# omniproto.net
KiCad netlist of a schematic drawn in EAGLE
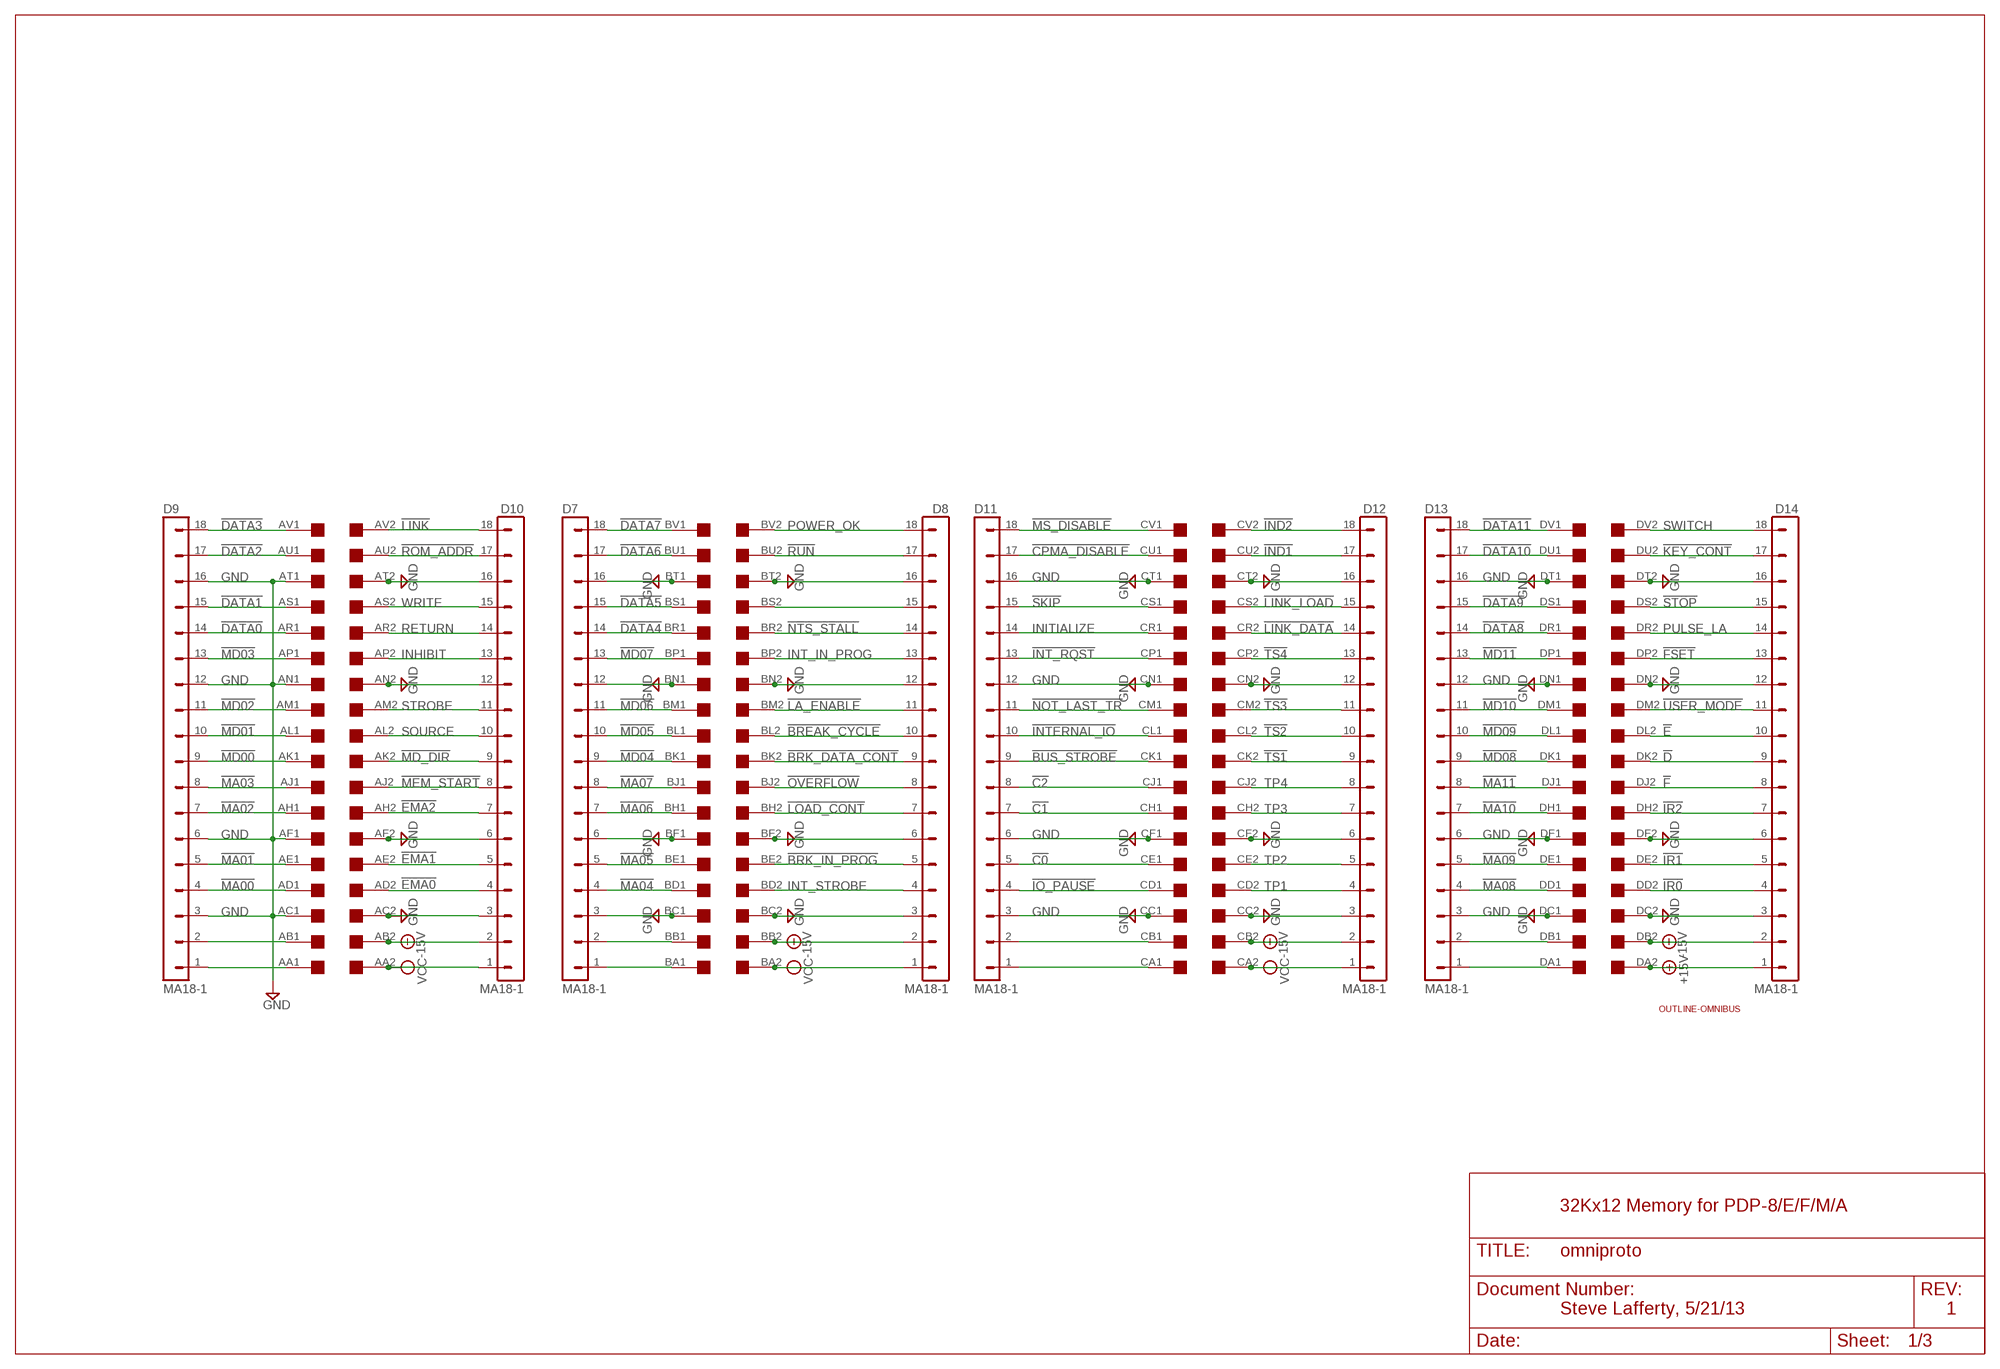
[diagram p0: schematic, sheet 1]
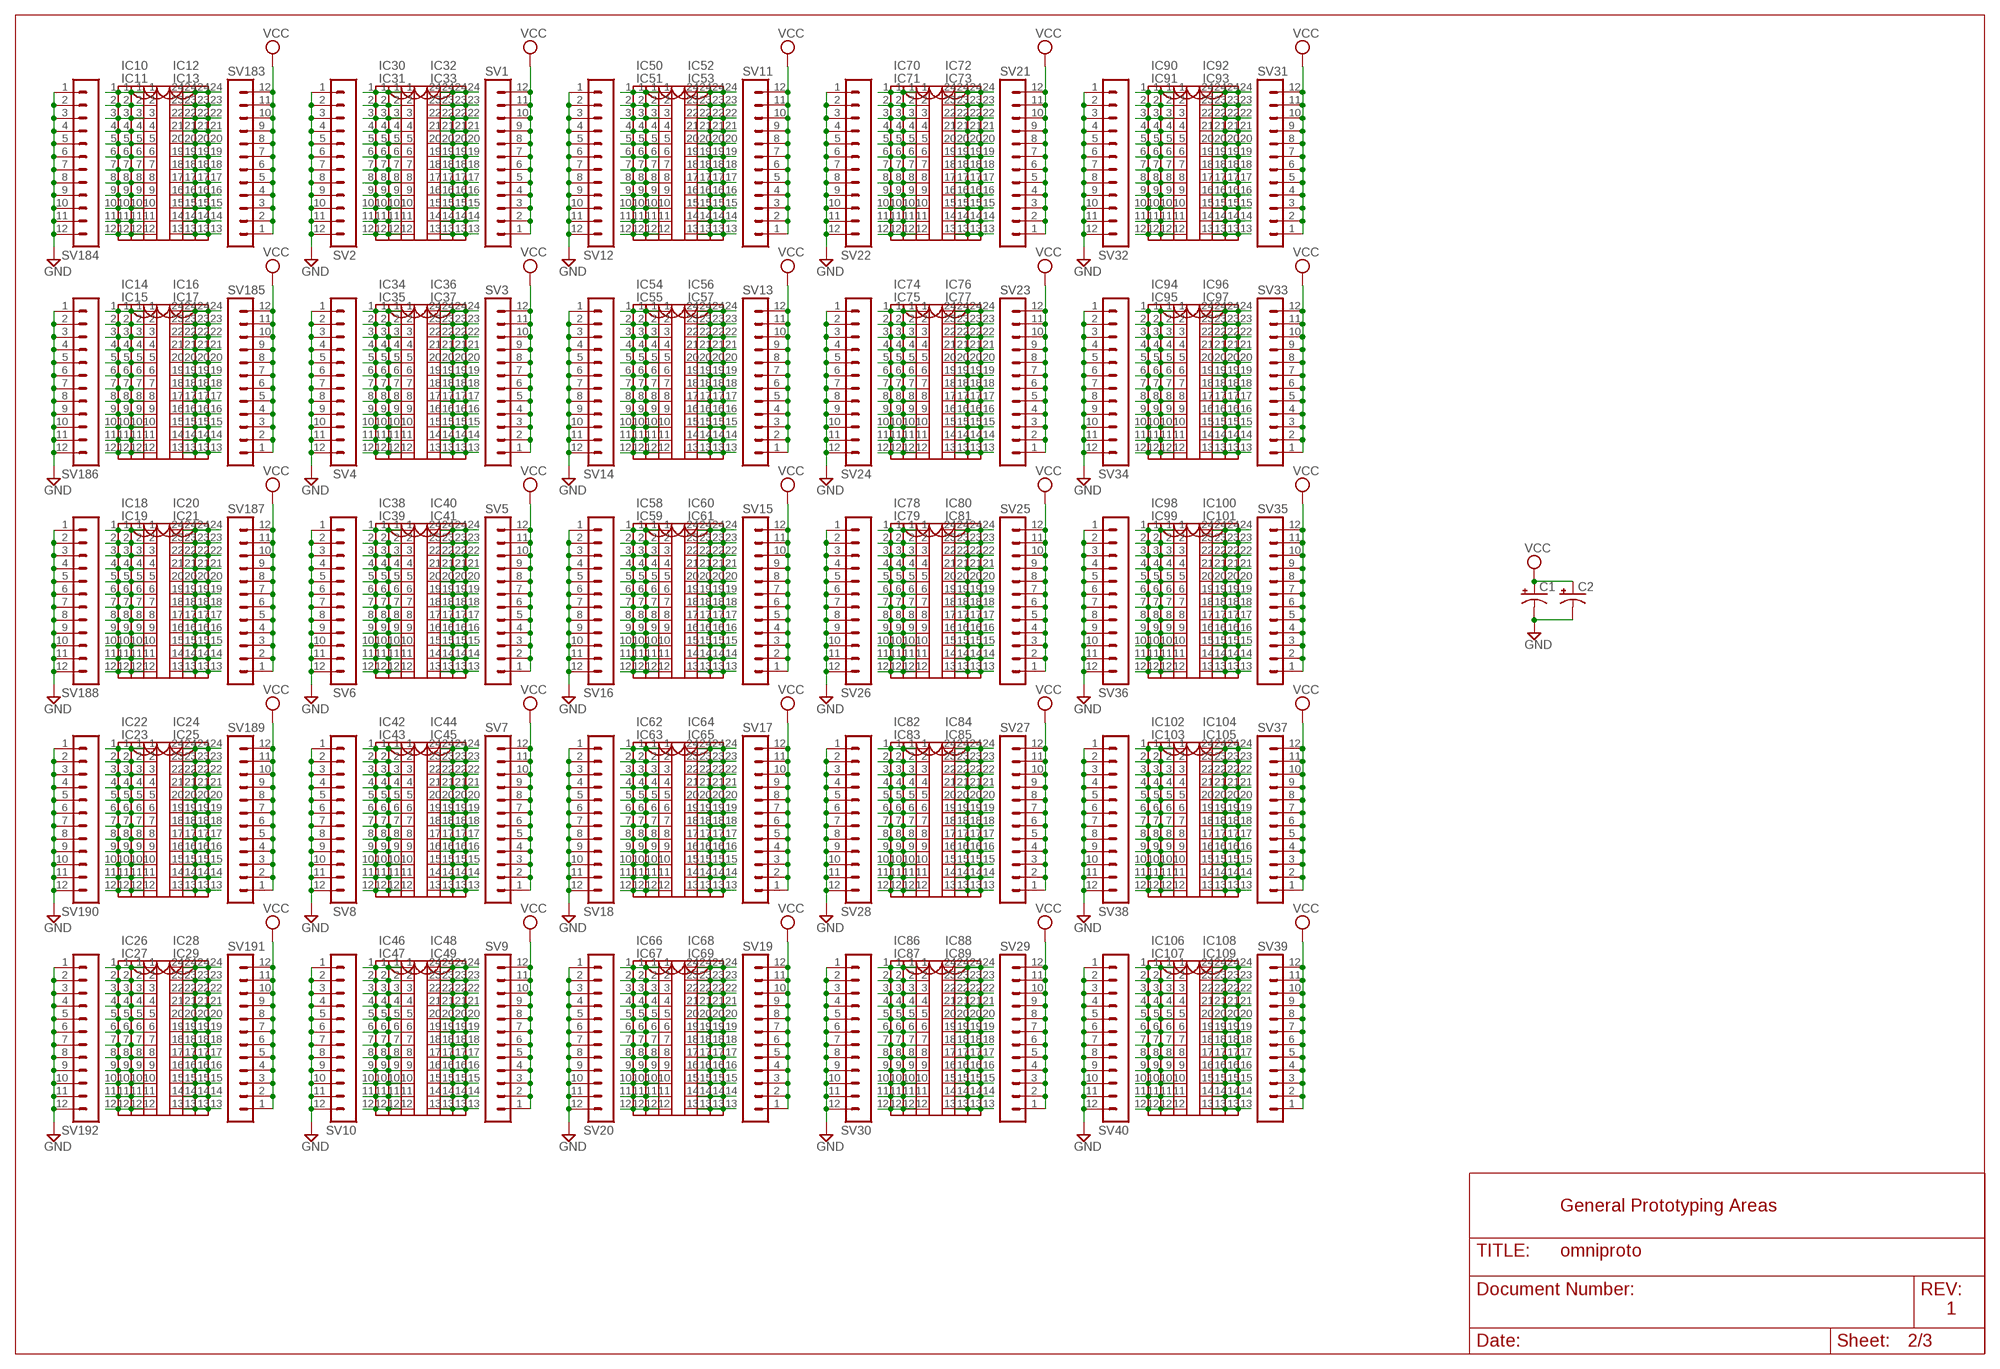
[diagram p1: schematic, sheet 2]
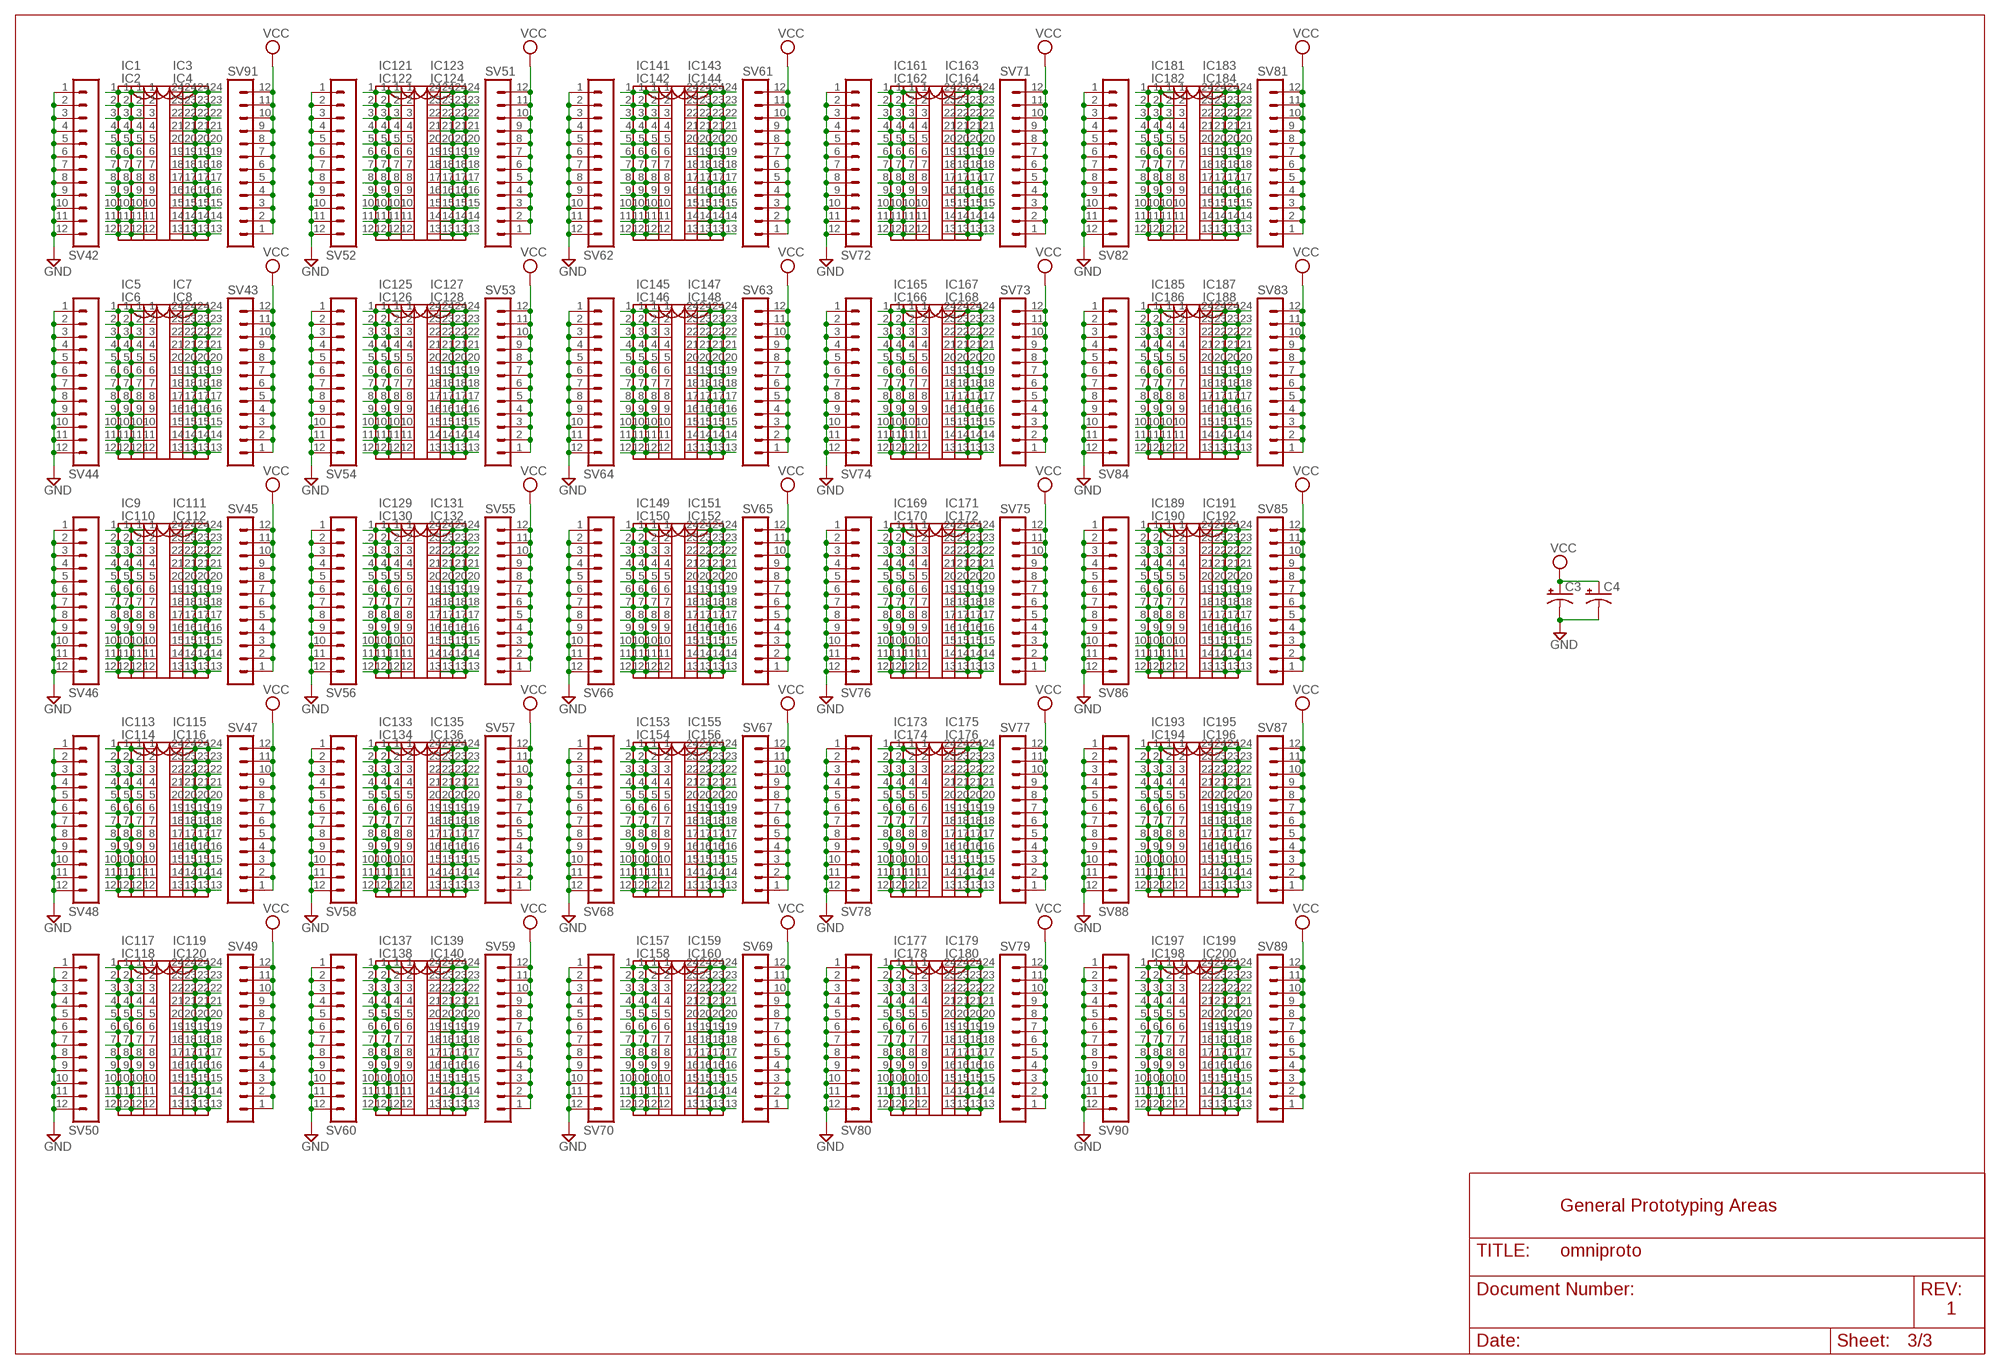
[diagram p2: schematic, sheet 3]

(export (version "E")
  (design (tool "Eeschema 10.0.6"))
  (components
    (comp (ref "D7")
      (value "MA18-1")
      (footprint "eagle-import:MA18-1")
      (libsource (lib "eagle-import") (part "MA18-1"))
    )
    (comp (ref "D8")
      (value "MA18-1")
      (footprint "eagle-import:MA18-1")
      (libsource (lib "eagle-import") (part "MA18-1"))
    )
    (comp (ref "D9")
      (value "MA18-1")
      (footprint "eagle-import:MA18-1")
      (libsource (lib "eagle-import") (part "MA18-1"))
    )
    (comp (ref "D10")
      (value "MA18-1")
      (footprint "eagle-import:MA18-1")
      (libsource (lib "eagle-import") (part "MA18-1"))
    )
    (comp (ref "D11")
      (value "MA18-1")
      (footprint "eagle-import:MA18-1")
      (libsource (lib "eagle-import") (part "MA18-1"))
    )
    (comp (ref "D12")
      (value "MA18-1")
      (footprint "eagle-import:MA18-1")
      (libsource (lib "eagle-import") (part "MA18-1"))
    )
    (comp (ref "D13")
      (value "MA18-1")
      (footprint "eagle-import:MA18-1")
      (libsource (lib "eagle-import") (part "MA18-1"))
    )
    (comp (ref "D14")
      (value "MA18-1")
      (footprint "eagle-import:MA18-1")
      (libsource (lib "eagle-import") (part "MA18-1"))
    )
    (comp (ref "U$1")
      (value "OUTLINE-OMNIBUS")
      (footprint "eagle-import:OMNIBUS")
      (libsource (lib "eagle-import") (part "OUTLINE-OMNIBUS"))
    )
    (comp (ref "U$2")
      (value "QUAD")
      (footprint "eagle-import:EDGE-CON8")
      (libsource (lib "eagle-import") (part "QUAD"))
    )
    (comp (ref "C3")
      (value "CPOL-USE20-8AXIAL")
      (footprint "eagle-import:E12-8")
      (libsource (lib "eagle-import") (part "CPOL-USE20-8AXIAL"))
    )
    (comp (ref "C4")
      (value "CPOL-USE20-8AXIAL")
      (footprint "eagle-import:E12-8")
      (libsource (lib "eagle-import") (part "CPOL-USE20-8AXIAL"))
    )
    (comp (ref "IC1")
      (value "DIL24-3")
      (footprint "eagle-import:DIL24-3")
      (libsource (lib "eagle-import") (part "DIL24-3"))
    )
    (comp (ref "IC2")
      (value "DIL24-6")
      (footprint "eagle-import:DIL24-6")
      (libsource (lib "eagle-import") (part "DIL24-6"))
    )
    (comp (ref "IC3")
      (value "DIL24-9")
      (footprint "eagle-import:DIL24-9")
      (libsource (lib "eagle-import") (part "DIL24-9"))
    )
    (comp (ref "IC4")
      (value "DIL24-6")
      (footprint "eagle-import:DIL24-6")
      (libsource (lib "eagle-import") (part "DIL24-6"))
    )
    (comp (ref "IC5")
      (value "DIL24-3")
      (footprint "eagle-import:DIL24-3")
      (libsource (lib "eagle-import") (part "DIL24-3"))
    )
    (comp (ref "IC6")
      (value "DIL24-6")
      (footprint "eagle-import:DIL24-6")
      (libsource (lib "eagle-import") (part "DIL24-6"))
    )
    (comp (ref "IC7")
      (value "DIL24-9")
      (footprint "eagle-import:DIL24-9")
      (libsource (lib "eagle-import") (part "DIL24-9"))
    )
    (comp (ref "IC8")
      (value "DIL24-6")
      (footprint "eagle-import:DIL24-6")
      (libsource (lib "eagle-import") (part "DIL24-6"))
    )
    (comp (ref "IC9")
      (value "DIL24-3")
      (footprint "eagle-import:DIL24-3")
      (libsource (lib "eagle-import") (part "DIL24-3"))
    )
    (comp (ref "IC110")
      (value "DIL24-6")
      (footprint "eagle-import:DIL24-6")
      (libsource (lib "eagle-import") (part "DIL24-6"))
    )
    (comp (ref "IC111")
      (value "DIL24-9")
      (footprint "eagle-import:DIL24-9")
      (libsource (lib "eagle-import") (part "DIL24-9"))
    )
    (comp (ref "IC112")
      (value "DIL24-6")
      (footprint "eagle-import:DIL24-6")
      (libsource (lib "eagle-import") (part "DIL24-6"))
    )
    (comp (ref "IC113")
      (value "DIL24-3")
      (footprint "eagle-import:DIL24-3")
      (libsource (lib "eagle-import") (part "DIL24-3"))
    )
    (comp (ref "IC114")
      (value "DIL24-6")
      (footprint "eagle-import:DIL24-6")
      (libsource (lib "eagle-import") (part "DIL24-6"))
    )
    (comp (ref "IC115")
      (value "DIL24-9")
      (footprint "eagle-import:DIL24-9")
      (libsource (lib "eagle-import") (part "DIL24-9"))
    )
    (comp (ref "IC116")
      (value "DIL24-6")
      (footprint "eagle-import:DIL24-6")
      (libsource (lib "eagle-import") (part "DIL24-6"))
    )
    (comp (ref "IC117")
      (value "DIL24-3")
      (footprint "eagle-import:DIL24-3")
      (libsource (lib "eagle-import") (part "DIL24-3"))
    )
    (comp (ref "IC118")
      (value "DIL24-6")
      (footprint "eagle-import:DIL24-6")
      (libsource (lib "eagle-import") (part "DIL24-6"))
    )
    (comp (ref "IC119")
      (value "DIL24-9")
      (footprint "eagle-import:DIL24-9")
      (libsource (lib "eagle-import") (part "DIL24-9"))
    )
    (comp (ref "IC120")
      (value "DIL24-6")
      (footprint "eagle-import:DIL24-6")
      (libsource (lib "eagle-import") (part "DIL24-6"))
    )
    (comp (ref "IC121")
      (value "DIL24-3")
      (footprint "eagle-import:DIL24-3")
      (libsource (lib "eagle-import") (part "DIL24-3"))
    )
    (comp (ref "IC122")
      (value "DIL24-6")
      (footprint "eagle-import:DIL24-6")
      (libsource (lib "eagle-import") (part "DIL24-6"))
    )
    (comp (ref "IC123")
      (value "DIL24-9")
      (footprint "eagle-import:DIL24-9")
      (libsource (lib "eagle-import") (part "DIL24-9"))
    )
    (comp (ref "IC124")
      (value "DIL24-6")
      (footprint "eagle-import:DIL24-6")
      (libsource (lib "eagle-import") (part "DIL24-6"))
    )
    (comp (ref "IC125")
      (value "DIL24-3")
      (footprint "eagle-import:DIL24-3")
      (libsource (lib "eagle-import") (part "DIL24-3"))
    )
    (comp (ref "IC126")
      (value "DIL24-6")
      (footprint "eagle-import:DIL24-6")
      (libsource (lib "eagle-import") (part "DIL24-6"))
    )
    (comp (ref "IC127")
      (value "DIL24-9")
      (footprint "eagle-import:DIL24-9")
      (libsource (lib "eagle-import") (part "DIL24-9"))
    )
    (comp (ref "IC128")
      (value "DIL24-6")
      (footprint "eagle-import:DIL24-6")
      (libsource (lib "eagle-import") (part "DIL24-6"))
    )
    (comp (ref "IC129")
      (value "DIL24-3")
      (footprint "eagle-import:DIL24-3")
      (libsource (lib "eagle-import") (part "DIL24-3"))
    )
    (comp (ref "IC130")
      (value "DIL24-6")
      (footprint "eagle-import:DIL24-6")
      (libsource (lib "eagle-import") (part "DIL24-6"))
    )
    (comp (ref "IC131")
      (value "DIL24-9")
      (footprint "eagle-import:DIL24-9")
      (libsource (lib "eagle-import") (part "DIL24-9"))
    )
    (comp (ref "IC132")
      (value "DIL24-6")
      (footprint "eagle-import:DIL24-6")
      (libsource (lib "eagle-import") (part "DIL24-6"))
    )
    (comp (ref "IC133")
      (value "DIL24-3")
      (footprint "eagle-import:DIL24-3")
      (libsource (lib "eagle-import") (part "DIL24-3"))
    )
    (comp (ref "IC134")
      (value "DIL24-6")
      (footprint "eagle-import:DIL24-6")
      (libsource (lib "eagle-import") (part "DIL24-6"))
    )
    (comp (ref "IC135")
      (value "DIL24-9")
      (footprint "eagle-import:DIL24-9")
      (libsource (lib "eagle-import") (part "DIL24-9"))
    )
    (comp (ref "IC136")
      (value "DIL24-6")
      (footprint "eagle-import:DIL24-6")
      (libsource (lib "eagle-import") (part "DIL24-6"))
    )
    (comp (ref "IC137")
      (value "DIL24-3")
      (footprint "eagle-import:DIL24-3")
      (libsource (lib "eagle-import") (part "DIL24-3"))
    )
    (comp (ref "IC138")
      (value "DIL24-6")
      (footprint "eagle-import:DIL24-6")
      (libsource (lib "eagle-import") (part "DIL24-6"))
    )
    (comp (ref "IC139")
      (value "DIL24-9")
      (footprint "eagle-import:DIL24-9")
      (libsource (lib "eagle-import") (part "DIL24-9"))
    )
    (comp (ref "IC140")
      (value "DIL24-6")
      (footprint "eagle-import:DIL24-6")
      (libsource (lib "eagle-import") (part "DIL24-6"))
    )
    (comp (ref "IC141")
      (value "DIL24-3")
      (footprint "eagle-import:DIL24-3")
      (libsource (lib "eagle-import") (part "DIL24-3"))
    )
    (comp (ref "IC142")
      (value "DIL24-6")
      (footprint "eagle-import:DIL24-6")
      (libsource (lib "eagle-import") (part "DIL24-6"))
    )
    (comp (ref "IC143")
      (value "DIL24-9")
      (footprint "eagle-import:DIL24-9")
      (libsource (lib "eagle-import") (part "DIL24-9"))
    )
    (comp (ref "IC144")
      (value "DIL24-6")
      (footprint "eagle-import:DIL24-6")
      (libsource (lib "eagle-import") (part "DIL24-6"))
    )
    (comp (ref "IC145")
      (value "DIL24-3")
      (footprint "eagle-import:DIL24-3")
      (libsource (lib "eagle-import") (part "DIL24-3"))
    )
    (comp (ref "IC146")
      (value "DIL24-6")
      (footprint "eagle-import:DIL24-6")
      (libsource (lib "eagle-import") (part "DIL24-6"))
    )
    (comp (ref "IC147")
      (value "DIL24-9")
      (footprint "eagle-import:DIL24-9")
      (libsource (lib "eagle-import") (part "DIL24-9"))
    )
    (comp (ref "IC148")
      (value "DIL24-6")
      (footprint "eagle-import:DIL24-6")
      (libsource (lib "eagle-import") (part "DIL24-6"))
    )
    (comp (ref "IC149")
      (value "DIL24-3")
      (footprint "eagle-import:DIL24-3")
      (libsource (lib "eagle-import") (part "DIL24-3"))
    )
    (comp (ref "IC150")
      (value "DIL24-6")
      (footprint "eagle-import:DIL24-6")
      (libsource (lib "eagle-import") (part "DIL24-6"))
    )
    (comp (ref "IC151")
      (value "DIL24-9")
      (footprint "eagle-import:DIL24-9")
      (libsource (lib "eagle-import") (part "DIL24-9"))
    )
    (comp (ref "IC152")
      (value "DIL24-6")
      (footprint "eagle-import:DIL24-6")
      (libsource (lib "eagle-import") (part "DIL24-6"))
    )
    (comp (ref "IC153")
      (value "DIL24-3")
      (footprint "eagle-import:DIL24-3")
      (libsource (lib "eagle-import") (part "DIL24-3"))
    )
    (comp (ref "IC154")
      (value "DIL24-6")
      (footprint "eagle-import:DIL24-6")
      (libsource (lib "eagle-import") (part "DIL24-6"))
    )
    (comp (ref "IC155")
      (value "DIL24-9")
      (footprint "eagle-import:DIL24-9")
      (libsource (lib "eagle-import") (part "DIL24-9"))
    )
    (comp (ref "IC156")
      (value "DIL24-6")
      (footprint "eagle-import:DIL24-6")
      (libsource (lib "eagle-import") (part "DIL24-6"))
    )
    (comp (ref "IC157")
      (value "DIL24-3")
      (footprint "eagle-import:DIL24-3")
      (libsource (lib "eagle-import") (part "DIL24-3"))
    )
    (comp (ref "IC158")
      (value "DIL24-6")
      (footprint "eagle-import:DIL24-6")
      (libsource (lib "eagle-import") (part "DIL24-6"))
    )
    (comp (ref "IC159")
      (value "DIL24-9")
      (footprint "eagle-import:DIL24-9")
      (libsource (lib "eagle-import") (part "DIL24-9"))
    )
    (comp (ref "IC160")
      (value "DIL24-6")
      (footprint "eagle-import:DIL24-6")
      (libsource (lib "eagle-import") (part "DIL24-6"))
    )
    (comp (ref "IC161")
      (value "DIL24-3")
      (footprint "eagle-import:DIL24-3")
      (libsource (lib "eagle-import") (part "DIL24-3"))
    )
    (comp (ref "IC162")
      (value "DIL24-6")
      (footprint "eagle-import:DIL24-6")
      (libsource (lib "eagle-import") (part "DIL24-6"))
    )
    (comp (ref "IC163")
      (value "DIL24-9")
      (footprint "eagle-import:DIL24-9")
      (libsource (lib "eagle-import") (part "DIL24-9"))
    )
    (comp (ref "IC164")
      (value "DIL24-6")
      (footprint "eagle-import:DIL24-6")
      (libsource (lib "eagle-import") (part "DIL24-6"))
    )
    (comp (ref "IC165")
      (value "DIL24-3")
      (footprint "eagle-import:DIL24-3")
      (libsource (lib "eagle-import") (part "DIL24-3"))
    )
    (comp (ref "IC166")
      (value "DIL24-6")
      (footprint "eagle-import:DIL24-6")
      (libsource (lib "eagle-import") (part "DIL24-6"))
    )
    (comp (ref "IC167")
      (value "DIL24-9")
      (footprint "eagle-import:DIL24-9")
      (libsource (lib "eagle-import") (part "DIL24-9"))
    )
    (comp (ref "IC168")
      (value "DIL24-6")
      (footprint "eagle-import:DIL24-6")
      (libsource (lib "eagle-import") (part "DIL24-6"))
    )
    (comp (ref "IC169")
      (value "DIL24-3")
      (footprint "eagle-import:DIL24-3")
      (libsource (lib "eagle-import") (part "DIL24-3"))
    )
    (comp (ref "IC170")
      (value "DIL24-6")
      (footprint "eagle-import:DIL24-6")
      (libsource (lib "eagle-import") (part "DIL24-6"))
    )
    (comp (ref "IC171")
      (value "DIL24-9")
      (footprint "eagle-import:DIL24-9")
      (libsource (lib "eagle-import") (part "DIL24-9"))
    )
    (comp (ref "IC172")
      (value "DIL24-6")
      (footprint "eagle-import:DIL24-6")
      (libsource (lib "eagle-import") (part "DIL24-6"))
    )
    (comp (ref "IC173")
      (value "DIL24-3")
      (footprint "eagle-import:DIL24-3")
      (libsource (lib "eagle-import") (part "DIL24-3"))
    )
    (comp (ref "IC174")
      (value "DIL24-6")
      (footprint "eagle-import:DIL24-6")
      (libsource (lib "eagle-import") (part "DIL24-6"))
    )
    (comp (ref "IC175")
      (value "DIL24-9")
      (footprint "eagle-import:DIL24-9")
      (libsource (lib "eagle-import") (part "DIL24-9"))
    )
    (comp (ref "IC176")
      (value "DIL24-6")
      (footprint "eagle-import:DIL24-6")
      (libsource (lib "eagle-import") (part "DIL24-6"))
    )
    (comp (ref "IC177")
      (value "DIL24-3")
      (footprint "eagle-import:DIL24-3")
      (libsource (lib "eagle-import") (part "DIL24-3"))
    )
    (comp (ref "IC178")
      (value "DIL24-6")
      (footprint "eagle-import:DIL24-6")
      (libsource (lib "eagle-import") (part "DIL24-6"))
    )
    (comp (ref "IC179")
      (value "DIL24-9")
      (footprint "eagle-import:DIL24-9")
      (libsource (lib "eagle-import") (part "DIL24-9"))
    )
    (comp (ref "IC180")
      (value "DIL24-6")
      (footprint "eagle-import:DIL24-6")
      (libsource (lib "eagle-import") (part "DIL24-6"))
    )
    (comp (ref "IC181")
      (value "DIL24-3")
      (footprint "eagle-import:DIL24-3")
      (libsource (lib "eagle-import") (part "DIL24-3"))
    )
    (comp (ref "IC182")
      (value "DIL24-6")
      (footprint "eagle-import:DIL24-6")
      (libsource (lib "eagle-import") (part "DIL24-6"))
    )
    (comp (ref "IC183")
      (value "DIL24-9")
      (footprint "eagle-import:DIL24-9")
      (libsource (lib "eagle-import") (part "DIL24-9"))
    )
    (comp (ref "IC184")
      (value "DIL24-6")
      (footprint "eagle-import:DIL24-6")
      (libsource (lib "eagle-import") (part "DIL24-6"))
    )
    (comp (ref "IC185")
      (value "DIL24-3")
      (footprint "eagle-import:DIL24-3")
      (libsource (lib "eagle-import") (part "DIL24-3"))
    )
    (comp (ref "IC186")
      (value "DIL24-6")
      (footprint "eagle-import:DIL24-6")
      (libsource (lib "eagle-import") (part "DIL24-6"))
    )
    (comp (ref "IC187")
      (value "DIL24-9")
      (footprint "eagle-import:DIL24-9")
      (libsource (lib "eagle-import") (part "DIL24-9"))
    )
    (comp (ref "IC188")
      (value "DIL24-6")
      (footprint "eagle-import:DIL24-6")
      (libsource (lib "eagle-import") (part "DIL24-6"))
    )
    (comp (ref "IC189")
      (value "DIL24-3")
      (footprint "eagle-import:DIL24-3")
      (libsource (lib "eagle-import") (part "DIL24-3"))
    )
    (comp (ref "IC190")
      (value "DIL24-6")
      (footprint "eagle-import:DIL24-6")
      (libsource (lib "eagle-import") (part "DIL24-6"))
    )
    (comp (ref "IC191")
      (value "DIL24-9")
      (footprint "eagle-import:DIL24-9")
      (libsource (lib "eagle-import") (part "DIL24-9"))
    )
    (comp (ref "IC192")
      (value "DIL24-6")
      (footprint "eagle-import:DIL24-6")
      (libsource (lib "eagle-import") (part "DIL24-6"))
    )
    (comp (ref "IC193")
      (value "DIL24-3")
      (footprint "eagle-import:DIL24-3")
      (libsource (lib "eagle-import") (part "DIL24-3"))
    )
    (comp (ref "IC194")
      (value "DIL24-6")
      (footprint "eagle-import:DIL24-6")
      (libsource (lib "eagle-import") (part "DIL24-6"))
    )
    (comp (ref "IC195")
      (value "DIL24-9")
      (footprint "eagle-import:DIL24-9")
      (libsource (lib "eagle-import") (part "DIL24-9"))
    )
    (comp (ref "IC196")
      (value "DIL24-6")
      (footprint "eagle-import:DIL24-6")
      (libsource (lib "eagle-import") (part "DIL24-6"))
    )
    (comp (ref "IC197")
      (value "DIL24-3")
      (footprint "eagle-import:DIL24-3")
      (libsource (lib "eagle-import") (part "DIL24-3"))
    )
    (comp (ref "IC198")
      (value "DIL24-6")
      (footprint "eagle-import:DIL24-6")
      (libsource (lib "eagle-import") (part "DIL24-6"))
    )
    (comp (ref "IC199")
      (value "DIL24-9")
      (footprint "eagle-import:DIL24-9")
      (libsource (lib "eagle-import") (part "DIL24-9"))
    )
    (comp (ref "IC200")
      (value "DIL24-6")
      (footprint "eagle-import:DIL24-6")
      (libsource (lib "eagle-import") (part "DIL24-6"))
    )
    (comp (ref "SV42")
      (value "MA12-1")
      (footprint "eagle-import:MA12-1")
      (libsource (lib "eagle-import") (part "MA12-1"))
    )
    (comp (ref "SV43")
      (value "MA12-1")
      (footprint "eagle-import:MA12-1")
      (libsource (lib "eagle-import") (part "MA12-1"))
    )
    (comp (ref "SV44")
      (value "MA12-1")
      (footprint "eagle-import:MA12-1")
      (libsource (lib "eagle-import") (part "MA12-1"))
    )
    (comp (ref "SV45")
      (value "MA12-1")
      (footprint "eagle-import:MA12-1")
      (libsource (lib "eagle-import") (part "MA12-1"))
    )
    (comp (ref "SV46")
      (value "MA12-1")
      (footprint "eagle-import:MA12-1")
      (libsource (lib "eagle-import") (part "MA12-1"))
    )
    (comp (ref "SV47")
      (value "MA12-1")
      (footprint "eagle-import:MA12-1")
      (libsource (lib "eagle-import") (part "MA12-1"))
    )
    (comp (ref "SV48")
      (value "MA12-1")
      (footprint "eagle-import:MA12-1")
      (libsource (lib "eagle-import") (part "MA12-1"))
    )
    (comp (ref "SV49")
      (value "MA12-1")
      (footprint "eagle-import:MA12-1")
      (libsource (lib "eagle-import") (part "MA12-1"))
    )
    (comp (ref "SV50")
      (value "MA12-1")
      (footprint "eagle-import:MA12-1")
      (libsource (lib "eagle-import") (part "MA12-1"))
    )
    (comp (ref "SV51")
      (value "MA12-1")
      (footprint "eagle-import:MA12-1")
      (libsource (lib "eagle-import") (part "MA12-1"))
    )
    (comp (ref "SV52")
      (value "MA12-1")
      (footprint "eagle-import:MA12-1")
      (libsource (lib "eagle-import") (part "MA12-1"))
    )
    (comp (ref "SV53")
      (value "MA12-1")
      (footprint "eagle-import:MA12-1")
      (libsource (lib "eagle-import") (part "MA12-1"))
    )
    (comp (ref "SV54")
      (value "MA12-1")
      (footprint "eagle-import:MA12-1")
      (libsource (lib "eagle-import") (part "MA12-1"))
    )
    (comp (ref "SV55")
      (value "MA12-1")
      (footprint "eagle-import:MA12-1")
      (libsource (lib "eagle-import") (part "MA12-1"))
    )
    (comp (ref "SV56")
      (value "MA12-1")
      (footprint "eagle-import:MA12-1")
      (libsource (lib "eagle-import") (part "MA12-1"))
    )
    (comp (ref "SV57")
      (value "MA12-1")
      (footprint "eagle-import:MA12-1")
      (libsource (lib "eagle-import") (part "MA12-1"))
    )
    (comp (ref "SV58")
      (value "MA12-1")
      (footprint "eagle-import:MA12-1")
      (libsource (lib "eagle-import") (part "MA12-1"))
    )
    (comp (ref "SV59")
      (value "MA12-1")
      (footprint "eagle-import:MA12-1")
      (libsource (lib "eagle-import") (part "MA12-1"))
    )
    (comp (ref "SV60")
      (value "MA12-1")
      (footprint "eagle-import:MA12-1")
      (libsource (lib "eagle-import") (part "MA12-1"))
    )
    (comp (ref "SV61")
      (value "MA12-1")
      (footprint "eagle-import:MA12-1")
      (libsource (lib "eagle-import") (part "MA12-1"))
    )
    (comp (ref "SV62")
      (value "MA12-1")
      (footprint "eagle-import:MA12-1")
      (libsource (lib "eagle-import") (part "MA12-1"))
    )
    (comp (ref "SV63")
      (value "MA12-1")
      (footprint "eagle-import:MA12-1")
      (libsource (lib "eagle-import") (part "MA12-1"))
    )
    (comp (ref "SV64")
      (value "MA12-1")
      (footprint "eagle-import:MA12-1")
      (libsource (lib "eagle-import") (part "MA12-1"))
    )
    (comp (ref "SV65")
      (value "MA12-1")
      (footprint "eagle-import:MA12-1")
      (libsource (lib "eagle-import") (part "MA12-1"))
    )
    (comp (ref "SV66")
      (value "MA12-1")
      (footprint "eagle-import:MA12-1")
      (libsource (lib "eagle-import") (part "MA12-1"))
    )
    (comp (ref "SV67")
      (value "MA12-1")
      (footprint "eagle-import:MA12-1")
      (libsource (lib "eagle-import") (part "MA12-1"))
    )
    (comp (ref "SV68")
      (value "MA12-1")
      (footprint "eagle-import:MA12-1")
      (libsource (lib "eagle-import") (part "MA12-1"))
    )
    (comp (ref "SV69")
      (value "MA12-1")
      (footprint "eagle-import:MA12-1")
      (libsource (lib "eagle-import") (part "MA12-1"))
    )
    (comp (ref "SV70")
      (value "MA12-1")
      (footprint "eagle-import:MA12-1")
      (libsource (lib "eagle-import") (part "MA12-1"))
    )
    (comp (ref "SV71")
      (value "MA12-1")
      (footprint "eagle-import:MA12-1")
      (libsource (lib "eagle-import") (part "MA12-1"))
    )
    (comp (ref "SV72")
      (value "MA12-1")
      (footprint "eagle-import:MA12-1")
      (libsource (lib "eagle-import") (part "MA12-1"))
    )
    (comp (ref "SV73")
      (value "MA12-1")
      (footprint "eagle-import:MA12-1")
      (libsource (lib "eagle-import") (part "MA12-1"))
    )
    (comp (ref "SV74")
      (value "MA12-1")
      (footprint "eagle-import:MA12-1")
      (libsource (lib "eagle-import") (part "MA12-1"))
    )
    (comp (ref "SV75")
      (value "MA12-1")
      (footprint "eagle-import:MA12-1")
      (libsource (lib "eagle-import") (part "MA12-1"))
    )
    (comp (ref "SV76")
      (value "MA12-1")
      (footprint "eagle-import:MA12-1")
      (libsource (lib "eagle-import") (part "MA12-1"))
    )
    (comp (ref "SV77")
      (value "MA12-1")
      (footprint "eagle-import:MA12-1")
      (libsource (lib "eagle-import") (part "MA12-1"))
    )
    (comp (ref "SV78")
      (value "MA12-1")
      (footprint "eagle-import:MA12-1")
      (libsource (lib "eagle-import") (part "MA12-1"))
    )
    (comp (ref "SV79")
      (value "MA12-1")
      (footprint "eagle-import:MA12-1")
      (libsource (lib "eagle-import") (part "MA12-1"))
    )
    (comp (ref "SV80")
      (value "MA12-1")
      (footprint "eagle-import:MA12-1")
      (libsource (lib "eagle-import") (part "MA12-1"))
    )
    (comp (ref "SV81")
      (value "MA12-1")
      (footprint "eagle-import:MA12-1")
      (libsource (lib "eagle-import") (part "MA12-1"))
    )
    (comp (ref "SV82")
      (value "MA12-1")
      (footprint "eagle-import:MA12-1")
      (libsource (lib "eagle-import") (part "MA12-1"))
    )
    (comp (ref "SV83")
      (value "MA12-1")
      (footprint "eagle-import:MA12-1")
      (libsource (lib "eagle-import") (part "MA12-1"))
    )
    (comp (ref "SV84")
      (value "MA12-1")
      (footprint "eagle-import:MA12-1")
      (libsource (lib "eagle-import") (part "MA12-1"))
    )
    (comp (ref "SV85")
      (value "MA12-1")
      (footprint "eagle-import:MA12-1")
      (libsource (lib "eagle-import") (part "MA12-1"))
    )
    (comp (ref "SV86")
      (value "MA12-1")
      (footprint "eagle-import:MA12-1")
      (libsource (lib "eagle-import") (part "MA12-1"))
    )
    (comp (ref "SV87")
      (value "MA12-1")
      (footprint "eagle-import:MA12-1")
      (libsource (lib "eagle-import") (part "MA12-1"))
    )
    (comp (ref "SV88")
      (value "MA12-1")
      (footprint "eagle-import:MA12-1")
      (libsource (lib "eagle-import") (part "MA12-1"))
    )
    (comp (ref "SV89")
      (value "MA12-1")
      (footprint "eagle-import:MA12-1")
      (libsource (lib "eagle-import") (part "MA12-1"))
    )
    (comp (ref "SV90")
      (value "MA12-1")
      (footprint "eagle-import:MA12-1")
      (libsource (lib "eagle-import") (part "MA12-1"))
    )
    (comp (ref "SV91")
      (value "MA12-1")
      (footprint "eagle-import:MA12-1")
      (libsource (lib "eagle-import") (part "MA12-1"))
    )
    (comp (ref "C1")
      (value "CPOL-USE20-8AXIAL")
      (footprint "eagle-import:E12-8")
      (libsource (lib "eagle-import") (part "CPOL-USE20-8AXIAL"))
    )
    (comp (ref "C2")
      (value "CPOL-USE20-8AXIAL")
      (footprint "eagle-import:E12-8")
      (libsource (lib "eagle-import") (part "CPOL-USE20-8AXIAL"))
    )
    (comp (ref "IC10")
      (value "DIL24-3")
      (footprint "eagle-import:DIL24-3")
      (libsource (lib "eagle-import") (part "DIL24-3"))
    )
    (comp (ref "IC11")
      (value "DIL24-6")
      (footprint "eagle-import:DIL24-6")
      (libsource (lib "eagle-import") (part "DIL24-6"))
    )
    (comp (ref "IC12")
      (value "DIL24-9")
      (footprint "eagle-import:DIL24-9")
      (libsource (lib "eagle-import") (part "DIL24-9"))
    )
    (comp (ref "IC13")
      (value "DIL24-6")
      (footprint "eagle-import:DIL24-6")
      (libsource (lib "eagle-import") (part "DIL24-6"))
    )
    (comp (ref "IC14")
      (value "DIL24-3")
      (footprint "eagle-import:DIL24-3")
      (libsource (lib "eagle-import") (part "DIL24-3"))
    )
    (comp (ref "IC15")
      (value "DIL24-6")
      (footprint "eagle-import:DIL24-6")
      (libsource (lib "eagle-import") (part "DIL24-6"))
    )
    (comp (ref "IC16")
      (value "DIL24-9")
      (footprint "eagle-import:DIL24-9")
      (libsource (lib "eagle-import") (part "DIL24-9"))
    )
    (comp (ref "IC17")
      (value "DIL24-6")
      (footprint "eagle-import:DIL24-6")
      (libsource (lib "eagle-import") (part "DIL24-6"))
    )
    (comp (ref "IC18")
      (value "DIL24-3")
      (footprint "eagle-import:DIL24-3")
      (libsource (lib "eagle-import") (part "DIL24-3"))
    )
    (comp (ref "IC19")
      (value "DIL24-6")
      (footprint "eagle-import:DIL24-6")
      (libsource (lib "eagle-import") (part "DIL24-6"))
    )
    (comp (ref "IC20")
      (value "DIL24-9")
      (footprint "eagle-import:DIL24-9")
      (libsource (lib "eagle-import") (part "DIL24-9"))
    )
    (comp (ref "IC21")
      (value "DIL24-6")
      (footprint "eagle-import:DIL24-6")
      (libsource (lib "eagle-import") (part "DIL24-6"))
    )
    (comp (ref "IC22")
      (value "DIL24-3")
      (footprint "eagle-import:DIL24-3")
      (libsource (lib "eagle-import") (part "DIL24-3"))
    )
    (comp (ref "IC23")
      (value "DIL24-6")
      (footprint "eagle-import:DIL24-6")
      (libsource (lib "eagle-import") (part "DIL24-6"))
    )
    (comp (ref "IC24")
      (value "DIL24-9")
      (footprint "eagle-import:DIL24-9")
      (libsource (lib "eagle-import") (part "DIL24-9"))
    )
    (comp (ref "IC25")
      (value "DIL24-6")
      (footprint "eagle-import:DIL24-6")
      (libsource (lib "eagle-import") (part "DIL24-6"))
    )
    (comp (ref "IC26")
      (value "DIL24-3")
      (footprint "eagle-import:DIL24-3")
      (libsource (lib "eagle-import") (part "DIL24-3"))
    )
    (comp (ref "IC27")
      (value "DIL24-6")
      (footprint "eagle-import:DIL24-6")
      (libsource (lib "eagle-import") (part "DIL24-6"))
    )
    (comp (ref "IC28")
      (value "DIL24-9")
      (footprint "eagle-import:DIL24-9")
      (libsource (lib "eagle-import") (part "DIL24-9"))
    )
    (comp (ref "IC29")
      (value "DIL24-6")
      (footprint "eagle-import:DIL24-6")
      (libsource (lib "eagle-import") (part "DIL24-6"))
    )
    (comp (ref "IC30")
      (value "DIL24-3")
      (footprint "eagle-import:DIL24-3")
      (libsource (lib "eagle-import") (part "DIL24-3"))
    )
    (comp (ref "IC31")
      (value "DIL24-6")
      (footprint "eagle-import:DIL24-6")
      (libsource (lib "eagle-import") (part "DIL24-6"))
    )
    (comp (ref "IC32")
      (value "DIL24-9")
      (footprint "eagle-import:DIL24-9")
      (libsource (lib "eagle-import") (part "DIL24-9"))
    )
    (comp (ref "IC33")
      (value "DIL24-6")
      (footprint "eagle-import:DIL24-6")
      (libsource (lib "eagle-import") (part "DIL24-6"))
    )
    (comp (ref "IC34")
      (value "DIL24-3")
      (footprint "eagle-import:DIL24-3")
      (libsource (lib "eagle-import") (part "DIL24-3"))
    )
    (comp (ref "IC35")
      (value "DIL24-6")
      (footprint "eagle-import:DIL24-6")
      (libsource (lib "eagle-import") (part "DIL24-6"))
    )
    (comp (ref "IC36")
      (value "DIL24-9")
      (footprint "eagle-import:DIL24-9")
      (libsource (lib "eagle-import") (part "DIL24-9"))
    )
    (comp (ref "IC37")
      (value "DIL24-6")
      (footprint "eagle-import:DIL24-6")
      (libsource (lib "eagle-import") (part "DIL24-6"))
    )
    (comp (ref "IC38")
      (value "DIL24-3")
      (footprint "eagle-import:DIL24-3")
      (libsource (lib "eagle-import") (part "DIL24-3"))
    )
    (comp (ref "IC39")
      (value "DIL24-6")
      (footprint "eagle-import:DIL24-6")
      (libsource (lib "eagle-import") (part "DIL24-6"))
    )
    (comp (ref "IC40")
      (value "DIL24-9")
      (footprint "eagle-import:DIL24-9")
      (libsource (lib "eagle-import") (part "DIL24-9"))
    )
    (comp (ref "IC41")
      (value "DIL24-6")
      (footprint "eagle-import:DIL24-6")
      (libsource (lib "eagle-import") (part "DIL24-6"))
    )
    (comp (ref "IC42")
      (value "DIL24-3")
      (footprint "eagle-import:DIL24-3")
      (libsource (lib "eagle-import") (part "DIL24-3"))
    )
    (comp (ref "IC43")
      (value "DIL24-6")
      (footprint "eagle-import:DIL24-6")
      (libsource (lib "eagle-import") (part "DIL24-6"))
    )
    (comp (ref "IC44")
      (value "DIL24-9")
      (footprint "eagle-import:DIL24-9")
      (libsource (lib "eagle-import") (part "DIL24-9"))
    )
    (comp (ref "IC45")
      (value "DIL24-6")
      (footprint "eagle-import:DIL24-6")
      (libsource (lib "eagle-import") (part "DIL24-6"))
    )
    (comp (ref "IC46")
      (value "DIL24-3")
      (footprint "eagle-import:DIL24-3")
      (libsource (lib "eagle-import") (part "DIL24-3"))
    )
    (comp (ref "IC47")
      (value "DIL24-6")
      (footprint "eagle-import:DIL24-6")
      (libsource (lib "eagle-import") (part "DIL24-6"))
    )
    (comp (ref "IC48")
      (value "DIL24-9")
      (footprint "eagle-import:DIL24-9")
      (libsource (lib "eagle-import") (part "DIL24-9"))
    )
    (comp (ref "IC49")
      (value "DIL24-6")
      (footprint "eagle-import:DIL24-6")
      (libsource (lib "eagle-import") (part "DIL24-6"))
    )
    (comp (ref "IC50")
      (value "DIL24-3")
      (footprint "eagle-import:DIL24-3")
      (libsource (lib "eagle-import") (part "DIL24-3"))
    )
    (comp (ref "IC51")
      (value "DIL24-6")
      (footprint "eagle-import:DIL24-6")
      (libsource (lib "eagle-import") (part "DIL24-6"))
    )
    (comp (ref "IC52")
      (value "DIL24-9")
      (footprint "eagle-import:DIL24-9")
      (libsource (lib "eagle-import") (part "DIL24-9"))
    )
    (comp (ref "IC53")
      (value "DIL24-6")
      (footprint "eagle-import:DIL24-6")
      (libsource (lib "eagle-import") (part "DIL24-6"))
    )
    (comp (ref "IC54")
      (value "DIL24-3")
      (footprint "eagle-import:DIL24-3")
      (libsource (lib "eagle-import") (part "DIL24-3"))
    )
    (comp (ref "IC55")
      (value "DIL24-6")
      (footprint "eagle-import:DIL24-6")
      (libsource (lib "eagle-import") (part "DIL24-6"))
    )
    (comp (ref "IC56")
      (value "DIL24-9")
      (footprint "eagle-import:DIL24-9")
      (libsource (lib "eagle-import") (part "DIL24-9"))
    )
    (comp (ref "IC57")
      (value "DIL24-6")
      (footprint "eagle-import:DIL24-6")
      (libsource (lib "eagle-import") (part "DIL24-6"))
    )
    (comp (ref "IC58")
      (value "DIL24-3")
      (footprint "eagle-import:DIL24-3")
      (libsource (lib "eagle-import") (part "DIL24-3"))
    )
    (comp (ref "IC59")
      (value "DIL24-6")
      (footprint "eagle-import:DIL24-6")
      (libsource (lib "eagle-import") (part "DIL24-6"))
    )
    (comp (ref "IC60")
      (value "DIL24-9")
      (footprint "eagle-import:DIL24-9")
      (libsource (lib "eagle-import") (part "DIL24-9"))
    )
    (comp (ref "IC61")
      (value "DIL24-6")
      (footprint "eagle-import:DIL24-6")
      (libsource (lib "eagle-import") (part "DIL24-6"))
    )
    (comp (ref "IC62")
      (value "DIL24-3")
      (footprint "eagle-import:DIL24-3")
      (libsource (lib "eagle-import") (part "DIL24-3"))
    )
    (comp (ref "IC63")
      (value "DIL24-6")
      (footprint "eagle-import:DIL24-6")
      (libsource (lib "eagle-import") (part "DIL24-6"))
    )
    (comp (ref "IC64")
      (value "DIL24-9")
      (footprint "eagle-import:DIL24-9")
      (libsource (lib "eagle-import") (part "DIL24-9"))
    )
    (comp (ref "IC65")
      (value "DIL24-6")
      (footprint "eagle-import:DIL24-6")
      (libsource (lib "eagle-import") (part "DIL24-6"))
    )
    (comp (ref "IC66")
      (value "DIL24-3")
      (footprint "eagle-import:DIL24-3")
      (libsource (lib "eagle-import") (part "DIL24-3"))
    )
    (comp (ref "IC67")
      (value "DIL24-6")
      (footprint "eagle-import:DIL24-6")
      (libsource (lib "eagle-import") (part "DIL24-6"))
    )
    (comp (ref "IC68")
      (value "DIL24-9")
      (footprint "eagle-import:DIL24-9")
      (libsource (lib "eagle-import") (part "DIL24-9"))
    )
    (comp (ref "IC69")
      (value "DIL24-6")
      (footprint "eagle-import:DIL24-6")
      (libsource (lib "eagle-import") (part "DIL24-6"))
    )
    (comp (ref "IC70")
      (value "DIL24-3")
      (footprint "eagle-import:DIL24-3")
      (libsource (lib "eagle-import") (part "DIL24-3"))
    )
    (comp (ref "IC71")
      (value "DIL24-6")
      (footprint "eagle-import:DIL24-6")
      (libsource (lib "eagle-import") (part "DIL24-6"))
    )
    (comp (ref "IC72")
      (value "DIL24-9")
      (footprint "eagle-import:DIL24-9")
      (libsource (lib "eagle-import") (part "DIL24-9"))
    )
    (comp (ref "IC73")
      (value "DIL24-6")
      (footprint "eagle-import:DIL24-6")
      (libsource (lib "eagle-import") (part "DIL24-6"))
    )
    (comp (ref "IC74")
      (value "DIL24-3")
      (footprint "eagle-import:DIL24-3")
      (libsource (lib "eagle-import") (part "DIL24-3"))
    )
    (comp (ref "IC75")
      (value "DIL24-6")
      (footprint "eagle-import:DIL24-6")
      (libsource (lib "eagle-import") (part "DIL24-6"))
    )
    (comp (ref "IC76")
      (value "DIL24-9")
      (footprint "eagle-import:DIL24-9")
      (libsource (lib "eagle-import") (part "DIL24-9"))
    )
    (comp (ref "IC77")
      (value "DIL24-6")
      (footprint "eagle-import:DIL24-6")
      (libsource (lib "eagle-import") (part "DIL24-6"))
    )
    (comp (ref "IC78")
      (value "DIL24-3")
      (footprint "eagle-import:DIL24-3")
      (libsource (lib "eagle-import") (part "DIL24-3"))
    )
    (comp (ref "IC79")
      (value "DIL24-6")
      (footprint "eagle-import:DIL24-6")
      (libsource (lib "eagle-import") (part "DIL24-6"))
    )
    (comp (ref "IC80")
      (value "DIL24-9")
      (footprint "eagle-import:DIL24-9")
      (libsource (lib "eagle-import") (part "DIL24-9"))
    )
    (comp (ref "IC81")
      (value "DIL24-6")
      (footprint "eagle-import:DIL24-6")
      (libsource (lib "eagle-import") (part "DIL24-6"))
    )
    (comp (ref "IC82")
      (value "DIL24-3")
      (footprint "eagle-import:DIL24-3")
      (libsource (lib "eagle-import") (part "DIL24-3"))
    )
    (comp (ref "IC83")
      (value "DIL24-6")
      (footprint "eagle-import:DIL24-6")
      (libsource (lib "eagle-import") (part "DIL24-6"))
    )
    (comp (ref "IC84")
      (value "DIL24-9")
      (footprint "eagle-import:DIL24-9")
      (libsource (lib "eagle-import") (part "DIL24-9"))
    )
    (comp (ref "IC85")
      (value "DIL24-6")
      (footprint "eagle-import:DIL24-6")
      (libsource (lib "eagle-import") (part "DIL24-6"))
    )
    (comp (ref "IC86")
      (value "DIL24-3")
      (footprint "eagle-import:DIL24-3")
      (libsource (lib "eagle-import") (part "DIL24-3"))
    )
    (comp (ref "IC87")
      (value "DIL24-6")
      (footprint "eagle-import:DIL24-6")
      (libsource (lib "eagle-import") (part "DIL24-6"))
    )
    (comp (ref "IC88")
      (value "DIL24-9")
      (footprint "eagle-import:DIL24-9")
      (libsource (lib "eagle-import") (part "DIL24-9"))
    )
    (comp (ref "IC89")
      (value "DIL24-6")
      (footprint "eagle-import:DIL24-6")
      (libsource (lib "eagle-import") (part "DIL24-6"))
    )
    (comp (ref "IC90")
      (value "DIL24-3")
      (footprint "eagle-import:DIL24-3")
      (libsource (lib "eagle-import") (part "DIL24-3"))
    )
    (comp (ref "IC91")
      (value "DIL24-6")
      (footprint "eagle-import:DIL24-6")
      (libsource (lib "eagle-import") (part "DIL24-6"))
    )
    (comp (ref "IC92")
      (value "DIL24-9")
      (footprint "eagle-import:DIL24-9")
      (libsource (lib "eagle-import") (part "DIL24-9"))
    )
    (comp (ref "IC93")
      (value "DIL24-6")
      (footprint "eagle-import:DIL24-6")
      (libsource (lib "eagle-import") (part "DIL24-6"))
    )
    (comp (ref "IC94")
      (value "DIL24-3")
      (footprint "eagle-import:DIL24-3")
      (libsource (lib "eagle-import") (part "DIL24-3"))
    )
    (comp (ref "IC95")
      (value "DIL24-6")
      (footprint "eagle-import:DIL24-6")
      (libsource (lib "eagle-import") (part "DIL24-6"))
    )
    (comp (ref "IC96")
      (value "DIL24-9")
      (footprint "eagle-import:DIL24-9")
      (libsource (lib "eagle-import") (part "DIL24-9"))
    )
    (comp (ref "IC97")
      (value "DIL24-6")
      (footprint "eagle-import:DIL24-6")
      (libsource (lib "eagle-import") (part "DIL24-6"))
    )
    (comp (ref "IC98")
      (value "DIL24-3")
      (footprint "eagle-import:DIL24-3")
      (libsource (lib "eagle-import") (part "DIL24-3"))
    )
    (comp (ref "IC99")
      (value "DIL24-6")
      (footprint "eagle-import:DIL24-6")
      (libsource (lib "eagle-import") (part "DIL24-6"))
    )
    (comp (ref "IC100")
      (value "DIL24-9")
      (footprint "eagle-import:DIL24-9")
      (libsource (lib "eagle-import") (part "DIL24-9"))
    )
    (comp (ref "IC101")
      (value "DIL24-6")
      (footprint "eagle-import:DIL24-6")
      (libsource (lib "eagle-import") (part "DIL24-6"))
    )
    (comp (ref "IC102")
      (value "DIL24-3")
      (footprint "eagle-import:DIL24-3")
      (libsource (lib "eagle-import") (part "DIL24-3"))
    )
    (comp (ref "IC103")
      (value "DIL24-6")
      (footprint "eagle-import:DIL24-6")
      (libsource (lib "eagle-import") (part "DIL24-6"))
    )
    (comp (ref "IC104")
      (value "DIL24-9")
      (footprint "eagle-import:DIL24-9")
      (libsource (lib "eagle-import") (part "DIL24-9"))
    )
    (comp (ref "IC105")
      (value "DIL24-6")
      (footprint "eagle-import:DIL24-6")
      (libsource (lib "eagle-import") (part "DIL24-6"))
    )
    (comp (ref "IC106")
      (value "DIL24-3")
      (footprint "eagle-import:DIL24-3")
      (libsource (lib "eagle-import") (part "DIL24-3"))
    )
    (comp (ref "IC107")
      (value "DIL24-6")
      (footprint "eagle-import:DIL24-6")
      (libsource (lib "eagle-import") (part "DIL24-6"))
    )
    (comp (ref "IC108")
      (value "DIL24-9")
      (footprint "eagle-import:DIL24-9")
      (libsource (lib "eagle-import") (part "DIL24-9"))
    )
    (comp (ref "IC109")
      (value "DIL24-6")
      (footprint "eagle-import:DIL24-6")
      (libsource (lib "eagle-import") (part "DIL24-6"))
    )
    (comp (ref "SV1")
      (value "MA12-1")
      (footprint "eagle-import:MA12-1")
      (libsource (lib "eagle-import") (part "MA12-1"))
    )
    (comp (ref "SV2")
      (value "MA12-1")
      (footprint "eagle-import:MA12-1")
      (libsource (lib "eagle-import") (part "MA12-1"))
    )
    (comp (ref "SV3")
      (value "MA12-1")
      (footprint "eagle-import:MA12-1")
      (libsource (lib "eagle-import") (part "MA12-1"))
    )
    (comp (ref "SV4")
      (value "MA12-1")
      (footprint "eagle-import:MA12-1")
      (libsource (lib "eagle-import") (part "MA12-1"))
    )
    (comp (ref "SV5")
      (value "MA12-1")
      (footprint "eagle-import:MA12-1")
      (libsource (lib "eagle-import") (part "MA12-1"))
    )
    (comp (ref "SV6")
      (value "MA12-1")
      (footprint "eagle-import:MA12-1")
      (libsource (lib "eagle-import") (part "MA12-1"))
    )
    (comp (ref "SV7")
      (value "MA12-1")
      (footprint "eagle-import:MA12-1")
      (libsource (lib "eagle-import") (part "MA12-1"))
    )
    (comp (ref "SV8")
      (value "MA12-1")
      (footprint "eagle-import:MA12-1")
      (libsource (lib "eagle-import") (part "MA12-1"))
    )
    (comp (ref "SV9")
      (value "MA12-1")
      (footprint "eagle-import:MA12-1")
      (libsource (lib "eagle-import") (part "MA12-1"))
    )
    (comp (ref "SV10")
      (value "MA12-1")
      (footprint "eagle-import:MA12-1")
      (libsource (lib "eagle-import") (part "MA12-1"))
    )
    (comp (ref "SV11")
      (value "MA12-1")
      (footprint "eagle-import:MA12-1")
      (libsource (lib "eagle-import") (part "MA12-1"))
    )
    (comp (ref "SV12")
      (value "MA12-1")
      (footprint "eagle-import:MA12-1")
      (libsource (lib "eagle-import") (part "MA12-1"))
    )
    (comp (ref "SV13")
      (value "MA12-1")
      (footprint "eagle-import:MA12-1")
      (libsource (lib "eagle-import") (part "MA12-1"))
    )
    (comp (ref "SV14")
      (value "MA12-1")
      (footprint "eagle-import:MA12-1")
      (libsource (lib "eagle-import") (part "MA12-1"))
    )
    (comp (ref "SV15")
      (value "MA12-1")
      (footprint "eagle-import:MA12-1")
      (libsource (lib "eagle-import") (part "MA12-1"))
    )
    (comp (ref "SV16")
      (value "MA12-1")
      (footprint "eagle-import:MA12-1")
      (libsource (lib "eagle-import") (part "MA12-1"))
    )
    (comp (ref "SV17")
      (value "MA12-1")
      (footprint "eagle-import:MA12-1")
      (libsource (lib "eagle-import") (part "MA12-1"))
    )
    (comp (ref "SV18")
      (value "MA12-1")
      (footprint "eagle-import:MA12-1")
      (libsource (lib "eagle-import") (part "MA12-1"))
    )
    (comp (ref "SV19")
      (value "MA12-1")
      (footprint "eagle-import:MA12-1")
      (libsource (lib "eagle-import") (part "MA12-1"))
    )
    (comp (ref "SV20")
      (value "MA12-1")
      (footprint "eagle-import:MA12-1")
      (libsource (lib "eagle-import") (part "MA12-1"))
    )
    (comp (ref "SV21")
      (value "MA12-1")
      (footprint "eagle-import:MA12-1")
      (libsource (lib "eagle-import") (part "MA12-1"))
    )
    (comp (ref "SV22")
      (value "MA12-1")
      (footprint "eagle-import:MA12-1")
      (libsource (lib "eagle-import") (part "MA12-1"))
    )
    (comp (ref "SV23")
      (value "MA12-1")
      (footprint "eagle-import:MA12-1")
      (libsource (lib "eagle-import") (part "MA12-1"))
    )
    (comp (ref "SV24")
      (value "MA12-1")
      (footprint "eagle-import:MA12-1")
      (libsource (lib "eagle-import") (part "MA12-1"))
    )
    (comp (ref "SV25")
      (value "MA12-1")
      (footprint "eagle-import:MA12-1")
      (libsource (lib "eagle-import") (part "MA12-1"))
    )
    (comp (ref "SV26")
      (value "MA12-1")
      (footprint "eagle-import:MA12-1")
      (libsource (lib "eagle-import") (part "MA12-1"))
    )
    (comp (ref "SV27")
      (value "MA12-1")
      (footprint "eagle-import:MA12-1")
      (libsource (lib "eagle-import") (part "MA12-1"))
    )
    (comp (ref "SV28")
      (value "MA12-1")
      (footprint "eagle-import:MA12-1")
      (libsource (lib "eagle-import") (part "MA12-1"))
    )
    (comp (ref "SV29")
      (value "MA12-1")
      (footprint "eagle-import:MA12-1")
      (libsource (lib "eagle-import") (part "MA12-1"))
    )
    (comp (ref "SV30")
      (value "MA12-1")
      (footprint "eagle-import:MA12-1")
      (libsource (lib "eagle-import") (part "MA12-1"))
    )
    (comp (ref "SV31")
      (value "MA12-1")
      (footprint "eagle-import:MA12-1")
      (libsource (lib "eagle-import") (part "MA12-1"))
    )
    (comp (ref "SV32")
      (value "MA12-1")
      (footprint "eagle-import:MA12-1")
      (libsource (lib "eagle-import") (part "MA12-1"))
    )
    (comp (ref "SV33")
      (value "MA12-1")
      (footprint "eagle-import:MA12-1")
      (libsource (lib "eagle-import") (part "MA12-1"))
    )
    (comp (ref "SV34")
      (value "MA12-1")
      (footprint "eagle-import:MA12-1")
      (libsource (lib "eagle-import") (part "MA12-1"))
    )
    (comp (ref "SV35")
      (value "MA12-1")
      (footprint "eagle-import:MA12-1")
      (libsource (lib "eagle-import") (part "MA12-1"))
    )
    (comp (ref "SV36")
      (value "MA12-1")
      (footprint "eagle-import:MA12-1")
      (libsource (lib "eagle-import") (part "MA12-1"))
    )
    (comp (ref "SV37")
      (value "MA12-1")
      (footprint "eagle-import:MA12-1")
      (libsource (lib "eagle-import") (part "MA12-1"))
    )
    (comp (ref "SV38")
      (value "MA12-1")
      (footprint "eagle-import:MA12-1")
      (libsource (lib "eagle-import") (part "MA12-1"))
    )
    (comp (ref "SV39")
      (value "MA12-1")
      (footprint "eagle-import:MA12-1")
      (libsource (lib "eagle-import") (part "MA12-1"))
    )
    (comp (ref "SV40")
      (value "MA12-1")
      (footprint "eagle-import:MA12-1")
      (libsource (lib "eagle-import") (part "MA12-1"))
    )
    (comp (ref "SV183")
      (value "MA12-1")
      (footprint "eagle-import:MA12-1")
      (libsource (lib "eagle-import") (part "MA12-1"))
    )
    (comp (ref "SV184")
      (value "MA12-1")
      (footprint "eagle-import:MA12-1")
      (libsource (lib "eagle-import") (part "MA12-1"))
    )
    (comp (ref "SV185")
      (value "MA12-1")
      (footprint "eagle-import:MA12-1")
      (libsource (lib "eagle-import") (part "MA12-1"))
    )
    (comp (ref "SV186")
      (value "MA12-1")
      (footprint "eagle-import:MA12-1")
      (libsource (lib "eagle-import") (part "MA12-1"))
    )
    (comp (ref "SV187")
      (value "MA12-1")
      (footprint "eagle-import:MA12-1")
      (libsource (lib "eagle-import") (part "MA12-1"))
    )
    (comp (ref "SV188")
      (value "MA12-1")
      (footprint "eagle-import:MA12-1")
      (libsource (lib "eagle-import") (part "MA12-1"))
    )
    (comp (ref "SV189")
      (value "MA12-1")
      (footprint "eagle-import:MA12-1")
      (libsource (lib "eagle-import") (part "MA12-1"))
    )
    (comp (ref "SV190")
      (value "MA12-1")
      (footprint "eagle-import:MA12-1")
      (libsource (lib "eagle-import") (part "MA12-1"))
    )
    (comp (ref "SV191")
      (value "MA12-1")
      (footprint "eagle-import:MA12-1")
      (libsource (lib "eagle-import") (part "MA12-1"))
    )
    (comp (ref "SV192")
      (value "MA12-1")
      (footprint "eagle-import:MA12-1")
      (libsource (lib "eagle-import") (part "MA12-1"))
    )
  )
  (nets
    (net (code "1") (name "+15V") (class "Default")
      (node (ref "D14") (pin "1") (pinfunction "1_1") (pintype "passive"))
      (node (ref "U$2") (pin "DA2") (pinfunction "1_DA2") (pintype "bidirectional"))
    )
    (net (code "2") (name "-15V") (class "Default")
      (node (ref "D10") (pin "2") (pinfunction "2_2") (pintype "passive"))
      (node (ref "D12") (pin "2") (pinfunction "2_2") (pintype "passive"))
      (node (ref "D14") (pin "2") (pinfunction "2_2") (pintype "passive"))
      (node (ref "D8") (pin "2") (pinfunction "2_2") (pintype "passive"))
      (node (ref "U$2") (pin "AB2") (pinfunction "1_AB2") (pintype "bidirectional"))
      (node (ref "U$2") (pin "BB2") (pinfunction "1_BB2") (pintype "bidirectional"))
      (node (ref "U$2") (pin "CB2") (pinfunction "1_CB2") (pintype "bidirectional"))
      (node (ref "U$2") (pin "DB2") (pinfunction "1_DB2") (pintype "bidirectional"))
    )
    (net (code "3") (name "GND") (class "Default")
      (node (ref "C1") (pin "-") (pinfunction "-_-") (pintype "passive"))
      (node (ref "C2") (pin "-") (pinfunction "-_-") (pintype "passive"))
      (node (ref "C3") (pin "-") (pinfunction "-_-") (pintype "passive"))
      (node (ref "C4") (pin "-") (pinfunction "-_-") (pintype "passive"))
      (node (ref "D10") (pin "12") (pinfunction "12_12") (pintype "passive"))
      (node (ref "D10") (pin "16") (pinfunction "16_16") (pintype "passive"))
      (node (ref "D10") (pin "3") (pinfunction "3_3") (pintype "passive"))
      (node (ref "D10") (pin "6") (pinfunction "6_6") (pintype "passive"))
      (node (ref "D11") (pin "12") (pinfunction "12_12") (pintype "passive"))
      (node (ref "D11") (pin "16") (pinfunction "16_16") (pintype "passive"))
      (node (ref "D11") (pin "3") (pinfunction "3_3") (pintype "passive"))
      (node (ref "D11") (pin "6") (pinfunction "6_6") (pintype "passive"))
      (node (ref "D12") (pin "12") (pinfunction "12_12") (pintype "passive"))
      (node (ref "D12") (pin "16") (pinfunction "16_16") (pintype "passive"))
      (node (ref "D12") (pin "3") (pinfunction "3_3") (pintype "passive"))
      (node (ref "D12") (pin "6") (pinfunction "6_6") (pintype "passive"))
      (node (ref "D13") (pin "12") (pinfunction "12_12") (pintype "passive"))
      (node (ref "D13") (pin "16") (pinfunction "16_16") (pintype "passive"))
      (node (ref "D13") (pin "3") (pinfunction "3_3") (pintype "passive"))
      (node (ref "D13") (pin "6") (pinfunction "6_6") (pintype "passive"))
      (node (ref "D14") (pin "12") (pinfunction "12_12") (pintype "passive"))
      (node (ref "D14") (pin "16") (pinfunction "16_16") (pintype "passive"))
      (node (ref "D14") (pin "3") (pinfunction "3_3") (pintype "passive"))
      (node (ref "D14") (pin "6") (pinfunction "6_6") (pintype "passive"))
      (node (ref "D7") (pin "12") (pinfunction "12_12") (pintype "passive"))
      (node (ref "D7") (pin "16") (pinfunction "16_16") (pintype "passive"))
      (node (ref "D7") (pin "3") (pinfunction "3_3") (pintype "passive"))
      (node (ref "D7") (pin "6") (pinfunction "6_6") (pintype "passive"))
      (node (ref "D8") (pin "12") (pinfunction "12_12") (pintype "passive"))
      (node (ref "D8") (pin "16") (pinfunction "16_16") (pintype "passive"))
      (node (ref "D8") (pin "3") (pinfunction "3_3") (pintype "passive"))
      (node (ref "D8") (pin "6") (pinfunction "6_6") (pintype "passive"))
      (node (ref "D9") (pin "12") (pinfunction "12_12") (pintype "passive"))
      (node (ref "D9") (pin "16") (pinfunction "16_16") (pintype "passive"))
      (node (ref "D9") (pin "3") (pinfunction "3_3") (pintype "passive"))
      (node (ref "D9") (pin "6") (pinfunction "6_6") (pintype "passive"))
      (node (ref "SV10") (pin "1") (pinfunction "1_1") (pintype "passive"))
      (node (ref "SV10") (pin "10") (pinfunction "10_10") (pintype "passive"))
      (node (ref "SV10") (pin "11") (pinfunction "11_11") (pintype "passive"))
      (node (ref "SV10") (pin "12") (pinfunction "12_12") (pintype "passive"))
      (node (ref "SV10") (pin "2") (pinfunction "2_2") (pintype "passive"))
      (node (ref "SV10") (pin "3") (pinfunction "3_3") (pintype "passive"))
      (node (ref "SV10") (pin "4") (pinfunction "4_4") (pintype "passive"))
      (node (ref "SV10") (pin "5") (pinfunction "5_5") (pintype "passive"))
      (node (ref "SV10") (pin "6") (pinfunction "6_6") (pintype "passive"))
      (node (ref "SV10") (pin "7") (pinfunction "7_7") (pintype "passive"))
      (node (ref "SV10") (pin "8") (pinfunction "8_8") (pintype "passive"))
      (node (ref "SV10") (pin "9") (pinfunction "9_9") (pintype "passive"))
      (node (ref "SV12") (pin "1") (pinfunction "1_1") (pintype "passive"))
      (node (ref "SV12") (pin "10") (pinfunction "10_10") (pintype "passive"))
      (node (ref "SV12") (pin "11") (pinfunction "11_11") (pintype "passive"))
      (node (ref "SV12") (pin "12") (pinfunction "12_12") (pintype "passive"))
      (node (ref "SV12") (pin "2") (pinfunction "2_2") (pintype "passive"))
      (node (ref "SV12") (pin "3") (pinfunction "3_3") (pintype "passive"))
      (node (ref "SV12") (pin "4") (pinfunction "4_4") (pintype "passive"))
      (node (ref "SV12") (pin "5") (pinfunction "5_5") (pintype "passive"))
      (node (ref "SV12") (pin "6") (pinfunction "6_6") (pintype "passive"))
      (node (ref "SV12") (pin "7") (pinfunction "7_7") (pintype "passive"))
      (node (ref "SV12") (pin "8") (pinfunction "8_8") (pintype "passive"))
      (node (ref "SV12") (pin "9") (pinfunction "9_9") (pintype "passive"))
      (node (ref "SV14") (pin "1") (pinfunction "1_1") (pintype "passive"))
      (node (ref "SV14") (pin "10") (pinfunction "10_10") (pintype "passive"))
      (node (ref "SV14") (pin "11") (pinfunction "11_11") (pintype "passive"))
      (node (ref "SV14") (pin "12") (pinfunction "12_12") (pintype "passive"))
      (node (ref "SV14") (pin "2") (pinfunction "2_2") (pintype "passive"))
      (node (ref "SV14") (pin "3") (pinfunction "3_3") (pintype "passive"))
      (node (ref "SV14") (pin "4") (pinfunction "4_4") (pintype "passive"))
      (node (ref "SV14") (pin "5") (pinfunction "5_5") (pintype "passive"))
      (node (ref "SV14") (pin "6") (pinfunction "6_6") (pintype "passive"))
      (node (ref "SV14") (pin "7") (pinfunction "7_7") (pintype "passive"))
      (node (ref "SV14") (pin "8") (pinfunction "8_8") (pintype "passive"))
      (node (ref "SV14") (pin "9") (pinfunction "9_9") (pintype "passive"))
      (node (ref "SV16") (pin "1") (pinfunction "1_1") (pintype "passive"))
      (node (ref "SV16") (pin "10") (pinfunction "10_10") (pintype "passive"))
      (node (ref "SV16") (pin "11") (pinfunction "11_11") (pintype "passive"))
      (node (ref "SV16") (pin "12") (pinfunction "12_12") (pintype "passive"))
      (node (ref "SV16") (pin "2") (pinfunction "2_2") (pintype "passive"))
      (node (ref "SV16") (pin "3") (pinfunction "3_3") (pintype "passive"))
      (node (ref "SV16") (pin "4") (pinfunction "4_4") (pintype "passive"))
      (node (ref "SV16") (pin "5") (pinfunction "5_5") (pintype "passive"))
      (node (ref "SV16") (pin "6") (pinfunction "6_6") (pintype "passive"))
      (node (ref "SV16") (pin "7") (pinfunction "7_7") (pintype "passive"))
      (node (ref "SV16") (pin "8") (pinfunction "8_8") (pintype "passive"))
      (node (ref "SV16") (pin "9") (pinfunction "9_9") (pintype "passive"))
      (node (ref "SV18") (pin "1") (pinfunction "1_1") (pintype "passive"))
      (node (ref "SV18") (pin "10") (pinfunction "10_10") (pintype "passive"))
      (node (ref "SV18") (pin "11") (pinfunction "11_11") (pintype "passive"))
      (node (ref "SV18") (pin "12") (pinfunction "12_12") (pintype "passive"))
      (node (ref "SV18") (pin "2") (pinfunction "2_2") (pintype "passive"))
      (node (ref "SV18") (pin "3") (pinfunction "3_3") (pintype "passive"))
      (node (ref "SV18") (pin "4") (pinfunction "4_4") (pintype "passive"))
      (node (ref "SV18") (pin "5") (pinfunction "5_5") (pintype "passive"))
      (node (ref "SV18") (pin "6") (pinfunction "6_6") (pintype "passive"))
      (node (ref "SV18") (pin "7") (pinfunction "7_7") (pintype "passive"))
      (node (ref "SV18") (pin "8") (pinfunction "8_8") (pintype "passive"))
      (node (ref "SV18") (pin "9") (pinfunction "9_9") (pintype "passive"))
      (node (ref "SV184") (pin "1") (pinfunction "1_1") (pintype "passive"))
      (node (ref "SV184") (pin "10") (pinfunction "10_10") (pintype "passive"))
      (node (ref "SV184") (pin "11") (pinfunction "11_11") (pintype "passive"))
      (node (ref "SV184") (pin "12") (pinfunction "12_12") (pintype "passive"))
      (node (ref "SV184") (pin "2") (pinfunction "2_2") (pintype "passive"))
      (node (ref "SV184") (pin "3") (pinfunction "3_3") (pintype "passive"))
      (node (ref "SV184") (pin "4") (pinfunction "4_4") (pintype "passive"))
      (node (ref "SV184") (pin "5") (pinfunction "5_5") (pintype "passive"))
      (node (ref "SV184") (pin "6") (pinfunction "6_6") (pintype "passive"))
      (node (ref "SV184") (pin "7") (pinfunction "7_7") (pintype "passive"))
      (node (ref "SV184") (pin "8") (pinfunction "8_8") (pintype "passive"))
      (node (ref "SV184") (pin "9") (pinfunction "9_9") (pintype "passive"))
      (node (ref "SV186") (pin "1") (pinfunction "1_1") (pintype "passive"))
      (node (ref "SV186") (pin "10") (pinfunction "10_10") (pintype "passive"))
      (node (ref "SV186") (pin "11") (pinfunction "11_11") (pintype "passive"))
      (node (ref "SV186") (pin "12") (pinfunction "12_12") (pintype "passive"))
      (node (ref "SV186") (pin "2") (pinfunction "2_2") (pintype "passive"))
      (node (ref "SV186") (pin "3") (pinfunction "3_3") (pintype "passive"))
      (node (ref "SV186") (pin "4") (pinfunction "4_4") (pintype "passive"))
      (node (ref "SV186") (pin "5") (pinfunction "5_5") (pintype "passive"))
      (node (ref "SV186") (pin "6") (pinfunction "6_6") (pintype "passive"))
      (node (ref "SV186") (pin "7") (pinfunction "7_7") (pintype "passive"))
      (node (ref "SV186") (pin "8") (pinfunction "8_8") (pintype "passive"))
      (node (ref "SV186") (pin "9") (pinfunction "9_9") (pintype "passive"))
      (node (ref "SV188") (pin "1") (pinfunction "1_1") (pintype "passive"))
      (node (ref "SV188") (pin "10") (pinfunction "10_10") (pintype "passive"))
      (node (ref "SV188") (pin "11") (pinfunction "11_11") (pintype "passive"))
      (node (ref "SV188") (pin "12") (pinfunction "12_12") (pintype "passive"))
      (node (ref "SV188") (pin "2") (pinfunction "2_2") (pintype "passive"))
      (node (ref "SV188") (pin "3") (pinfunction "3_3") (pintype "passive"))
      (node (ref "SV188") (pin "4") (pinfunction "4_4") (pintype "passive"))
      (node (ref "SV188") (pin "5") (pinfunction "5_5") (pintype "passive"))
      (node (ref "SV188") (pin "6") (pinfunction "6_6") (pintype "passive"))
      (node (ref "SV188") (pin "7") (pinfunction "7_7") (pintype "passive"))
      (node (ref "SV188") (pin "8") (pinfunction "8_8") (pintype "passive"))
      (node (ref "SV188") (pin "9") (pinfunction "9_9") (pintype "passive"))
      (node (ref "SV190") (pin "1") (pinfunction "1_1") (pintype "passive"))
      (node (ref "SV190") (pin "10") (pinfunction "10_10") (pintype "passive"))
      (node (ref "SV190") (pin "11") (pinfunction "11_11") (pintype "passive"))
      (node (ref "SV190") (pin "12") (pinfunction "12_12") (pintype "passive"))
      (node (ref "SV190") (pin "2") (pinfunction "2_2") (pintype "passive"))
      (node (ref "SV190") (pin "3") (pinfunction "3_3") (pintype "passive"))
      (node (ref "SV190") (pin "4") (pinfunction "4_4") (pintype "passive"))
      (node (ref "SV190") (pin "5") (pinfunction "5_5") (pintype "passive"))
      (node (ref "SV190") (pin "6") (pinfunction "6_6") (pintype "passive"))
      (node (ref "SV190") (pin "7") (pinfunction "7_7") (pintype "passive"))
      (node (ref "SV190") (pin "8") (pinfunction "8_8") (pintype "passive"))
      (node (ref "SV190") (pin "9") (pinfunction "9_9") (pintype "passive"))
      (node (ref "SV192") (pin "1") (pinfunction "1_1") (pintype "passive"))
      (node (ref "SV192") (pin "10") (pinfunction "10_10") (pintype "passive"))
      (node (ref "SV192") (pin "11") (pinfunction "11_11") (pintype "passive"))
      (node (ref "SV192") (pin "12") (pinfunction "12_12") (pintype "passive"))
      (node (ref "SV192") (pin "2") (pinfunction "2_2") (pintype "passive"))
      (node (ref "SV192") (pin "3") (pinfunction "3_3") (pintype "passive"))
      (node (ref "SV192") (pin "4") (pinfunction "4_4") (pintype "passive"))
      (node (ref "SV192") (pin "5") (pinfunction "5_5") (pintype "passive"))
      (node (ref "SV192") (pin "6") (pinfunction "6_6") (pintype "passive"))
      (node (ref "SV192") (pin "7") (pinfunction "7_7") (pintype "passive"))
      (node (ref "SV192") (pin "8") (pinfunction "8_8") (pintype "passive"))
      (node (ref "SV192") (pin "9") (pinfunction "9_9") (pintype "passive"))
      (node (ref "SV2") (pin "1") (pinfunction "1_1") (pintype "passive"))
      (node (ref "SV2") (pin "10") (pinfunction "10_10") (pintype "passive"))
      (node (ref "SV2") (pin "11") (pinfunction "11_11") (pintype "passive"))
      (node (ref "SV2") (pin "12") (pinfunction "12_12") (pintype "passive"))
      (node (ref "SV2") (pin "2") (pinfunction "2_2") (pintype "passive"))
      (node (ref "SV2") (pin "3") (pinfunction "3_3") (pintype "passive"))
      (node (ref "SV2") (pin "4") (pinfunction "4_4") (pintype "passive"))
      (node (ref "SV2") (pin "5") (pinfunction "5_5") (pintype "passive"))
      (node (ref "SV2") (pin "6") (pinfunction "6_6") (pintype "passive"))
      (node (ref "SV2") (pin "7") (pinfunction "7_7") (pintype "passive"))
      (node (ref "SV2") (pin "8") (pinfunction "8_8") (pintype "passive"))
      (node (ref "SV2") (pin "9") (pinfunction "9_9") (pintype "passive"))
      (node (ref "SV20") (pin "1") (pinfunction "1_1") (pintype "passive"))
      (node (ref "SV20") (pin "10") (pinfunction "10_10") (pintype "passive"))
      (node (ref "SV20") (pin "11") (pinfunction "11_11") (pintype "passive"))
      (node (ref "SV20") (pin "12") (pinfunction "12_12") (pintype "passive"))
      (node (ref "SV20") (pin "2") (pinfunction "2_2") (pintype "passive"))
      (node (ref "SV20") (pin "3") (pinfunction "3_3") (pintype "passive"))
      (node (ref "SV20") (pin "4") (pinfunction "4_4") (pintype "passive"))
      (node (ref "SV20") (pin "5") (pinfunction "5_5") (pintype "passive"))
      (node (ref "SV20") (pin "6") (pinfunction "6_6") (pintype "passive"))
      (node (ref "SV20") (pin "7") (pinfunction "7_7") (pintype "passive"))
      (node (ref "SV20") (pin "8") (pinfunction "8_8") (pintype "passive"))
      (node (ref "SV20") (pin "9") (pinfunction "9_9") (pintype "passive"))
      (node (ref "SV22") (pin "1") (pinfunction "1_1") (pintype "passive"))
      (node (ref "SV22") (pin "10") (pinfunction "10_10") (pintype "passive"))
      (node (ref "SV22") (pin "11") (pinfunction "11_11") (pintype "passive"))
      (node (ref "SV22") (pin "12") (pinfunction "12_12") (pintype "passive"))
      (node (ref "SV22") (pin "2") (pinfunction "2_2") (pintype "passive"))
      (node (ref "SV22") (pin "3") (pinfunction "3_3") (pintype "passive"))
      (node (ref "SV22") (pin "4") (pinfunction "4_4") (pintype "passive"))
      (node (ref "SV22") (pin "5") (pinfunction "5_5") (pintype "passive"))
      (node (ref "SV22") (pin "6") (pinfunction "6_6") (pintype "passive"))
      (node (ref "SV22") (pin "7") (pinfunction "7_7") (pintype "passive"))
      (node (ref "SV22") (pin "8") (pinfunction "8_8") (pintype "passive"))
      (node (ref "SV22") (pin "9") (pinfunction "9_9") (pintype "passive"))
      (node (ref "SV24") (pin "1") (pinfunction "1_1") (pintype "passive"))
      (node (ref "SV24") (pin "10") (pinfunction "10_10") (pintype "passive"))
      (node (ref "SV24") (pin "11") (pinfunction "11_11") (pintype "passive"))
      (node (ref "SV24") (pin "12") (pinfunction "12_12") (pintype "passive"))
      (node (ref "SV24") (pin "2") (pinfunction "2_2") (pintype "passive"))
      (node (ref "SV24") (pin "3") (pinfunction "3_3") (pintype "passive"))
      (node (ref "SV24") (pin "4") (pinfunction "4_4") (pintype "passive"))
      (node (ref "SV24") (pin "5") (pinfunction "5_5") (pintype "passive"))
      (node (ref "SV24") (pin "6") (pinfunction "6_6") (pintype "passive"))
      (node (ref "SV24") (pin "7") (pinfunction "7_7") (pintype "passive"))
      (node (ref "SV24") (pin "8") (pinfunction "8_8") (pintype "passive"))
      (node (ref "SV24") (pin "9") (pinfunction "9_9") (pintype "passive"))
      (node (ref "SV26") (pin "1") (pinfunction "1_1") (pintype "passive"))
      (node (ref "SV26") (pin "10") (pinfunction "10_10") (pintype "passive"))
      (node (ref "SV26") (pin "11") (pinfunction "11_11") (pintype "passive"))
      (node (ref "SV26") (pin "12") (pinfunction "12_12") (pintype "passive"))
      (node (ref "SV26") (pin "2") (pinfunction "2_2") (pintype "passive"))
      (node (ref "SV26") (pin "3") (pinfunction "3_3") (pintype "passive"))
      (node (ref "SV26") (pin "4") (pinfunction "4_4") (pintype "passive"))
      (node (ref "SV26") (pin "5") (pinfunction "5_5") (pintype "passive"))
      (node (ref "SV26") (pin "6") (pinfunction "6_6") (pintype "passive"))
      (node (ref "SV26") (pin "7") (pinfunction "7_7") (pintype "passive"))
      (node (ref "SV26") (pin "8") (pinfunction "8_8") (pintype "passive"))
      (node (ref "SV26") (pin "9") (pinfunction "9_9") (pintype "passive"))
      (node (ref "SV28") (pin "1") (pinfunction "1_1") (pintype "passive"))
      (node (ref "SV28") (pin "10") (pinfunction "10_10") (pintype "passive"))
      (node (ref "SV28") (pin "11") (pinfunction "11_11") (pintype "passive"))
      (node (ref "SV28") (pin "12") (pinfunction "12_12") (pintype "passive"))
      (node (ref "SV28") (pin "2") (pinfunction "2_2") (pintype "passive"))
      (node (ref "SV28") (pin "3") (pinfunction "3_3") (pintype "passive"))
      (node (ref "SV28") (pin "4") (pinfunction "4_4") (pintype "passive"))
      (node (ref "SV28") (pin "5") (pinfunction "5_5") (pintype "passive"))
      (node (ref "SV28") (pin "6") (pinfunction "6_6") (pintype "passive"))
      (node (ref "SV28") (pin "7") (pinfunction "7_7") (pintype "passive"))
      (node (ref "SV28") (pin "8") (pinfunction "8_8") (pintype "passive"))
      (node (ref "SV28") (pin "9") (pinfunction "9_9") (pintype "passive"))
      (node (ref "SV30") (pin "1") (pinfunction "1_1") (pintype "passive"))
      (node (ref "SV30") (pin "10") (pinfunction "10_10") (pintype "passive"))
      (node (ref "SV30") (pin "11") (pinfunction "11_11") (pintype "passive"))
      (node (ref "SV30") (pin "12") (pinfunction "12_12") (pintype "passive"))
      (node (ref "SV30") (pin "2") (pinfunction "2_2") (pintype "passive"))
      (node (ref "SV30") (pin "3") (pinfunction "3_3") (pintype "passive"))
      (node (ref "SV30") (pin "4") (pinfunction "4_4") (pintype "passive"))
      (node (ref "SV30") (pin "5") (pinfunction "5_5") (pintype "passive"))
      (node (ref "SV30") (pin "6") (pinfunction "6_6") (pintype "passive"))
      (node (ref "SV30") (pin "7") (pinfunction "7_7") (pintype "passive"))
      (node (ref "SV30") (pin "8") (pinfunction "8_8") (pintype "passive"))
      (node (ref "SV30") (pin "9") (pinfunction "9_9") (pintype "passive"))
      (node (ref "SV32") (pin "1") (pinfunction "1_1") (pintype "passive"))
      (node (ref "SV32") (pin "10") (pinfunction "10_10") (pintype "passive"))
      (node (ref "SV32") (pin "11") (pinfunction "11_11") (pintype "passive"))
      (node (ref "SV32") (pin "12") (pinfunction "12_12") (pintype "passive"))
      (node (ref "SV32") (pin "2") (pinfunction "2_2") (pintype "passive"))
      (node (ref "SV32") (pin "3") (pinfunction "3_3") (pintype "passive"))
      (node (ref "SV32") (pin "4") (pinfunction "4_4") (pintype "passive"))
      (node (ref "SV32") (pin "5") (pinfunction "5_5") (pintype "passive"))
      (node (ref "SV32") (pin "6") (pinfunction "6_6") (pintype "passive"))
      (node (ref "SV32") (pin "7") (pinfunction "7_7") (pintype "passive"))
      (node (ref "SV32") (pin "8") (pinfunction "8_8") (pintype "passive"))
      (node (ref "SV32") (pin "9") (pinfunction "9_9") (pintype "passive"))
      (node (ref "SV34") (pin "1") (pinfunction "1_1") (pintype "passive"))
      (node (ref "SV34") (pin "10") (pinfunction "10_10") (pintype "passive"))
      (node (ref "SV34") (pin "11") (pinfunction "11_11") (pintype "passive"))
      (node (ref "SV34") (pin "12") (pinfunction "12_12") (pintype "passive"))
      (node (ref "SV34") (pin "2") (pinfunction "2_2") (pintype "passive"))
      (node (ref "SV34") (pin "3") (pinfunction "3_3") (pintype "passive"))
      (node (ref "SV34") (pin "4") (pinfunction "4_4") (pintype "passive"))
      (node (ref "SV34") (pin "5") (pinfunction "5_5") (pintype "passive"))
      (node (ref "SV34") (pin "6") (pinfunction "6_6") (pintype "passive"))
      (node (ref "SV34") (pin "7") (pinfunction "7_7") (pintype "passive"))
      (node (ref "SV34") (pin "8") (pinfunction "8_8") (pintype "passive"))
      (node (ref "SV34") (pin "9") (pinfunction "9_9") (pintype "passive"))
      (node (ref "SV36") (pin "1") (pinfunction "1_1") (pintype "passive"))
      (node (ref "SV36") (pin "10") (pinfunction "10_10") (pintype "passive"))
      (node (ref "SV36") (pin "11") (pinfunction "11_11") (pintype "passive"))
      (node (ref "SV36") (pin "12") (pinfunction "12_12") (pintype "passive"))
      (node (ref "SV36") (pin "2") (pinfunction "2_2") (pintype "passive"))
      (node (ref "SV36") (pin "3") (pinfunction "3_3") (pintype "passive"))
      (node (ref "SV36") (pin "4") (pinfunction "4_4") (pintype "passive"))
      (node (ref "SV36") (pin "5") (pinfunction "5_5") (pintype "passive"))
      (node (ref "SV36") (pin "6") (pinfunction "6_6") (pintype "passive"))
      (node (ref "SV36") (pin "7") (pinfunction "7_7") (pintype "passive"))
      (node (ref "SV36") (pin "8") (pinfunction "8_8") (pintype "passive"))
      (node (ref "SV36") (pin "9") (pinfunction "9_9") (pintype "passive"))
      (node (ref "SV38") (pin "1") (pinfunction "1_1") (pintype "passive"))
      (node (ref "SV38") (pin "10") (pinfunction "10_10") (pintype "passive"))
      (node (ref "SV38") (pin "11") (pinfunction "11_11") (pintype "passive"))
      (node (ref "SV38") (pin "12") (pinfunction "12_12") (pintype "passive"))
      (node (ref "SV38") (pin "2") (pinfunction "2_2") (pintype "passive"))
      (node (ref "SV38") (pin "3") (pinfunction "3_3") (pintype "passive"))
      (node (ref "SV38") (pin "4") (pinfunction "4_4") (pintype "passive"))
      (node (ref "SV38") (pin "5") (pinfunction "5_5") (pintype "passive"))
      (node (ref "SV38") (pin "6") (pinfunction "6_6") (pintype "passive"))
      (node (ref "SV38") (pin "7") (pinfunction "7_7") (pintype "passive"))
      (node (ref "SV38") (pin "8") (pinfunction "8_8") (pintype "passive"))
      (node (ref "SV38") (pin "9") (pinfunction "9_9") (pintype "passive"))
      (node (ref "SV4") (pin "1") (pinfunction "1_1") (pintype "passive"))
      (node (ref "SV4") (pin "10") (pinfunction "10_10") (pintype "passive"))
      (node (ref "SV4") (pin "11") (pinfunction "11_11") (pintype "passive"))
      (node (ref "SV4") (pin "12") (pinfunction "12_12") (pintype "passive"))
      (node (ref "SV4") (pin "2") (pinfunction "2_2") (pintype "passive"))
      (node (ref "SV4") (pin "3") (pinfunction "3_3") (pintype "passive"))
      (node (ref "SV4") (pin "4") (pinfunction "4_4") (pintype "passive"))
      (node (ref "SV4") (pin "5") (pinfunction "5_5") (pintype "passive"))
      (node (ref "SV4") (pin "6") (pinfunction "6_6") (pintype "passive"))
      (node (ref "SV4") (pin "7") (pinfunction "7_7") (pintype "passive"))
      (node (ref "SV4") (pin "8") (pinfunction "8_8") (pintype "passive"))
      (node (ref "SV4") (pin "9") (pinfunction "9_9") (pintype "passive"))
      (node (ref "SV40") (pin "1") (pinfunction "1_1") (pintype "passive"))
      (node (ref "SV40") (pin "10") (pinfunction "10_10") (pintype "passive"))
      (node (ref "SV40") (pin "11") (pinfunction "11_11") (pintype "passive"))
      (node (ref "SV40") (pin "12") (pinfunction "12_12") (pintype "passive"))
      (node (ref "SV40") (pin "2") (pinfunction "2_2") (pintype "passive"))
      (node (ref "SV40") (pin "3") (pinfunction "3_3") (pintype "passive"))
      (node (ref "SV40") (pin "4") (pinfunction "4_4") (pintype "passive"))
      (node (ref "SV40") (pin "5") (pinfunction "5_5") (pintype "passive"))
      (node (ref "SV40") (pin "6") (pinfunction "6_6") (pintype "passive"))
      (node (ref "SV40") (pin "7") (pinfunction "7_7") (pintype "passive"))
      (node (ref "SV40") (pin "8") (pinfunction "8_8") (pintype "passive"))
      (node (ref "SV40") (pin "9") (pinfunction "9_9") (pintype "passive"))
      (node (ref "SV42") (pin "1") (pinfunction "1_1") (pintype "passive"))
      (node (ref "SV42") (pin "10") (pinfunction "10_10") (pintype "passive"))
      (node (ref "SV42") (pin "11") (pinfunction "11_11") (pintype "passive"))
      (node (ref "SV42") (pin "12") (pinfunction "12_12") (pintype "passive"))
      (node (ref "SV42") (pin "2") (pinfunction "2_2") (pintype "passive"))
      (node (ref "SV42") (pin "3") (pinfunction "3_3") (pintype "passive"))
      (node (ref "SV42") (pin "4") (pinfunction "4_4") (pintype "passive"))
      (node (ref "SV42") (pin "5") (pinfunction "5_5") (pintype "passive"))
      (node (ref "SV42") (pin "6") (pinfunction "6_6") (pintype "passive"))
      (node (ref "SV42") (pin "7") (pinfunction "7_7") (pintype "passive"))
      (node (ref "SV42") (pin "8") (pinfunction "8_8") (pintype "passive"))
      (node (ref "SV42") (pin "9") (pinfunction "9_9") (pintype "passive"))
      (node (ref "SV44") (pin "1") (pinfunction "1_1") (pintype "passive"))
      (node (ref "SV44") (pin "10") (pinfunction "10_10") (pintype "passive"))
      (node (ref "SV44") (pin "11") (pinfunction "11_11") (pintype "passive"))
      (node (ref "SV44") (pin "12") (pinfunction "12_12") (pintype "passive"))
      (node (ref "SV44") (pin "2") (pinfunction "2_2") (pintype "passive"))
      (node (ref "SV44") (pin "3") (pinfunction "3_3") (pintype "passive"))
      (node (ref "SV44") (pin "4") (pinfunction "4_4") (pintype "passive"))
      (node (ref "SV44") (pin "5") (pinfunction "5_5") (pintype "passive"))
      (node (ref "SV44") (pin "6") (pinfunction "6_6") (pintype "passive"))
      (node (ref "SV44") (pin "7") (pinfunction "7_7") (pintype "passive"))
      (node (ref "SV44") (pin "8") (pinfunction "8_8") (pintype "passive"))
      (node (ref "SV44") (pin "9") (pinfunction "9_9") (pintype "passive"))
      (node (ref "SV46") (pin "1") (pinfunction "1_1") (pintype "passive"))
      (node (ref "SV46") (pin "10") (pinfunction "10_10") (pintype "passive"))
      (node (ref "SV46") (pin "11") (pinfunction "11_11") (pintype "passive"))
      (node (ref "SV46") (pin "12") (pinfunction "12_12") (pintype "passive"))
      (node (ref "SV46") (pin "2") (pinfunction "2_2") (pintype "passive"))
      (node (ref "SV46") (pin "3") (pinfunction "3_3") (pintype "passive"))
      (node (ref "SV46") (pin "4") (pinfunction "4_4") (pintype "passive"))
      (node (ref "SV46") (pin "5") (pinfunction "5_5") (pintype "passive"))
      (node (ref "SV46") (pin "6") (pinfunction "6_6") (pintype "passive"))
      (node (ref "SV46") (pin "7") (pinfunction "7_7") (pintype "passive"))
      (node (ref "SV46") (pin "8") (pinfunction "8_8") (pintype "passive"))
      (node (ref "SV46") (pin "9") (pinfunction "9_9") (pintype "passive"))
      (node (ref "SV48") (pin "1") (pinfunction "1_1") (pintype "passive"))
      (node (ref "SV48") (pin "10") (pinfunction "10_10") (pintype "passive"))
      (node (ref "SV48") (pin "11") (pinfunction "11_11") (pintype "passive"))
      (node (ref "SV48") (pin "12") (pinfunction "12_12") (pintype "passive"))
      (node (ref "SV48") (pin "2") (pinfunction "2_2") (pintype "passive"))
      (node (ref "SV48") (pin "3") (pinfunction "3_3") (pintype "passive"))
      (node (ref "SV48") (pin "4") (pinfunction "4_4") (pintype "passive"))
      (node (ref "SV48") (pin "5") (pinfunction "5_5") (pintype "passive"))
      (node (ref "SV48") (pin "6") (pinfunction "6_6") (pintype "passive"))
      (node (ref "SV48") (pin "7") (pinfunction "7_7") (pintype "passive"))
      (node (ref "SV48") (pin "8") (pinfunction "8_8") (pintype "passive"))
      (node (ref "SV48") (pin "9") (pinfunction "9_9") (pintype "passive"))
      (node (ref "SV50") (pin "1") (pinfunction "1_1") (pintype "passive"))
      (node (ref "SV50") (pin "10") (pinfunction "10_10") (pintype "passive"))
      (node (ref "SV50") (pin "11") (pinfunction "11_11") (pintype "passive"))
      (node (ref "SV50") (pin "12") (pinfunction "12_12") (pintype "passive"))
      (node (ref "SV50") (pin "2") (pinfunction "2_2") (pintype "passive"))
      (node (ref "SV50") (pin "3") (pinfunction "3_3") (pintype "passive"))
      (node (ref "SV50") (pin "4") (pinfunction "4_4") (pintype "passive"))
      (node (ref "SV50") (pin "5") (pinfunction "5_5") (pintype "passive"))
      (node (ref "SV50") (pin "6") (pinfunction "6_6") (pintype "passive"))
      (node (ref "SV50") (pin "7") (pinfunction "7_7") (pintype "passive"))
      (node (ref "SV50") (pin "8") (pinfunction "8_8") (pintype "passive"))
      (node (ref "SV50") (pin "9") (pinfunction "9_9") (pintype "passive"))
      (node (ref "SV52") (pin "1") (pinfunction "1_1") (pintype "passive"))
      (node (ref "SV52") (pin "10") (pinfunction "10_10") (pintype "passive"))
      (node (ref "SV52") (pin "11") (pinfunction "11_11") (pintype "passive"))
      (node (ref "SV52") (pin "12") (pinfunction "12_12") (pintype "passive"))
      (node (ref "SV52") (pin "2") (pinfunction "2_2") (pintype "passive"))
      (node (ref "SV52") (pin "3") (pinfunction "3_3") (pintype "passive"))
      (node (ref "SV52") (pin "4") (pinfunction "4_4") (pintype "passive"))
      (node (ref "SV52") (pin "5") (pinfunction "5_5") (pintype "passive"))
      (node (ref "SV52") (pin "6") (pinfunction "6_6") (pintype "passive"))
      (node (ref "SV52") (pin "7") (pinfunction "7_7") (pintype "passive"))
      (node (ref "SV52") (pin "8") (pinfunction "8_8") (pintype "passive"))
      (node (ref "SV52") (pin "9") (pinfunction "9_9") (pintype "passive"))
      (node (ref "SV54") (pin "1") (pinfunction "1_1") (pintype "passive"))
      (node (ref "SV54") (pin "10") (pinfunction "10_10") (pintype "passive"))
      (node (ref "SV54") (pin "11") (pinfunction "11_11") (pintype "passive"))
      (node (ref "SV54") (pin "12") (pinfunction "12_12") (pintype "passive"))
      (node (ref "SV54") (pin "2") (pinfunction "2_2") (pintype "passive"))
      (node (ref "SV54") (pin "3") (pinfunction "3_3") (pintype "passive"))
      (node (ref "SV54") (pin "4") (pinfunction "4_4") (pintype "passive"))
      (node (ref "SV54") (pin "5") (pinfunction "5_5") (pintype "passive"))
      (node (ref "SV54") (pin "6") (pinfunction "6_6") (pintype "passive"))
      (node (ref "SV54") (pin "7") (pinfunction "7_7") (pintype "passive"))
      (node (ref "SV54") (pin "8") (pinfunction "8_8") (pintype "passive"))
      (node (ref "SV54") (pin "9") (pinfunction "9_9") (pintype "passive"))
      (node (ref "SV56") (pin "1") (pinfunction "1_1") (pintype "passive"))
      (node (ref "SV56") (pin "10") (pinfunction "10_10") (pintype "passive"))
      (node (ref "SV56") (pin "11") (pinfunction "11_11") (pintype "passive"))
      (node (ref "SV56") (pin "12") (pinfunction "12_12") (pintype "passive"))
      (node (ref "SV56") (pin "2") (pinfunction "2_2") (pintype "passive"))
      (node (ref "SV56") (pin "3") (pinfunction "3_3") (pintype "passive"))
      (node (ref "SV56") (pin "4") (pinfunction "4_4") (pintype "passive"))
      (node (ref "SV56") (pin "5") (pinfunction "5_5") (pintype "passive"))
      (node (ref "SV56") (pin "6") (pinfunction "6_6") (pintype "passive"))
      (node (ref "SV56") (pin "7") (pinfunction "7_7") (pintype "passive"))
      (node (ref "SV56") (pin "8") (pinfunction "8_8") (pintype "passive"))
      (node (ref "SV56") (pin "9") (pinfunction "9_9") (pintype "passive"))
      (node (ref "SV58") (pin "1") (pinfunction "1_1") (pintype "passive"))
      (node (ref "SV58") (pin "10") (pinfunction "10_10") (pintype "passive"))
      (node (ref "SV58") (pin "11") (pinfunction "11_11") (pintype "passive"))
      (node (ref "SV58") (pin "12") (pinfunction "12_12") (pintype "passive"))
      (node (ref "SV58") (pin "2") (pinfunction "2_2") (pintype "passive"))
      (node (ref "SV58") (pin "3") (pinfunction "3_3") (pintype "passive"))
      (node (ref "SV58") (pin "4") (pinfunction "4_4") (pintype "passive"))
      (node (ref "SV58") (pin "5") (pinfunction "5_5") (pintype "passive"))
      (node (ref "SV58") (pin "6") (pinfunction "6_6") (pintype "passive"))
      (node (ref "SV58") (pin "7") (pinfunction "7_7") (pintype "passive"))
      (node (ref "SV58") (pin "8") (pinfunction "8_8") (pintype "passive"))
      (node (ref "SV58") (pin "9") (pinfunction "9_9") (pintype "passive"))
      (node (ref "SV6") (pin "1") (pinfunction "1_1") (pintype "passive"))
      (node (ref "SV6") (pin "10") (pinfunction "10_10") (pintype "passive"))
      (node (ref "SV6") (pin "11") (pinfunction "11_11") (pintype "passive"))
      (node (ref "SV6") (pin "12") (pinfunction "12_12") (pintype "passive"))
      (node (ref "SV6") (pin "2") (pinfunction "2_2") (pintype "passive"))
      (node (ref "SV6") (pin "3") (pinfunction "3_3") (pintype "passive"))
      (node (ref "SV6") (pin "4") (pinfunction "4_4") (pintype "passive"))
      (node (ref "SV6") (pin "5") (pinfunction "5_5") (pintype "passive"))
      (node (ref "SV6") (pin "6") (pinfunction "6_6") (pintype "passive"))
      (node (ref "SV6") (pin "7") (pinfunction "7_7") (pintype "passive"))
      (node (ref "SV6") (pin "8") (pinfunction "8_8") (pintype "passive"))
      (node (ref "SV6") (pin "9") (pinfunction "9_9") (pintype "passive"))
      (node (ref "SV60") (pin "1") (pinfunction "1_1") (pintype "passive"))
      (node (ref "SV60") (pin "10") (pinfunction "10_10") (pintype "passive"))
      (node (ref "SV60") (pin "11") (pinfunction "11_11") (pintype "passive"))
      (node (ref "SV60") (pin "12") (pinfunction "12_12") (pintype "passive"))
      (node (ref "SV60") (pin "2") (pinfunction "2_2") (pintype "passive"))
      (node (ref "SV60") (pin "3") (pinfunction "3_3") (pintype "passive"))
      (node (ref "SV60") (pin "4") (pinfunction "4_4") (pintype "passive"))
      (node (ref "SV60") (pin "5") (pinfunction "5_5") (pintype "passive"))
      (node (ref "SV60") (pin "6") (pinfunction "6_6") (pintype "passive"))
      (node (ref "SV60") (pin "7") (pinfunction "7_7") (pintype "passive"))
      (node (ref "SV60") (pin "8") (pinfunction "8_8") (pintype "passive"))
      (node (ref "SV60") (pin "9") (pinfunction "9_9") (pintype "passive"))
      (node (ref "SV62") (pin "1") (pinfunction "1_1") (pintype "passive"))
      (node (ref "SV62") (pin "10") (pinfunction "10_10") (pintype "passive"))
      (node (ref "SV62") (pin "11") (pinfunction "11_11") (pintype "passive"))
      (node (ref "SV62") (pin "12") (pinfunction "12_12") (pintype "passive"))
      (node (ref "SV62") (pin "2") (pinfunction "2_2") (pintype "passive"))
      (node (ref "SV62") (pin "3") (pinfunction "3_3") (pintype "passive"))
      (node (ref "SV62") (pin "4") (pinfunction "4_4") (pintype "passive"))
      (node (ref "SV62") (pin "5") (pinfunction "5_5") (pintype "passive"))
      (node (ref "SV62") (pin "6") (pinfunction "6_6") (pintype "passive"))
      (node (ref "SV62") (pin "7") (pinfunction "7_7") (pintype "passive"))
      (node (ref "SV62") (pin "8") (pinfunction "8_8") (pintype "passive"))
      (node (ref "SV62") (pin "9") (pinfunction "9_9") (pintype "passive"))
      (node (ref "SV64") (pin "1") (pinfunction "1_1") (pintype "passive"))
      (node (ref "SV64") (pin "10") (pinfunction "10_10") (pintype "passive"))
      (node (ref "SV64") (pin "11") (pinfunction "11_11") (pintype "passive"))
      (node (ref "SV64") (pin "12") (pinfunction "12_12") (pintype "passive"))
      (node (ref "SV64") (pin "2") (pinfunction "2_2") (pintype "passive"))
      (node (ref "SV64") (pin "3") (pinfunction "3_3") (pintype "passive"))
      (node (ref "SV64") (pin "4") (pinfunction "4_4") (pintype "passive"))
      (node (ref "SV64") (pin "5") (pinfunction "5_5") (pintype "passive"))
      (node (ref "SV64") (pin "6") (pinfunction "6_6") (pintype "passive"))
      (node (ref "SV64") (pin "7") (pinfunction "7_7") (pintype "passive"))
      (node (ref "SV64") (pin "8") (pinfunction "8_8") (pintype "passive"))
      (node (ref "SV64") (pin "9") (pinfunction "9_9") (pintype "passive"))
      (node (ref "SV66") (pin "1") (pinfunction "1_1") (pintype "passive"))
      (node (ref "SV66") (pin "10") (pinfunction "10_10") (pintype "passive"))
      (node (ref "SV66") (pin "11") (pinfunction "11_11") (pintype "passive"))
      (node (ref "SV66") (pin "12") (pinfunction "12_12") (pintype "passive"))
      (node (ref "SV66") (pin "2") (pinfunction "2_2") (pintype "passive"))
      (node (ref "SV66") (pin "3") (pinfunction "3_3") (pintype "passive"))
      (node (ref "SV66") (pin "4") (pinfunction "4_4") (pintype "passive"))
      (node (ref "SV66") (pin "5") (pinfunction "5_5") (pintype "passive"))
      (node (ref "SV66") (pin "6") (pinfunction "6_6") (pintype "passive"))
      (node (ref "SV66") (pin "7") (pinfunction "7_7") (pintype "passive"))
      (node (ref "SV66") (pin "8") (pinfunction "8_8") (pintype "passive"))
      (node (ref "SV66") (pin "9") (pinfunction "9_9") (pintype "passive"))
      (node (ref "SV68") (pin "1") (pinfunction "1_1") (pintype "passive"))
      (node (ref "SV68") (pin "10") (pinfunction "10_10") (pintype "passive"))
      (node (ref "SV68") (pin "11") (pinfunction "11_11") (pintype "passive"))
      (node (ref "SV68") (pin "12") (pinfunction "12_12") (pintype "passive"))
      (node (ref "SV68") (pin "2") (pinfunction "2_2") (pintype "passive"))
      (node (ref "SV68") (pin "3") (pinfunction "3_3") (pintype "passive"))
      (node (ref "SV68") (pin "4") (pinfunction "4_4") (pintype "passive"))
      (node (ref "SV68") (pin "5") (pinfunction "5_5") (pintype "passive"))
      (node (ref "SV68") (pin "6") (pinfunction "6_6") (pintype "passive"))
      (node (ref "SV68") (pin "7") (pinfunction "7_7") (pintype "passive"))
      (node (ref "SV68") (pin "8") (pinfunction "8_8") (pintype "passive"))
      (node (ref "SV68") (pin "9") (pinfunction "9_9") (pintype "passive"))
      (node (ref "SV70") (pin "1") (pinfunction "1_1") (pintype "passive"))
      (node (ref "SV70") (pin "10") (pinfunction "10_10") (pintype "passive"))
      (node (ref "SV70") (pin "11") (pinfunction "11_11") (pintype "passive"))
      (node (ref "SV70") (pin "12") (pinfunction "12_12") (pintype "passive"))
      (node (ref "SV70") (pin "2") (pinfunction "2_2") (pintype "passive"))
      (node (ref "SV70") (pin "3") (pinfunction "3_3") (pintype "passive"))
      (node (ref "SV70") (pin "4") (pinfunction "4_4") (pintype "passive"))
      (node (ref "SV70") (pin "5") (pinfunction "5_5") (pintype "passive"))
      (node (ref "SV70") (pin "6") (pinfunction "6_6") (pintype "passive"))
      (node (ref "SV70") (pin "7") (pinfunction "7_7") (pintype "passive"))
      (node (ref "SV70") (pin "8") (pinfunction "8_8") (pintype "passive"))
      (node (ref "SV70") (pin "9") (pinfunction "9_9") (pintype "passive"))
      (node (ref "SV72") (pin "1") (pinfunction "1_1") (pintype "passive"))
      (node (ref "SV72") (pin "10") (pinfunction "10_10") (pintype "passive"))
      (node (ref "SV72") (pin "11") (pinfunction "11_11") (pintype "passive"))
      (node (ref "SV72") (pin "12") (pinfunction "12_12") (pintype "passive"))
      (node (ref "SV72") (pin "2") (pinfunction "2_2") (pintype "passive"))
      (node (ref "SV72") (pin "3") (pinfunction "3_3") (pintype "passive"))
      (node (ref "SV72") (pin "4") (pinfunction "4_4") (pintype "passive"))
      (node (ref "SV72") (pin "5") (pinfunction "5_5") (pintype "passive"))
      (node (ref "SV72") (pin "6") (pinfunction "6_6") (pintype "passive"))
      (node (ref "SV72") (pin "7") (pinfunction "7_7") (pintype "passive"))
      (node (ref "SV72") (pin "8") (pinfunction "8_8") (pintype "passive"))
      (node (ref "SV72") (pin "9") (pinfunction "9_9") (pintype "passive"))
      (node (ref "SV74") (pin "1") (pinfunction "1_1") (pintype "passive"))
      (node (ref "SV74") (pin "10") (pinfunction "10_10") (pintype "passive"))
      (node (ref "SV74") (pin "11") (pinfunction "11_11") (pintype "passive"))
      (node (ref "SV74") (pin "12") (pinfunction "12_12") (pintype "passive"))
      (node (ref "SV74") (pin "2") (pinfunction "2_2") (pintype "passive"))
      (node (ref "SV74") (pin "3") (pinfunction "3_3") (pintype "passive"))
      (node (ref "SV74") (pin "4") (pinfunction "4_4") (pintype "passive"))
      (node (ref "SV74") (pin "5") (pinfunction "5_5") (pintype "passive"))
      (node (ref "SV74") (pin "6") (pinfunction "6_6") (pintype "passive"))
      (node (ref "SV74") (pin "7") (pinfunction "7_7") (pintype "passive"))
      (node (ref "SV74") (pin "8") (pinfunction "8_8") (pintype "passive"))
      (node (ref "SV74") (pin "9") (pinfunction "9_9") (pintype "passive"))
      (node (ref "SV76") (pin "1") (pinfunction "1_1") (pintype "passive"))
      (node (ref "SV76") (pin "10") (pinfunction "10_10") (pintype "passive"))
      (node (ref "SV76") (pin "11") (pinfunction "11_11") (pintype "passive"))
      (node (ref "SV76") (pin "12") (pinfunction "12_12") (pintype "passive"))
      (node (ref "SV76") (pin "2") (pinfunction "2_2") (pintype "passive"))
      (node (ref "SV76") (pin "3") (pinfunction "3_3") (pintype "passive"))
      (node (ref "SV76") (pin "4") (pinfunction "4_4") (pintype "passive"))
      (node (ref "SV76") (pin "5") (pinfunction "5_5") (pintype "passive"))
      (node (ref "SV76") (pin "6") (pinfunction "6_6") (pintype "passive"))
      (node (ref "SV76") (pin "7") (pinfunction "7_7") (pintype "passive"))
      (node (ref "SV76") (pin "8") (pinfunction "8_8") (pintype "passive"))
      (node (ref "SV76") (pin "9") (pinfunction "9_9") (pintype "passive"))
      (node (ref "SV78") (pin "1") (pinfunction "1_1") (pintype "passive"))
      (node (ref "SV78") (pin "10") (pinfunction "10_10") (pintype "passive"))
      (node (ref "SV78") (pin "11") (pinfunction "11_11") (pintype "passive"))
      (node (ref "SV78") (pin "12") (pinfunction "12_12") (pintype "passive"))
      (node (ref "SV78") (pin "2") (pinfunction "2_2") (pintype "passive"))
      (node (ref "SV78") (pin "3") (pinfunction "3_3") (pintype "passive"))
      (node (ref "SV78") (pin "4") (pinfunction "4_4") (pintype "passive"))
      (node (ref "SV78") (pin "5") (pinfunction "5_5") (pintype "passive"))
      (node (ref "SV78") (pin "6") (pinfunction "6_6") (pintype "passive"))
      (node (ref "SV78") (pin "7") (pinfunction "7_7") (pintype "passive"))
      (node (ref "SV78") (pin "8") (pinfunction "8_8") (pintype "passive"))
      (node (ref "SV78") (pin "9") (pinfunction "9_9") (pintype "passive"))
      (node (ref "SV8") (pin "1") (pinfunction "1_1") (pintype "passive"))
      (node (ref "SV8") (pin "10") (pinfunction "10_10") (pintype "passive"))
      (node (ref "SV8") (pin "11") (pinfunction "11_11") (pintype "passive"))
      (node (ref "SV8") (pin "12") (pinfunction "12_12") (pintype "passive"))
      (node (ref "SV8") (pin "2") (pinfunction "2_2") (pintype "passive"))
      (node (ref "SV8") (pin "3") (pinfunction "3_3") (pintype "passive"))
      (node (ref "SV8") (pin "4") (pinfunction "4_4") (pintype "passive"))
      (node (ref "SV8") (pin "5") (pinfunction "5_5") (pintype "passive"))
      (node (ref "SV8") (pin "6") (pinfunction "6_6") (pintype "passive"))
      (node (ref "SV8") (pin "7") (pinfunction "7_7") (pintype "passive"))
      (node (ref "SV8") (pin "8") (pinfunction "8_8") (pintype "passive"))
      (node (ref "SV8") (pin "9") (pinfunction "9_9") (pintype "passive"))
      (node (ref "SV80") (pin "1") (pinfunction "1_1") (pintype "passive"))
      (node (ref "SV80") (pin "10") (pinfunction "10_10") (pintype "passive"))
      (node (ref "SV80") (pin "11") (pinfunction "11_11") (pintype "passive"))
      (node (ref "SV80") (pin "12") (pinfunction "12_12") (pintype "passive"))
      (node (ref "SV80") (pin "2") (pinfunction "2_2") (pintype "passive"))
      (node (ref "SV80") (pin "3") (pinfunction "3_3") (pintype "passive"))
      (node (ref "SV80") (pin "4") (pinfunction "4_4") (pintype "passive"))
      (node (ref "SV80") (pin "5") (pinfunction "5_5") (pintype "passive"))
      (node (ref "SV80") (pin "6") (pinfunction "6_6") (pintype "passive"))
      (node (ref "SV80") (pin "7") (pinfunction "7_7") (pintype "passive"))
      (node (ref "SV80") (pin "8") (pinfunction "8_8") (pintype "passive"))
      (node (ref "SV80") (pin "9") (pinfunction "9_9") (pintype "passive"))
      (node (ref "SV82") (pin "1") (pinfunction "1_1") (pintype "passive"))
      (node (ref "SV82") (pin "10") (pinfunction "10_10") (pintype "passive"))
      (node (ref "SV82") (pin "11") (pinfunction "11_11") (pintype "passive"))
      (node (ref "SV82") (pin "12") (pinfunction "12_12") (pintype "passive"))
      (node (ref "SV82") (pin "2") (pinfunction "2_2") (pintype "passive"))
      (node (ref "SV82") (pin "3") (pinfunction "3_3") (pintype "passive"))
      (node (ref "SV82") (pin "4") (pinfunction "4_4") (pintype "passive"))
      (node (ref "SV82") (pin "5") (pinfunction "5_5") (pintype "passive"))
      (node (ref "SV82") (pin "6") (pinfunction "6_6") (pintype "passive"))
      (node (ref "SV82") (pin "7") (pinfunction "7_7") (pintype "passive"))
      (node (ref "SV82") (pin "8") (pinfunction "8_8") (pintype "passive"))
      (node (ref "SV82") (pin "9") (pinfunction "9_9") (pintype "passive"))
      (node (ref "SV84") (pin "1") (pinfunction "1_1") (pintype "passive"))
      (node (ref "SV84") (pin "10") (pinfunction "10_10") (pintype "passive"))
      (node (ref "SV84") (pin "11") (pinfunction "11_11") (pintype "passive"))
      (node (ref "SV84") (pin "12") (pinfunction "12_12") (pintype "passive"))
      (node (ref "SV84") (pin "2") (pinfunction "2_2") (pintype "passive"))
      (node (ref "SV84") (pin "3") (pinfunction "3_3") (pintype "passive"))
      (node (ref "SV84") (pin "4") (pinfunction "4_4") (pintype "passive"))
      (node (ref "SV84") (pin "5") (pinfunction "5_5") (pintype "passive"))
      (node (ref "SV84") (pin "6") (pinfunction "6_6") (pintype "passive"))
      (node (ref "SV84") (pin "7") (pinfunction "7_7") (pintype "passive"))
      (node (ref "SV84") (pin "8") (pinfunction "8_8") (pintype "passive"))
      (node (ref "SV84") (pin "9") (pinfunction "9_9") (pintype "passive"))
      (node (ref "SV86") (pin "1") (pinfunction "1_1") (pintype "passive"))
      (node (ref "SV86") (pin "10") (pinfunction "10_10") (pintype "passive"))
      (node (ref "SV86") (pin "11") (pinfunction "11_11") (pintype "passive"))
      (node (ref "SV86") (pin "12") (pinfunction "12_12") (pintype "passive"))
      (node (ref "SV86") (pin "2") (pinfunction "2_2") (pintype "passive"))
      (node (ref "SV86") (pin "3") (pinfunction "3_3") (pintype "passive"))
      (node (ref "SV86") (pin "4") (pinfunction "4_4") (pintype "passive"))
      (node (ref "SV86") (pin "5") (pinfunction "5_5") (pintype "passive"))
      (node (ref "SV86") (pin "6") (pinfunction "6_6") (pintype "passive"))
      (node (ref "SV86") (pin "7") (pinfunction "7_7") (pintype "passive"))
      (node (ref "SV86") (pin "8") (pinfunction "8_8") (pintype "passive"))
      (node (ref "SV86") (pin "9") (pinfunction "9_9") (pintype "passive"))
      (node (ref "SV88") (pin "1") (pinfunction "1_1") (pintype "passive"))
      (node (ref "SV88") (pin "10") (pinfunction "10_10") (pintype "passive"))
      (node (ref "SV88") (pin "11") (pinfunction "11_11") (pintype "passive"))
      (node (ref "SV88") (pin "12") (pinfunction "12_12") (pintype "passive"))
      (node (ref "SV88") (pin "2") (pinfunction "2_2") (pintype "passive"))
      (node (ref "SV88") (pin "3") (pinfunction "3_3") (pintype "passive"))
      (node (ref "SV88") (pin "4") (pinfunction "4_4") (pintype "passive"))
      (node (ref "SV88") (pin "5") (pinfunction "5_5") (pintype "passive"))
      (node (ref "SV88") (pin "6") (pinfunction "6_6") (pintype "passive"))
      (node (ref "SV88") (pin "7") (pinfunction "7_7") (pintype "passive"))
      (node (ref "SV88") (pin "8") (pinfunction "8_8") (pintype "passive"))
      (node (ref "SV88") (pin "9") (pinfunction "9_9") (pintype "passive"))
      (node (ref "SV90") (pin "1") (pinfunction "1_1") (pintype "passive"))
      (node (ref "SV90") (pin "10") (pinfunction "10_10") (pintype "passive"))
      (node (ref "SV90") (pin "11") (pinfunction "11_11") (pintype "passive"))
      (node (ref "SV90") (pin "12") (pinfunction "12_12") (pintype "passive"))
      (node (ref "SV90") (pin "2") (pinfunction "2_2") (pintype "passive"))
      (node (ref "SV90") (pin "3") (pinfunction "3_3") (pintype "passive"))
      (node (ref "SV90") (pin "4") (pinfunction "4_4") (pintype "passive"))
      (node (ref "SV90") (pin "5") (pinfunction "5_5") (pintype "passive"))
      (node (ref "SV90") (pin "6") (pinfunction "6_6") (pintype "passive"))
      (node (ref "SV90") (pin "7") (pinfunction "7_7") (pintype "passive"))
      (node (ref "SV90") (pin "8") (pinfunction "8_8") (pintype "passive"))
      (node (ref "SV90") (pin "9") (pinfunction "9_9") (pintype "passive"))
      (node (ref "U$2") (pin "AC1") (pinfunction "1_AC1") (pintype "bidirectional"))
      (node (ref "U$2") (pin "AC2") (pinfunction "1_AC2") (pintype "bidirectional"))
      (node (ref "U$2") (pin "AF1") (pinfunction "1_AF1") (pintype "bidirectional"))
      (node (ref "U$2") (pin "AF2") (pinfunction "1_AF2") (pintype "bidirectional"))
      (node (ref "U$2") (pin "AN1") (pinfunction "1_AN1") (pintype "bidirectional"))
      (node (ref "U$2") (pin "AN2") (pinfunction "1_AN2") (pintype "bidirectional"))
      (node (ref "U$2") (pin "AT1") (pinfunction "1_AT1") (pintype "bidirectional"))
      (node (ref "U$2") (pin "AT2") (pinfunction "1_AT2") (pintype "bidirectional"))
      (node (ref "U$2") (pin "BC1") (pinfunction "1_BC1") (pintype "bidirectional"))
      (node (ref "U$2") (pin "BC2") (pinfunction "1_BC2") (pintype "bidirectional"))
      (node (ref "U$2") (pin "BF1") (pinfunction "1_BF1") (pintype "bidirectional"))
      (node (ref "U$2") (pin "BF2") (pinfunction "1_BF2") (pintype "bidirectional"))
      (node (ref "U$2") (pin "BN1") (pinfunction "1_BN1") (pintype "bidirectional"))
      (node (ref "U$2") (pin "BN2") (pinfunction "1_BN2") (pintype "bidirectional"))
      (node (ref "U$2") (pin "BT1") (pinfunction "1_BT1") (pintype "bidirectional"))
      (node (ref "U$2") (pin "BT2") (pinfunction "1_BT2") (pintype "bidirectional"))
      (node (ref "U$2") (pin "CC1") (pinfunction "1_CC1") (pintype "bidirectional"))
      (node (ref "U$2") (pin "CC2") (pinfunction "1_CC2") (pintype "bidirectional"))
      (node (ref "U$2") (pin "CF1") (pinfunction "1_CF1") (pintype "bidirectional"))
      (node (ref "U$2") (pin "CF2") (pinfunction "1_CF2") (pintype "bidirectional"))
      (node (ref "U$2") (pin "CN1") (pinfunction "1_CN1") (pintype "bidirectional"))
      (node (ref "U$2") (pin "CN2") (pinfunction "1_CN2") (pintype "bidirectional"))
      (node (ref "U$2") (pin "CT1") (pinfunction "1_CT1") (pintype "bidirectional"))
      (node (ref "U$2") (pin "CT2") (pinfunction "1_CT2") (pintype "bidirectional"))
      (node (ref "U$2") (pin "DC1") (pinfunction "1_DC1") (pintype "bidirectional"))
      (node (ref "U$2") (pin "DC2") (pinfunction "1_DC2") (pintype "bidirectional"))
      (node (ref "U$2") (pin "DF1") (pinfunction "1_DF1") (pintype "bidirectional"))
      (node (ref "U$2") (pin "DF2") (pinfunction "1_DF2") (pintype "bidirectional"))
      (node (ref "U$2") (pin "DN1") (pinfunction "1_DN1") (pintype "bidirectional"))
      (node (ref "U$2") (pin "DN2") (pinfunction "1_DN2") (pintype "bidirectional"))
      (node (ref "U$2") (pin "DT1") (pinfunction "1_DT1") (pintype "bidirectional"))
      (node (ref "U$2") (pin "DT2") (pinfunction "1_DT2") (pintype "bidirectional"))
    )
    (net (code "4") (name "INHIBIT") (class "Default")
      (node (ref "D10") (pin "13") (pinfunction "13_13") (pintype "passive"))
      (node (ref "U$2") (pin "AP2") (pinfunction "1_AP2") (pintype "bidirectional"))
    )
    (net (code "5") (name "INITIALIZE") (class "Default")
      (node (ref "D11") (pin "14") (pinfunction "14_14") (pintype "passive"))
      (node (ref "U$2") (pin "CR1") (pinfunction "1_CR1") (pintype "bidirectional"))
    )
    (net (code "6") (name "INT_IN_PROG") (class "Default")
      (node (ref "D8") (pin "13") (pinfunction "13_13") (pintype "passive"))
      (node (ref "U$2") (pin "BP2") (pinfunction "1_BP2") (pintype "bidirectional"))
    )
    (net (code "7") (name "INT_STROBE") (class "Default")
      (node (ref "D8") (pin "4") (pinfunction "4_4") (pintype "passive"))
      (node (ref "U$2") (pin "BD2") (pinfunction "1_BD2") (pintype "bidirectional"))
    )
    (net (code "8") (name "Net-(IC1-Pad1)") (class "Default")
      (node (ref "IC1") (pin "1") (pinfunction "1_1") (pintype "passive"))
      (node (ref "IC2") (pin "1") (pinfunction "1_1") (pintype "passive"))
      (node (ref "IC3") (pin "1") (pinfunction "1_1") (pintype "passive"))
      (node (ref "IC4") (pin "1") (pinfunction "1_1") (pintype "passive"))
    )
    (net (code "9") (name "Net-(IC1-Pad2)") (class "Default")
      (node (ref "IC1") (pin "2") (pinfunction "2_2") (pintype "passive"))
      (node (ref "IC2") (pin "2") (pinfunction "2_2") (pintype "passive"))
      (node (ref "IC3") (pin "2") (pinfunction "2_2") (pintype "passive"))
      (node (ref "IC4") (pin "2") (pinfunction "2_2") (pintype "passive"))
    )
    (net (code "10") (name "Net-(IC1-Pad3)") (class "Default")
      (node (ref "IC1") (pin "3") (pinfunction "3_3") (pintype "passive"))
      (node (ref "IC2") (pin "3") (pinfunction "3_3") (pintype "passive"))
      (node (ref "IC3") (pin "3") (pinfunction "3_3") (pintype "passive"))
      (node (ref "IC4") (pin "3") (pinfunction "3_3") (pintype "passive"))
    )
    (net (code "11") (name "Net-(IC1-Pad4)") (class "Default")
      (node (ref "IC1") (pin "4") (pinfunction "4_4") (pintype "passive"))
      (node (ref "IC2") (pin "4") (pinfunction "4_4") (pintype "passive"))
      (node (ref "IC3") (pin "4") (pinfunction "4_4") (pintype "passive"))
      (node (ref "IC4") (pin "4") (pinfunction "4_4") (pintype "passive"))
    )
    (net (code "12") (name "Net-(IC1-Pad5)") (class "Default")
      (node (ref "IC1") (pin "5") (pinfunction "5_5") (pintype "passive"))
      (node (ref "IC2") (pin "5") (pinfunction "5_5") (pintype "passive"))
      (node (ref "IC3") (pin "5") (pinfunction "5_5") (pintype "passive"))
      (node (ref "IC4") (pin "5") (pinfunction "5_5") (pintype "passive"))
    )
    (net (code "13") (name "Net-(IC1-Pad6)") (class "Default")
      (node (ref "IC1") (pin "6") (pinfunction "6_6") (pintype "passive"))
      (node (ref "IC2") (pin "6") (pinfunction "6_6") (pintype "passive"))
      (node (ref "IC3") (pin "6") (pinfunction "6_6") (pintype "passive"))
      (node (ref "IC4") (pin "6") (pinfunction "6_6") (pintype "passive"))
    )
    (net (code "14") (name "Net-(IC1-Pad7)") (class "Default")
      (node (ref "IC1") (pin "7") (pinfunction "7_7") (pintype "passive"))
      (node (ref "IC2") (pin "7") (pinfunction "7_7") (pintype "passive"))
      (node (ref "IC3") (pin "7") (pinfunction "7_7") (pintype "passive"))
      (node (ref "IC4") (pin "7") (pinfunction "7_7") (pintype "passive"))
    )
    (net (code "15") (name "Net-(IC1-Pad8)") (class "Default")
      (node (ref "IC1") (pin "8") (pinfunction "8_8") (pintype "passive"))
      (node (ref "IC2") (pin "8") (pinfunction "8_8") (pintype "passive"))
      (node (ref "IC3") (pin "8") (pinfunction "8_8") (pintype "passive"))
      (node (ref "IC4") (pin "8") (pinfunction "8_8") (pintype "passive"))
    )
    (net (code "16") (name "Net-(IC1-Pad9)") (class "Default")
      (node (ref "IC1") (pin "9") (pinfunction "9_9") (pintype "passive"))
      (node (ref "IC2") (pin "9") (pinfunction "9_9") (pintype "passive"))
      (node (ref "IC3") (pin "9") (pinfunction "9_9") (pintype "passive"))
      (node (ref "IC4") (pin "9") (pinfunction "9_9") (pintype "passive"))
    )
    (net (code "17") (name "Net-(IC1-Pad10)") (class "Default")
      (node (ref "IC1") (pin "10") (pinfunction "10_10") (pintype "passive"))
      (node (ref "IC2") (pin "10") (pinfunction "10_10") (pintype "passive"))
      (node (ref "IC3") (pin "10") (pinfunction "10_10") (pintype "passive"))
      (node (ref "IC4") (pin "10") (pinfunction "10_10") (pintype "passive"))
    )
    (net (code "18") (name "Net-(IC1-Pad11)") (class "Default")
      (node (ref "IC1") (pin "11") (pinfunction "11_11") (pintype "passive"))
      (node (ref "IC2") (pin "11") (pinfunction "11_11") (pintype "passive"))
      (node (ref "IC3") (pin "11") (pinfunction "11_11") (pintype "passive"))
      (node (ref "IC4") (pin "11") (pinfunction "11_11") (pintype "passive"))
    )
    (net (code "19") (name "Net-(IC1-Pad12)") (class "Default")
      (node (ref "IC1") (pin "12") (pinfunction "12_12") (pintype "passive"))
      (node (ref "IC2") (pin "12") (pinfunction "12_12") (pintype "passive"))
      (node (ref "IC3") (pin "12") (pinfunction "12_12") (pintype "passive"))
      (node (ref "IC4") (pin "12") (pinfunction "12_12") (pintype "passive"))
    )
    (net (code "20") (name "Net-(IC1-Pad13)") (class "Default")
      (node (ref "IC1") (pin "13") (pinfunction "13_13") (pintype "passive"))
      (node (ref "IC2") (pin "13") (pinfunction "13_13") (pintype "passive"))
      (node (ref "IC3") (pin "13") (pinfunction "13_13") (pintype "passive"))
      (node (ref "IC4") (pin "13") (pinfunction "13_13") (pintype "passive"))
    )
    (net (code "21") (name "Net-(IC1-Pad14)") (class "Default")
      (node (ref "IC1") (pin "14") (pinfunction "14_14") (pintype "passive"))
      (node (ref "IC2") (pin "14") (pinfunction "14_14") (pintype "passive"))
      (node (ref "IC3") (pin "14") (pinfunction "14_14") (pintype "passive"))
      (node (ref "IC4") (pin "14") (pinfunction "14_14") (pintype "passive"))
    )
    (net (code "22") (name "Net-(IC1-Pad15)") (class "Default")
      (node (ref "IC1") (pin "15") (pinfunction "15_15") (pintype "passive"))
      (node (ref "IC2") (pin "15") (pinfunction "15_15") (pintype "passive"))
      (node (ref "IC3") (pin "15") (pinfunction "15_15") (pintype "passive"))
      (node (ref "IC4") (pin "15") (pinfunction "15_15") (pintype "passive"))
    )
    (net (code "23") (name "Net-(IC1-Pad16)") (class "Default")
      (node (ref "IC1") (pin "16") (pinfunction "16_16") (pintype "passive"))
      (node (ref "IC2") (pin "16") (pinfunction "16_16") (pintype "passive"))
      (node (ref "IC3") (pin "16") (pinfunction "16_16") (pintype "passive"))
      (node (ref "IC4") (pin "16") (pinfunction "16_16") (pintype "passive"))
    )
    (net (code "24") (name "Net-(IC1-Pad17)") (class "Default")
      (node (ref "IC1") (pin "17") (pinfunction "17_17") (pintype "passive"))
      (node (ref "IC2") (pin "17") (pinfunction "17_17") (pintype "passive"))
      (node (ref "IC3") (pin "17") (pinfunction "17_17") (pintype "passive"))
      (node (ref "IC4") (pin "17") (pinfunction "17_17") (pintype "passive"))
    )
    (net (code "25") (name "Net-(IC1-Pad18)") (class "Default")
      (node (ref "IC1") (pin "18") (pinfunction "18_18") (pintype "passive"))
      (node (ref "IC2") (pin "18") (pinfunction "18_18") (pintype "passive"))
      (node (ref "IC3") (pin "18") (pinfunction "18_18") (pintype "passive"))
      (node (ref "IC4") (pin "18") (pinfunction "18_18") (pintype "passive"))
    )
    (net (code "26") (name "Net-(IC1-Pad19)") (class "Default")
      (node (ref "IC1") (pin "19") (pinfunction "19_19") (pintype "passive"))
      (node (ref "IC2") (pin "19") (pinfunction "19_19") (pintype "passive"))
      (node (ref "IC3") (pin "19") (pinfunction "19_19") (pintype "passive"))
      (node (ref "IC4") (pin "19") (pinfunction "19_19") (pintype "passive"))
    )
    (net (code "27") (name "Net-(IC1-Pad20)") (class "Default")
      (node (ref "IC1") (pin "20") (pinfunction "20_20") (pintype "passive"))
      (node (ref "IC2") (pin "20") (pinfunction "20_20") (pintype "passive"))
      (node (ref "IC3") (pin "20") (pinfunction "20_20") (pintype "passive"))
      (node (ref "IC4") (pin "20") (pinfunction "20_20") (pintype "passive"))
    )
    (net (code "28") (name "Net-(IC1-Pad21)") (class "Default")
      (node (ref "IC1") (pin "21") (pinfunction "21_21") (pintype "passive"))
      (node (ref "IC2") (pin "21") (pinfunction "21_21") (pintype "passive"))
      (node (ref "IC3") (pin "21") (pinfunction "21_21") (pintype "passive"))
      (node (ref "IC4") (pin "21") (pinfunction "21_21") (pintype "passive"))
    )
    (net (code "29") (name "Net-(IC1-Pad22)") (class "Default")
      (node (ref "IC1") (pin "22") (pinfunction "22_22") (pintype "passive"))
      (node (ref "IC2") (pin "22") (pinfunction "22_22") (pintype "passive"))
      (node (ref "IC3") (pin "22") (pinfunction "22_22") (pintype "passive"))
      (node (ref "IC4") (pin "22") (pinfunction "22_22") (pintype "passive"))
    )
    (net (code "30") (name "Net-(IC1-Pad23)") (class "Default")
      (node (ref "IC1") (pin "23") (pinfunction "23_23") (pintype "passive"))
      (node (ref "IC2") (pin "23") (pinfunction "23_23") (pintype "passive"))
      (node (ref "IC3") (pin "23") (pinfunction "23_23") (pintype "passive"))
      (node (ref "IC4") (pin "23") (pinfunction "23_23") (pintype "passive"))
    )
    (net (code "31") (name "Net-(IC1-Pad24)") (class "Default")
      (node (ref "IC1") (pin "24") (pinfunction "24_24") (pintype "passive"))
      (node (ref "IC2") (pin "24") (pinfunction "24_24") (pintype "passive"))
      (node (ref "IC3") (pin "24") (pinfunction "24_24") (pintype "passive"))
      (node (ref "IC4") (pin "24") (pinfunction "24_24") (pintype "passive"))
    )
    (net (code "32") (name "Net-(IC5-Pad1)") (class "Default")
      (node (ref "IC5") (pin "1") (pinfunction "1_1") (pintype "passive"))
      (node (ref "IC6") (pin "1") (pinfunction "1_1") (pintype "passive"))
      (node (ref "IC7") (pin "1") (pinfunction "1_1") (pintype "passive"))
      (node (ref "IC8") (pin "1") (pinfunction "1_1") (pintype "passive"))
    )
    (net (code "33") (name "Net-(IC5-Pad2)") (class "Default")
      (node (ref "IC5") (pin "2") (pinfunction "2_2") (pintype "passive"))
      (node (ref "IC6") (pin "2") (pinfunction "2_2") (pintype "passive"))
      (node (ref "IC7") (pin "2") (pinfunction "2_2") (pintype "passive"))
      (node (ref "IC8") (pin "2") (pinfunction "2_2") (pintype "passive"))
    )
    (net (code "34") (name "Net-(IC5-Pad3)") (class "Default")
      (node (ref "IC5") (pin "3") (pinfunction "3_3") (pintype "passive"))
      (node (ref "IC6") (pin "3") (pinfunction "3_3") (pintype "passive"))
      (node (ref "IC7") (pin "3") (pinfunction "3_3") (pintype "passive"))
      (node (ref "IC8") (pin "3") (pinfunction "3_3") (pintype "passive"))
    )
    (net (code "35") (name "Net-(IC5-Pad4)") (class "Default")
      (node (ref "IC5") (pin "4") (pinfunction "4_4") (pintype "passive"))
      (node (ref "IC6") (pin "4") (pinfunction "4_4") (pintype "passive"))
      (node (ref "IC7") (pin "4") (pinfunction "4_4") (pintype "passive"))
      (node (ref "IC8") (pin "4") (pinfunction "4_4") (pintype "passive"))
    )
    (net (code "36") (name "Net-(IC5-Pad5)") (class "Default")
      (node (ref "IC5") (pin "5") (pinfunction "5_5") (pintype "passive"))
      (node (ref "IC6") (pin "5") (pinfunction "5_5") (pintype "passive"))
      (node (ref "IC7") (pin "5") (pinfunction "5_5") (pintype "passive"))
      (node (ref "IC8") (pin "5") (pinfunction "5_5") (pintype "passive"))
    )
    (net (code "37") (name "Net-(IC5-Pad6)") (class "Default")
      (node (ref "IC5") (pin "6") (pinfunction "6_6") (pintype "passive"))
      (node (ref "IC6") (pin "6") (pinfunction "6_6") (pintype "passive"))
      (node (ref "IC7") (pin "6") (pinfunction "6_6") (pintype "passive"))
      (node (ref "IC8") (pin "6") (pinfunction "6_6") (pintype "passive"))
    )
    (net (code "38") (name "Net-(IC5-Pad7)") (class "Default")
      (node (ref "IC5") (pin "7") (pinfunction "7_7") (pintype "passive"))
      (node (ref "IC6") (pin "7") (pinfunction "7_7") (pintype "passive"))
      (node (ref "IC7") (pin "7") (pinfunction "7_7") (pintype "passive"))
      (node (ref "IC8") (pin "7") (pinfunction "7_7") (pintype "passive"))
    )
    (net (code "39") (name "Net-(IC5-Pad8)") (class "Default")
      (node (ref "IC5") (pin "8") (pinfunction "8_8") (pintype "passive"))
      (node (ref "IC6") (pin "8") (pinfunction "8_8") (pintype "passive"))
      (node (ref "IC7") (pin "8") (pinfunction "8_8") (pintype "passive"))
      (node (ref "IC8") (pin "8") (pinfunction "8_8") (pintype "passive"))
    )
    (net (code "40") (name "Net-(IC5-Pad9)") (class "Default")
      (node (ref "IC5") (pin "9") (pinfunction "9_9") (pintype "passive"))
      (node (ref "IC6") (pin "9") (pinfunction "9_9") (pintype "passive"))
      (node (ref "IC7") (pin "9") (pinfunction "9_9") (pintype "passive"))
      (node (ref "IC8") (pin "9") (pinfunction "9_9") (pintype "passive"))
    )
    (net (code "41") (name "Net-(IC5-Pad10)") (class "Default")
      (node (ref "IC5") (pin "10") (pinfunction "10_10") (pintype "passive"))
      (node (ref "IC6") (pin "10") (pinfunction "10_10") (pintype "passive"))
      (node (ref "IC7") (pin "10") (pinfunction "10_10") (pintype "passive"))
      (node (ref "IC8") (pin "10") (pinfunction "10_10") (pintype "passive"))
    )
    (net (code "42") (name "Net-(IC5-Pad11)") (class "Default")
      (node (ref "IC5") (pin "11") (pinfunction "11_11") (pintype "passive"))
      (node (ref "IC6") (pin "11") (pinfunction "11_11") (pintype "passive"))
      (node (ref "IC7") (pin "11") (pinfunction "11_11") (pintype "passive"))
      (node (ref "IC8") (pin "11") (pinfunction "11_11") (pintype "passive"))
    )
    (net (code "43") (name "Net-(IC5-Pad12)") (class "Default")
      (node (ref "IC5") (pin "12") (pinfunction "12_12") (pintype "passive"))
      (node (ref "IC6") (pin "12") (pinfunction "12_12") (pintype "passive"))
      (node (ref "IC7") (pin "12") (pinfunction "12_12") (pintype "passive"))
      (node (ref "IC8") (pin "12") (pinfunction "12_12") (pintype "passive"))
    )
    (net (code "44") (name "Net-(IC5-Pad13)") (class "Default")
      (node (ref "IC5") (pin "13") (pinfunction "13_13") (pintype "passive"))
      (node (ref "IC6") (pin "13") (pinfunction "13_13") (pintype "passive"))
      (node (ref "IC7") (pin "13") (pinfunction "13_13") (pintype "passive"))
      (node (ref "IC8") (pin "13") (pinfunction "13_13") (pintype "passive"))
    )
    (net (code "45") (name "Net-(IC5-Pad14)") (class "Default")
      (node (ref "IC5") (pin "14") (pinfunction "14_14") (pintype "passive"))
      (node (ref "IC6") (pin "14") (pinfunction "14_14") (pintype "passive"))
      (node (ref "IC7") (pin "14") (pinfunction "14_14") (pintype "passive"))
      (node (ref "IC8") (pin "14") (pinfunction "14_14") (pintype "passive"))
    )
    (net (code "46") (name "Net-(IC5-Pad15)") (class "Default")
      (node (ref "IC5") (pin "15") (pinfunction "15_15") (pintype "passive"))
      (node (ref "IC6") (pin "15") (pinfunction "15_15") (pintype "passive"))
      (node (ref "IC7") (pin "15") (pinfunction "15_15") (pintype "passive"))
      (node (ref "IC8") (pin "15") (pinfunction "15_15") (pintype "passive"))
    )
    (net (code "47") (name "Net-(IC5-Pad16)") (class "Default")
      (node (ref "IC5") (pin "16") (pinfunction "16_16") (pintype "passive"))
      (node (ref "IC6") (pin "16") (pinfunction "16_16") (pintype "passive"))
      (node (ref "IC7") (pin "16") (pinfunction "16_16") (pintype "passive"))
      (node (ref "IC8") (pin "16") (pinfunction "16_16") (pintype "passive"))
    )
    (net (code "48") (name "Net-(IC5-Pad17)") (class "Default")
      (node (ref "IC5") (pin "17") (pinfunction "17_17") (pintype "passive"))
      (node (ref "IC6") (pin "17") (pinfunction "17_17") (pintype "passive"))
      (node (ref "IC7") (pin "17") (pinfunction "17_17") (pintype "passive"))
      (node (ref "IC8") (pin "17") (pinfunction "17_17") (pintype "passive"))
    )
    (net (code "49") (name "Net-(IC5-Pad18)") (class "Default")
      (node (ref "IC5") (pin "18") (pinfunction "18_18") (pintype "passive"))
      (node (ref "IC6") (pin "18") (pinfunction "18_18") (pintype "passive"))
      (node (ref "IC7") (pin "18") (pinfunction "18_18") (pintype "passive"))
      (node (ref "IC8") (pin "18") (pinfunction "18_18") (pintype "passive"))
    )
    (net (code "50") (name "Net-(IC5-Pad19)") (class "Default")
      (node (ref "IC5") (pin "19") (pinfunction "19_19") (pintype "passive"))
      (node (ref "IC6") (pin "19") (pinfunction "19_19") (pintype "passive"))
      (node (ref "IC7") (pin "19") (pinfunction "19_19") (pintype "passive"))
      (node (ref "IC8") (pin "19") (pinfunction "19_19") (pintype "passive"))
    )
    (net (code "51") (name "Net-(IC5-Pad20)") (class "Default")
      (node (ref "IC5") (pin "20") (pinfunction "20_20") (pintype "passive"))
      (node (ref "IC6") (pin "20") (pinfunction "20_20") (pintype "passive"))
      (node (ref "IC7") (pin "20") (pinfunction "20_20") (pintype "passive"))
      (node (ref "IC8") (pin "20") (pinfunction "20_20") (pintype "passive"))
    )
    (net (code "52") (name "Net-(IC5-Pad21)") (class "Default")
      (node (ref "IC5") (pin "21") (pinfunction "21_21") (pintype "passive"))
      (node (ref "IC6") (pin "21") (pinfunction "21_21") (pintype "passive"))
      (node (ref "IC7") (pin "21") (pinfunction "21_21") (pintype "passive"))
      (node (ref "IC8") (pin "21") (pinfunction "21_21") (pintype "passive"))
    )
    (net (code "53") (name "Net-(IC5-Pad22)") (class "Default")
      (node (ref "IC5") (pin "22") (pinfunction "22_22") (pintype "passive"))
      (node (ref "IC6") (pin "22") (pinfunction "22_22") (pintype "passive"))
      (node (ref "IC7") (pin "22") (pinfunction "22_22") (pintype "passive"))
      (node (ref "IC8") (pin "22") (pinfunction "22_22") (pintype "passive"))
    )
    (net (code "54") (name "Net-(IC5-Pad23)") (class "Default")
      (node (ref "IC5") (pin "23") (pinfunction "23_23") (pintype "passive"))
      (node (ref "IC6") (pin "23") (pinfunction "23_23") (pintype "passive"))
      (node (ref "IC7") (pin "23") (pinfunction "23_23") (pintype "passive"))
      (node (ref "IC8") (pin "23") (pinfunction "23_23") (pintype "passive"))
    )
    (net (code "55") (name "Net-(IC5-Pad24)") (class "Default")
      (node (ref "IC5") (pin "24") (pinfunction "24_24") (pintype "passive"))
      (node (ref "IC6") (pin "24") (pinfunction "24_24") (pintype "passive"))
      (node (ref "IC7") (pin "24") (pinfunction "24_24") (pintype "passive"))
      (node (ref "IC8") (pin "24") (pinfunction "24_24") (pintype "passive"))
    )
    (net (code "56") (name "Net-(IC10-Pad1)") (class "Default")
      (node (ref "IC10") (pin "1") (pinfunction "1_1") (pintype "passive"))
      (node (ref "IC11") (pin "1") (pinfunction "1_1") (pintype "passive"))
      (node (ref "IC12") (pin "1") (pinfunction "1_1") (pintype "passive"))
      (node (ref "IC13") (pin "1") (pinfunction "1_1") (pintype "passive"))
    )
    (net (code "57") (name "Net-(IC10-Pad2)") (class "Default")
      (node (ref "IC10") (pin "2") (pinfunction "2_2") (pintype "passive"))
      (node (ref "IC11") (pin "2") (pinfunction "2_2") (pintype "passive"))
      (node (ref "IC12") (pin "2") (pinfunction "2_2") (pintype "passive"))
      (node (ref "IC13") (pin "2") (pinfunction "2_2") (pintype "passive"))
    )
    (net (code "58") (name "Net-(IC10-Pad3)") (class "Default")
      (node (ref "IC10") (pin "3") (pinfunction "3_3") (pintype "passive"))
      (node (ref "IC11") (pin "3") (pinfunction "3_3") (pintype "passive"))
      (node (ref "IC12") (pin "3") (pinfunction "3_3") (pintype "passive"))
      (node (ref "IC13") (pin "3") (pinfunction "3_3") (pintype "passive"))
    )
    (net (code "59") (name "Net-(IC10-Pad4)") (class "Default")
      (node (ref "IC10") (pin "4") (pinfunction "4_4") (pintype "passive"))
      (node (ref "IC11") (pin "4") (pinfunction "4_4") (pintype "passive"))
      (node (ref "IC12") (pin "4") (pinfunction "4_4") (pintype "passive"))
      (node (ref "IC13") (pin "4") (pinfunction "4_4") (pintype "passive"))
    )
    (net (code "60") (name "Net-(IC10-Pad5)") (class "Default")
      (node (ref "IC10") (pin "5") (pinfunction "5_5") (pintype "passive"))
      (node (ref "IC11") (pin "5") (pinfunction "5_5") (pintype "passive"))
      (node (ref "IC12") (pin "5") (pinfunction "5_5") (pintype "passive"))
      (node (ref "IC13") (pin "5") (pinfunction "5_5") (pintype "passive"))
    )
    (net (code "61") (name "Net-(IC10-Pad6)") (class "Default")
      (node (ref "IC10") (pin "6") (pinfunction "6_6") (pintype "passive"))
      (node (ref "IC11") (pin "6") (pinfunction "6_6") (pintype "passive"))
      (node (ref "IC12") (pin "6") (pinfunction "6_6") (pintype "passive"))
      (node (ref "IC13") (pin "6") (pinfunction "6_6") (pintype "passive"))
    )
    (net (code "62") (name "Net-(IC10-Pad7)") (class "Default")
      (node (ref "IC10") (pin "7") (pinfunction "7_7") (pintype "passive"))
      (node (ref "IC11") (pin "7") (pinfunction "7_7") (pintype "passive"))
      (node (ref "IC12") (pin "7") (pinfunction "7_7") (pintype "passive"))
      (node (ref "IC13") (pin "7") (pinfunction "7_7") (pintype "passive"))
    )
    (net (code "63") (name "Net-(IC10-Pad8)") (class "Default")
      (node (ref "IC10") (pin "8") (pinfunction "8_8") (pintype "passive"))
      (node (ref "IC11") (pin "8") (pinfunction "8_8") (pintype "passive"))
      (node (ref "IC12") (pin "8") (pinfunction "8_8") (pintype "passive"))
      (node (ref "IC13") (pin "8") (pinfunction "8_8") (pintype "passive"))
    )
    (net (code "64") (name "Net-(IC10-Pad9)") (class "Default")
      (node (ref "IC10") (pin "9") (pinfunction "9_9") (pintype "passive"))
      (node (ref "IC11") (pin "9") (pinfunction "9_9") (pintype "passive"))
      (node (ref "IC12") (pin "9") (pinfunction "9_9") (pintype "passive"))
      (node (ref "IC13") (pin "9") (pinfunction "9_9") (pintype "passive"))
    )
    (net (code "65") (name "Net-(IC10-Pad10)") (class "Default")
      (node (ref "IC10") (pin "10") (pinfunction "10_10") (pintype "passive"))
      (node (ref "IC11") (pin "10") (pinfunction "10_10") (pintype "passive"))
      (node (ref "IC12") (pin "10") (pinfunction "10_10") (pintype "passive"))
      (node (ref "IC13") (pin "10") (pinfunction "10_10") (pintype "passive"))
    )
    (net (code "66") (name "Net-(IC10-Pad11)") (class "Default")
      (node (ref "IC10") (pin "11") (pinfunction "11_11") (pintype "passive"))
      (node (ref "IC11") (pin "11") (pinfunction "11_11") (pintype "passive"))
      (node (ref "IC12") (pin "11") (pinfunction "11_11") (pintype "passive"))
      (node (ref "IC13") (pin "11") (pinfunction "11_11") (pintype "passive"))
    )
    (net (code "67") (name "Net-(IC10-Pad12)") (class "Default")
      (node (ref "IC10") (pin "12") (pinfunction "12_12") (pintype "passive"))
      (node (ref "IC11") (pin "12") (pinfunction "12_12") (pintype "passive"))
      (node (ref "IC12") (pin "12") (pinfunction "12_12") (pintype "passive"))
      (node (ref "IC13") (pin "12") (pinfunction "12_12") (pintype "passive"))
    )
    (net (code "68") (name "Net-(IC10-Pad13)") (class "Default")
      (node (ref "IC10") (pin "13") (pinfunction "13_13") (pintype "passive"))
      (node (ref "IC11") (pin "13") (pinfunction "13_13") (pintype "passive"))
      (node (ref "IC12") (pin "13") (pinfunction "13_13") (pintype "passive"))
      (node (ref "IC13") (pin "13") (pinfunction "13_13") (pintype "passive"))
    )
    (net (code "69") (name "Net-(IC10-Pad14)") (class "Default")
      (node (ref "IC10") (pin "14") (pinfunction "14_14") (pintype "passive"))
      (node (ref "IC11") (pin "14") (pinfunction "14_14") (pintype "passive"))
      (node (ref "IC12") (pin "14") (pinfunction "14_14") (pintype "passive"))
      (node (ref "IC13") (pin "14") (pinfunction "14_14") (pintype "passive"))
    )
    (net (code "70") (name "Net-(IC10-Pad15)") (class "Default")
      (node (ref "IC10") (pin "15") (pinfunction "15_15") (pintype "passive"))
      (node (ref "IC11") (pin "15") (pinfunction "15_15") (pintype "passive"))
      (node (ref "IC12") (pin "15") (pinfunction "15_15") (pintype "passive"))
      (node (ref "IC13") (pin "15") (pinfunction "15_15") (pintype "passive"))
    )
    (net (code "71") (name "Net-(IC10-Pad16)") (class "Default")
      (node (ref "IC10") (pin "16") (pinfunction "16_16") (pintype "passive"))
      (node (ref "IC11") (pin "16") (pinfunction "16_16") (pintype "passive"))
      (node (ref "IC12") (pin "16") (pinfunction "16_16") (pintype "passive"))
      (node (ref "IC13") (pin "16") (pinfunction "16_16") (pintype "passive"))
    )
    (net (code "72") (name "Net-(IC10-Pad17)") (class "Default")
      (node (ref "IC10") (pin "17") (pinfunction "17_17") (pintype "passive"))
      (node (ref "IC11") (pin "17") (pinfunction "17_17") (pintype "passive"))
      (node (ref "IC12") (pin "17") (pinfunction "17_17") (pintype "passive"))
      (node (ref "IC13") (pin "17") (pinfunction "17_17") (pintype "passive"))
    )
    (net (code "73") (name "Net-(IC10-Pad18)") (class "Default")
      (node (ref "IC10") (pin "18") (pinfunction "18_18") (pintype "passive"))
      (node (ref "IC11") (pin "18") (pinfunction "18_18") (pintype "passive"))
      (node (ref "IC12") (pin "18") (pinfunction "18_18") (pintype "passive"))
      (node (ref "IC13") (pin "18") (pinfunction "18_18") (pintype "passive"))
    )
    (net (code "74") (name "Net-(IC10-Pad19)") (class "Default")
      (node (ref "IC10") (pin "19") (pinfunction "19_19") (pintype "passive"))
      (node (ref "IC11") (pin "19") (pinfunction "19_19") (pintype "passive"))
      (node (ref "IC12") (pin "19") (pinfunction "19_19") (pintype "passive"))
      (node (ref "IC13") (pin "19") (pinfunction "19_19") (pintype "passive"))
    )
    (net (code "75") (name "Net-(IC10-Pad20)") (class "Default")
      (node (ref "IC10") (pin "20") (pinfunction "20_20") (pintype "passive"))
      (node (ref "IC11") (pin "20") (pinfunction "20_20") (pintype "passive"))
      (node (ref "IC12") (pin "20") (pinfunction "20_20") (pintype "passive"))
      (node (ref "IC13") (pin "20") (pinfunction "20_20") (pintype "passive"))
    )
    (net (code "76") (name "Net-(IC10-Pad21)") (class "Default")
      (node (ref "IC10") (pin "21") (pinfunction "21_21") (pintype "passive"))
      (node (ref "IC11") (pin "21") (pinfunction "21_21") (pintype "passive"))
      (node (ref "IC12") (pin "21") (pinfunction "21_21") (pintype "passive"))
      (node (ref "IC13") (pin "21") (pinfunction "21_21") (pintype "passive"))
    )
    (net (code "77") (name "Net-(IC10-Pad22)") (class "Default")
      (node (ref "IC10") (pin "22") (pinfunction "22_22") (pintype "passive"))
      (node (ref "IC11") (pin "22") (pinfunction "22_22") (pintype "passive"))
      (node (ref "IC12") (pin "22") (pinfunction "22_22") (pintype "passive"))
      (node (ref "IC13") (pin "22") (pinfunction "22_22") (pintype "passive"))
    )
    (net (code "78") (name "Net-(IC10-Pad23)") (class "Default")
      (node (ref "IC10") (pin "23") (pinfunction "23_23") (pintype "passive"))
      (node (ref "IC11") (pin "23") (pinfunction "23_23") (pintype "passive"))
      (node (ref "IC12") (pin "23") (pinfunction "23_23") (pintype "passive"))
      (node (ref "IC13") (pin "23") (pinfunction "23_23") (pintype "passive"))
    )
    (net (code "79") (name "Net-(IC10-Pad24)") (class "Default")
      (node (ref "IC10") (pin "24") (pinfunction "24_24") (pintype "passive"))
      (node (ref "IC11") (pin "24") (pinfunction "24_24") (pintype "passive"))
      (node (ref "IC12") (pin "24") (pinfunction "24_24") (pintype "passive"))
      (node (ref "IC13") (pin "24") (pinfunction "24_24") (pintype "passive"))
    )
    (net (code "80") (name "Net-(IC14-Pad1)") (class "Default")
      (node (ref "IC14") (pin "1") (pinfunction "1_1") (pintype "passive"))
      (node (ref "IC15") (pin "1") (pinfunction "1_1") (pintype "passive"))
      (node (ref "IC16") (pin "1") (pinfunction "1_1") (pintype "passive"))
      (node (ref "IC17") (pin "1") (pinfunction "1_1") (pintype "passive"))
    )
    (net (code "81") (name "Net-(IC14-Pad2)") (class "Default")
      (node (ref "IC14") (pin "2") (pinfunction "2_2") (pintype "passive"))
      (node (ref "IC15") (pin "2") (pinfunction "2_2") (pintype "passive"))
      (node (ref "IC16") (pin "2") (pinfunction "2_2") (pintype "passive"))
      (node (ref "IC17") (pin "2") (pinfunction "2_2") (pintype "passive"))
    )
    (net (code "82") (name "Net-(IC14-Pad3)") (class "Default")
      (node (ref "IC14") (pin "3") (pinfunction "3_3") (pintype "passive"))
      (node (ref "IC15") (pin "3") (pinfunction "3_3") (pintype "passive"))
      (node (ref "IC16") (pin "3") (pinfunction "3_3") (pintype "passive"))
      (node (ref "IC17") (pin "3") (pinfunction "3_3") (pintype "passive"))
    )
    (net (code "83") (name "Net-(IC14-Pad4)") (class "Default")
      (node (ref "IC14") (pin "4") (pinfunction "4_4") (pintype "passive"))
      (node (ref "IC15") (pin "4") (pinfunction "4_4") (pintype "passive"))
      (node (ref "IC16") (pin "4") (pinfunction "4_4") (pintype "passive"))
      (node (ref "IC17") (pin "4") (pinfunction "4_4") (pintype "passive"))
    )
    (net (code "84") (name "Net-(IC14-Pad5)") (class "Default")
      (node (ref "IC14") (pin "5") (pinfunction "5_5") (pintype "passive"))
      (node (ref "IC15") (pin "5") (pinfunction "5_5") (pintype "passive"))
      (node (ref "IC16") (pin "5") (pinfunction "5_5") (pintype "passive"))
      (node (ref "IC17") (pin "5") (pinfunction "5_5") (pintype "passive"))
    )
    (net (code "85") (name "Net-(IC14-Pad6)") (class "Default")
      (node (ref "IC14") (pin "6") (pinfunction "6_6") (pintype "passive"))
      (node (ref "IC15") (pin "6") (pinfunction "6_6") (pintype "passive"))
      (node (ref "IC16") (pin "6") (pinfunction "6_6") (pintype "passive"))
      (node (ref "IC17") (pin "6") (pinfunction "6_6") (pintype "passive"))
    )
    (net (code "86") (name "Net-(IC14-Pad7)") (class "Default")
      (node (ref "IC14") (pin "7") (pinfunction "7_7") (pintype "passive"))
      (node (ref "IC15") (pin "7") (pinfunction "7_7") (pintype "passive"))
      (node (ref "IC16") (pin "7") (pinfunction "7_7") (pintype "passive"))
      (node (ref "IC17") (pin "7") (pinfunction "7_7") (pintype "passive"))
    )
    (net (code "87") (name "Net-(IC14-Pad8)") (class "Default")
      (node (ref "IC14") (pin "8") (pinfunction "8_8") (pintype "passive"))
      (node (ref "IC15") (pin "8") (pinfunction "8_8") (pintype "passive"))
      (node (ref "IC16") (pin "8") (pinfunction "8_8") (pintype "passive"))
      (node (ref "IC17") (pin "8") (pinfunction "8_8") (pintype "passive"))
    )
    (net (code "88") (name "Net-(IC14-Pad9)") (class "Default")
      (node (ref "IC14") (pin "9") (pinfunction "9_9") (pintype "passive"))
      (node (ref "IC15") (pin "9") (pinfunction "9_9") (pintype "passive"))
      (node (ref "IC16") (pin "9") (pinfunction "9_9") (pintype "passive"))
      (node (ref "IC17") (pin "9") (pinfunction "9_9") (pintype "passive"))
    )
    (net (code "89") (name "Net-(IC14-Pad10)") (class "Default")
      (node (ref "IC14") (pin "10") (pinfunction "10_10") (pintype "passive"))
      (node (ref "IC15") (pin "10") (pinfunction "10_10") (pintype "passive"))
      (node (ref "IC16") (pin "10") (pinfunction "10_10") (pintype "passive"))
      (node (ref "IC17") (pin "10") (pinfunction "10_10") (pintype "passive"))
    )
    (net (code "90") (name "Net-(IC14-Pad11)") (class "Default")
      (node (ref "IC14") (pin "11") (pinfunction "11_11") (pintype "passive"))
      (node (ref "IC15") (pin "11") (pinfunction "11_11") (pintype "passive"))
      (node (ref "IC16") (pin "11") (pinfunction "11_11") (pintype "passive"))
      (node (ref "IC17") (pin "11") (pinfunction "11_11") (pintype "passive"))
    )
    (net (code "91") (name "Net-(IC14-Pad12)") (class "Default")
      (node (ref "IC14") (pin "12") (pinfunction "12_12") (pintype "passive"))
      (node (ref "IC15") (pin "12") (pinfunction "12_12") (pintype "passive"))
      (node (ref "IC16") (pin "12") (pinfunction "12_12") (pintype "passive"))
      (node (ref "IC17") (pin "12") (pinfunction "12_12") (pintype "passive"))
    )
    (net (code "92") (name "Net-(IC14-Pad13)") (class "Default")
      (node (ref "IC14") (pin "13") (pinfunction "13_13") (pintype "passive"))
      (node (ref "IC15") (pin "13") (pinfunction "13_13") (pintype "passive"))
      (node (ref "IC16") (pin "13") (pinfunction "13_13") (pintype "passive"))
      (node (ref "IC17") (pin "13") (pinfunction "13_13") (pintype "passive"))
    )
    (net (code "93") (name "Net-(IC14-Pad14)") (class "Default")
      (node (ref "IC14") (pin "14") (pinfunction "14_14") (pintype "passive"))
      (node (ref "IC15") (pin "14") (pinfunction "14_14") (pintype "passive"))
      (node (ref "IC16") (pin "14") (pinfunction "14_14") (pintype "passive"))
      (node (ref "IC17") (pin "14") (pinfunction "14_14") (pintype "passive"))
    )
    (net (code "94") (name "Net-(IC14-Pad15)") (class "Default")
      (node (ref "IC14") (pin "15") (pinfunction "15_15") (pintype "passive"))
      (node (ref "IC15") (pin "15") (pinfunction "15_15") (pintype "passive"))
      (node (ref "IC16") (pin "15") (pinfunction "15_15") (pintype "passive"))
      (node (ref "IC17") (pin "15") (pinfunction "15_15") (pintype "passive"))
    )
    (net (code "95") (name "Net-(IC14-Pad16)") (class "Default")
      (node (ref "IC14") (pin "16") (pinfunction "16_16") (pintype "passive"))
      (node (ref "IC15") (pin "16") (pinfunction "16_16") (pintype "passive"))
      (node (ref "IC16") (pin "16") (pinfunction "16_16") (pintype "passive"))
      (node (ref "IC17") (pin "16") (pinfunction "16_16") (pintype "passive"))
    )
    (net (code "96") (name "Net-(IC14-Pad17)") (class "Default")
      (node (ref "IC14") (pin "17") (pinfunction "17_17") (pintype "passive"))
      (node (ref "IC15") (pin "17") (pinfunction "17_17") (pintype "passive"))
      (node (ref "IC16") (pin "17") (pinfunction "17_17") (pintype "passive"))
      (node (ref "IC17") (pin "17") (pinfunction "17_17") (pintype "passive"))
    )
    (net (code "97") (name "Net-(IC14-Pad18)") (class "Default")
      (node (ref "IC14") (pin "18") (pinfunction "18_18") (pintype "passive"))
      (node (ref "IC15") (pin "18") (pinfunction "18_18") (pintype "passive"))
      (node (ref "IC16") (pin "18") (pinfunction "18_18") (pintype "passive"))
      (node (ref "IC17") (pin "18") (pinfunction "18_18") (pintype "passive"))
    )
    (net (code "98") (name "Net-(IC14-Pad19)") (class "Default")
      (node (ref "IC14") (pin "19") (pinfunction "19_19") (pintype "passive"))
      (node (ref "IC15") (pin "19") (pinfunction "19_19") (pintype "passive"))
      (node (ref "IC16") (pin "19") (pinfunction "19_19") (pintype "passive"))
      (node (ref "IC17") (pin "19") (pinfunction "19_19") (pintype "passive"))
    )
    (net (code "99") (name "Net-(IC14-Pad20)") (class "Default")
      (node (ref "IC14") (pin "20") (pinfunction "20_20") (pintype "passive"))
      (node (ref "IC15") (pin "20") (pinfunction "20_20") (pintype "passive"))
      (node (ref "IC16") (pin "20") (pinfunction "20_20") (pintype "passive"))
      (node (ref "IC17") (pin "20") (pinfunction "20_20") (pintype "passive"))
    )
    (net (code "100") (name "Net-(IC14-Pad21)") (class "Default")
      (node (ref "IC14") (pin "21") (pinfunction "21_21") (pintype "passive"))
      (node (ref "IC15") (pin "21") (pinfunction "21_21") (pintype "passive"))
      (node (ref "IC16") (pin "21") (pinfunction "21_21") (pintype "passive"))
      (node (ref "IC17") (pin "21") (pinfunction "21_21") (pintype "passive"))
    )
    (net (code "101") (name "Net-(IC14-Pad22)") (class "Default")
      (node (ref "IC14") (pin "22") (pinfunction "22_22") (pintype "passive"))
      (node (ref "IC15") (pin "22") (pinfunction "22_22") (pintype "passive"))
      (node (ref "IC16") (pin "22") (pinfunction "22_22") (pintype "passive"))
      (node (ref "IC17") (pin "22") (pinfunction "22_22") (pintype "passive"))
    )
    (net (code "102") (name "Net-(IC14-Pad23)") (class "Default")
      (node (ref "IC14") (pin "23") (pinfunction "23_23") (pintype "passive"))
      (node (ref "IC15") (pin "23") (pinfunction "23_23") (pintype "passive"))
      (node (ref "IC16") (pin "23") (pinfunction "23_23") (pintype "passive"))
      (node (ref "IC17") (pin "23") (pinfunction "23_23") (pintype "passive"))
    )
    (net (code "103") (name "Net-(IC14-Pad24)") (class "Default")
      (node (ref "IC14") (pin "24") (pinfunction "24_24") (pintype "passive"))
      (node (ref "IC15") (pin "24") (pinfunction "24_24") (pintype "passive"))
      (node (ref "IC16") (pin "24") (pinfunction "24_24") (pintype "passive"))
      (node (ref "IC17") (pin "24") (pinfunction "24_24") (pintype "passive"))
    )
    (net (code "104") (name "Net-(IC18-Pad1)") (class "Default")
      (node (ref "IC18") (pin "1") (pinfunction "1_1") (pintype "passive"))
      (node (ref "IC19") (pin "1") (pinfunction "1_1") (pintype "passive"))
      (node (ref "IC20") (pin "1") (pinfunction "1_1") (pintype "passive"))
      (node (ref "IC21") (pin "1") (pinfunction "1_1") (pintype "passive"))
    )
    (net (code "105") (name "Net-(IC18-Pad2)") (class "Default")
      (node (ref "IC18") (pin "2") (pinfunction "2_2") (pintype "passive"))
      (node (ref "IC19") (pin "2") (pinfunction "2_2") (pintype "passive"))
      (node (ref "IC20") (pin "2") (pinfunction "2_2") (pintype "passive"))
      (node (ref "IC21") (pin "2") (pinfunction "2_2") (pintype "passive"))
    )
    (net (code "106") (name "Net-(IC18-Pad3)") (class "Default")
      (node (ref "IC18") (pin "3") (pinfunction "3_3") (pintype "passive"))
      (node (ref "IC19") (pin "3") (pinfunction "3_3") (pintype "passive"))
      (node (ref "IC20") (pin "3") (pinfunction "3_3") (pintype "passive"))
      (node (ref "IC21") (pin "3") (pinfunction "3_3") (pintype "passive"))
    )
    (net (code "107") (name "Net-(IC18-Pad4)") (class "Default")
      (node (ref "IC18") (pin "4") (pinfunction "4_4") (pintype "passive"))
      (node (ref "IC19") (pin "4") (pinfunction "4_4") (pintype "passive"))
      (node (ref "IC20") (pin "4") (pinfunction "4_4") (pintype "passive"))
      (node (ref "IC21") (pin "4") (pinfunction "4_4") (pintype "passive"))
    )
    (net (code "108") (name "Net-(IC18-Pad5)") (class "Default")
      (node (ref "IC18") (pin "5") (pinfunction "5_5") (pintype "passive"))
      (node (ref "IC19") (pin "5") (pinfunction "5_5") (pintype "passive"))
      (node (ref "IC20") (pin "5") (pinfunction "5_5") (pintype "passive"))
      (node (ref "IC21") (pin "5") (pinfunction "5_5") (pintype "passive"))
    )
    (net (code "109") (name "Net-(IC18-Pad6)") (class "Default")
      (node (ref "IC18") (pin "6") (pinfunction "6_6") (pintype "passive"))
      (node (ref "IC19") (pin "6") (pinfunction "6_6") (pintype "passive"))
      (node (ref "IC20") (pin "6") (pinfunction "6_6") (pintype "passive"))
      (node (ref "IC21") (pin "6") (pinfunction "6_6") (pintype "passive"))
    )
    (net (code "110") (name "Net-(IC18-Pad7)") (class "Default")
      (node (ref "IC18") (pin "7") (pinfunction "7_7") (pintype "passive"))
      (node (ref "IC19") (pin "7") (pinfunction "7_7") (pintype "passive"))
      (node (ref "IC20") (pin "7") (pinfunction "7_7") (pintype "passive"))
      (node (ref "IC21") (pin "7") (pinfunction "7_7") (pintype "passive"))
    )
    (net (code "111") (name "Net-(IC18-Pad8)") (class "Default")
      (node (ref "IC18") (pin "8") (pinfunction "8_8") (pintype "passive"))
      (node (ref "IC19") (pin "8") (pinfunction "8_8") (pintype "passive"))
      (node (ref "IC20") (pin "8") (pinfunction "8_8") (pintype "passive"))
      (node (ref "IC21") (pin "8") (pinfunction "8_8") (pintype "passive"))
    )
    (net (code "112") (name "Net-(IC18-Pad9)") (class "Default")
      (node (ref "IC18") (pin "9") (pinfunction "9_9") (pintype "passive"))
      (node (ref "IC19") (pin "9") (pinfunction "9_9") (pintype "passive"))
      (node (ref "IC20") (pin "9") (pinfunction "9_9") (pintype "passive"))
      (node (ref "IC21") (pin "9") (pinfunction "9_9") (pintype "passive"))
    )
    (net (code "113") (name "Net-(IC18-Pad10)") (class "Default")
      (node (ref "IC18") (pin "10") (pinfunction "10_10") (pintype "passive"))
      (node (ref "IC19") (pin "10") (pinfunction "10_10") (pintype "passive"))
      (node (ref "IC20") (pin "10") (pinfunction "10_10") (pintype "passive"))
      (node (ref "IC21") (pin "10") (pinfunction "10_10") (pintype "passive"))
    )
    (net (code "114") (name "Net-(IC18-Pad11)") (class "Default")
      (node (ref "IC18") (pin "11") (pinfunction "11_11") (pintype "passive"))
      (node (ref "IC19") (pin "11") (pinfunction "11_11") (pintype "passive"))
      (node (ref "IC20") (pin "11") (pinfunction "11_11") (pintype "passive"))
      (node (ref "IC21") (pin "11") (pinfunction "11_11") (pintype "passive"))
    )
    (net (code "115") (name "Net-(IC18-Pad12)") (class "Default")
      (node (ref "IC18") (pin "12") (pinfunction "12_12") (pintype "passive"))
      (node (ref "IC19") (pin "12") (pinfunction "12_12") (pintype "passive"))
      (node (ref "IC20") (pin "12") (pinfunction "12_12") (pintype "passive"))
      (node (ref "IC21") (pin "12") (pinfunction "12_12") (pintype "passive"))
    )
    (net (code "116") (name "Net-(IC18-Pad13)") (class "Default")
      (node (ref "IC18") (pin "13") (pinfunction "13_13") (pintype "passive"))
      (node (ref "IC19") (pin "13") (pinfunction "13_13") (pintype "passive"))
      (node (ref "IC20") (pin "13") (pinfunction "13_13") (pintype "passive"))
      (node (ref "IC21") (pin "13") (pinfunction "13_13") (pintype "passive"))
    )
    (net (code "117") (name "Net-(IC18-Pad14)") (class "Default")
      (node (ref "IC18") (pin "14") (pinfunction "14_14") (pintype "passive"))
      (node (ref "IC19") (pin "14") (pinfunction "14_14") (pintype "passive"))
      (node (ref "IC20") (pin "14") (pinfunction "14_14") (pintype "passive"))
      (node (ref "IC21") (pin "14") (pinfunction "14_14") (pintype "passive"))
    )
    (net (code "118") (name "Net-(IC18-Pad15)") (class "Default")
      (node (ref "IC18") (pin "15") (pinfunction "15_15") (pintype "passive"))
      (node (ref "IC19") (pin "15") (pinfunction "15_15") (pintype "passive"))
      (node (ref "IC20") (pin "15") (pinfunction "15_15") (pintype "passive"))
      (node (ref "IC21") (pin "15") (pinfunction "15_15") (pintype "passive"))
    )
    (net (code "119") (name "Net-(IC18-Pad16)") (class "Default")
      (node (ref "IC18") (pin "16") (pinfunction "16_16") (pintype "passive"))
      (node (ref "IC19") (pin "16") (pinfunction "16_16") (pintype "passive"))
      (node (ref "IC20") (pin "16") (pinfunction "16_16") (pintype "passive"))
      (node (ref "IC21") (pin "16") (pinfunction "16_16") (pintype "passive"))
    )
    (net (code "120") (name "Net-(IC18-Pad17)") (class "Default")
      (node (ref "IC18") (pin "17") (pinfunction "17_17") (pintype "passive"))
      (node (ref "IC19") (pin "17") (pinfunction "17_17") (pintype "passive"))
      (node (ref "IC20") (pin "17") (pinfunction "17_17") (pintype "passive"))
      (node (ref "IC21") (pin "17") (pinfunction "17_17") (pintype "passive"))
    )
    (net (code "121") (name "Net-(IC18-Pad18)") (class "Default")
      (node (ref "IC18") (pin "18") (pinfunction "18_18") (pintype "passive"))
      (node (ref "IC19") (pin "18") (pinfunction "18_18") (pintype "passive"))
      (node (ref "IC20") (pin "18") (pinfunction "18_18") (pintype "passive"))
      (node (ref "IC21") (pin "18") (pinfunction "18_18") (pintype "passive"))
    )
    (net (code "122") (name "Net-(IC18-Pad19)") (class "Default")
      (node (ref "IC18") (pin "19") (pinfunction "19_19") (pintype "passive"))
      (node (ref "IC19") (pin "19") (pinfunction "19_19") (pintype "passive"))
      (node (ref "IC20") (pin "19") (pinfunction "19_19") (pintype "passive"))
      (node (ref "IC21") (pin "19") (pinfunction "19_19") (pintype "passive"))
    )
    (net (code "123") (name "Net-(IC18-Pad20)") (class "Default")
      (node (ref "IC18") (pin "20") (pinfunction "20_20") (pintype "passive"))
      (node (ref "IC19") (pin "20") (pinfunction "20_20") (pintype "passive"))
      (node (ref "IC20") (pin "20") (pinfunction "20_20") (pintype "passive"))
      (node (ref "IC21") (pin "20") (pinfunction "20_20") (pintype "passive"))
    )
    (net (code "124") (name "Net-(IC18-Pad21)") (class "Default")
      (node (ref "IC18") (pin "21") (pinfunction "21_21") (pintype "passive"))
      (node (ref "IC19") (pin "21") (pinfunction "21_21") (pintype "passive"))
      (node (ref "IC20") (pin "21") (pinfunction "21_21") (pintype "passive"))
      (node (ref "IC21") (pin "21") (pinfunction "21_21") (pintype "passive"))
    )
    (net (code "125") (name "Net-(IC18-Pad22)") (class "Default")
      (node (ref "IC18") (pin "22") (pinfunction "22_22") (pintype "passive"))
      (node (ref "IC19") (pin "22") (pinfunction "22_22") (pintype "passive"))
      (node (ref "IC20") (pin "22") (pinfunction "22_22") (pintype "passive"))
      (node (ref "IC21") (pin "22") (pinfunction "22_22") (pintype "passive"))
    )
    (net (code "126") (name "Net-(IC18-Pad23)") (class "Default")
      (node (ref "IC18") (pin "23") (pinfunction "23_23") (pintype "passive"))
      (node (ref "IC19") (pin "23") (pinfunction "23_23") (pintype "passive"))
      (node (ref "IC20") (pin "23") (pinfunction "23_23") (pintype "passive"))
      (node (ref "IC21") (pin "23") (pinfunction "23_23") (pintype "passive"))
    )
    (net (code "127") (name "Net-(IC18-Pad24)") (class "Default")
      (node (ref "IC18") (pin "24") (pinfunction "24_24") (pintype "passive"))
      (node (ref "IC19") (pin "24") (pinfunction "24_24") (pintype "passive"))
      (node (ref "IC20") (pin "24") (pinfunction "24_24") (pintype "passive"))
      (node (ref "IC21") (pin "24") (pinfunction "24_24") (pintype "passive"))
    )
    (net (code "128") (name "Net-(IC22-Pad1)") (class "Default")
      (node (ref "IC22") (pin "1") (pinfunction "1_1") (pintype "passive"))
      (node (ref "IC23") (pin "1") (pinfunction "1_1") (pintype "passive"))
      (node (ref "IC24") (pin "1") (pinfunction "1_1") (pintype "passive"))
      (node (ref "IC25") (pin "1") (pinfunction "1_1") (pintype "passive"))
    )
    (net (code "129") (name "Net-(IC22-Pad2)") (class "Default")
      (node (ref "IC22") (pin "2") (pinfunction "2_2") (pintype "passive"))
      (node (ref "IC23") (pin "2") (pinfunction "2_2") (pintype "passive"))
      (node (ref "IC24") (pin "2") (pinfunction "2_2") (pintype "passive"))
      (node (ref "IC25") (pin "2") (pinfunction "2_2") (pintype "passive"))
    )
    (net (code "130") (name "Net-(IC22-Pad3)") (class "Default")
      (node (ref "IC22") (pin "3") (pinfunction "3_3") (pintype "passive"))
      (node (ref "IC23") (pin "3") (pinfunction "3_3") (pintype "passive"))
      (node (ref "IC24") (pin "3") (pinfunction "3_3") (pintype "passive"))
      (node (ref "IC25") (pin "3") (pinfunction "3_3") (pintype "passive"))
    )
    (net (code "131") (name "Net-(IC22-Pad4)") (class "Default")
      (node (ref "IC22") (pin "4") (pinfunction "4_4") (pintype "passive"))
      (node (ref "IC23") (pin "4") (pinfunction "4_4") (pintype "passive"))
      (node (ref "IC24") (pin "4") (pinfunction "4_4") (pintype "passive"))
      (node (ref "IC25") (pin "4") (pinfunction "4_4") (pintype "passive"))
    )
    (net (code "132") (name "Net-(IC22-Pad5)") (class "Default")
      (node (ref "IC22") (pin "5") (pinfunction "5_5") (pintype "passive"))
      (node (ref "IC23") (pin "5") (pinfunction "5_5") (pintype "passive"))
      (node (ref "IC24") (pin "5") (pinfunction "5_5") (pintype "passive"))
      (node (ref "IC25") (pin "5") (pinfunction "5_5") (pintype "passive"))
    )
    (net (code "133") (name "Net-(IC22-Pad6)") (class "Default")
      (node (ref "IC22") (pin "6") (pinfunction "6_6") (pintype "passive"))
      (node (ref "IC23") (pin "6") (pinfunction "6_6") (pintype "passive"))
      (node (ref "IC24") (pin "6") (pinfunction "6_6") (pintype "passive"))
      (node (ref "IC25") (pin "6") (pinfunction "6_6") (pintype "passive"))
    )
    (net (code "134") (name "Net-(IC22-Pad7)") (class "Default")
      (node (ref "IC22") (pin "7") (pinfunction "7_7") (pintype "passive"))
      (node (ref "IC23") (pin "7") (pinfunction "7_7") (pintype "passive"))
      (node (ref "IC24") (pin "7") (pinfunction "7_7") (pintype "passive"))
      (node (ref "IC25") (pin "7") (pinfunction "7_7") (pintype "passive"))
    )
    (net (code "135") (name "Net-(IC22-Pad8)") (class "Default")
      (node (ref "IC22") (pin "8") (pinfunction "8_8") (pintype "passive"))
      (node (ref "IC23") (pin "8") (pinfunction "8_8") (pintype "passive"))
      (node (ref "IC24") (pin "8") (pinfunction "8_8") (pintype "passive"))
      (node (ref "IC25") (pin "8") (pinfunction "8_8") (pintype "passive"))
    )
    (net (code "136") (name "Net-(IC22-Pad9)") (class "Default")
      (node (ref "IC22") (pin "9") (pinfunction "9_9") (pintype "passive"))
      (node (ref "IC23") (pin "9") (pinfunction "9_9") (pintype "passive"))
      (node (ref "IC24") (pin "9") (pinfunction "9_9") (pintype "passive"))
      (node (ref "IC25") (pin "9") (pinfunction "9_9") (pintype "passive"))
    )
    (net (code "137") (name "Net-(IC22-Pad10)") (class "Default")
      (node (ref "IC22") (pin "10") (pinfunction "10_10") (pintype "passive"))
      (node (ref "IC23") (pin "10") (pinfunction "10_10") (pintype "passive"))
      (node (ref "IC24") (pin "10") (pinfunction "10_10") (pintype "passive"))
      (node (ref "IC25") (pin "10") (pinfunction "10_10") (pintype "passive"))
    )
    (net (code "138") (name "Net-(IC22-Pad11)") (class "Default")
      (node (ref "IC22") (pin "11") (pinfunction "11_11") (pintype "passive"))
      (node (ref "IC23") (pin "11") (pinfunction "11_11") (pintype "passive"))
      (node (ref "IC24") (pin "11") (pinfunction "11_11") (pintype "passive"))
      (node (ref "IC25") (pin "11") (pinfunction "11_11") (pintype "passive"))
    )
    (net (code "139") (name "Net-(IC22-Pad12)") (class "Default")
      (node (ref "IC22") (pin "12") (pinfunction "12_12") (pintype "passive"))
      (node (ref "IC23") (pin "12") (pinfunction "12_12") (pintype "passive"))
      (node (ref "IC24") (pin "12") (pinfunction "12_12") (pintype "passive"))
      (node (ref "IC25") (pin "12") (pinfunction "12_12") (pintype "passive"))
    )
    (net (code "140") (name "Net-(IC22-Pad13)") (class "Default")
      (node (ref "IC22") (pin "13") (pinfunction "13_13") (pintype "passive"))
      (node (ref "IC23") (pin "13") (pinfunction "13_13") (pintype "passive"))
      (node (ref "IC24") (pin "13") (pinfunction "13_13") (pintype "passive"))
      (node (ref "IC25") (pin "13") (pinfunction "13_13") (pintype "passive"))
    )
    (net (code "141") (name "Net-(IC22-Pad14)") (class "Default")
      (node (ref "IC22") (pin "14") (pinfunction "14_14") (pintype "passive"))
      (node (ref "IC23") (pin "14") (pinfunction "14_14") (pintype "passive"))
      (node (ref "IC24") (pin "14") (pinfunction "14_14") (pintype "passive"))
      (node (ref "IC25") (pin "14") (pinfunction "14_14") (pintype "passive"))
    )
    (net (code "142") (name "Net-(IC22-Pad15)") (class "Default")
      (node (ref "IC22") (pin "15") (pinfunction "15_15") (pintype "passive"))
      (node (ref "IC23") (pin "15") (pinfunction "15_15") (pintype "passive"))
      (node (ref "IC24") (pin "15") (pinfunction "15_15") (pintype "passive"))
      (node (ref "IC25") (pin "15") (pinfunction "15_15") (pintype "passive"))
    )
    (net (code "143") (name "Net-(IC22-Pad16)") (class "Default")
      (node (ref "IC22") (pin "16") (pinfunction "16_16") (pintype "passive"))
      (node (ref "IC23") (pin "16") (pinfunction "16_16") (pintype "passive"))
      (node (ref "IC24") (pin "16") (pinfunction "16_16") (pintype "passive"))
      (node (ref "IC25") (pin "16") (pinfunction "16_16") (pintype "passive"))
    )
    (net (code "144") (name "Net-(IC22-Pad17)") (class "Default")
      (node (ref "IC22") (pin "17") (pinfunction "17_17") (pintype "passive"))
      (node (ref "IC23") (pin "17") (pinfunction "17_17") (pintype "passive"))
      (node (ref "IC24") (pin "17") (pinfunction "17_17") (pintype "passive"))
      (node (ref "IC25") (pin "17") (pinfunction "17_17") (pintype "passive"))
    )
    (net (code "145") (name "Net-(IC22-Pad18)") (class "Default")
      (node (ref "IC22") (pin "18") (pinfunction "18_18") (pintype "passive"))
      (node (ref "IC23") (pin "18") (pinfunction "18_18") (pintype "passive"))
      (node (ref "IC24") (pin "18") (pinfunction "18_18") (pintype "passive"))
      (node (ref "IC25") (pin "18") (pinfunction "18_18") (pintype "passive"))
    )
    (net (code "146") (name "Net-(IC22-Pad19)") (class "Default")
      (node (ref "IC22") (pin "19") (pinfunction "19_19") (pintype "passive"))
      (node (ref "IC23") (pin "19") (pinfunction "19_19") (pintype "passive"))
      (node (ref "IC24") (pin "19") (pinfunction "19_19") (pintype "passive"))
      (node (ref "IC25") (pin "19") (pinfunction "19_19") (pintype "passive"))
    )
    (net (code "147") (name "Net-(IC22-Pad20)") (class "Default")
      (node (ref "IC22") (pin "20") (pinfunction "20_20") (pintype "passive"))
      (node (ref "IC23") (pin "20") (pinfunction "20_20") (pintype "passive"))
      (node (ref "IC24") (pin "20") (pinfunction "20_20") (pintype "passive"))
      (node (ref "IC25") (pin "20") (pinfunction "20_20") (pintype "passive"))
    )
    (net (code "148") (name "Net-(IC22-Pad21)") (class "Default")
      (node (ref "IC22") (pin "21") (pinfunction "21_21") (pintype "passive"))
      (node (ref "IC23") (pin "21") (pinfunction "21_21") (pintype "passive"))
      (node (ref "IC24") (pin "21") (pinfunction "21_21") (pintype "passive"))
      (node (ref "IC25") (pin "21") (pinfunction "21_21") (pintype "passive"))
    )
    (net (code "149") (name "Net-(IC22-Pad22)") (class "Default")
      (node (ref "IC22") (pin "22") (pinfunction "22_22") (pintype "passive"))
      (node (ref "IC23") (pin "22") (pinfunction "22_22") (pintype "passive"))
      (node (ref "IC24") (pin "22") (pinfunction "22_22") (pintype "passive"))
      (node (ref "IC25") (pin "22") (pinfunction "22_22") (pintype "passive"))
    )
    (net (code "150") (name "Net-(IC22-Pad23)") (class "Default")
      (node (ref "IC22") (pin "23") (pinfunction "23_23") (pintype "passive"))
      (node (ref "IC23") (pin "23") (pinfunction "23_23") (pintype "passive"))
      (node (ref "IC24") (pin "23") (pinfunction "23_23") (pintype "passive"))
      (node (ref "IC25") (pin "23") (pinfunction "23_23") (pintype "passive"))
    )
    (net (code "151") (name "Net-(IC22-Pad24)") (class "Default")
      (node (ref "IC22") (pin "24") (pinfunction "24_24") (pintype "passive"))
      (node (ref "IC23") (pin "24") (pinfunction "24_24") (pintype "passive"))
      (node (ref "IC24") (pin "24") (pinfunction "24_24") (pintype "passive"))
      (node (ref "IC25") (pin "24") (pinfunction "24_24") (pintype "passive"))
    )
    (net (code "152") (name "Net-(IC26-Pad1)") (class "Default")
      (node (ref "IC26") (pin "1") (pinfunction "1_1") (pintype "passive"))
      (node (ref "IC27") (pin "1") (pinfunction "1_1") (pintype "passive"))
      (node (ref "IC28") (pin "1") (pinfunction "1_1") (pintype "passive"))
      (node (ref "IC29") (pin "1") (pinfunction "1_1") (pintype "passive"))
    )
    (net (code "153") (name "Net-(IC26-Pad2)") (class "Default")
      (node (ref "IC26") (pin "2") (pinfunction "2_2") (pintype "passive"))
      (node (ref "IC27") (pin "2") (pinfunction "2_2") (pintype "passive"))
      (node (ref "IC28") (pin "2") (pinfunction "2_2") (pintype "passive"))
      (node (ref "IC29") (pin "2") (pinfunction "2_2") (pintype "passive"))
    )
    (net (code "154") (name "Net-(IC26-Pad3)") (class "Default")
      (node (ref "IC26") (pin "3") (pinfunction "3_3") (pintype "passive"))
      (node (ref "IC27") (pin "3") (pinfunction "3_3") (pintype "passive"))
      (node (ref "IC28") (pin "3") (pinfunction "3_3") (pintype "passive"))
      (node (ref "IC29") (pin "3") (pinfunction "3_3") (pintype "passive"))
    )
    (net (code "155") (name "Net-(IC26-Pad4)") (class "Default")
      (node (ref "IC26") (pin "4") (pinfunction "4_4") (pintype "passive"))
      (node (ref "IC27") (pin "4") (pinfunction "4_4") (pintype "passive"))
      (node (ref "IC28") (pin "4") (pinfunction "4_4") (pintype "passive"))
      (node (ref "IC29") (pin "4") (pinfunction "4_4") (pintype "passive"))
    )
    (net (code "156") (name "Net-(IC26-Pad5)") (class "Default")
      (node (ref "IC26") (pin "5") (pinfunction "5_5") (pintype "passive"))
      (node (ref "IC27") (pin "5") (pinfunction "5_5") (pintype "passive"))
      (node (ref "IC28") (pin "5") (pinfunction "5_5") (pintype "passive"))
      (node (ref "IC29") (pin "5") (pinfunction "5_5") (pintype "passive"))
    )
    (net (code "157") (name "Net-(IC26-Pad6)") (class "Default")
      (node (ref "IC26") (pin "6") (pinfunction "6_6") (pintype "passive"))
      (node (ref "IC27") (pin "6") (pinfunction "6_6") (pintype "passive"))
      (node (ref "IC28") (pin "6") (pinfunction "6_6") (pintype "passive"))
      (node (ref "IC29") (pin "6") (pinfunction "6_6") (pintype "passive"))
    )
    (net (code "158") (name "Net-(IC26-Pad7)") (class "Default")
      (node (ref "IC26") (pin "7") (pinfunction "7_7") (pintype "passive"))
      (node (ref "IC27") (pin "7") (pinfunction "7_7") (pintype "passive"))
      (node (ref "IC28") (pin "7") (pinfunction "7_7") (pintype "passive"))
      (node (ref "IC29") (pin "7") (pinfunction "7_7") (pintype "passive"))
    )
    (net (code "159") (name "Net-(IC26-Pad8)") (class "Default")
      (node (ref "IC26") (pin "8") (pinfunction "8_8") (pintype "passive"))
      (node (ref "IC27") (pin "8") (pinfunction "8_8") (pintype "passive"))
      (node (ref "IC28") (pin "8") (pinfunction "8_8") (pintype "passive"))
      (node (ref "IC29") (pin "8") (pinfunction "8_8") (pintype "passive"))
    )
    (net (code "160") (name "Net-(IC26-Pad9)") (class "Default")
      (node (ref "IC26") (pin "9") (pinfunction "9_9") (pintype "passive"))
      (node (ref "IC27") (pin "9") (pinfunction "9_9") (pintype "passive"))
      (node (ref "IC28") (pin "9") (pinfunction "9_9") (pintype "passive"))
      (node (ref "IC29") (pin "9") (pinfunction "9_9") (pintype "passive"))
    )
    (net (code "161") (name "Net-(IC26-Pad10)") (class "Default")
      (node (ref "IC26") (pin "10") (pinfunction "10_10") (pintype "passive"))
      (node (ref "IC27") (pin "10") (pinfunction "10_10") (pintype "passive"))
      (node (ref "IC28") (pin "10") (pinfunction "10_10") (pintype "passive"))
      (node (ref "IC29") (pin "10") (pinfunction "10_10") (pintype "passive"))
    )
    (net (code "162") (name "Net-(IC26-Pad11)") (class "Default")
      (node (ref "IC26") (pin "11") (pinfunction "11_11") (pintype "passive"))
      (node (ref "IC27") (pin "11") (pinfunction "11_11") (pintype "passive"))
      (node (ref "IC28") (pin "11") (pinfunction "11_11") (pintype "passive"))
      (node (ref "IC29") (pin "11") (pinfunction "11_11") (pintype "passive"))
    )
    (net (code "163") (name "Net-(IC26-Pad12)") (class "Default")
      (node (ref "IC26") (pin "12") (pinfunction "12_12") (pintype "passive"))
      (node (ref "IC27") (pin "12") (pinfunction "12_12") (pintype "passive"))
      (node (ref "IC28") (pin "12") (pinfunction "12_12") (pintype "passive"))
      (node (ref "IC29") (pin "12") (pinfunction "12_12") (pintype "passive"))
    )
    (net (code "164") (name "Net-(IC26-Pad13)") (class "Default")
      (node (ref "IC26") (pin "13") (pinfunction "13_13") (pintype "passive"))
      (node (ref "IC27") (pin "13") (pinfunction "13_13") (pintype "passive"))
      (node (ref "IC28") (pin "13") (pinfunction "13_13") (pintype "passive"))
      (node (ref "IC29") (pin "13") (pinfunction "13_13") (pintype "passive"))
    )
    (net (code "165") (name "Net-(IC26-Pad14)") (class "Default")
      (node (ref "IC26") (pin "14") (pinfunction "14_14") (pintype "passive"))
      (node (ref "IC27") (pin "14") (pinfunction "14_14") (pintype "passive"))
      (node (ref "IC28") (pin "14") (pinfunction "14_14") (pintype "passive"))
      (node (ref "IC29") (pin "14") (pinfunction "14_14") (pintype "passive"))
    )
    (net (code "166") (name "Net-(IC26-Pad15)") (class "Default")
      (node (ref "IC26") (pin "15") (pinfunction "15_15") (pintype "passive"))
      (node (ref "IC27") (pin "15") (pinfunction "15_15") (pintype "passive"))
      (node (ref "IC28") (pin "15") (pinfunction "15_15") (pintype "passive"))
      (node (ref "IC29") (pin "15") (pinfunction "15_15") (pintype "passive"))
    )
    (net (code "167") (name "Net-(IC26-Pad16)") (class "Default")
      (node (ref "IC26") (pin "16") (pinfunction "16_16") (pintype "passive"))
      (node (ref "IC27") (pin "16") (pinfunction "16_16") (pintype "passive"))
      (node (ref "IC28") (pin "16") (pinfunction "16_16") (pintype "passive"))
      (node (ref "IC29") (pin "16") (pinfunction "16_16") (pintype "passive"))
    )
    (net (code "168") (name "Net-(IC26-Pad17)") (class "Default")
      (node (ref "IC26") (pin "17") (pinfunction "17_17") (pintype "passive"))
      (node (ref "IC27") (pin "17") (pinfunction "17_17") (pintype "passive"))
      (node (ref "IC28") (pin "17") (pinfunction "17_17") (pintype "passive"))
      (node (ref "IC29") (pin "17") (pinfunction "17_17") (pintype "passive"))
    )
    (net (code "169") (name "Net-(IC26-Pad18)") (class "Default")
      (node (ref "IC26") (pin "18") (pinfunction "18_18") (pintype "passive"))
      (node (ref "IC27") (pin "18") (pinfunction "18_18") (pintype "passive"))
      (node (ref "IC28") (pin "18") (pinfunction "18_18") (pintype "passive"))
      (node (ref "IC29") (pin "18") (pinfunction "18_18") (pintype "passive"))
    )
    (net (code "170") (name "Net-(IC26-Pad19)") (class "Default")
      (node (ref "IC26") (pin "19") (pinfunction "19_19") (pintype "passive"))
      (node (ref "IC27") (pin "19") (pinfunction "19_19") (pintype "passive"))
      (node (ref "IC28") (pin "19") (pinfunction "19_19") (pintype "passive"))
      (node (ref "IC29") (pin "19") (pinfunction "19_19") (pintype "passive"))
    )
    (net (code "171") (name "Net-(IC26-Pad20)") (class "Default")
      (node (ref "IC26") (pin "20") (pinfunction "20_20") (pintype "passive"))
      (node (ref "IC27") (pin "20") (pinfunction "20_20") (pintype "passive"))
      (node (ref "IC28") (pin "20") (pinfunction "20_20") (pintype "passive"))
      (node (ref "IC29") (pin "20") (pinfunction "20_20") (pintype "passive"))
    )
    (net (code "172") (name "Net-(IC26-Pad21)") (class "Default")
      (node (ref "IC26") (pin "21") (pinfunction "21_21") (pintype "passive"))
      (node (ref "IC27") (pin "21") (pinfunction "21_21") (pintype "passive"))
      (node (ref "IC28") (pin "21") (pinfunction "21_21") (pintype "passive"))
      (node (ref "IC29") (pin "21") (pinfunction "21_21") (pintype "passive"))
    )
    (net (code "173") (name "Net-(IC26-Pad22)") (class "Default")
      (node (ref "IC26") (pin "22") (pinfunction "22_22") (pintype "passive"))
      (node (ref "IC27") (pin "22") (pinfunction "22_22") (pintype "passive"))
      (node (ref "IC28") (pin "22") (pinfunction "22_22") (pintype "passive"))
      (node (ref "IC29") (pin "22") (pinfunction "22_22") (pintype "passive"))
    )
    (net (code "174") (name "Net-(IC26-Pad23)") (class "Default")
      (node (ref "IC26") (pin "23") (pinfunction "23_23") (pintype "passive"))
      (node (ref "IC27") (pin "23") (pinfunction "23_23") (pintype "passive"))
      (node (ref "IC28") (pin "23") (pinfunction "23_23") (pintype "passive"))
      (node (ref "IC29") (pin "23") (pinfunction "23_23") (pintype "passive"))
    )
    (net (code "175") (name "Net-(IC26-Pad24)") (class "Default")
      (node (ref "IC26") (pin "24") (pinfunction "24_24") (pintype "passive"))
      (node (ref "IC27") (pin "24") (pinfunction "24_24") (pintype "passive"))
      (node (ref "IC28") (pin "24") (pinfunction "24_24") (pintype "passive"))
      (node (ref "IC29") (pin "24") (pinfunction "24_24") (pintype "passive"))
    )
    (net (code "176") (name "Net-(IC30-Pad1)") (class "Default")
      (node (ref "IC30") (pin "1") (pinfunction "1_1") (pintype "passive"))
      (node (ref "IC31") (pin "1") (pinfunction "1_1") (pintype "passive"))
      (node (ref "IC32") (pin "1") (pinfunction "1_1") (pintype "passive"))
      (node (ref "IC33") (pin "1") (pinfunction "1_1") (pintype "passive"))
    )
    (net (code "177") (name "Net-(IC30-Pad2)") (class "Default")
      (node (ref "IC30") (pin "2") (pinfunction "2_2") (pintype "passive"))
      (node (ref "IC31") (pin "2") (pinfunction "2_2") (pintype "passive"))
      (node (ref "IC32") (pin "2") (pinfunction "2_2") (pintype "passive"))
      (node (ref "IC33") (pin "2") (pinfunction "2_2") (pintype "passive"))
    )
    (net (code "178") (name "Net-(IC30-Pad3)") (class "Default")
      (node (ref "IC30") (pin "3") (pinfunction "3_3") (pintype "passive"))
      (node (ref "IC31") (pin "3") (pinfunction "3_3") (pintype "passive"))
      (node (ref "IC32") (pin "3") (pinfunction "3_3") (pintype "passive"))
      (node (ref "IC33") (pin "3") (pinfunction "3_3") (pintype "passive"))
    )
    (net (code "179") (name "Net-(IC30-Pad4)") (class "Default")
      (node (ref "IC30") (pin "4") (pinfunction "4_4") (pintype "passive"))
      (node (ref "IC31") (pin "4") (pinfunction "4_4") (pintype "passive"))
      (node (ref "IC32") (pin "4") (pinfunction "4_4") (pintype "passive"))
      (node (ref "IC33") (pin "4") (pinfunction "4_4") (pintype "passive"))
    )
    (net (code "180") (name "Net-(IC30-Pad5)") (class "Default")
      (node (ref "IC30") (pin "5") (pinfunction "5_5") (pintype "passive"))
      (node (ref "IC31") (pin "5") (pinfunction "5_5") (pintype "passive"))
      (node (ref "IC32") (pin "5") (pinfunction "5_5") (pintype "passive"))
      (node (ref "IC33") (pin "5") (pinfunction "5_5") (pintype "passive"))
    )
    (net (code "181") (name "Net-(IC30-Pad6)") (class "Default")
      (node (ref "IC30") (pin "6") (pinfunction "6_6") (pintype "passive"))
      (node (ref "IC31") (pin "6") (pinfunction "6_6") (pintype "passive"))
      (node (ref "IC32") (pin "6") (pinfunction "6_6") (pintype "passive"))
      (node (ref "IC33") (pin "6") (pinfunction "6_6") (pintype "passive"))
    )
    (net (code "182") (name "Net-(IC30-Pad7)") (class "Default")
      (node (ref "IC30") (pin "7") (pinfunction "7_7") (pintype "passive"))
      (node (ref "IC31") (pin "7") (pinfunction "7_7") (pintype "passive"))
      (node (ref "IC32") (pin "7") (pinfunction "7_7") (pintype "passive"))
      (node (ref "IC33") (pin "7") (pinfunction "7_7") (pintype "passive"))
    )
    (net (code "183") (name "Net-(IC30-Pad8)") (class "Default")
      (node (ref "IC30") (pin "8") (pinfunction "8_8") (pintype "passive"))
      (node (ref "IC31") (pin "8") (pinfunction "8_8") (pintype "passive"))
      (node (ref "IC32") (pin "8") (pinfunction "8_8") (pintype "passive"))
      (node (ref "IC33") (pin "8") (pinfunction "8_8") (pintype "passive"))
    )
    (net (code "184") (name "Net-(IC30-Pad9)") (class "Default")
      (node (ref "IC30") (pin "9") (pinfunction "9_9") (pintype "passive"))
      (node (ref "IC31") (pin "9") (pinfunction "9_9") (pintype "passive"))
      (node (ref "IC32") (pin "9") (pinfunction "9_9") (pintype "passive"))
      (node (ref "IC33") (pin "9") (pinfunction "9_9") (pintype "passive"))
    )
    (net (code "185") (name "Net-(IC30-Pad10)") (class "Default")
      (node (ref "IC30") (pin "10") (pinfunction "10_10") (pintype "passive"))
      (node (ref "IC31") (pin "10") (pinfunction "10_10") (pintype "passive"))
      (node (ref "IC32") (pin "10") (pinfunction "10_10") (pintype "passive"))
      (node (ref "IC33") (pin "10") (pinfunction "10_10") (pintype "passive"))
    )
    (net (code "186") (name "Net-(IC30-Pad11)") (class "Default")
      (node (ref "IC30") (pin "11") (pinfunction "11_11") (pintype "passive"))
      (node (ref "IC31") (pin "11") (pinfunction "11_11") (pintype "passive"))
      (node (ref "IC32") (pin "11") (pinfunction "11_11") (pintype "passive"))
      (node (ref "IC33") (pin "11") (pinfunction "11_11") (pintype "passive"))
    )
    (net (code "187") (name "Net-(IC30-Pad12)") (class "Default")
      (node (ref "IC30") (pin "12") (pinfunction "12_12") (pintype "passive"))
      (node (ref "IC31") (pin "12") (pinfunction "12_12") (pintype "passive"))
      (node (ref "IC32") (pin "12") (pinfunction "12_12") (pintype "passive"))
      (node (ref "IC33") (pin "12") (pinfunction "12_12") (pintype "passive"))
    )
    (net (code "188") (name "Net-(IC30-Pad13)") (class "Default")
      (node (ref "IC30") (pin "13") (pinfunction "13_13") (pintype "passive"))
      (node (ref "IC31") (pin "13") (pinfunction "13_13") (pintype "passive"))
      (node (ref "IC32") (pin "13") (pinfunction "13_13") (pintype "passive"))
      (node (ref "IC33") (pin "13") (pinfunction "13_13") (pintype "passive"))
    )
    (net (code "189") (name "Net-(IC30-Pad14)") (class "Default")
      (node (ref "IC30") (pin "14") (pinfunction "14_14") (pintype "passive"))
      (node (ref "IC31") (pin "14") (pinfunction "14_14") (pintype "passive"))
      (node (ref "IC32") (pin "14") (pinfunction "14_14") (pintype "passive"))
      (node (ref "IC33") (pin "14") (pinfunction "14_14") (pintype "passive"))
    )
    (net (code "190") (name "Net-(IC30-Pad15)") (class "Default")
      (node (ref "IC30") (pin "15") (pinfunction "15_15") (pintype "passive"))
      (node (ref "IC31") (pin "15") (pinfunction "15_15") (pintype "passive"))
      (node (ref "IC32") (pin "15") (pinfunction "15_15") (pintype "passive"))
      (node (ref "IC33") (pin "15") (pinfunction "15_15") (pintype "passive"))
    )
    (net (code "191") (name "Net-(IC30-Pad16)") (class "Default")
      (node (ref "IC30") (pin "16") (pinfunction "16_16") (pintype "passive"))
      (node (ref "IC31") (pin "16") (pinfunction "16_16") (pintype "passive"))
      (node (ref "IC32") (pin "16") (pinfunction "16_16") (pintype "passive"))
      (node (ref "IC33") (pin "16") (pinfunction "16_16") (pintype "passive"))
    )
    (net (code "192") (name "Net-(IC30-Pad17)") (class "Default")
      (node (ref "IC30") (pin "17") (pinfunction "17_17") (pintype "passive"))
      (node (ref "IC31") (pin "17") (pinfunction "17_17") (pintype "passive"))
      (node (ref "IC32") (pin "17") (pinfunction "17_17") (pintype "passive"))
      (node (ref "IC33") (pin "17") (pinfunction "17_17") (pintype "passive"))
    )
    (net (code "193") (name "Net-(IC30-Pad18)") (class "Default")
      (node (ref "IC30") (pin "18") (pinfunction "18_18") (pintype "passive"))
      (node (ref "IC31") (pin "18") (pinfunction "18_18") (pintype "passive"))
      (node (ref "IC32") (pin "18") (pinfunction "18_18") (pintype "passive"))
      (node (ref "IC33") (pin "18") (pinfunction "18_18") (pintype "passive"))
    )
    (net (code "194") (name "Net-(IC30-Pad19)") (class "Default")
      (node (ref "IC30") (pin "19") (pinfunction "19_19") (pintype "passive"))
      (node (ref "IC31") (pin "19") (pinfunction "19_19") (pintype "passive"))
      (node (ref "IC32") (pin "19") (pinfunction "19_19") (pintype "passive"))
      (node (ref "IC33") (pin "19") (pinfunction "19_19") (pintype "passive"))
    )
    (net (code "195") (name "Net-(IC30-Pad20)") (class "Default")
      (node (ref "IC30") (pin "20") (pinfunction "20_20") (pintype "passive"))
      (node (ref "IC31") (pin "20") (pinfunction "20_20") (pintype "passive"))
      (node (ref "IC32") (pin "20") (pinfunction "20_20") (pintype "passive"))
      (node (ref "IC33") (pin "20") (pinfunction "20_20") (pintype "passive"))
    )
    (net (code "196") (name "Net-(IC30-Pad21)") (class "Default")
      (node (ref "IC30") (pin "21") (pinfunction "21_21") (pintype "passive"))
      (node (ref "IC31") (pin "21") (pinfunction "21_21") (pintype "passive"))
      (node (ref "IC32") (pin "21") (pinfunction "21_21") (pintype "passive"))
      (node (ref "IC33") (pin "21") (pinfunction "21_21") (pintype "passive"))
    )
    (net (code "197") (name "Net-(IC30-Pad22)") (class "Default")
      (node (ref "IC30") (pin "22") (pinfunction "22_22") (pintype "passive"))
      (node (ref "IC31") (pin "22") (pinfunction "22_22") (pintype "passive"))
      (node (ref "IC32") (pin "22") (pinfunction "22_22") (pintype "passive"))
      (node (ref "IC33") (pin "22") (pinfunction "22_22") (pintype "passive"))
    )
    (net (code "198") (name "Net-(IC30-Pad23)") (class "Default")
      (node (ref "IC30") (pin "23") (pinfunction "23_23") (pintype "passive"))
      (node (ref "IC31") (pin "23") (pinfunction "23_23") (pintype "passive"))
      (node (ref "IC32") (pin "23") (pinfunction "23_23") (pintype "passive"))
      (node (ref "IC33") (pin "23") (pinfunction "23_23") (pintype "passive"))
    )
    (net (code "199") (name "Net-(IC30-Pad24)") (class "Default")
      (node (ref "IC30") (pin "24") (pinfunction "24_24") (pintype "passive"))
      (node (ref "IC31") (pin "24") (pinfunction "24_24") (pintype "passive"))
      (node (ref "IC32") (pin "24") (pinfunction "24_24") (pintype "passive"))
      (node (ref "IC33") (pin "24") (pinfunction "24_24") (pintype "passive"))
    )
    (net (code "200") (name "Net-(IC34-Pad1)") (class "Default")
      (node (ref "IC34") (pin "1") (pinfunction "1_1") (pintype "passive"))
      (node (ref "IC35") (pin "1") (pinfunction "1_1") (pintype "passive"))
      (node (ref "IC36") (pin "1") (pinfunction "1_1") (pintype "passive"))
      (node (ref "IC37") (pin "1") (pinfunction "1_1") (pintype "passive"))
    )
    (net (code "201") (name "Net-(IC34-Pad2)") (class "Default")
      (node (ref "IC34") (pin "2") (pinfunction "2_2") (pintype "passive"))
      (node (ref "IC35") (pin "2") (pinfunction "2_2") (pintype "passive"))
      (node (ref "IC36") (pin "2") (pinfunction "2_2") (pintype "passive"))
      (node (ref "IC37") (pin "2") (pinfunction "2_2") (pintype "passive"))
    )
    (net (code "202") (name "Net-(IC34-Pad3)") (class "Default")
      (node (ref "IC34") (pin "3") (pinfunction "3_3") (pintype "passive"))
      (node (ref "IC35") (pin "3") (pinfunction "3_3") (pintype "passive"))
      (node (ref "IC36") (pin "3") (pinfunction "3_3") (pintype "passive"))
      (node (ref "IC37") (pin "3") (pinfunction "3_3") (pintype "passive"))
    )
    (net (code "203") (name "Net-(IC34-Pad4)") (class "Default")
      (node (ref "IC34") (pin "4") (pinfunction "4_4") (pintype "passive"))
      (node (ref "IC35") (pin "4") (pinfunction "4_4") (pintype "passive"))
      (node (ref "IC36") (pin "4") (pinfunction "4_4") (pintype "passive"))
      (node (ref "IC37") (pin "4") (pinfunction "4_4") (pintype "passive"))
    )
    (net (code "204") (name "Net-(IC34-Pad5)") (class "Default")
      (node (ref "IC34") (pin "5") (pinfunction "5_5") (pintype "passive"))
      (node (ref "IC35") (pin "5") (pinfunction "5_5") (pintype "passive"))
      (node (ref "IC36") (pin "5") (pinfunction "5_5") (pintype "passive"))
      (node (ref "IC37") (pin "5") (pinfunction "5_5") (pintype "passive"))
    )
    (net (code "205") (name "Net-(IC34-Pad6)") (class "Default")
      (node (ref "IC34") (pin "6") (pinfunction "6_6") (pintype "passive"))
      (node (ref "IC35") (pin "6") (pinfunction "6_6") (pintype "passive"))
      (node (ref "IC36") (pin "6") (pinfunction "6_6") (pintype "passive"))
      (node (ref "IC37") (pin "6") (pinfunction "6_6") (pintype "passive"))
    )
    (net (code "206") (name "Net-(IC34-Pad7)") (class "Default")
      (node (ref "IC34") (pin "7") (pinfunction "7_7") (pintype "passive"))
      (node (ref "IC35") (pin "7") (pinfunction "7_7") (pintype "passive"))
      (node (ref "IC36") (pin "7") (pinfunction "7_7") (pintype "passive"))
      (node (ref "IC37") (pin "7") (pinfunction "7_7") (pintype "passive"))
    )
    (net (code "207") (name "Net-(IC34-Pad8)") (class "Default")
      (node (ref "IC34") (pin "8") (pinfunction "8_8") (pintype "passive"))
      (node (ref "IC35") (pin "8") (pinfunction "8_8") (pintype "passive"))
      (node (ref "IC36") (pin "8") (pinfunction "8_8") (pintype "passive"))
      (node (ref "IC37") (pin "8") (pinfunction "8_8") (pintype "passive"))
    )
    (net (code "208") (name "Net-(IC34-Pad9)") (class "Default")
      (node (ref "IC34") (pin "9") (pinfunction "9_9") (pintype "passive"))
      (node (ref "IC35") (pin "9") (pinfunction "9_9") (pintype "passive"))
      (node (ref "IC36") (pin "9") (pinfunction "9_9") (pintype "passive"))
      (node (ref "IC37") (pin "9") (pinfunction "9_9") (pintype "passive"))
    )
    (net (code "209") (name "Net-(IC34-Pad10)") (class "Default")
      (node (ref "IC34") (pin "10") (pinfunction "10_10") (pintype "passive"))
      (node (ref "IC35") (pin "10") (pinfunction "10_10") (pintype "passive"))
      (node (ref "IC36") (pin "10") (pinfunction "10_10") (pintype "passive"))
      (node (ref "IC37") (pin "10") (pinfunction "10_10") (pintype "passive"))
    )
    (net (code "210") (name "Net-(IC34-Pad11)") (class "Default")
      (node (ref "IC34") (pin "11") (pinfunction "11_11") (pintype "passive"))
      (node (ref "IC35") (pin "11") (pinfunction "11_11") (pintype "passive"))
      (node (ref "IC36") (pin "11") (pinfunction "11_11") (pintype "passive"))
      (node (ref "IC37") (pin "11") (pinfunction "11_11") (pintype "passive"))
    )
    (net (code "211") (name "Net-(IC34-Pad12)") (class "Default")
      (node (ref "IC34") (pin "12") (pinfunction "12_12") (pintype "passive"))
      (node (ref "IC35") (pin "12") (pinfunction "12_12") (pintype "passive"))
      (node (ref "IC36") (pin "12") (pinfunction "12_12") (pintype "passive"))
      (node (ref "IC37") (pin "12") (pinfunction "12_12") (pintype "passive"))
    )
    (net (code "212") (name "Net-(IC34-Pad13)") (class "Default")
      (node (ref "IC34") (pin "13") (pinfunction "13_13") (pintype "passive"))
      (node (ref "IC35") (pin "13") (pinfunction "13_13") (pintype "passive"))
      (node (ref "IC36") (pin "13") (pinfunction "13_13") (pintype "passive"))
      (node (ref "IC37") (pin "13") (pinfunction "13_13") (pintype "passive"))
    )
    (net (code "213") (name "Net-(IC34-Pad14)") (class "Default")
      (node (ref "IC34") (pin "14") (pinfunction "14_14") (pintype "passive"))
      (node (ref "IC35") (pin "14") (pinfunction "14_14") (pintype "passive"))
      (node (ref "IC36") (pin "14") (pinfunction "14_14") (pintype "passive"))
      (node (ref "IC37") (pin "14") (pinfunction "14_14") (pintype "passive"))
    )
    (net (code "214") (name "Net-(IC34-Pad15)") (class "Default")
      (node (ref "IC34") (pin "15") (pinfunction "15_15") (pintype "passive"))
      (node (ref "IC35") (pin "15") (pinfunction "15_15") (pintype "passive"))
      (node (ref "IC36") (pin "15") (pinfunction "15_15") (pintype "passive"))
      (node (ref "IC37") (pin "15") (pinfunction "15_15") (pintype "passive"))
    )
    (net (code "215") (name "Net-(IC34-Pad16)") (class "Default")
      (node (ref "IC34") (pin "16") (pinfunction "16_16") (pintype "passive"))
      (node (ref "IC35") (pin "16") (pinfunction "16_16") (pintype "passive"))
      (node (ref "IC36") (pin "16") (pinfunction "16_16") (pintype "passive"))
      (node (ref "IC37") (pin "16") (pinfunction "16_16") (pintype "passive"))
    )
    (net (code "216") (name "Net-(IC34-Pad17)") (class "Default")
      (node (ref "IC34") (pin "17") (pinfunction "17_17") (pintype "passive"))
      (node (ref "IC35") (pin "17") (pinfunction "17_17") (pintype "passive"))
      (node (ref "IC36") (pin "17") (pinfunction "17_17") (pintype "passive"))
      (node (ref "IC37") (pin "17") (pinfunction "17_17") (pintype "passive"))
    )
    (net (code "217") (name "Net-(IC34-Pad18)") (class "Default")
      (node (ref "IC34") (pin "18") (pinfunction "18_18") (pintype "passive"))
      (node (ref "IC35") (pin "18") (pinfunction "18_18") (pintype "passive"))
      (node (ref "IC36") (pin "18") (pinfunction "18_18") (pintype "passive"))
      (node (ref "IC37") (pin "18") (pinfunction "18_18") (pintype "passive"))
    )
    (net (code "218") (name "Net-(IC34-Pad19)") (class "Default")
      (node (ref "IC34") (pin "19") (pinfunction "19_19") (pintype "passive"))
      (node (ref "IC35") (pin "19") (pinfunction "19_19") (pintype "passive"))
      (node (ref "IC36") (pin "19") (pinfunction "19_19") (pintype "passive"))
      (node (ref "IC37") (pin "19") (pinfunction "19_19") (pintype "passive"))
    )
    (net (code "219") (name "Net-(IC34-Pad20)") (class "Default")
      (node (ref "IC34") (pin "20") (pinfunction "20_20") (pintype "passive"))
      (node (ref "IC35") (pin "20") (pinfunction "20_20") (pintype "passive"))
      (node (ref "IC36") (pin "20") (pinfunction "20_20") (pintype "passive"))
      (node (ref "IC37") (pin "20") (pinfunction "20_20") (pintype "passive"))
    )
    (net (code "220") (name "Net-(IC34-Pad21)") (class "Default")
      (node (ref "IC34") (pin "21") (pinfunction "21_21") (pintype "passive"))
      (node (ref "IC35") (pin "21") (pinfunction "21_21") (pintype "passive"))
      (node (ref "IC36") (pin "21") (pinfunction "21_21") (pintype "passive"))
      (node (ref "IC37") (pin "21") (pinfunction "21_21") (pintype "passive"))
    )
    (net (code "221") (name "Net-(IC34-Pad22)") (class "Default")
      (node (ref "IC34") (pin "22") (pinfunction "22_22") (pintype "passive"))
      (node (ref "IC35") (pin "22") (pinfunction "22_22") (pintype "passive"))
      (node (ref "IC36") (pin "22") (pinfunction "22_22") (pintype "passive"))
      (node (ref "IC37") (pin "22") (pinfunction "22_22") (pintype "passive"))
    )
    (net (code "222") (name "Net-(IC34-Pad23)") (class "Default")
      (node (ref "IC34") (pin "23") (pinfunction "23_23") (pintype "passive"))
      (node (ref "IC35") (pin "23") (pinfunction "23_23") (pintype "passive"))
      (node (ref "IC36") (pin "23") (pinfunction "23_23") (pintype "passive"))
      (node (ref "IC37") (pin "23") (pinfunction "23_23") (pintype "passive"))
    )
    (net (code "223") (name "Net-(IC34-Pad24)") (class "Default")
      (node (ref "IC34") (pin "24") (pinfunction "24_24") (pintype "passive"))
      (node (ref "IC35") (pin "24") (pinfunction "24_24") (pintype "passive"))
      (node (ref "IC36") (pin "24") (pinfunction "24_24") (pintype "passive"))
      (node (ref "IC37") (pin "24") (pinfunction "24_24") (pintype "passive"))
    )
    (net (code "224") (name "Net-(IC38-Pad1)") (class "Default")
      (node (ref "IC38") (pin "1") (pinfunction "1_1") (pintype "passive"))
      (node (ref "IC39") (pin "1") (pinfunction "1_1") (pintype "passive"))
      (node (ref "IC40") (pin "1") (pinfunction "1_1") (pintype "passive"))
      (node (ref "IC41") (pin "1") (pinfunction "1_1") (pintype "passive"))
    )
    (net (code "225") (name "Net-(IC38-Pad2)") (class "Default")
      (node (ref "IC38") (pin "2") (pinfunction "2_2") (pintype "passive"))
      (node (ref "IC39") (pin "2") (pinfunction "2_2") (pintype "passive"))
      (node (ref "IC40") (pin "2") (pinfunction "2_2") (pintype "passive"))
      (node (ref "IC41") (pin "2") (pinfunction "2_2") (pintype "passive"))
    )
    (net (code "226") (name "Net-(IC38-Pad3)") (class "Default")
      (node (ref "IC38") (pin "3") (pinfunction "3_3") (pintype "passive"))
      (node (ref "IC39") (pin "3") (pinfunction "3_3") (pintype "passive"))
      (node (ref "IC40") (pin "3") (pinfunction "3_3") (pintype "passive"))
      (node (ref "IC41") (pin "3") (pinfunction "3_3") (pintype "passive"))
    )
    (net (code "227") (name "Net-(IC38-Pad4)") (class "Default")
      (node (ref "IC38") (pin "4") (pinfunction "4_4") (pintype "passive"))
      (node (ref "IC39") (pin "4") (pinfunction "4_4") (pintype "passive"))
      (node (ref "IC40") (pin "4") (pinfunction "4_4") (pintype "passive"))
      (node (ref "IC41") (pin "4") (pinfunction "4_4") (pintype "passive"))
    )
    (net (code "228") (name "Net-(IC38-Pad5)") (class "Default")
      (node (ref "IC38") (pin "5") (pinfunction "5_5") (pintype "passive"))
      (node (ref "IC39") (pin "5") (pinfunction "5_5") (pintype "passive"))
      (node (ref "IC40") (pin "5") (pinfunction "5_5") (pintype "passive"))
      (node (ref "IC41") (pin "5") (pinfunction "5_5") (pintype "passive"))
    )
    (net (code "229") (name "Net-(IC38-Pad6)") (class "Default")
      (node (ref "IC38") (pin "6") (pinfunction "6_6") (pintype "passive"))
      (node (ref "IC39") (pin "6") (pinfunction "6_6") (pintype "passive"))
      (node (ref "IC40") (pin "6") (pinfunction "6_6") (pintype "passive"))
      (node (ref "IC41") (pin "6") (pinfunction "6_6") (pintype "passive"))
    )
    (net (code "230") (name "Net-(IC38-Pad7)") (class "Default")
      (node (ref "IC38") (pin "7") (pinfunction "7_7") (pintype "passive"))
      (node (ref "IC39") (pin "7") (pinfunction "7_7") (pintype "passive"))
      (node (ref "IC40") (pin "7") (pinfunction "7_7") (pintype "passive"))
      (node (ref "IC41") (pin "7") (pinfunction "7_7") (pintype "passive"))
    )
    (net (code "231") (name "Net-(IC38-Pad8)") (class "Default")
      (node (ref "IC38") (pin "8") (pinfunction "8_8") (pintype "passive"))
      (node (ref "IC39") (pin "8") (pinfunction "8_8") (pintype "passive"))
      (node (ref "IC40") (pin "8") (pinfunction "8_8") (pintype "passive"))
      (node (ref "IC41") (pin "8") (pinfunction "8_8") (pintype "passive"))
    )
    (net (code "232") (name "Net-(IC38-Pad9)") (class "Default")
      (node (ref "IC38") (pin "9") (pinfunction "9_9") (pintype "passive"))
      (node (ref "IC39") (pin "9") (pinfunction "9_9") (pintype "passive"))
      (node (ref "IC40") (pin "9") (pinfunction "9_9") (pintype "passive"))
      (node (ref "IC41") (pin "9") (pinfunction "9_9") (pintype "passive"))
    )
    (net (code "233") (name "Net-(IC38-Pad10)") (class "Default")
      (node (ref "IC38") (pin "10") (pinfunction "10_10") (pintype "passive"))
      (node (ref "IC39") (pin "10") (pinfunction "10_10") (pintype "passive"))
      (node (ref "IC40") (pin "10") (pinfunction "10_10") (pintype "passive"))
      (node (ref "IC41") (pin "10") (pinfunction "10_10") (pintype "passive"))
    )
    (net (code "234") (name "Net-(IC38-Pad11)") (class "Default")
      (node (ref "IC38") (pin "11") (pinfunction "11_11") (pintype "passive"))
      (node (ref "IC39") (pin "11") (pinfunction "11_11") (pintype "passive"))
      (node (ref "IC40") (pin "11") (pinfunction "11_11") (pintype "passive"))
      (node (ref "IC41") (pin "11") (pinfunction "11_11") (pintype "passive"))
    )
    (net (code "235") (name "Net-(IC38-Pad12)") (class "Default")
      (node (ref "IC38") (pin "12") (pinfunction "12_12") (pintype "passive"))
      (node (ref "IC39") (pin "12") (pinfunction "12_12") (pintype "passive"))
      (node (ref "IC40") (pin "12") (pinfunction "12_12") (pintype "passive"))
      (node (ref "IC41") (pin "12") (pinfunction "12_12") (pintype "passive"))
    )
    (net (code "236") (name "Net-(IC38-Pad13)") (class "Default")
      (node (ref "IC38") (pin "13") (pinfunction "13_13") (pintype "passive"))
      (node (ref "IC39") (pin "13") (pinfunction "13_13") (pintype "passive"))
      (node (ref "IC40") (pin "13") (pinfunction "13_13") (pintype "passive"))
      (node (ref "IC41") (pin "13") (pinfunction "13_13") (pintype "passive"))
    )
    (net (code "237") (name "Net-(IC38-Pad14)") (class "Default")
      (node (ref "IC38") (pin "14") (pinfunction "14_14") (pintype "passive"))
      (node (ref "IC39") (pin "14") (pinfunction "14_14") (pintype "passive"))
      (node (ref "IC40") (pin "14") (pinfunction "14_14") (pintype "passive"))
      (node (ref "IC41") (pin "14") (pinfunction "14_14") (pintype "passive"))
    )
    (net (code "238") (name "Net-(IC38-Pad15)") (class "Default")
      (node (ref "IC38") (pin "15") (pinfunction "15_15") (pintype "passive"))
      (node (ref "IC39") (pin "15") (pinfunction "15_15") (pintype "passive"))
      (node (ref "IC40") (pin "15") (pinfunction "15_15") (pintype "passive"))
      (node (ref "IC41") (pin "15") (pinfunction "15_15") (pintype "passive"))
    )
    (net (code "239") (name "Net-(IC38-Pad16)") (class "Default")
      (node (ref "IC38") (pin "16") (pinfunction "16_16") (pintype "passive"))
      (node (ref "IC39") (pin "16") (pinfunction "16_16") (pintype "passive"))
      (node (ref "IC40") (pin "16") (pinfunction "16_16") (pintype "passive"))
      (node (ref "IC41") (pin "16") (pinfunction "16_16") (pintype "passive"))
    )
    (net (code "240") (name "Net-(IC38-Pad17)") (class "Default")
      (node (ref "IC38") (pin "17") (pinfunction "17_17") (pintype "passive"))
      (node (ref "IC39") (pin "17") (pinfunction "17_17") (pintype "passive"))
      (node (ref "IC40") (pin "17") (pinfunction "17_17") (pintype "passive"))
      (node (ref "IC41") (pin "17") (pinfunction "17_17") (pintype "passive"))
    )
    (net (code "241") (name "Net-(IC38-Pad18)") (class "Default")
      (node (ref "IC38") (pin "18") (pinfunction "18_18") (pintype "passive"))
      (node (ref "IC39") (pin "18") (pinfunction "18_18") (pintype "passive"))
      (node (ref "IC40") (pin "18") (pinfunction "18_18") (pintype "passive"))
      (node (ref "IC41") (pin "18") (pinfunction "18_18") (pintype "passive"))
    )
    (net (code "242") (name "Net-(IC38-Pad19)") (class "Default")
      (node (ref "IC38") (pin "19") (pinfunction "19_19") (pintype "passive"))
      (node (ref "IC39") (pin "19") (pinfunction "19_19") (pintype "passive"))
      (node (ref "IC40") (pin "19") (pinfunction "19_19") (pintype "passive"))
      (node (ref "IC41") (pin "19") (pinfunction "19_19") (pintype "passive"))
    )
    (net (code "243") (name "Net-(IC38-Pad20)") (class "Default")
      (node (ref "IC38") (pin "20") (pinfunction "20_20") (pintype "passive"))
      (node (ref "IC39") (pin "20") (pinfunction "20_20") (pintype "passive"))
      (node (ref "IC40") (pin "20") (pinfunction "20_20") (pintype "passive"))
      (node (ref "IC41") (pin "20") (pinfunction "20_20") (pintype "passive"))
    )
    (net (code "244") (name "Net-(IC38-Pad21)") (class "Default")
      (node (ref "IC38") (pin "21") (pinfunction "21_21") (pintype "passive"))
      (node (ref "IC39") (pin "21") (pinfunction "21_21") (pintype "passive"))
      (node (ref "IC40") (pin "21") (pinfunction "21_21") (pintype "passive"))
      (node (ref "IC41") (pin "21") (pinfunction "21_21") (pintype "passive"))
    )
    (net (code "245") (name "Net-(IC38-Pad22)") (class "Default")
      (node (ref "IC38") (pin "22") (pinfunction "22_22") (pintype "passive"))
      (node (ref "IC39") (pin "22") (pinfunction "22_22") (pintype "passive"))
      (node (ref "IC40") (pin "22") (pinfunction "22_22") (pintype "passive"))
      (node (ref "IC41") (pin "22") (pinfunction "22_22") (pintype "passive"))
    )
    (net (code "246") (name "Net-(IC38-Pad23)") (class "Default")
      (node (ref "IC38") (pin "23") (pinfunction "23_23") (pintype "passive"))
      (node (ref "IC39") (pin "23") (pinfunction "23_23") (pintype "passive"))
      (node (ref "IC40") (pin "23") (pinfunction "23_23") (pintype "passive"))
      (node (ref "IC41") (pin "23") (pinfunction "23_23") (pintype "passive"))
    )
    (net (code "247") (name "Net-(IC38-Pad24)") (class "Default")
      (node (ref "IC38") (pin "24") (pinfunction "24_24") (pintype "passive"))
      (node (ref "IC39") (pin "24") (pinfunction "24_24") (pintype "passive"))
      (node (ref "IC40") (pin "24") (pinfunction "24_24") (pintype "passive"))
      (node (ref "IC41") (pin "24") (pinfunction "24_24") (pintype "passive"))
    )
    (net (code "248") (name "Net-(IC42-Pad1)") (class "Default")
      (node (ref "IC42") (pin "1") (pinfunction "1_1") (pintype "passive"))
      (node (ref "IC43") (pin "1") (pinfunction "1_1") (pintype "passive"))
      (node (ref "IC44") (pin "1") (pinfunction "1_1") (pintype "passive"))
      (node (ref "IC45") (pin "1") (pinfunction "1_1") (pintype "passive"))
    )
    (net (code "249") (name "Net-(IC42-Pad2)") (class "Default")
      (node (ref "IC42") (pin "2") (pinfunction "2_2") (pintype "passive"))
      (node (ref "IC43") (pin "2") (pinfunction "2_2") (pintype "passive"))
      (node (ref "IC44") (pin "2") (pinfunction "2_2") (pintype "passive"))
      (node (ref "IC45") (pin "2") (pinfunction "2_2") (pintype "passive"))
    )
    (net (code "250") (name "Net-(IC42-Pad3)") (class "Default")
      (node (ref "IC42") (pin "3") (pinfunction "3_3") (pintype "passive"))
      (node (ref "IC43") (pin "3") (pinfunction "3_3") (pintype "passive"))
      (node (ref "IC44") (pin "3") (pinfunction "3_3") (pintype "passive"))
      (node (ref "IC45") (pin "3") (pinfunction "3_3") (pintype "passive"))
    )
    (net (code "251") (name "Net-(IC42-Pad4)") (class "Default")
      (node (ref "IC42") (pin "4") (pinfunction "4_4") (pintype "passive"))
      (node (ref "IC43") (pin "4") (pinfunction "4_4") (pintype "passive"))
      (node (ref "IC44") (pin "4") (pinfunction "4_4") (pintype "passive"))
      (node (ref "IC45") (pin "4") (pinfunction "4_4") (pintype "passive"))
    )
    (net (code "252") (name "Net-(IC42-Pad5)") (class "Default")
      (node (ref "IC42") (pin "5") (pinfunction "5_5") (pintype "passive"))
      (node (ref "IC43") (pin "5") (pinfunction "5_5") (pintype "passive"))
      (node (ref "IC44") (pin "5") (pinfunction "5_5") (pintype "passive"))
      (node (ref "IC45") (pin "5") (pinfunction "5_5") (pintype "passive"))
    )
    (net (code "253") (name "Net-(IC42-Pad6)") (class "Default")
      (node (ref "IC42") (pin "6") (pinfunction "6_6") (pintype "passive"))
      (node (ref "IC43") (pin "6") (pinfunction "6_6") (pintype "passive"))
      (node (ref "IC44") (pin "6") (pinfunction "6_6") (pintype "passive"))
      (node (ref "IC45") (pin "6") (pinfunction "6_6") (pintype "passive"))
    )
    (net (code "254") (name "Net-(IC42-Pad7)") (class "Default")
      (node (ref "IC42") (pin "7") (pinfunction "7_7") (pintype "passive"))
      (node (ref "IC43") (pin "7") (pinfunction "7_7") (pintype "passive"))
      (node (ref "IC44") (pin "7") (pinfunction "7_7") (pintype "passive"))
      (node (ref "IC45") (pin "7") (pinfunction "7_7") (pintype "passive"))
    )
    (net (code "255") (name "Net-(IC42-Pad8)") (class "Default")
      (node (ref "IC42") (pin "8") (pinfunction "8_8") (pintype "passive"))
      (node (ref "IC43") (pin "8") (pinfunction "8_8") (pintype "passive"))
      (node (ref "IC44") (pin "8") (pinfunction "8_8") (pintype "passive"))
      (node (ref "IC45") (pin "8") (pinfunction "8_8") (pintype "passive"))
    )
    (net (code "256") (name "Net-(IC42-Pad9)") (class "Default")
      (node (ref "IC42") (pin "9") (pinfunction "9_9") (pintype "passive"))
      (node (ref "IC43") (pin "9") (pinfunction "9_9") (pintype "passive"))
      (node (ref "IC44") (pin "9") (pinfunction "9_9") (pintype "passive"))
      (node (ref "IC45") (pin "9") (pinfunction "9_9") (pintype "passive"))
    )
    (net (code "257") (name "Net-(IC42-Pad10)") (class "Default")
      (node (ref "IC42") (pin "10") (pinfunction "10_10") (pintype "passive"))
      (node (ref "IC43") (pin "10") (pinfunction "10_10") (pintype "passive"))
      (node (ref "IC44") (pin "10") (pinfunction "10_10") (pintype "passive"))
      (node (ref "IC45") (pin "10") (pinfunction "10_10") (pintype "passive"))
    )
    (net (code "258") (name "Net-(IC42-Pad11)") (class "Default")
      (node (ref "IC42") (pin "11") (pinfunction "11_11") (pintype "passive"))
      (node (ref "IC43") (pin "11") (pinfunction "11_11") (pintype "passive"))
      (node (ref "IC44") (pin "11") (pinfunction "11_11") (pintype "passive"))
      (node (ref "IC45") (pin "11") (pinfunction "11_11") (pintype "passive"))
    )
    (net (code "259") (name "Net-(IC42-Pad12)") (class "Default")
      (node (ref "IC42") (pin "12") (pinfunction "12_12") (pintype "passive"))
      (node (ref "IC43") (pin "12") (pinfunction "12_12") (pintype "passive"))
      (node (ref "IC44") (pin "12") (pinfunction "12_12") (pintype "passive"))
      (node (ref "IC45") (pin "12") (pinfunction "12_12") (pintype "passive"))
    )
    (net (code "260") (name "Net-(IC42-Pad13)") (class "Default")
      (node (ref "IC42") (pin "13") (pinfunction "13_13") (pintype "passive"))
      (node (ref "IC43") (pin "13") (pinfunction "13_13") (pintype "passive"))
      (node (ref "IC44") (pin "13") (pinfunction "13_13") (pintype "passive"))
      (node (ref "IC45") (pin "13") (pinfunction "13_13") (pintype "passive"))
    )
    (net (code "261") (name "Net-(IC42-Pad14)") (class "Default")
      (node (ref "IC42") (pin "14") (pinfunction "14_14") (pintype "passive"))
      (node (ref "IC43") (pin "14") (pinfunction "14_14") (pintype "passive"))
      (node (ref "IC44") (pin "14") (pinfunction "14_14") (pintype "passive"))
      (node (ref "IC45") (pin "14") (pinfunction "14_14") (pintype "passive"))
    )
    (net (code "262") (name "Net-(IC42-Pad15)") (class "Default")
      (node (ref "IC42") (pin "15") (pinfunction "15_15") (pintype "passive"))
      (node (ref "IC43") (pin "15") (pinfunction "15_15") (pintype "passive"))
      (node (ref "IC44") (pin "15") (pinfunction "15_15") (pintype "passive"))
      (node (ref "IC45") (pin "15") (pinfunction "15_15") (pintype "passive"))
    )
    (net (code "263") (name "Net-(IC42-Pad16)") (class "Default")
      (node (ref "IC42") (pin "16") (pinfunction "16_16") (pintype "passive"))
      (node (ref "IC43") (pin "16") (pinfunction "16_16") (pintype "passive"))
      (node (ref "IC44") (pin "16") (pinfunction "16_16") (pintype "passive"))
      (node (ref "IC45") (pin "16") (pinfunction "16_16") (pintype "passive"))
    )
    (net (code "264") (name "Net-(IC42-Pad17)") (class "Default")
      (node (ref "IC42") (pin "17") (pinfunction "17_17") (pintype "passive"))
      (node (ref "IC43") (pin "17") (pinfunction "17_17") (pintype "passive"))
      (node (ref "IC44") (pin "17") (pinfunction "17_17") (pintype "passive"))
      (node (ref "IC45") (pin "17") (pinfunction "17_17") (pintype "passive"))
    )
    (net (code "265") (name "Net-(IC42-Pad18)") (class "Default")
      (node (ref "IC42") (pin "18") (pinfunction "18_18") (pintype "passive"))
      (node (ref "IC43") (pin "18") (pinfunction "18_18") (pintype "passive"))
      (node (ref "IC44") (pin "18") (pinfunction "18_18") (pintype "passive"))
      (node (ref "IC45") (pin "18") (pinfunction "18_18") (pintype "passive"))
    )
    (net (code "266") (name "Net-(IC42-Pad19)") (class "Default")
      (node (ref "IC42") (pin "19") (pinfunction "19_19") (pintype "passive"))
      (node (ref "IC43") (pin "19") (pinfunction "19_19") (pintype "passive"))
      (node (ref "IC44") (pin "19") (pinfunction "19_19") (pintype "passive"))
      (node (ref "IC45") (pin "19") (pinfunction "19_19") (pintype "passive"))
    )
    (net (code "267") (name "Net-(IC42-Pad20)") (class "Default")
      (node (ref "IC42") (pin "20") (pinfunction "20_20") (pintype "passive"))
      (node (ref "IC43") (pin "20") (pinfunction "20_20") (pintype "passive"))
      (node (ref "IC44") (pin "20") (pinfunction "20_20") (pintype "passive"))
      (node (ref "IC45") (pin "20") (pinfunction "20_20") (pintype "passive"))
    )
    (net (code "268") (name "Net-(IC42-Pad21)") (class "Default")
      (node (ref "IC42") (pin "21") (pinfunction "21_21") (pintype "passive"))
      (node (ref "IC43") (pin "21") (pinfunction "21_21") (pintype "passive"))
      (node (ref "IC44") (pin "21") (pinfunction "21_21") (pintype "passive"))
      (node (ref "IC45") (pin "21") (pinfunction "21_21") (pintype "passive"))
    )
    (net (code "269") (name "Net-(IC42-Pad22)") (class "Default")
      (node (ref "IC42") (pin "22") (pinfunction "22_22") (pintype "passive"))
      (node (ref "IC43") (pin "22") (pinfunction "22_22") (pintype "passive"))
      (node (ref "IC44") (pin "22") (pinfunction "22_22") (pintype "passive"))
      (node (ref "IC45") (pin "22") (pinfunction "22_22") (pintype "passive"))
    )
    (net (code "270") (name "Net-(IC42-Pad23)") (class "Default")
      (node (ref "IC42") (pin "23") (pinfunction "23_23") (pintype "passive"))
      (node (ref "IC43") (pin "23") (pinfunction "23_23") (pintype "passive"))
      (node (ref "IC44") (pin "23") (pinfunction "23_23") (pintype "passive"))
      (node (ref "IC45") (pin "23") (pinfunction "23_23") (pintype "passive"))
    )
    (net (code "271") (name "Net-(IC42-Pad24)") (class "Default")
      (node (ref "IC42") (pin "24") (pinfunction "24_24") (pintype "passive"))
      (node (ref "IC43") (pin "24") (pinfunction "24_24") (pintype "passive"))
      (node (ref "IC44") (pin "24") (pinfunction "24_24") (pintype "passive"))
      (node (ref "IC45") (pin "24") (pinfunction "24_24") (pintype "passive"))
    )
    (net (code "272") (name "Net-(IC46-Pad1)") (class "Default")
      (node (ref "IC46") (pin "1") (pinfunction "1_1") (pintype "passive"))
      (node (ref "IC47") (pin "1") (pinfunction "1_1") (pintype "passive"))
      (node (ref "IC48") (pin "1") (pinfunction "1_1") (pintype "passive"))
      (node (ref "IC49") (pin "1") (pinfunction "1_1") (pintype "passive"))
    )
    (net (code "273") (name "Net-(IC46-Pad2)") (class "Default")
      (node (ref "IC46") (pin "2") (pinfunction "2_2") (pintype "passive"))
      (node (ref "IC47") (pin "2") (pinfunction "2_2") (pintype "passive"))
      (node (ref "IC48") (pin "2") (pinfunction "2_2") (pintype "passive"))
      (node (ref "IC49") (pin "2") (pinfunction "2_2") (pintype "passive"))
    )
    (net (code "274") (name "Net-(IC46-Pad3)") (class "Default")
      (node (ref "IC46") (pin "3") (pinfunction "3_3") (pintype "passive"))
      (node (ref "IC47") (pin "3") (pinfunction "3_3") (pintype "passive"))
      (node (ref "IC48") (pin "3") (pinfunction "3_3") (pintype "passive"))
      (node (ref "IC49") (pin "3") (pinfunction "3_3") (pintype "passive"))
    )
    (net (code "275") (name "Net-(IC46-Pad4)") (class "Default")
      (node (ref "IC46") (pin "4") (pinfunction "4_4") (pintype "passive"))
      (node (ref "IC47") (pin "4") (pinfunction "4_4") (pintype "passive"))
      (node (ref "IC48") (pin "4") (pinfunction "4_4") (pintype "passive"))
      (node (ref "IC49") (pin "4") (pinfunction "4_4") (pintype "passive"))
    )
    (net (code "276") (name "Net-(IC46-Pad5)") (class "Default")
      (node (ref "IC46") (pin "5") (pinfunction "5_5") (pintype "passive"))
      (node (ref "IC47") (pin "5") (pinfunction "5_5") (pintype "passive"))
      (node (ref "IC48") (pin "5") (pinfunction "5_5") (pintype "passive"))
      (node (ref "IC49") (pin "5") (pinfunction "5_5") (pintype "passive"))
    )
    (net (code "277") (name "Net-(IC46-Pad6)") (class "Default")
      (node (ref "IC46") (pin "6") (pinfunction "6_6") (pintype "passive"))
      (node (ref "IC47") (pin "6") (pinfunction "6_6") (pintype "passive"))
      (node (ref "IC48") (pin "6") (pinfunction "6_6") (pintype "passive"))
      (node (ref "IC49") (pin "6") (pinfunction "6_6") (pintype "passive"))
    )
    (net (code "278") (name "Net-(IC46-Pad7)") (class "Default")
      (node (ref "IC46") (pin "7") (pinfunction "7_7") (pintype "passive"))
      (node (ref "IC47") (pin "7") (pinfunction "7_7") (pintype "passive"))
      (node (ref "IC48") (pin "7") (pinfunction "7_7") (pintype "passive"))
      (node (ref "IC49") (pin "7") (pinfunction "7_7") (pintype "passive"))
    )
    (net (code "279") (name "Net-(IC46-Pad8)") (class "Default")
      (node (ref "IC46") (pin "8") (pinfunction "8_8") (pintype "passive"))
      (node (ref "IC47") (pin "8") (pinfunction "8_8") (pintype "passive"))
      (node (ref "IC48") (pin "8") (pinfunction "8_8") (pintype "passive"))
      (node (ref "IC49") (pin "8") (pinfunction "8_8") (pintype "passive"))
    )
    (net (code "280") (name "Net-(IC46-Pad9)") (class "Default")
      (node (ref "IC46") (pin "9") (pinfunction "9_9") (pintype "passive"))
      (node (ref "IC47") (pin "9") (pinfunction "9_9") (pintype "passive"))
      (node (ref "IC48") (pin "9") (pinfunction "9_9") (pintype "passive"))
      (node (ref "IC49") (pin "9") (pinfunction "9_9") (pintype "passive"))
    )
    (net (code "281") (name "Net-(IC46-Pad10)") (class "Default")
      (node (ref "IC46") (pin "10") (pinfunction "10_10") (pintype "passive"))
      (node (ref "IC47") (pin "10") (pinfunction "10_10") (pintype "passive"))
      (node (ref "IC48") (pin "10") (pinfunction "10_10") (pintype "passive"))
      (node (ref "IC49") (pin "10") (pinfunction "10_10") (pintype "passive"))
    )
    (net (code "282") (name "Net-(IC46-Pad11)") (class "Default")
      (node (ref "IC46") (pin "11") (pinfunction "11_11") (pintype "passive"))
      (node (ref "IC47") (pin "11") (pinfunction "11_11") (pintype "passive"))
      (node (ref "IC48") (pin "11") (pinfunction "11_11") (pintype "passive"))
      (node (ref "IC49") (pin "11") (pinfunction "11_11") (pintype "passive"))
    )
    (net (code "283") (name "Net-(IC46-Pad12)") (class "Default")
      (node (ref "IC46") (pin "12") (pinfunction "12_12") (pintype "passive"))
      (node (ref "IC47") (pin "12") (pinfunction "12_12") (pintype "passive"))
      (node (ref "IC48") (pin "12") (pinfunction "12_12") (pintype "passive"))
      (node (ref "IC49") (pin "12") (pinfunction "12_12") (pintype "passive"))
    )
    (net (code "284") (name "Net-(IC46-Pad13)") (class "Default")
      (node (ref "IC46") (pin "13") (pinfunction "13_13") (pintype "passive"))
      (node (ref "IC47") (pin "13") (pinfunction "13_13") (pintype "passive"))
      (node (ref "IC48") (pin "13") (pinfunction "13_13") (pintype "passive"))
      (node (ref "IC49") (pin "13") (pinfunction "13_13") (pintype "passive"))
    )
    (net (code "285") (name "Net-(IC46-Pad14)") (class "Default")
      (node (ref "IC46") (pin "14") (pinfunction "14_14") (pintype "passive"))
      (node (ref "IC47") (pin "14") (pinfunction "14_14") (pintype "passive"))
      (node (ref "IC48") (pin "14") (pinfunction "14_14") (pintype "passive"))
      (node (ref "IC49") (pin "14") (pinfunction "14_14") (pintype "passive"))
    )
    (net (code "286") (name "Net-(IC46-Pad15)") (class "Default")
      (node (ref "IC46") (pin "15") (pinfunction "15_15") (pintype "passive"))
      (node (ref "IC47") (pin "15") (pinfunction "15_15") (pintype "passive"))
      (node (ref "IC48") (pin "15") (pinfunction "15_15") (pintype "passive"))
      (node (ref "IC49") (pin "15") (pinfunction "15_15") (pintype "passive"))
    )
    (net (code "287") (name "Net-(IC46-Pad16)") (class "Default")
      (node (ref "IC46") (pin "16") (pinfunction "16_16") (pintype "passive"))
      (node (ref "IC47") (pin "16") (pinfunction "16_16") (pintype "passive"))
      (node (ref "IC48") (pin "16") (pinfunction "16_16") (pintype "passive"))
      (node (ref "IC49") (pin "16") (pinfunction "16_16") (pintype "passive"))
    )
    (net (code "288") (name "Net-(IC46-Pad17)") (class "Default")
      (node (ref "IC46") (pin "17") (pinfunction "17_17") (pintype "passive"))
      (node (ref "IC47") (pin "17") (pinfunction "17_17") (pintype "passive"))
      (node (ref "IC48") (pin "17") (pinfunction "17_17") (pintype "passive"))
      (node (ref "IC49") (pin "17") (pinfunction "17_17") (pintype "passive"))
    )
    (net (code "289") (name "Net-(IC46-Pad18)") (class "Default")
      (node (ref "IC46") (pin "18") (pinfunction "18_18") (pintype "passive"))
      (node (ref "IC47") (pin "18") (pinfunction "18_18") (pintype "passive"))
      (node (ref "IC48") (pin "18") (pinfunction "18_18") (pintype "passive"))
      (node (ref "IC49") (pin "18") (pinfunction "18_18") (pintype "passive"))
    )
    (net (code "290") (name "Net-(IC46-Pad19)") (class "Default")
      (node (ref "IC46") (pin "19") (pinfunction "19_19") (pintype "passive"))
      (node (ref "IC47") (pin "19") (pinfunction "19_19") (pintype "passive"))
      (node (ref "IC48") (pin "19") (pinfunction "19_19") (pintype "passive"))
      (node (ref "IC49") (pin "19") (pinfunction "19_19") (pintype "passive"))
    )
    (net (code "291") (name "Net-(IC46-Pad20)") (class "Default")
      (node (ref "IC46") (pin "20") (pinfunction "20_20") (pintype "passive"))
      (node (ref "IC47") (pin "20") (pinfunction "20_20") (pintype "passive"))
      (node (ref "IC48") (pin "20") (pinfunction "20_20") (pintype "passive"))
      (node (ref "IC49") (pin "20") (pinfunction "20_20") (pintype "passive"))
    )
    (net (code "292") (name "Net-(IC46-Pad21)") (class "Default")
      (node (ref "IC46") (pin "21") (pinfunction "21_21") (pintype "passive"))
      (node (ref "IC47") (pin "21") (pinfunction "21_21") (pintype "passive"))
      (node (ref "IC48") (pin "21") (pinfunction "21_21") (pintype "passive"))
      (node (ref "IC49") (pin "21") (pinfunction "21_21") (pintype "passive"))
    )
    (net (code "293") (name "Net-(IC46-Pad22)") (class "Default")
      (node (ref "IC46") (pin "22") (pinfunction "22_22") (pintype "passive"))
      (node (ref "IC47") (pin "22") (pinfunction "22_22") (pintype "passive"))
      (node (ref "IC48") (pin "22") (pinfunction "22_22") (pintype "passive"))
      (node (ref "IC49") (pin "22") (pinfunction "22_22") (pintype "passive"))
    )
    (net (code "294") (name "Net-(IC46-Pad23)") (class "Default")
      (node (ref "IC46") (pin "23") (pinfunction "23_23") (pintype "passive"))
      (node (ref "IC47") (pin "23") (pinfunction "23_23") (pintype "passive"))
      (node (ref "IC48") (pin "23") (pinfunction "23_23") (pintype "passive"))
      (node (ref "IC49") (pin "23") (pinfunction "23_23") (pintype "passive"))
    )
    (net (code "295") (name "Net-(IC46-Pad24)") (class "Default")
      (node (ref "IC46") (pin "24") (pinfunction "24_24") (pintype "passive"))
      (node (ref "IC47") (pin "24") (pinfunction "24_24") (pintype "passive"))
      (node (ref "IC48") (pin "24") (pinfunction "24_24") (pintype "passive"))
      (node (ref "IC49") (pin "24") (pinfunction "24_24") (pintype "passive"))
    )
    (net (code "296") (name "Net-(IC50-Pad1)") (class "Default")
      (node (ref "IC50") (pin "1") (pinfunction "1_1") (pintype "passive"))
      (node (ref "IC51") (pin "1") (pinfunction "1_1") (pintype "passive"))
      (node (ref "IC52") (pin "1") (pinfunction "1_1") (pintype "passive"))
      (node (ref "IC53") (pin "1") (pinfunction "1_1") (pintype "passive"))
    )
    (net (code "297") (name "Net-(IC50-Pad2)") (class "Default")
      (node (ref "IC50") (pin "2") (pinfunction "2_2") (pintype "passive"))
      (node (ref "IC51") (pin "2") (pinfunction "2_2") (pintype "passive"))
      (node (ref "IC52") (pin "2") (pinfunction "2_2") (pintype "passive"))
      (node (ref "IC53") (pin "2") (pinfunction "2_2") (pintype "passive"))
    )
    (net (code "298") (name "Net-(IC50-Pad3)") (class "Default")
      (node (ref "IC50") (pin "3") (pinfunction "3_3") (pintype "passive"))
      (node (ref "IC51") (pin "3") (pinfunction "3_3") (pintype "passive"))
      (node (ref "IC52") (pin "3") (pinfunction "3_3") (pintype "passive"))
      (node (ref "IC53") (pin "3") (pinfunction "3_3") (pintype "passive"))
    )
    (net (code "299") (name "Net-(IC50-Pad4)") (class "Default")
      (node (ref "IC50") (pin "4") (pinfunction "4_4") (pintype "passive"))
      (node (ref "IC51") (pin "4") (pinfunction "4_4") (pintype "passive"))
      (node (ref "IC52") (pin "4") (pinfunction "4_4") (pintype "passive"))
      (node (ref "IC53") (pin "4") (pinfunction "4_4") (pintype "passive"))
    )
    (net (code "300") (name "Net-(IC50-Pad5)") (class "Default")
      (node (ref "IC50") (pin "5") (pinfunction "5_5") (pintype "passive"))
      (node (ref "IC51") (pin "5") (pinfunction "5_5") (pintype "passive"))
      (node (ref "IC52") (pin "5") (pinfunction "5_5") (pintype "passive"))
      (node (ref "IC53") (pin "5") (pinfunction "5_5") (pintype "passive"))
    )
    (net (code "301") (name "Net-(IC50-Pad6)") (class "Default")
      (node (ref "IC50") (pin "6") (pinfunction "6_6") (pintype "passive"))
      (node (ref "IC51") (pin "6") (pinfunction "6_6") (pintype "passive"))
      (node (ref "IC52") (pin "6") (pinfunction "6_6") (pintype "passive"))
      (node (ref "IC53") (pin "6") (pinfunction "6_6") (pintype "passive"))
    )
    (net (code "302") (name "Net-(IC50-Pad7)") (class "Default")
      (node (ref "IC50") (pin "7") (pinfunction "7_7") (pintype "passive"))
      (node (ref "IC51") (pin "7") (pinfunction "7_7") (pintype "passive"))
      (node (ref "IC52") (pin "7") (pinfunction "7_7") (pintype "passive"))
      (node (ref "IC53") (pin "7") (pinfunction "7_7") (pintype "passive"))
    )
    (net (code "303") (name "Net-(IC50-Pad8)") (class "Default")
      (node (ref "IC50") (pin "8") (pinfunction "8_8") (pintype "passive"))
      (node (ref "IC51") (pin "8") (pinfunction "8_8") (pintype "passive"))
      (node (ref "IC52") (pin "8") (pinfunction "8_8") (pintype "passive"))
      (node (ref "IC53") (pin "8") (pinfunction "8_8") (pintype "passive"))
    )
    (net (code "304") (name "Net-(IC50-Pad9)") (class "Default")
      (node (ref "IC50") (pin "9") (pinfunction "9_9") (pintype "passive"))
      (node (ref "IC51") (pin "9") (pinfunction "9_9") (pintype "passive"))
      (node (ref "IC52") (pin "9") (pinfunction "9_9") (pintype "passive"))
      (node (ref "IC53") (pin "9") (pinfunction "9_9") (pintype "passive"))
    )
    (net (code "305") (name "Net-(IC50-Pad10)") (class "Default")
      (node (ref "IC50") (pin "10") (pinfunction "10_10") (pintype "passive"))
      (node (ref "IC51") (pin "10") (pinfunction "10_10") (pintype "passive"))
      (node (ref "IC52") (pin "10") (pinfunction "10_10") (pintype "passive"))
      (node (ref "IC53") (pin "10") (pinfunction "10_10") (pintype "passive"))
    )
    (net (code "306") (name "Net-(IC50-Pad11)") (class "Default")
      (node (ref "IC50") (pin "11") (pinfunction "11_11") (pintype "passive"))
      (node (ref "IC51") (pin "11") (pinfunction "11_11") (pintype "passive"))
      (node (ref "IC52") (pin "11") (pinfunction "11_11") (pintype "passive"))
      (node (ref "IC53") (pin "11") (pinfunction "11_11") (pintype "passive"))
    )
    (net (code "307") (name "Net-(IC50-Pad12)") (class "Default")
      (node (ref "IC50") (pin "12") (pinfunction "12_12") (pintype "passive"))
      (node (ref "IC51") (pin "12") (pinfunction "12_12") (pintype "passive"))
      (node (ref "IC52") (pin "12") (pinfunction "12_12") (pintype "passive"))
      (node (ref "IC53") (pin "12") (pinfunction "12_12") (pintype "passive"))
    )
    (net (code "308") (name "Net-(IC50-Pad13)") (class "Default")
      (node (ref "IC50") (pin "13") (pinfunction "13_13") (pintype "passive"))
      (node (ref "IC51") (pin "13") (pinfunction "13_13") (pintype "passive"))
      (node (ref "IC52") (pin "13") (pinfunction "13_13") (pintype "passive"))
      (node (ref "IC53") (pin "13") (pinfunction "13_13") (pintype "passive"))
    )
    (net (code "309") (name "Net-(IC50-Pad14)") (class "Default")
      (node (ref "IC50") (pin "14") (pinfunction "14_14") (pintype "passive"))
      (node (ref "IC51") (pin "14") (pinfunction "14_14") (pintype "passive"))
      (node (ref "IC52") (pin "14") (pinfunction "14_14") (pintype "passive"))
      (node (ref "IC53") (pin "14") (pinfunction "14_14") (pintype "passive"))
    )
    (net (code "310") (name "Net-(IC50-Pad15)") (class "Default")
      (node (ref "IC50") (pin "15") (pinfunction "15_15") (pintype "passive"))
      (node (ref "IC51") (pin "15") (pinfunction "15_15") (pintype "passive"))
      (node (ref "IC52") (pin "15") (pinfunction "15_15") (pintype "passive"))
      (node (ref "IC53") (pin "15") (pinfunction "15_15") (pintype "passive"))
    )
    (net (code "311") (name "Net-(IC50-Pad16)") (class "Default")
      (node (ref "IC50") (pin "16") (pinfunction "16_16") (pintype "passive"))
      (node (ref "IC51") (pin "16") (pinfunction "16_16") (pintype "passive"))
      (node (ref "IC52") (pin "16") (pinfunction "16_16") (pintype "passive"))
      (node (ref "IC53") (pin "16") (pinfunction "16_16") (pintype "passive"))
    )
    (net (code "312") (name "Net-(IC50-Pad17)") (class "Default")
      (node (ref "IC50") (pin "17") (pinfunction "17_17") (pintype "passive"))
      (node (ref "IC51") (pin "17") (pinfunction "17_17") (pintype "passive"))
      (node (ref "IC52") (pin "17") (pinfunction "17_17") (pintype "passive"))
      (node (ref "IC53") (pin "17") (pinfunction "17_17") (pintype "passive"))
    )
    (net (code "313") (name "Net-(IC50-Pad18)") (class "Default")
      (node (ref "IC50") (pin "18") (pinfunction "18_18") (pintype "passive"))
      (node (ref "IC51") (pin "18") (pinfunction "18_18") (pintype "passive"))
      (node (ref "IC52") (pin "18") (pinfunction "18_18") (pintype "passive"))
      (node (ref "IC53") (pin "18") (pinfunction "18_18") (pintype "passive"))
    )
    (net (code "314") (name "Net-(IC50-Pad19)") (class "Default")
      (node (ref "IC50") (pin "19") (pinfunction "19_19") (pintype "passive"))
      (node (ref "IC51") (pin "19") (pinfunction "19_19") (pintype "passive"))
      (node (ref "IC52") (pin "19") (pinfunction "19_19") (pintype "passive"))
      (node (ref "IC53") (pin "19") (pinfunction "19_19") (pintype "passive"))
    )
    (net (code "315") (name "Net-(IC50-Pad20)") (class "Default")
      (node (ref "IC50") (pin "20") (pinfunction "20_20") (pintype "passive"))
      (node (ref "IC51") (pin "20") (pinfunction "20_20") (pintype "passive"))
      (node (ref "IC52") (pin "20") (pinfunction "20_20") (pintype "passive"))
      (node (ref "IC53") (pin "20") (pinfunction "20_20") (pintype "passive"))
    )
    (net (code "316") (name "Net-(IC50-Pad21)") (class "Default")
      (node (ref "IC50") (pin "21") (pinfunction "21_21") (pintype "passive"))
      (node (ref "IC51") (pin "21") (pinfunction "21_21") (pintype "passive"))
      (node (ref "IC52") (pin "21") (pinfunction "21_21") (pintype "passive"))
      (node (ref "IC53") (pin "21") (pinfunction "21_21") (pintype "passive"))
    )
    (net (code "317") (name "Net-(IC50-Pad22)") (class "Default")
      (node (ref "IC50") (pin "22") (pinfunction "22_22") (pintype "passive"))
      (node (ref "IC51") (pin "22") (pinfunction "22_22") (pintype "passive"))
      (node (ref "IC52") (pin "22") (pinfunction "22_22") (pintype "passive"))
      (node (ref "IC53") (pin "22") (pinfunction "22_22") (pintype "passive"))
    )
    (net (code "318") (name "Net-(IC50-Pad23)") (class "Default")
      (node (ref "IC50") (pin "23") (pinfunction "23_23") (pintype "passive"))
      (node (ref "IC51") (pin "23") (pinfunction "23_23") (pintype "passive"))
      (node (ref "IC52") (pin "23") (pinfunction "23_23") (pintype "passive"))
      (node (ref "IC53") (pin "23") (pinfunction "23_23") (pintype "passive"))
    )
    (net (code "319") (name "Net-(IC50-Pad24)") (class "Default")
      (node (ref "IC50") (pin "24") (pinfunction "24_24") (pintype "passive"))
      (node (ref "IC51") (pin "24") (pinfunction "24_24") (pintype "passive"))
      (node (ref "IC52") (pin "24") (pinfunction "24_24") (pintype "passive"))
      (node (ref "IC53") (pin "24") (pinfunction "24_24") (pintype "passive"))
    )
    (net (code "320") (name "Net-(IC54-Pad1)") (class "Default")
      (node (ref "IC54") (pin "1") (pinfunction "1_1") (pintype "passive"))
      (node (ref "IC55") (pin "1") (pinfunction "1_1") (pintype "passive"))
      (node (ref "IC56") (pin "1") (pinfunction "1_1") (pintype "passive"))
      (node (ref "IC57") (pin "1") (pinfunction "1_1") (pintype "passive"))
    )
    (net (code "321") (name "Net-(IC54-Pad2)") (class "Default")
      (node (ref "IC54") (pin "2") (pinfunction "2_2") (pintype "passive"))
      (node (ref "IC55") (pin "2") (pinfunction "2_2") (pintype "passive"))
      (node (ref "IC56") (pin "2") (pinfunction "2_2") (pintype "passive"))
      (node (ref "IC57") (pin "2") (pinfunction "2_2") (pintype "passive"))
    )
    (net (code "322") (name "Net-(IC54-Pad3)") (class "Default")
      (node (ref "IC54") (pin "3") (pinfunction "3_3") (pintype "passive"))
      (node (ref "IC55") (pin "3") (pinfunction "3_3") (pintype "passive"))
      (node (ref "IC56") (pin "3") (pinfunction "3_3") (pintype "passive"))
      (node (ref "IC57") (pin "3") (pinfunction "3_3") (pintype "passive"))
    )
    (net (code "323") (name "Net-(IC54-Pad4)") (class "Default")
      (node (ref "IC54") (pin "4") (pinfunction "4_4") (pintype "passive"))
      (node (ref "IC55") (pin "4") (pinfunction "4_4") (pintype "passive"))
      (node (ref "IC56") (pin "4") (pinfunction "4_4") (pintype "passive"))
      (node (ref "IC57") (pin "4") (pinfunction "4_4") (pintype "passive"))
    )
    (net (code "324") (name "Net-(IC54-Pad5)") (class "Default")
      (node (ref "IC54") (pin "5") (pinfunction "5_5") (pintype "passive"))
      (node (ref "IC55") (pin "5") (pinfunction "5_5") (pintype "passive"))
      (node (ref "IC56") (pin "5") (pinfunction "5_5") (pintype "passive"))
      (node (ref "IC57") (pin "5") (pinfunction "5_5") (pintype "passive"))
    )
    (net (code "325") (name "Net-(IC54-Pad6)") (class "Default")
      (node (ref "IC54") (pin "6") (pinfunction "6_6") (pintype "passive"))
      (node (ref "IC55") (pin "6") (pinfunction "6_6") (pintype "passive"))
      (node (ref "IC56") (pin "6") (pinfunction "6_6") (pintype "passive"))
      (node (ref "IC57") (pin "6") (pinfunction "6_6") (pintype "passive"))
    )
    (net (code "326") (name "Net-(IC54-Pad7)") (class "Default")
      (node (ref "IC54") (pin "7") (pinfunction "7_7") (pintype "passive"))
      (node (ref "IC55") (pin "7") (pinfunction "7_7") (pintype "passive"))
      (node (ref "IC56") (pin "7") (pinfunction "7_7") (pintype "passive"))
      (node (ref "IC57") (pin "7") (pinfunction "7_7") (pintype "passive"))
    )
    (net (code "327") (name "Net-(IC54-Pad8)") (class "Default")
      (node (ref "IC54") (pin "8") (pinfunction "8_8") (pintype "passive"))
      (node (ref "IC55") (pin "8") (pinfunction "8_8") (pintype "passive"))
      (node (ref "IC56") (pin "8") (pinfunction "8_8") (pintype "passive"))
      (node (ref "IC57") (pin "8") (pinfunction "8_8") (pintype "passive"))
    )
    (net (code "328") (name "Net-(IC54-Pad9)") (class "Default")
      (node (ref "IC54") (pin "9") (pinfunction "9_9") (pintype "passive"))
      (node (ref "IC55") (pin "9") (pinfunction "9_9") (pintype "passive"))
      (node (ref "IC56") (pin "9") (pinfunction "9_9") (pintype "passive"))
      (node (ref "IC57") (pin "9") (pinfunction "9_9") (pintype "passive"))
    )
    (net (code "329") (name "Net-(IC54-Pad10)") (class "Default")
      (node (ref "IC54") (pin "10") (pinfunction "10_10") (pintype "passive"))
      (node (ref "IC55") (pin "10") (pinfunction "10_10") (pintype "passive"))
      (node (ref "IC56") (pin "10") (pinfunction "10_10") (pintype "passive"))
      (node (ref "IC57") (pin "10") (pinfunction "10_10") (pintype "passive"))
    )
    (net (code "330") (name "Net-(IC54-Pad11)") (class "Default")
      (node (ref "IC54") (pin "11") (pinfunction "11_11") (pintype "passive"))
      (node (ref "IC55") (pin "11") (pinfunction "11_11") (pintype "passive"))
      (node (ref "IC56") (pin "11") (pinfunction "11_11") (pintype "passive"))
      (node (ref "IC57") (pin "11") (pinfunction "11_11") (pintype "passive"))
    )
    (net (code "331") (name "Net-(IC54-Pad12)") (class "Default")
      (node (ref "IC54") (pin "12") (pinfunction "12_12") (pintype "passive"))
      (node (ref "IC55") (pin "12") (pinfunction "12_12") (pintype "passive"))
      (node (ref "IC56") (pin "12") (pinfunction "12_12") (pintype "passive"))
      (node (ref "IC57") (pin "12") (pinfunction "12_12") (pintype "passive"))
    )
    (net (code "332") (name "Net-(IC54-Pad13)") (class "Default")
      (node (ref "IC54") (pin "13") (pinfunction "13_13") (pintype "passive"))
      (node (ref "IC55") (pin "13") (pinfunction "13_13") (pintype "passive"))
      (node (ref "IC56") (pin "13") (pinfunction "13_13") (pintype "passive"))
      (node (ref "IC57") (pin "13") (pinfunction "13_13") (pintype "passive"))
    )
    (net (code "333") (name "Net-(IC54-Pad14)") (class "Default")
      (node (ref "IC54") (pin "14") (pinfunction "14_14") (pintype "passive"))
      (node (ref "IC55") (pin "14") (pinfunction "14_14") (pintype "passive"))
      (node (ref "IC56") (pin "14") (pinfunction "14_14") (pintype "passive"))
      (node (ref "IC57") (pin "14") (pinfunction "14_14") (pintype "passive"))
    )
    (net (code "334") (name "Net-(IC54-Pad15)") (class "Default")
      (node (ref "IC54") (pin "15") (pinfunction "15_15") (pintype "passive"))
      (node (ref "IC55") (pin "15") (pinfunction "15_15") (pintype "passive"))
      (node (ref "IC56") (pin "15") (pinfunction "15_15") (pintype "passive"))
      (node (ref "IC57") (pin "15") (pinfunction "15_15") (pintype "passive"))
    )
    (net (code "335") (name "Net-(IC54-Pad16)") (class "Default")
      (node (ref "IC54") (pin "16") (pinfunction "16_16") (pintype "passive"))
      (node (ref "IC55") (pin "16") (pinfunction "16_16") (pintype "passive"))
      (node (ref "IC56") (pin "16") (pinfunction "16_16") (pintype "passive"))
      (node (ref "IC57") (pin "16") (pinfunction "16_16") (pintype "passive"))
    )
    (net (code "336") (name "Net-(IC54-Pad17)") (class "Default")
      (node (ref "IC54") (pin "17") (pinfunction "17_17") (pintype "passive"))
      (node (ref "IC55") (pin "17") (pinfunction "17_17") (pintype "passive"))
      (node (ref "IC56") (pin "17") (pinfunction "17_17") (pintype "passive"))
      (node (ref "IC57") (pin "17") (pinfunction "17_17") (pintype "passive"))
    )
    (net (code "337") (name "Net-(IC54-Pad18)") (class "Default")
      (node (ref "IC54") (pin "18") (pinfunction "18_18") (pintype "passive"))
      (node (ref "IC55") (pin "18") (pinfunction "18_18") (pintype "passive"))
      (node (ref "IC56") (pin "18") (pinfunction "18_18") (pintype "passive"))
      (node (ref "IC57") (pin "18") (pinfunction "18_18") (pintype "passive"))
    )
    (net (code "338") (name "Net-(IC54-Pad19)") (class "Default")
      (node (ref "IC54") (pin "19") (pinfunction "19_19") (pintype "passive"))
      (node (ref "IC55") (pin "19") (pinfunction "19_19") (pintype "passive"))
      (node (ref "IC56") (pin "19") (pinfunction "19_19") (pintype "passive"))
      (node (ref "IC57") (pin "19") (pinfunction "19_19") (pintype "passive"))
    )
    (net (code "339") (name "Net-(IC54-Pad20)") (class "Default")
      (node (ref "IC54") (pin "20") (pinfunction "20_20") (pintype "passive"))
      (node (ref "IC55") (pin "20") (pinfunction "20_20") (pintype "passive"))
      (node (ref "IC56") (pin "20") (pinfunction "20_20") (pintype "passive"))
      (node (ref "IC57") (pin "20") (pinfunction "20_20") (pintype "passive"))
    )
    (net (code "340") (name "Net-(IC54-Pad21)") (class "Default")
      (node (ref "IC54") (pin "21") (pinfunction "21_21") (pintype "passive"))
      (node (ref "IC55") (pin "21") (pinfunction "21_21") (pintype "passive"))
      (node (ref "IC56") (pin "21") (pinfunction "21_21") (pintype "passive"))
      (node (ref "IC57") (pin "21") (pinfunction "21_21") (pintype "passive"))
    )
    (net (code "341") (name "Net-(IC54-Pad22)") (class "Default")
      (node (ref "IC54") (pin "22") (pinfunction "22_22") (pintype "passive"))
      (node (ref "IC55") (pin "22") (pinfunction "22_22") (pintype "passive"))
      (node (ref "IC56") (pin "22") (pinfunction "22_22") (pintype "passive"))
      (node (ref "IC57") (pin "22") (pinfunction "22_22") (pintype "passive"))
    )
    (net (code "342") (name "Net-(IC54-Pad23)") (class "Default")
      (node (ref "IC54") (pin "23") (pinfunction "23_23") (pintype "passive"))
      (node (ref "IC55") (pin "23") (pinfunction "23_23") (pintype "passive"))
      (node (ref "IC56") (pin "23") (pinfunction "23_23") (pintype "passive"))
      (node (ref "IC57") (pin "23") (pinfunction "23_23") (pintype "passive"))
    )
    (net (code "343") (name "Net-(IC54-Pad24)") (class "Default")
      (node (ref "IC54") (pin "24") (pinfunction "24_24") (pintype "passive"))
      (node (ref "IC55") (pin "24") (pinfunction "24_24") (pintype "passive"))
      (node (ref "IC56") (pin "24") (pinfunction "24_24") (pintype "passive"))
      (node (ref "IC57") (pin "24") (pinfunction "24_24") (pintype "passive"))
    )
    (net (code "344") (name "Net-(IC58-Pad1)") (class "Default")
      (node (ref "IC58") (pin "1") (pinfunction "1_1") (pintype "passive"))
      (node (ref "IC59") (pin "1") (pinfunction "1_1") (pintype "passive"))
      (node (ref "IC60") (pin "1") (pinfunction "1_1") (pintype "passive"))
      (node (ref "IC61") (pin "1") (pinfunction "1_1") (pintype "passive"))
    )
    (net (code "345") (name "Net-(IC58-Pad2)") (class "Default")
      (node (ref "IC58") (pin "2") (pinfunction "2_2") (pintype "passive"))
      (node (ref "IC59") (pin "2") (pinfunction "2_2") (pintype "passive"))
      (node (ref "IC60") (pin "2") (pinfunction "2_2") (pintype "passive"))
      (node (ref "IC61") (pin "2") (pinfunction "2_2") (pintype "passive"))
    )
    (net (code "346") (name "Net-(IC58-Pad3)") (class "Default")
      (node (ref "IC58") (pin "3") (pinfunction "3_3") (pintype "passive"))
      (node (ref "IC59") (pin "3") (pinfunction "3_3") (pintype "passive"))
      (node (ref "IC60") (pin "3") (pinfunction "3_3") (pintype "passive"))
      (node (ref "IC61") (pin "3") (pinfunction "3_3") (pintype "passive"))
    )
    (net (code "347") (name "Net-(IC58-Pad4)") (class "Default")
      (node (ref "IC58") (pin "4") (pinfunction "4_4") (pintype "passive"))
      (node (ref "IC59") (pin "4") (pinfunction "4_4") (pintype "passive"))
      (node (ref "IC60") (pin "4") (pinfunction "4_4") (pintype "passive"))
      (node (ref "IC61") (pin "4") (pinfunction "4_4") (pintype "passive"))
    )
    (net (code "348") (name "Net-(IC58-Pad5)") (class "Default")
      (node (ref "IC58") (pin "5") (pinfunction "5_5") (pintype "passive"))
      (node (ref "IC59") (pin "5") (pinfunction "5_5") (pintype "passive"))
      (node (ref "IC60") (pin "5") (pinfunction "5_5") (pintype "passive"))
      (node (ref "IC61") (pin "5") (pinfunction "5_5") (pintype "passive"))
    )
    (net (code "349") (name "Net-(IC58-Pad6)") (class "Default")
      (node (ref "IC58") (pin "6") (pinfunction "6_6") (pintype "passive"))
      (node (ref "IC59") (pin "6") (pinfunction "6_6") (pintype "passive"))
      (node (ref "IC60") (pin "6") (pinfunction "6_6") (pintype "passive"))
      (node (ref "IC61") (pin "6") (pinfunction "6_6") (pintype "passive"))
    )
    (net (code "350") (name "Net-(IC58-Pad7)") (class "Default")
      (node (ref "IC58") (pin "7") (pinfunction "7_7") (pintype "passive"))
      (node (ref "IC59") (pin "7") (pinfunction "7_7") (pintype "passive"))
      (node (ref "IC60") (pin "7") (pinfunction "7_7") (pintype "passive"))
      (node (ref "IC61") (pin "7") (pinfunction "7_7") (pintype "passive"))
    )
    (net (code "351") (name "Net-(IC58-Pad8)") (class "Default")
      (node (ref "IC58") (pin "8") (pinfunction "8_8") (pintype "passive"))
      (node (ref "IC59") (pin "8") (pinfunction "8_8") (pintype "passive"))
      (node (ref "IC60") (pin "8") (pinfunction "8_8") (pintype "passive"))
      (node (ref "IC61") (pin "8") (pinfunction "8_8") (pintype "passive"))
    )
    (net (code "352") (name "Net-(IC58-Pad9)") (class "Default")
      (node (ref "IC58") (pin "9") (pinfunction "9_9") (pintype "passive"))
      (node (ref "IC59") (pin "9") (pinfunction "9_9") (pintype "passive"))
      (node (ref "IC60") (pin "9") (pinfunction "9_9") (pintype "passive"))
      (node (ref "IC61") (pin "9") (pinfunction "9_9") (pintype "passive"))
    )
    (net (code "353") (name "Net-(IC58-Pad10)") (class "Default")
      (node (ref "IC58") (pin "10") (pinfunction "10_10") (pintype "passive"))
      (node (ref "IC59") (pin "10") (pinfunction "10_10") (pintype "passive"))
      (node (ref "IC60") (pin "10") (pinfunction "10_10") (pintype "passive"))
      (node (ref "IC61") (pin "10") (pinfunction "10_10") (pintype "passive"))
    )
    (net (code "354") (name "Net-(IC58-Pad11)") (class "Default")
      (node (ref "IC58") (pin "11") (pinfunction "11_11") (pintype "passive"))
      (node (ref "IC59") (pin "11") (pinfunction "11_11") (pintype "passive"))
      (node (ref "IC60") (pin "11") (pinfunction "11_11") (pintype "passive"))
      (node (ref "IC61") (pin "11") (pinfunction "11_11") (pintype "passive"))
    )
    (net (code "355") (name "Net-(IC58-Pad12)") (class "Default")
      (node (ref "IC58") (pin "12") (pinfunction "12_12") (pintype "passive"))
      (node (ref "IC59") (pin "12") (pinfunction "12_12") (pintype "passive"))
      (node (ref "IC60") (pin "12") (pinfunction "12_12") (pintype "passive"))
      (node (ref "IC61") (pin "12") (pinfunction "12_12") (pintype "passive"))
    )
    (net (code "356") (name "Net-(IC58-Pad13)") (class "Default")
      (node (ref "IC58") (pin "13") (pinfunction "13_13") (pintype "passive"))
      (node (ref "IC59") (pin "13") (pinfunction "13_13") (pintype "passive"))
      (node (ref "IC60") (pin "13") (pinfunction "13_13") (pintype "passive"))
      (node (ref "IC61") (pin "13") (pinfunction "13_13") (pintype "passive"))
    )
    (net (code "357") (name "Net-(IC58-Pad14)") (class "Default")
      (node (ref "IC58") (pin "14") (pinfunction "14_14") (pintype "passive"))
      (node (ref "IC59") (pin "14") (pinfunction "14_14") (pintype "passive"))
      (node (ref "IC60") (pin "14") (pinfunction "14_14") (pintype "passive"))
      (node (ref "IC61") (pin "14") (pinfunction "14_14") (pintype "passive"))
    )
    (net (code "358") (name "Net-(IC58-Pad15)") (class "Default")
      (node (ref "IC58") (pin "15") (pinfunction "15_15") (pintype "passive"))
      (node (ref "IC59") (pin "15") (pinfunction "15_15") (pintype "passive"))
      (node (ref "IC60") (pin "15") (pinfunction "15_15") (pintype "passive"))
      (node (ref "IC61") (pin "15") (pinfunction "15_15") (pintype "passive"))
    )
    (net (code "359") (name "Net-(IC58-Pad16)") (class "Default")
      (node (ref "IC58") (pin "16") (pinfunction "16_16") (pintype "passive"))
      (node (ref "IC59") (pin "16") (pinfunction "16_16") (pintype "passive"))
      (node (ref "IC60") (pin "16") (pinfunction "16_16") (pintype "passive"))
      (node (ref "IC61") (pin "16") (pinfunction "16_16") (pintype "passive"))
    )
    (net (code "360") (name "Net-(IC58-Pad17)") (class "Default")
      (node (ref "IC58") (pin "17") (pinfunction "17_17") (pintype "passive"))
      (node (ref "IC59") (pin "17") (pinfunction "17_17") (pintype "passive"))
      (node (ref "IC60") (pin "17") (pinfunction "17_17") (pintype "passive"))
      (node (ref "IC61") (pin "17") (pinfunction "17_17") (pintype "passive"))
    )
    (net (code "361") (name "Net-(IC58-Pad18)") (class "Default")
      (node (ref "IC58") (pin "18") (pinfunction "18_18") (pintype "passive"))
      (node (ref "IC59") (pin "18") (pinfunction "18_18") (pintype "passive"))
      (node (ref "IC60") (pin "18") (pinfunction "18_18") (pintype "passive"))
      (node (ref "IC61") (pin "18") (pinfunction "18_18") (pintype "passive"))
    )
    (net (code "362") (name "Net-(IC58-Pad19)") (class "Default")
      (node (ref "IC58") (pin "19") (pinfunction "19_19") (pintype "passive"))
      (node (ref "IC59") (pin "19") (pinfunction "19_19") (pintype "passive"))
      (node (ref "IC60") (pin "19") (pinfunction "19_19") (pintype "passive"))
      (node (ref "IC61") (pin "19") (pinfunction "19_19") (pintype "passive"))
    )
    (net (code "363") (name "Net-(IC58-Pad20)") (class "Default")
      (node (ref "IC58") (pin "20") (pinfunction "20_20") (pintype "passive"))
      (node (ref "IC59") (pin "20") (pinfunction "20_20") (pintype "passive"))
      (node (ref "IC60") (pin "20") (pinfunction "20_20") (pintype "passive"))
      (node (ref "IC61") (pin "20") (pinfunction "20_20") (pintype "passive"))
    )
    (net (code "364") (name "Net-(IC58-Pad21)") (class "Default")
      (node (ref "IC58") (pin "21") (pinfunction "21_21") (pintype "passive"))
      (node (ref "IC59") (pin "21") (pinfunction "21_21") (pintype "passive"))
      (node (ref "IC60") (pin "21") (pinfunction "21_21") (pintype "passive"))
      (node (ref "IC61") (pin "21") (pinfunction "21_21") (pintype "passive"))
    )
    (net (code "365") (name "Net-(IC58-Pad22)") (class "Default")
      (node (ref "IC58") (pin "22") (pinfunction "22_22") (pintype "passive"))
      (node (ref "IC59") (pin "22") (pinfunction "22_22") (pintype "passive"))
      (node (ref "IC60") (pin "22") (pinfunction "22_22") (pintype "passive"))
      (node (ref "IC61") (pin "22") (pinfunction "22_22") (pintype "passive"))
    )
    (net (code "366") (name "Net-(IC58-Pad23)") (class "Default")
      (node (ref "IC58") (pin "23") (pinfunction "23_23") (pintype "passive"))
      (node (ref "IC59") (pin "23") (pinfunction "23_23") (pintype "passive"))
      (node (ref "IC60") (pin "23") (pinfunction "23_23") (pintype "passive"))
      (node (ref "IC61") (pin "23") (pinfunction "23_23") (pintype "passive"))
    )
    (net (code "367") (name "Net-(IC58-Pad24)") (class "Default")
      (node (ref "IC58") (pin "24") (pinfunction "24_24") (pintype "passive"))
      (node (ref "IC59") (pin "24") (pinfunction "24_24") (pintype "passive"))
      (node (ref "IC60") (pin "24") (pinfunction "24_24") (pintype "passive"))
      (node (ref "IC61") (pin "24") (pinfunction "24_24") (pintype "passive"))
    )
    (net (code "368") (name "Net-(IC62-Pad1)") (class "Default")
      (node (ref "IC62") (pin "1") (pinfunction "1_1") (pintype "passive"))
      (node (ref "IC63") (pin "1") (pinfunction "1_1") (pintype "passive"))
      (node (ref "IC64") (pin "1") (pinfunction "1_1") (pintype "passive"))
      (node (ref "IC65") (pin "1") (pinfunction "1_1") (pintype "passive"))
    )
    (net (code "369") (name "Net-(IC62-Pad2)") (class "Default")
      (node (ref "IC62") (pin "2") (pinfunction "2_2") (pintype "passive"))
      (node (ref "IC63") (pin "2") (pinfunction "2_2") (pintype "passive"))
      (node (ref "IC64") (pin "2") (pinfunction "2_2") (pintype "passive"))
      (node (ref "IC65") (pin "2") (pinfunction "2_2") (pintype "passive"))
    )
    (net (code "370") (name "Net-(IC62-Pad3)") (class "Default")
      (node (ref "IC62") (pin "3") (pinfunction "3_3") (pintype "passive"))
      (node (ref "IC63") (pin "3") (pinfunction "3_3") (pintype "passive"))
      (node (ref "IC64") (pin "3") (pinfunction "3_3") (pintype "passive"))
      (node (ref "IC65") (pin "3") (pinfunction "3_3") (pintype "passive"))
    )
    (net (code "371") (name "Net-(IC62-Pad4)") (class "Default")
      (node (ref "IC62") (pin "4") (pinfunction "4_4") (pintype "passive"))
      (node (ref "IC63") (pin "4") (pinfunction "4_4") (pintype "passive"))
      (node (ref "IC64") (pin "4") (pinfunction "4_4") (pintype "passive"))
      (node (ref "IC65") (pin "4") (pinfunction "4_4") (pintype "passive"))
    )
    (net (code "372") (name "Net-(IC62-Pad5)") (class "Default")
      (node (ref "IC62") (pin "5") (pinfunction "5_5") (pintype "passive"))
      (node (ref "IC63") (pin "5") (pinfunction "5_5") (pintype "passive"))
      (node (ref "IC64") (pin "5") (pinfunction "5_5") (pintype "passive"))
      (node (ref "IC65") (pin "5") (pinfunction "5_5") (pintype "passive"))
    )
    (net (code "373") (name "Net-(IC62-Pad6)") (class "Default")
      (node (ref "IC62") (pin "6") (pinfunction "6_6") (pintype "passive"))
      (node (ref "IC63") (pin "6") (pinfunction "6_6") (pintype "passive"))
      (node (ref "IC64") (pin "6") (pinfunction "6_6") (pintype "passive"))
      (node (ref "IC65") (pin "6") (pinfunction "6_6") (pintype "passive"))
    )
    (net (code "374") (name "Net-(IC62-Pad7)") (class "Default")
      (node (ref "IC62") (pin "7") (pinfunction "7_7") (pintype "passive"))
      (node (ref "IC63") (pin "7") (pinfunction "7_7") (pintype "passive"))
      (node (ref "IC64") (pin "7") (pinfunction "7_7") (pintype "passive"))
      (node (ref "IC65") (pin "7") (pinfunction "7_7") (pintype "passive"))
    )
    (net (code "375") (name "Net-(IC62-Pad8)") (class "Default")
      (node (ref "IC62") (pin "8") (pinfunction "8_8") (pintype "passive"))
      (node (ref "IC63") (pin "8") (pinfunction "8_8") (pintype "passive"))
      (node (ref "IC64") (pin "8") (pinfunction "8_8") (pintype "passive"))
      (node (ref "IC65") (pin "8") (pinfunction "8_8") (pintype "passive"))
    )
    (net (code "376") (name "Net-(IC62-Pad9)") (class "Default")
      (node (ref "IC62") (pin "9") (pinfunction "9_9") (pintype "passive"))
      (node (ref "IC63") (pin "9") (pinfunction "9_9") (pintype "passive"))
      (node (ref "IC64") (pin "9") (pinfunction "9_9") (pintype "passive"))
      (node (ref "IC65") (pin "9") (pinfunction "9_9") (pintype "passive"))
    )
    (net (code "377") (name "Net-(IC62-Pad10)") (class "Default")
      (node (ref "IC62") (pin "10") (pinfunction "10_10") (pintype "passive"))
      (node (ref "IC63") (pin "10") (pinfunction "10_10") (pintype "passive"))
      (node (ref "IC64") (pin "10") (pinfunction "10_10") (pintype "passive"))
      (node (ref "IC65") (pin "10") (pinfunction "10_10") (pintype "passive"))
    )
    (net (code "378") (name "Net-(IC62-Pad11)") (class "Default")
      (node (ref "IC62") (pin "11") (pinfunction "11_11") (pintype "passive"))
      (node (ref "IC63") (pin "11") (pinfunction "11_11") (pintype "passive"))
      (node (ref "IC64") (pin "11") (pinfunction "11_11") (pintype "passive"))
      (node (ref "IC65") (pin "11") (pinfunction "11_11") (pintype "passive"))
    )
    (net (code "379") (name "Net-(IC62-Pad12)") (class "Default")
      (node (ref "IC62") (pin "12") (pinfunction "12_12") (pintype "passive"))
      (node (ref "IC63") (pin "12") (pinfunction "12_12") (pintype "passive"))
      (node (ref "IC64") (pin "12") (pinfunction "12_12") (pintype "passive"))
      (node (ref "IC65") (pin "12") (pinfunction "12_12") (pintype "passive"))
    )
    (net (code "380") (name "Net-(IC62-Pad13)") (class "Default")
      (node (ref "IC62") (pin "13") (pinfunction "13_13") (pintype "passive"))
      (node (ref "IC63") (pin "13") (pinfunction "13_13") (pintype "passive"))
      (node (ref "IC64") (pin "13") (pinfunction "13_13") (pintype "passive"))
      (node (ref "IC65") (pin "13") (pinfunction "13_13") (pintype "passive"))
    )
    (net (code "381") (name "Net-(IC62-Pad14)") (class "Default")
      (node (ref "IC62") (pin "14") (pinfunction "14_14") (pintype "passive"))
      (node (ref "IC63") (pin "14") (pinfunction "14_14") (pintype "passive"))
      (node (ref "IC64") (pin "14") (pinfunction "14_14") (pintype "passive"))
      (node (ref "IC65") (pin "14") (pinfunction "14_14") (pintype "passive"))
    )
    (net (code "382") (name "Net-(IC62-Pad15)") (class "Default")
      (node (ref "IC62") (pin "15") (pinfunction "15_15") (pintype "passive"))
      (node (ref "IC63") (pin "15") (pinfunction "15_15") (pintype "passive"))
      (node (ref "IC64") (pin "15") (pinfunction "15_15") (pintype "passive"))
      (node (ref "IC65") (pin "15") (pinfunction "15_15") (pintype "passive"))
    )
    (net (code "383") (name "Net-(IC62-Pad16)") (class "Default")
      (node (ref "IC62") (pin "16") (pinfunction "16_16") (pintype "passive"))
      (node (ref "IC63") (pin "16") (pinfunction "16_16") (pintype "passive"))
      (node (ref "IC64") (pin "16") (pinfunction "16_16") (pintype "passive"))
      (node (ref "IC65") (pin "16") (pinfunction "16_16") (pintype "passive"))
    )
    (net (code "384") (name "Net-(IC62-Pad17)") (class "Default")
      (node (ref "IC62") (pin "17") (pinfunction "17_17") (pintype "passive"))
      (node (ref "IC63") (pin "17") (pinfunction "17_17") (pintype "passive"))
      (node (ref "IC64") (pin "17") (pinfunction "17_17") (pintype "passive"))
      (node (ref "IC65") (pin "17") (pinfunction "17_17") (pintype "passive"))
    )
    (net (code "385") (name "Net-(IC62-Pad18)") (class "Default")
      (node (ref "IC62") (pin "18") (pinfunction "18_18") (pintype "passive"))
      (node (ref "IC63") (pin "18") (pinfunction "18_18") (pintype "passive"))
      (node (ref "IC64") (pin "18") (pinfunction "18_18") (pintype "passive"))
      (node (ref "IC65") (pin "18") (pinfunction "18_18") (pintype "passive"))
    )
    (net (code "386") (name "Net-(IC62-Pad19)") (class "Default")
      (node (ref "IC62") (pin "19") (pinfunction "19_19") (pintype "passive"))
      (node (ref "IC63") (pin "19") (pinfunction "19_19") (pintype "passive"))
      (node (ref "IC64") (pin "19") (pinfunction "19_19") (pintype "passive"))
      (node (ref "IC65") (pin "19") (pinfunction "19_19") (pintype "passive"))
    )
    (net (code "387") (name "Net-(IC62-Pad20)") (class "Default")
      (node (ref "IC62") (pin "20") (pinfunction "20_20") (pintype "passive"))
      (node (ref "IC63") (pin "20") (pinfunction "20_20") (pintype "passive"))
      (node (ref "IC64") (pin "20") (pinfunction "20_20") (pintype "passive"))
      (node (ref "IC65") (pin "20") (pinfunction "20_20") (pintype "passive"))
    )
    (net (code "388") (name "Net-(IC62-Pad21)") (class "Default")
      (node (ref "IC62") (pin "21") (pinfunction "21_21") (pintype "passive"))
      (node (ref "IC63") (pin "21") (pinfunction "21_21") (pintype "passive"))
      (node (ref "IC64") (pin "21") (pinfunction "21_21") (pintype "passive"))
      (node (ref "IC65") (pin "21") (pinfunction "21_21") (pintype "passive"))
    )
    (net (code "389") (name "Net-(IC62-Pad22)") (class "Default")
      (node (ref "IC62") (pin "22") (pinfunction "22_22") (pintype "passive"))
      (node (ref "IC63") (pin "22") (pinfunction "22_22") (pintype "passive"))
      (node (ref "IC64") (pin "22") (pinfunction "22_22") (pintype "passive"))
      (node (ref "IC65") (pin "22") (pinfunction "22_22") (pintype "passive"))
    )
    (net (code "390") (name "Net-(IC62-Pad23)") (class "Default")
      (node (ref "IC62") (pin "23") (pinfunction "23_23") (pintype "passive"))
      (node (ref "IC63") (pin "23") (pinfunction "23_23") (pintype "passive"))
      (node (ref "IC64") (pin "23") (pinfunction "23_23") (pintype "passive"))
      (node (ref "IC65") (pin "23") (pinfunction "23_23") (pintype "passive"))
    )
    (net (code "391") (name "Net-(IC62-Pad24)") (class "Default")
      (node (ref "IC62") (pin "24") (pinfunction "24_24") (pintype "passive"))
      (node (ref "IC63") (pin "24") (pinfunction "24_24") (pintype "passive"))
      (node (ref "IC64") (pin "24") (pinfunction "24_24") (pintype "passive"))
      (node (ref "IC65") (pin "24") (pinfunction "24_24") (pintype "passive"))
    )
    (net (code "392") (name "Net-(IC66-Pad1)") (class "Default")
      (node (ref "IC66") (pin "1") (pinfunction "1_1") (pintype "passive"))
      (node (ref "IC67") (pin "1") (pinfunction "1_1") (pintype "passive"))
      (node (ref "IC68") (pin "1") (pinfunction "1_1") (pintype "passive"))
      (node (ref "IC69") (pin "1") (pinfunction "1_1") (pintype "passive"))
    )
    (net (code "393") (name "Net-(IC66-Pad2)") (class "Default")
      (node (ref "IC66") (pin "2") (pinfunction "2_2") (pintype "passive"))
      (node (ref "IC67") (pin "2") (pinfunction "2_2") (pintype "passive"))
      (node (ref "IC68") (pin "2") (pinfunction "2_2") (pintype "passive"))
      (node (ref "IC69") (pin "2") (pinfunction "2_2") (pintype "passive"))
    )
    (net (code "394") (name "Net-(IC66-Pad3)") (class "Default")
      (node (ref "IC66") (pin "3") (pinfunction "3_3") (pintype "passive"))
      (node (ref "IC67") (pin "3") (pinfunction "3_3") (pintype "passive"))
      (node (ref "IC68") (pin "3") (pinfunction "3_3") (pintype "passive"))
      (node (ref "IC69") (pin "3") (pinfunction "3_3") (pintype "passive"))
    )
    (net (code "395") (name "Net-(IC66-Pad4)") (class "Default")
      (node (ref "IC66") (pin "4") (pinfunction "4_4") (pintype "passive"))
      (node (ref "IC67") (pin "4") (pinfunction "4_4") (pintype "passive"))
      (node (ref "IC68") (pin "4") (pinfunction "4_4") (pintype "passive"))
      (node (ref "IC69") (pin "4") (pinfunction "4_4") (pintype "passive"))
    )
    (net (code "396") (name "Net-(IC66-Pad5)") (class "Default")
      (node (ref "IC66") (pin "5") (pinfunction "5_5") (pintype "passive"))
      (node (ref "IC67") (pin "5") (pinfunction "5_5") (pintype "passive"))
      (node (ref "IC68") (pin "5") (pinfunction "5_5") (pintype "passive"))
      (node (ref "IC69") (pin "5") (pinfunction "5_5") (pintype "passive"))
    )
    (net (code "397") (name "Net-(IC66-Pad6)") (class "Default")
      (node (ref "IC66") (pin "6") (pinfunction "6_6") (pintype "passive"))
      (node (ref "IC67") (pin "6") (pinfunction "6_6") (pintype "passive"))
      (node (ref "IC68") (pin "6") (pinfunction "6_6") (pintype "passive"))
      (node (ref "IC69") (pin "6") (pinfunction "6_6") (pintype "passive"))
    )
    (net (code "398") (name "Net-(IC66-Pad7)") (class "Default")
      (node (ref "IC66") (pin "7") (pinfunction "7_7") (pintype "passive"))
      (node (ref "IC67") (pin "7") (pinfunction "7_7") (pintype "passive"))
      (node (ref "IC68") (pin "7") (pinfunction "7_7") (pintype "passive"))
      (node (ref "IC69") (pin "7") (pinfunction "7_7") (pintype "passive"))
    )
    (net (code "399") (name "Net-(IC66-Pad8)") (class "Default")
      (node (ref "IC66") (pin "8") (pinfunction "8_8") (pintype "passive"))
      (node (ref "IC67") (pin "8") (pinfunction "8_8") (pintype "passive"))
      (node (ref "IC68") (pin "8") (pinfunction "8_8") (pintype "passive"))
      (node (ref "IC69") (pin "8") (pinfunction "8_8") (pintype "passive"))
    )
    (net (code "400") (name "Net-(IC66-Pad9)") (class "Default")
      (node (ref "IC66") (pin "9") (pinfunction "9_9") (pintype "passive"))
      (node (ref "IC67") (pin "9") (pinfunction "9_9") (pintype "passive"))
      (node (ref "IC68") (pin "9") (pinfunction "9_9") (pintype "passive"))
      (node (ref "IC69") (pin "9") (pinfunction "9_9") (pintype "passive"))
    )
    (net (code "401") (name "Net-(IC66-Pad10)") (class "Default")
      (node (ref "IC66") (pin "10") (pinfunction "10_10") (pintype "passive"))
      (node (ref "IC67") (pin "10") (pinfunction "10_10") (pintype "passive"))
      (node (ref "IC68") (pin "10") (pinfunction "10_10") (pintype "passive"))
      (node (ref "IC69") (pin "10") (pinfunction "10_10") (pintype "passive"))
    )
    (net (code "402") (name "Net-(IC66-Pad11)") (class "Default")
      (node (ref "IC66") (pin "11") (pinfunction "11_11") (pintype "passive"))
      (node (ref "IC67") (pin "11") (pinfunction "11_11") (pintype "passive"))
      (node (ref "IC68") (pin "11") (pinfunction "11_11") (pintype "passive"))
      (node (ref "IC69") (pin "11") (pinfunction "11_11") (pintype "passive"))
    )
    (net (code "403") (name "Net-(IC66-Pad12)") (class "Default")
      (node (ref "IC66") (pin "12") (pinfunction "12_12") (pintype "passive"))
      (node (ref "IC67") (pin "12") (pinfunction "12_12") (pintype "passive"))
      (node (ref "IC68") (pin "12") (pinfunction "12_12") (pintype "passive"))
      (node (ref "IC69") (pin "12") (pinfunction "12_12") (pintype "passive"))
    )
    (net (code "404") (name "Net-(IC66-Pad13)") (class "Default")
      (node (ref "IC66") (pin "13") (pinfunction "13_13") (pintype "passive"))
      (node (ref "IC67") (pin "13") (pinfunction "13_13") (pintype "passive"))
      (node (ref "IC68") (pin "13") (pinfunction "13_13") (pintype "passive"))
      (node (ref "IC69") (pin "13") (pinfunction "13_13") (pintype "passive"))
    )
    (net (code "405") (name "Net-(IC66-Pad14)") (class "Default")
      (node (ref "IC66") (pin "14") (pinfunction "14_14") (pintype "passive"))
      (node (ref "IC67") (pin "14") (pinfunction "14_14") (pintype "passive"))
      (node (ref "IC68") (pin "14") (pinfunction "14_14") (pintype "passive"))
      (node (ref "IC69") (pin "14") (pinfunction "14_14") (pintype "passive"))
    )
    (net (code "406") (name "Net-(IC66-Pad15)") (class "Default")
      (node (ref "IC66") (pin "15") (pinfunction "15_15") (pintype "passive"))
      (node (ref "IC67") (pin "15") (pinfunction "15_15") (pintype "passive"))
      (node (ref "IC68") (pin "15") (pinfunction "15_15") (pintype "passive"))
      (node (ref "IC69") (pin "15") (pinfunction "15_15") (pintype "passive"))
    )
    (net (code "407") (name "Net-(IC66-Pad16)") (class "Default")
      (node (ref "IC66") (pin "16") (pinfunction "16_16") (pintype "passive"))
      (node (ref "IC67") (pin "16") (pinfunction "16_16") (pintype "passive"))
      (node (ref "IC68") (pin "16") (pinfunction "16_16") (pintype "passive"))
      (node (ref "IC69") (pin "16") (pinfunction "16_16") (pintype "passive"))
    )
    (net (code "408") (name "Net-(IC66-Pad17)") (class "Default")
      (node (ref "IC66") (pin "17") (pinfunction "17_17") (pintype "passive"))
      (node (ref "IC67") (pin "17") (pinfunction "17_17") (pintype "passive"))
      (node (ref "IC68") (pin "17") (pinfunction "17_17") (pintype "passive"))
      (node (ref "IC69") (pin "17") (pinfunction "17_17") (pintype "passive"))
    )
    (net (code "409") (name "Net-(IC66-Pad18)") (class "Default")
      (node (ref "IC66") (pin "18") (pinfunction "18_18") (pintype "passive"))
      (node (ref "IC67") (pin "18") (pinfunction "18_18") (pintype "passive"))
      (node (ref "IC68") (pin "18") (pinfunction "18_18") (pintype "passive"))
      (node (ref "IC69") (pin "18") (pinfunction "18_18") (pintype "passive"))
    )
    (net (code "410") (name "Net-(IC66-Pad19)") (class "Default")
      (node (ref "IC66") (pin "19") (pinfunction "19_19") (pintype "passive"))
      (node (ref "IC67") (pin "19") (pinfunction "19_19") (pintype "passive"))
      (node (ref "IC68") (pin "19") (pinfunction "19_19") (pintype "passive"))
      (node (ref "IC69") (pin "19") (pinfunction "19_19") (pintype "passive"))
    )
    (net (code "411") (name "Net-(IC66-Pad20)") (class "Default")
      (node (ref "IC66") (pin "20") (pinfunction "20_20") (pintype "passive"))
      (node (ref "IC67") (pin "20") (pinfunction "20_20") (pintype "passive"))
      (node (ref "IC68") (pin "20") (pinfunction "20_20") (pintype "passive"))
      (node (ref "IC69") (pin "20") (pinfunction "20_20") (pintype "passive"))
    )
    (net (code "412") (name "Net-(IC66-Pad21)") (class "Default")
      (node (ref "IC66") (pin "21") (pinfunction "21_21") (pintype "passive"))
      (node (ref "IC67") (pin "21") (pinfunction "21_21") (pintype "passive"))
      (node (ref "IC68") (pin "21") (pinfunction "21_21") (pintype "passive"))
      (node (ref "IC69") (pin "21") (pinfunction "21_21") (pintype "passive"))
    )
    (net (code "413") (name "Net-(IC66-Pad22)") (class "Default")
      (node (ref "IC66") (pin "22") (pinfunction "22_22") (pintype "passive"))
      (node (ref "IC67") (pin "22") (pinfunction "22_22") (pintype "passive"))
      (node (ref "IC68") (pin "22") (pinfunction "22_22") (pintype "passive"))
      (node (ref "IC69") (pin "22") (pinfunction "22_22") (pintype "passive"))
    )
    (net (code "414") (name "Net-(IC66-Pad23)") (class "Default")
      (node (ref "IC66") (pin "23") (pinfunction "23_23") (pintype "passive"))
      (node (ref "IC67") (pin "23") (pinfunction "23_23") (pintype "passive"))
      (node (ref "IC68") (pin "23") (pinfunction "23_23") (pintype "passive"))
      (node (ref "IC69") (pin "23") (pinfunction "23_23") (pintype "passive"))
    )
    (net (code "415") (name "Net-(IC66-Pad24)") (class "Default")
      (node (ref "IC66") (pin "24") (pinfunction "24_24") (pintype "passive"))
      (node (ref "IC67") (pin "24") (pinfunction "24_24") (pintype "passive"))
      (node (ref "IC68") (pin "24") (pinfunction "24_24") (pintype "passive"))
      (node (ref "IC69") (pin "24") (pinfunction "24_24") (pintype "passive"))
    )
    (net (code "416") (name "Net-(IC70-Pad1)") (class "Default")
      (node (ref "IC70") (pin "1") (pinfunction "1_1") (pintype "passive"))
      (node (ref "IC71") (pin "1") (pinfunction "1_1") (pintype "passive"))
      (node (ref "IC72") (pin "1") (pinfunction "1_1") (pintype "passive"))
      (node (ref "IC73") (pin "1") (pinfunction "1_1") (pintype "passive"))
    )
    (net (code "417") (name "Net-(IC70-Pad2)") (class "Default")
      (node (ref "IC70") (pin "2") (pinfunction "2_2") (pintype "passive"))
      (node (ref "IC71") (pin "2") (pinfunction "2_2") (pintype "passive"))
      (node (ref "IC72") (pin "2") (pinfunction "2_2") (pintype "passive"))
      (node (ref "IC73") (pin "2") (pinfunction "2_2") (pintype "passive"))
    )
    (net (code "418") (name "Net-(IC70-Pad3)") (class "Default")
      (node (ref "IC70") (pin "3") (pinfunction "3_3") (pintype "passive"))
      (node (ref "IC71") (pin "3") (pinfunction "3_3") (pintype "passive"))
      (node (ref "IC72") (pin "3") (pinfunction "3_3") (pintype "passive"))
      (node (ref "IC73") (pin "3") (pinfunction "3_3") (pintype "passive"))
    )
    (net (code "419") (name "Net-(IC70-Pad4)") (class "Default")
      (node (ref "IC70") (pin "4") (pinfunction "4_4") (pintype "passive"))
      (node (ref "IC71") (pin "4") (pinfunction "4_4") (pintype "passive"))
      (node (ref "IC72") (pin "4") (pinfunction "4_4") (pintype "passive"))
      (node (ref "IC73") (pin "4") (pinfunction "4_4") (pintype "passive"))
    )
    (net (code "420") (name "Net-(IC70-Pad5)") (class "Default")
      (node (ref "IC70") (pin "5") (pinfunction "5_5") (pintype "passive"))
      (node (ref "IC71") (pin "5") (pinfunction "5_5") (pintype "passive"))
      (node (ref "IC72") (pin "5") (pinfunction "5_5") (pintype "passive"))
      (node (ref "IC73") (pin "5") (pinfunction "5_5") (pintype "passive"))
    )
    (net (code "421") (name "Net-(IC70-Pad6)") (class "Default")
      (node (ref "IC70") (pin "6") (pinfunction "6_6") (pintype "passive"))
      (node (ref "IC71") (pin "6") (pinfunction "6_6") (pintype "passive"))
      (node (ref "IC72") (pin "6") (pinfunction "6_6") (pintype "passive"))
      (node (ref "IC73") (pin "6") (pinfunction "6_6") (pintype "passive"))
    )
    (net (code "422") (name "Net-(IC70-Pad7)") (class "Default")
      (node (ref "IC70") (pin "7") (pinfunction "7_7") (pintype "passive"))
      (node (ref "IC71") (pin "7") (pinfunction "7_7") (pintype "passive"))
      (node (ref "IC72") (pin "7") (pinfunction "7_7") (pintype "passive"))
      (node (ref "IC73") (pin "7") (pinfunction "7_7") (pintype "passive"))
    )
    (net (code "423") (name "Net-(IC70-Pad8)") (class "Default")
      (node (ref "IC70") (pin "8") (pinfunction "8_8") (pintype "passive"))
      (node (ref "IC71") (pin "8") (pinfunction "8_8") (pintype "passive"))
      (node (ref "IC72") (pin "8") (pinfunction "8_8") (pintype "passive"))
      (node (ref "IC73") (pin "8") (pinfunction "8_8") (pintype "passive"))
    )
    (net (code "424") (name "Net-(IC70-Pad9)") (class "Default")
      (node (ref "IC70") (pin "9") (pinfunction "9_9") (pintype "passive"))
      (node (ref "IC71") (pin "9") (pinfunction "9_9") (pintype "passive"))
      (node (ref "IC72") (pin "9") (pinfunction "9_9") (pintype "passive"))
      (node (ref "IC73") (pin "9") (pinfunction "9_9") (pintype "passive"))
    )
    (net (code "425") (name "Net-(IC70-Pad10)") (class "Default")
      (node (ref "IC70") (pin "10") (pinfunction "10_10") (pintype "passive"))
      (node (ref "IC71") (pin "10") (pinfunction "10_10") (pintype "passive"))
      (node (ref "IC72") (pin "10") (pinfunction "10_10") (pintype "passive"))
      (node (ref "IC73") (pin "10") (pinfunction "10_10") (pintype "passive"))
    )
    (net (code "426") (name "Net-(IC70-Pad11)") (class "Default")
      (node (ref "IC70") (pin "11") (pinfunction "11_11") (pintype "passive"))
      (node (ref "IC71") (pin "11") (pinfunction "11_11") (pintype "passive"))
      (node (ref "IC72") (pin "11") (pinfunction "11_11") (pintype "passive"))
      (node (ref "IC73") (pin "11") (pinfunction "11_11") (pintype "passive"))
    )
    (net (code "427") (name "Net-(IC70-Pad12)") (class "Default")
      (node (ref "IC70") (pin "12") (pinfunction "12_12") (pintype "passive"))
      (node (ref "IC71") (pin "12") (pinfunction "12_12") (pintype "passive"))
      (node (ref "IC72") (pin "12") (pinfunction "12_12") (pintype "passive"))
      (node (ref "IC73") (pin "12") (pinfunction "12_12") (pintype "passive"))
    )
    (net (code "428") (name "Net-(IC70-Pad13)") (class "Default")
      (node (ref "IC70") (pin "13") (pinfunction "13_13") (pintype "passive"))
      (node (ref "IC71") (pin "13") (pinfunction "13_13") (pintype "passive"))
      (node (ref "IC72") (pin "13") (pinfunction "13_13") (pintype "passive"))
      (node (ref "IC73") (pin "13") (pinfunction "13_13") (pintype "passive"))
    )
    (net (code "429") (name "Net-(IC70-Pad14)") (class "Default")
      (node (ref "IC70") (pin "14") (pinfunction "14_14") (pintype "passive"))
      (node (ref "IC71") (pin "14") (pinfunction "14_14") (pintype "passive"))
      (node (ref "IC72") (pin "14") (pinfunction "14_14") (pintype "passive"))
      (node (ref "IC73") (pin "14") (pinfunction "14_14") (pintype "passive"))
    )
    (net (code "430") (name "Net-(IC70-Pad15)") (class "Default")
      (node (ref "IC70") (pin "15") (pinfunction "15_15") (pintype "passive"))
      (node (ref "IC71") (pin "15") (pinfunction "15_15") (pintype "passive"))
      (node (ref "IC72") (pin "15") (pinfunction "15_15") (pintype "passive"))
      (node (ref "IC73") (pin "15") (pinfunction "15_15") (pintype "passive"))
    )
    (net (code "431") (name "Net-(IC70-Pad16)") (class "Default")
      (node (ref "IC70") (pin "16") (pinfunction "16_16") (pintype "passive"))
      (node (ref "IC71") (pin "16") (pinfunction "16_16") (pintype "passive"))
      (node (ref "IC72") (pin "16") (pinfunction "16_16") (pintype "passive"))
      (node (ref "IC73") (pin "16") (pinfunction "16_16") (pintype "passive"))
    )
    (net (code "432") (name "Net-(IC70-Pad17)") (class "Default")
      (node (ref "IC70") (pin "17") (pinfunction "17_17") (pintype "passive"))
      (node (ref "IC71") (pin "17") (pinfunction "17_17") (pintype "passive"))
      (node (ref "IC72") (pin "17") (pinfunction "17_17") (pintype "passive"))
      (node (ref "IC73") (pin "17") (pinfunction "17_17") (pintype "passive"))
    )
    (net (code "433") (name "Net-(IC70-Pad18)") (class "Default")
      (node (ref "IC70") (pin "18") (pinfunction "18_18") (pintype "passive"))
      (node (ref "IC71") (pin "18") (pinfunction "18_18") (pintype "passive"))
      (node (ref "IC72") (pin "18") (pinfunction "18_18") (pintype "passive"))
      (node (ref "IC73") (pin "18") (pinfunction "18_18") (pintype "passive"))
    )
    (net (code "434") (name "Net-(IC70-Pad19)") (class "Default")
      (node (ref "IC70") (pin "19") (pinfunction "19_19") (pintype "passive"))
      (node (ref "IC71") (pin "19") (pinfunction "19_19") (pintype "passive"))
      (node (ref "IC72") (pin "19") (pinfunction "19_19") (pintype "passive"))
      (node (ref "IC73") (pin "19") (pinfunction "19_19") (pintype "passive"))
    )
    (net (code "435") (name "Net-(IC70-Pad20)") (class "Default")
      (node (ref "IC70") (pin "20") (pinfunction "20_20") (pintype "passive"))
      (node (ref "IC71") (pin "20") (pinfunction "20_20") (pintype "passive"))
      (node (ref "IC72") (pin "20") (pinfunction "20_20") (pintype "passive"))
      (node (ref "IC73") (pin "20") (pinfunction "20_20") (pintype "passive"))
    )
    (net (code "436") (name "Net-(IC70-Pad21)") (class "Default")
      (node (ref "IC70") (pin "21") (pinfunction "21_21") (pintype "passive"))
      (node (ref "IC71") (pin "21") (pinfunction "21_21") (pintype "passive"))
      (node (ref "IC72") (pin "21") (pinfunction "21_21") (pintype "passive"))
      (node (ref "IC73") (pin "21") (pinfunction "21_21") (pintype "passive"))
    )
    (net (code "437") (name "Net-(IC70-Pad22)") (class "Default")
      (node (ref "IC70") (pin "22") (pinfunction "22_22") (pintype "passive"))
      (node (ref "IC71") (pin "22") (pinfunction "22_22") (pintype "passive"))
      (node (ref "IC72") (pin "22") (pinfunction "22_22") (pintype "passive"))
      (node (ref "IC73") (pin "22") (pinfunction "22_22") (pintype "passive"))
    )
    (net (code "438") (name "Net-(IC70-Pad23)") (class "Default")
      (node (ref "IC70") (pin "23") (pinfunction "23_23") (pintype "passive"))
      (node (ref "IC71") (pin "23") (pinfunction "23_23") (pintype "passive"))
      (node (ref "IC72") (pin "23") (pinfunction "23_23") (pintype "passive"))
      (node (ref "IC73") (pin "23") (pinfunction "23_23") (pintype "passive"))
    )
    (net (code "439") (name "Net-(IC70-Pad24)") (class "Default")
      (node (ref "IC70") (pin "24") (pinfunction "24_24") (pintype "passive"))
      (node (ref "IC71") (pin "24") (pinfunction "24_24") (pintype "passive"))
      (node (ref "IC72") (pin "24") (pinfunction "24_24") (pintype "passive"))
      (node (ref "IC73") (pin "24") (pinfunction "24_24") (pintype "passive"))
    )
    (net (code "440") (name "Net-(IC74-Pad1)") (class "Default")
      (node (ref "IC74") (pin "1") (pinfunction "1_1") (pintype "passive"))
      (node (ref "IC75") (pin "1") (pinfunction "1_1") (pintype "passive"))
      (node (ref "IC76") (pin "1") (pinfunction "1_1") (pintype "passive"))
      (node (ref "IC77") (pin "1") (pinfunction "1_1") (pintype "passive"))
    )
    (net (code "441") (name "Net-(IC74-Pad2)") (class "Default")
      (node (ref "IC74") (pin "2") (pinfunction "2_2") (pintype "passive"))
      (node (ref "IC75") (pin "2") (pinfunction "2_2") (pintype "passive"))
      (node (ref "IC76") (pin "2") (pinfunction "2_2") (pintype "passive"))
      (node (ref "IC77") (pin "2") (pinfunction "2_2") (pintype "passive"))
    )
    (net (code "442") (name "Net-(IC74-Pad3)") (class "Default")
      (node (ref "IC74") (pin "3") (pinfunction "3_3") (pintype "passive"))
      (node (ref "IC75") (pin "3") (pinfunction "3_3") (pintype "passive"))
      (node (ref "IC76") (pin "3") (pinfunction "3_3") (pintype "passive"))
      (node (ref "IC77") (pin "3") (pinfunction "3_3") (pintype "passive"))
    )
    (net (code "443") (name "Net-(IC74-Pad4)") (class "Default")
      (node (ref "IC74") (pin "4") (pinfunction "4_4") (pintype "passive"))
      (node (ref "IC75") (pin "4") (pinfunction "4_4") (pintype "passive"))
      (node (ref "IC76") (pin "4") (pinfunction "4_4") (pintype "passive"))
      (node (ref "IC77") (pin "4") (pinfunction "4_4") (pintype "passive"))
    )
    (net (code "444") (name "Net-(IC74-Pad5)") (class "Default")
      (node (ref "IC74") (pin "5") (pinfunction "5_5") (pintype "passive"))
      (node (ref "IC75") (pin "5") (pinfunction "5_5") (pintype "passive"))
      (node (ref "IC76") (pin "5") (pinfunction "5_5") (pintype "passive"))
      (node (ref "IC77") (pin "5") (pinfunction "5_5") (pintype "passive"))
    )
    (net (code "445") (name "Net-(IC74-Pad6)") (class "Default")
      (node (ref "IC74") (pin "6") (pinfunction "6_6") (pintype "passive"))
      (node (ref "IC75") (pin "6") (pinfunction "6_6") (pintype "passive"))
      (node (ref "IC76") (pin "6") (pinfunction "6_6") (pintype "passive"))
      (node (ref "IC77") (pin "6") (pinfunction "6_6") (pintype "passive"))
    )
    (net (code "446") (name "Net-(IC74-Pad7)") (class "Default")
      (node (ref "IC74") (pin "7") (pinfunction "7_7") (pintype "passive"))
      (node (ref "IC75") (pin "7") (pinfunction "7_7") (pintype "passive"))
      (node (ref "IC76") (pin "7") (pinfunction "7_7") (pintype "passive"))
      (node (ref "IC77") (pin "7") (pinfunction "7_7") (pintype "passive"))
    )
    (net (code "447") (name "Net-(IC74-Pad8)") (class "Default")
      (node (ref "IC74") (pin "8") (pinfunction "8_8") (pintype "passive"))
      (node (ref "IC75") (pin "8") (pinfunction "8_8") (pintype "passive"))
      (node (ref "IC76") (pin "8") (pinfunction "8_8") (pintype "passive"))
      (node (ref "IC77") (pin "8") (pinfunction "8_8") (pintype "passive"))
    )
    (net (code "448") (name "Net-(IC74-Pad9)") (class "Default")
      (node (ref "IC74") (pin "9") (pinfunction "9_9") (pintype "passive"))
      (node (ref "IC75") (pin "9") (pinfunction "9_9") (pintype "passive"))
      (node (ref "IC76") (pin "9") (pinfunction "9_9") (pintype "passive"))
      (node (ref "IC77") (pin "9") (pinfunction "9_9") (pintype "passive"))
    )
    (net (code "449") (name "Net-(IC74-Pad10)") (class "Default")
      (node (ref "IC74") (pin "10") (pinfunction "10_10") (pintype "passive"))
      (node (ref "IC75") (pin "10") (pinfunction "10_10") (pintype "passive"))
      (node (ref "IC76") (pin "10") (pinfunction "10_10") (pintype "passive"))
      (node (ref "IC77") (pin "10") (pinfunction "10_10") (pintype "passive"))
    )
    (net (code "450") (name "Net-(IC74-Pad11)") (class "Default")
      (node (ref "IC74") (pin "11") (pinfunction "11_11") (pintype "passive"))
      (node (ref "IC75") (pin "11") (pinfunction "11_11") (pintype "passive"))
      (node (ref "IC76") (pin "11") (pinfunction "11_11") (pintype "passive"))
      (node (ref "IC77") (pin "11") (pinfunction "11_11") (pintype "passive"))
    )
    (net (code "451") (name "Net-(IC74-Pad12)") (class "Default")
      (node (ref "IC74") (pin "12") (pinfunction "12_12") (pintype "passive"))
      (node (ref "IC75") (pin "12") (pinfunction "12_12") (pintype "passive"))
      (node (ref "IC76") (pin "12") (pinfunction "12_12") (pintype "passive"))
      (node (ref "IC77") (pin "12") (pinfunction "12_12") (pintype "passive"))
    )
    (net (code "452") (name "Net-(IC74-Pad13)") (class "Default")
      (node (ref "IC74") (pin "13") (pinfunction "13_13") (pintype "passive"))
      (node (ref "IC75") (pin "13") (pinfunction "13_13") (pintype "passive"))
      (node (ref "IC76") (pin "13") (pinfunction "13_13") (pintype "passive"))
      (node (ref "IC77") (pin "13") (pinfunction "13_13") (pintype "passive"))
    )
    (net (code "453") (name "Net-(IC74-Pad14)") (class "Default")
      (node (ref "IC74") (pin "14") (pinfunction "14_14") (pintype "passive"))
      (node (ref "IC75") (pin "14") (pinfunction "14_14") (pintype "passive"))
      (node (ref "IC76") (pin "14") (pinfunction "14_14") (pintype "passive"))
      (node (ref "IC77") (pin "14") (pinfunction "14_14") (pintype "passive"))
    )
    (net (code "454") (name "Net-(IC74-Pad15)") (class "Default")
      (node (ref "IC74") (pin "15") (pinfunction "15_15") (pintype "passive"))
      (node (ref "IC75") (pin "15") (pinfunction "15_15") (pintype "passive"))
      (node (ref "IC76") (pin "15") (pinfunction "15_15") (pintype "passive"))
      (node (ref "IC77") (pin "15") (pinfunction "15_15") (pintype "passive"))
    )
    (net (code "455") (name "Net-(IC74-Pad16)") (class "Default")
      (node (ref "IC74") (pin "16") (pinfunction "16_16") (pintype "passive"))
      (node (ref "IC75") (pin "16") (pinfunction "16_16") (pintype "passive"))
      (node (ref "IC76") (pin "16") (pinfunction "16_16") (pintype "passive"))
      (node (ref "IC77") (pin "16") (pinfunction "16_16") (pintype "passive"))
    )
    (net (code "456") (name "Net-(IC74-Pad17)") (class "Default")
      (node (ref "IC74") (pin "17") (pinfunction "17_17") (pintype "passive"))
      (node (ref "IC75") (pin "17") (pinfunction "17_17") (pintype "passive"))
      (node (ref "IC76") (pin "17") (pinfunction "17_17") (pintype "passive"))
      (node (ref "IC77") (pin "17") (pinfunction "17_17") (pintype "passive"))
    )
    (net (code "457") (name "Net-(IC74-Pad18)") (class "Default")
      (node (ref "IC74") (pin "18") (pinfunction "18_18") (pintype "passive"))
      (node (ref "IC75") (pin "18") (pinfunction "18_18") (pintype "passive"))
      (node (ref "IC76") (pin "18") (pinfunction "18_18") (pintype "passive"))
      (node (ref "IC77") (pin "18") (pinfunction "18_18") (pintype "passive"))
    )
    (net (code "458") (name "Net-(IC74-Pad19)") (class "Default")
      (node (ref "IC74") (pin "19") (pinfunction "19_19") (pintype "passive"))
      (node (ref "IC75") (pin "19") (pinfunction "19_19") (pintype "passive"))
      (node (ref "IC76") (pin "19") (pinfunction "19_19") (pintype "passive"))
      (node (ref "IC77") (pin "19") (pinfunction "19_19") (pintype "passive"))
    )
    (net (code "459") (name "Net-(IC74-Pad20)") (class "Default")
      (node (ref "IC74") (pin "20") (pinfunction "20_20") (pintype "passive"))
      (node (ref "IC75") (pin "20") (pinfunction "20_20") (pintype "passive"))
      (node (ref "IC76") (pin "20") (pinfunction "20_20") (pintype "passive"))
      (node (ref "IC77") (pin "20") (pinfunction "20_20") (pintype "passive"))
    )
    (net (code "460") (name "Net-(IC74-Pad21)") (class "Default")
      (node (ref "IC74") (pin "21") (pinfunction "21_21") (pintype "passive"))
      (node (ref "IC75") (pin "21") (pinfunction "21_21") (pintype "passive"))
      (node (ref "IC76") (pin "21") (pinfunction "21_21") (pintype "passive"))
      (node (ref "IC77") (pin "21") (pinfunction "21_21") (pintype "passive"))
    )
    (net (code "461") (name "Net-(IC74-Pad22)") (class "Default")
      (node (ref "IC74") (pin "22") (pinfunction "22_22") (pintype "passive"))
      (node (ref "IC75") (pin "22") (pinfunction "22_22") (pintype "passive"))
      (node (ref "IC76") (pin "22") (pinfunction "22_22") (pintype "passive"))
      (node (ref "IC77") (pin "22") (pinfunction "22_22") (pintype "passive"))
    )
    (net (code "462") (name "Net-(IC74-Pad23)") (class "Default")
      (node (ref "IC74") (pin "23") (pinfunction "23_23") (pintype "passive"))
      (node (ref "IC75") (pin "23") (pinfunction "23_23") (pintype "passive"))
      (node (ref "IC76") (pin "23") (pinfunction "23_23") (pintype "passive"))
      (node (ref "IC77") (pin "23") (pinfunction "23_23") (pintype "passive"))
    )
    (net (code "463") (name "Net-(IC74-Pad24)") (class "Default")
      (node (ref "IC74") (pin "24") (pinfunction "24_24") (pintype "passive"))
      (node (ref "IC75") (pin "24") (pinfunction "24_24") (pintype "passive"))
      (node (ref "IC76") (pin "24") (pinfunction "24_24") (pintype "passive"))
      (node (ref "IC77") (pin "24") (pinfunction "24_24") (pintype "passive"))
    )
    (net (code "464") (name "Net-(IC78-Pad1)") (class "Default")
      (node (ref "IC78") (pin "1") (pinfunction "1_1") (pintype "passive"))
      (node (ref "IC79") (pin "1") (pinfunction "1_1") (pintype "passive"))
      (node (ref "IC80") (pin "1") (pinfunction "1_1") (pintype "passive"))
      (node (ref "IC81") (pin "1") (pinfunction "1_1") (pintype "passive"))
    )
    (net (code "465") (name "Net-(IC78-Pad2)") (class "Default")
      (node (ref "IC78") (pin "2") (pinfunction "2_2") (pintype "passive"))
      (node (ref "IC79") (pin "2") (pinfunction "2_2") (pintype "passive"))
      (node (ref "IC80") (pin "2") (pinfunction "2_2") (pintype "passive"))
      (node (ref "IC81") (pin "2") (pinfunction "2_2") (pintype "passive"))
    )
    (net (code "466") (name "Net-(IC78-Pad3)") (class "Default")
      (node (ref "IC78") (pin "3") (pinfunction "3_3") (pintype "passive"))
      (node (ref "IC79") (pin "3") (pinfunction "3_3") (pintype "passive"))
      (node (ref "IC80") (pin "3") (pinfunction "3_3") (pintype "passive"))
      (node (ref "IC81") (pin "3") (pinfunction "3_3") (pintype "passive"))
    )
    (net (code "467") (name "Net-(IC78-Pad4)") (class "Default")
      (node (ref "IC78") (pin "4") (pinfunction "4_4") (pintype "passive"))
      (node (ref "IC79") (pin "4") (pinfunction "4_4") (pintype "passive"))
      (node (ref "IC80") (pin "4") (pinfunction "4_4") (pintype "passive"))
      (node (ref "IC81") (pin "4") (pinfunction "4_4") (pintype "passive"))
    )
    (net (code "468") (name "Net-(IC78-Pad5)") (class "Default")
      (node (ref "IC78") (pin "5") (pinfunction "5_5") (pintype "passive"))
      (node (ref "IC79") (pin "5") (pinfunction "5_5") (pintype "passive"))
      (node (ref "IC80") (pin "5") (pinfunction "5_5") (pintype "passive"))
      (node (ref "IC81") (pin "5") (pinfunction "5_5") (pintype "passive"))
    )
    (net (code "469") (name "Net-(IC78-Pad6)") (class "Default")
      (node (ref "IC78") (pin "6") (pinfunction "6_6") (pintype "passive"))
      (node (ref "IC79") (pin "6") (pinfunction "6_6") (pintype "passive"))
      (node (ref "IC80") (pin "6") (pinfunction "6_6") (pintype "passive"))
      (node (ref "IC81") (pin "6") (pinfunction "6_6") (pintype "passive"))
    )
    (net (code "470") (name "Net-(IC78-Pad7)") (class "Default")
      (node (ref "IC78") (pin "7") (pinfunction "7_7") (pintype "passive"))
      (node (ref "IC79") (pin "7") (pinfunction "7_7") (pintype "passive"))
      (node (ref "IC80") (pin "7") (pinfunction "7_7") (pintype "passive"))
      (node (ref "IC81") (pin "7") (pinfunction "7_7") (pintype "passive"))
    )
    (net (code "471") (name "Net-(IC78-Pad8)") (class "Default")
      (node (ref "IC78") (pin "8") (pinfunction "8_8") (pintype "passive"))
      (node (ref "IC79") (pin "8") (pinfunction "8_8") (pintype "passive"))
      (node (ref "IC80") (pin "8") (pinfunction "8_8") (pintype "passive"))
      (node (ref "IC81") (pin "8") (pinfunction "8_8") (pintype "passive"))
    )
    (net (code "472") (name "Net-(IC78-Pad9)") (class "Default")
      (node (ref "IC78") (pin "9") (pinfunction "9_9") (pintype "passive"))
      (node (ref "IC79") (pin "9") (pinfunction "9_9") (pintype "passive"))
      (node (ref "IC80") (pin "9") (pinfunction "9_9") (pintype "passive"))
      (node (ref "IC81") (pin "9") (pinfunction "9_9") (pintype "passive"))
    )
    (net (code "473") (name "Net-(IC78-Pad10)") (class "Default")
      (node (ref "IC78") (pin "10") (pinfunction "10_10") (pintype "passive"))
      (node (ref "IC79") (pin "10") (pinfunction "10_10") (pintype "passive"))
      (node (ref "IC80") (pin "10") (pinfunction "10_10") (pintype "passive"))
      (node (ref "IC81") (pin "10") (pinfunction "10_10") (pintype "passive"))
    )
    (net (code "474") (name "Net-(IC78-Pad11)") (class "Default")
      (node (ref "IC78") (pin "11") (pinfunction "11_11") (pintype "passive"))
      (node (ref "IC79") (pin "11") (pinfunction "11_11") (pintype "passive"))
      (node (ref "IC80") (pin "11") (pinfunction "11_11") (pintype "passive"))
      (node (ref "IC81") (pin "11") (pinfunction "11_11") (pintype "passive"))
    )
    (net (code "475") (name "Net-(IC78-Pad12)") (class "Default")
      (node (ref "IC78") (pin "12") (pinfunction "12_12") (pintype "passive"))
      (node (ref "IC79") (pin "12") (pinfunction "12_12") (pintype "passive"))
      (node (ref "IC80") (pin "12") (pinfunction "12_12") (pintype "passive"))
      (node (ref "IC81") (pin "12") (pinfunction "12_12") (pintype "passive"))
    )
    (net (code "476") (name "Net-(IC78-Pad13)") (class "Default")
      (node (ref "IC78") (pin "13") (pinfunction "13_13") (pintype "passive"))
      (node (ref "IC79") (pin "13") (pinfunction "13_13") (pintype "passive"))
      (node (ref "IC80") (pin "13") (pinfunction "13_13") (pintype "passive"))
      (node (ref "IC81") (pin "13") (pinfunction "13_13") (pintype "passive"))
    )
    (net (code "477") (name "Net-(IC78-Pad14)") (class "Default")
      (node (ref "IC78") (pin "14") (pinfunction "14_14") (pintype "passive"))
      (node (ref "IC79") (pin "14") (pinfunction "14_14") (pintype "passive"))
      (node (ref "IC80") (pin "14") (pinfunction "14_14") (pintype "passive"))
      (node (ref "IC81") (pin "14") (pinfunction "14_14") (pintype "passive"))
    )
    (net (code "478") (name "Net-(IC78-Pad15)") (class "Default")
      (node (ref "IC78") (pin "15") (pinfunction "15_15") (pintype "passive"))
      (node (ref "IC79") (pin "15") (pinfunction "15_15") (pintype "passive"))
      (node (ref "IC80") (pin "15") (pinfunction "15_15") (pintype "passive"))
      (node (ref "IC81") (pin "15") (pinfunction "15_15") (pintype "passive"))
    )
    (net (code "479") (name "Net-(IC78-Pad16)") (class "Default")
      (node (ref "IC78") (pin "16") (pinfunction "16_16") (pintype "passive"))
      (node (ref "IC79") (pin "16") (pinfunction "16_16") (pintype "passive"))
      (node (ref "IC80") (pin "16") (pinfunction "16_16") (pintype "passive"))
      (node (ref "IC81") (pin "16") (pinfunction "16_16") (pintype "passive"))
    )
    (net (code "480") (name "Net-(IC78-Pad17)") (class "Default")
      (node (ref "IC78") (pin "17") (pinfunction "17_17") (pintype "passive"))
      (node (ref "IC79") (pin "17") (pinfunction "17_17") (pintype "passive"))
      (node (ref "IC80") (pin "17") (pinfunction "17_17") (pintype "passive"))
      (node (ref "IC81") (pin "17") (pinfunction "17_17") (pintype "passive"))
    )
    (net (code "481") (name "Net-(IC78-Pad18)") (class "Default")
      (node (ref "IC78") (pin "18") (pinfunction "18_18") (pintype "passive"))
      (node (ref "IC79") (pin "18") (pinfunction "18_18") (pintype "passive"))
      (node (ref "IC80") (pin "18") (pinfunction "18_18") (pintype "passive"))
      (node (ref "IC81") (pin "18") (pinfunction "18_18") (pintype "passive"))
    )
    (net (code "482") (name "Net-(IC78-Pad19)") (class "Default")
      (node (ref "IC78") (pin "19") (pinfunction "19_19") (pintype "passive"))
      (node (ref "IC79") (pin "19") (pinfunction "19_19") (pintype "passive"))
      (node (ref "IC80") (pin "19") (pinfunction "19_19") (pintype "passive"))
      (node (ref "IC81") (pin "19") (pinfunction "19_19") (pintype "passive"))
    )
    (net (code "483") (name "Net-(IC78-Pad20)") (class "Default")
      (node (ref "IC78") (pin "20") (pinfunction "20_20") (pintype "passive"))
      (node (ref "IC79") (pin "20") (pinfunction "20_20") (pintype "passive"))
      (node (ref "IC80") (pin "20") (pinfunction "20_20") (pintype "passive"))
      (node (ref "IC81") (pin "20") (pinfunction "20_20") (pintype "passive"))
    )
    (net (code "484") (name "Net-(IC78-Pad21)") (class "Default")
      (node (ref "IC78") (pin "21") (pinfunction "21_21") (pintype "passive"))
      (node (ref "IC79") (pin "21") (pinfunction "21_21") (pintype "passive"))
      (node (ref "IC80") (pin "21") (pinfunction "21_21") (pintype "passive"))
      (node (ref "IC81") (pin "21") (pinfunction "21_21") (pintype "passive"))
    )
    (net (code "485") (name "Net-(IC78-Pad22)") (class "Default")
      (node (ref "IC78") (pin "22") (pinfunction "22_22") (pintype "passive"))
      (node (ref "IC79") (pin "22") (pinfunction "22_22") (pintype "passive"))
      (node (ref "IC80") (pin "22") (pinfunction "22_22") (pintype "passive"))
      (node (ref "IC81") (pin "22") (pinfunction "22_22") (pintype "passive"))
    )
    (net (code "486") (name "Net-(IC78-Pad23)") (class "Default")
      (node (ref "IC78") (pin "23") (pinfunction "23_23") (pintype "passive"))
      (node (ref "IC79") (pin "23") (pinfunction "23_23") (pintype "passive"))
      (node (ref "IC80") (pin "23") (pinfunction "23_23") (pintype "passive"))
      (node (ref "IC81") (pin "23") (pinfunction "23_23") (pintype "passive"))
    )
    (net (code "487") (name "Net-(IC78-Pad24)") (class "Default")
      (node (ref "IC78") (pin "24") (pinfunction "24_24") (pintype "passive"))
      (node (ref "IC79") (pin "24") (pinfunction "24_24") (pintype "passive"))
      (node (ref "IC80") (pin "24") (pinfunction "24_24") (pintype "passive"))
      (node (ref "IC81") (pin "24") (pinfunction "24_24") (pintype "passive"))
    )
    (net (code "488") (name "Net-(IC82-Pad1)") (class "Default")
      (node (ref "IC82") (pin "1") (pinfunction "1_1") (pintype "passive"))
      (node (ref "IC83") (pin "1") (pinfunction "1_1") (pintype "passive"))
      (node (ref "IC84") (pin "1") (pinfunction "1_1") (pintype "passive"))
      (node (ref "IC85") (pin "1") (pinfunction "1_1") (pintype "passive"))
    )
    (net (code "489") (name "Net-(IC82-Pad2)") (class "Default")
      (node (ref "IC82") (pin "2") (pinfunction "2_2") (pintype "passive"))
      (node (ref "IC83") (pin "2") (pinfunction "2_2") (pintype "passive"))
      (node (ref "IC84") (pin "2") (pinfunction "2_2") (pintype "passive"))
      (node (ref "IC85") (pin "2") (pinfunction "2_2") (pintype "passive"))
    )
    (net (code "490") (name "Net-(IC82-Pad3)") (class "Default")
      (node (ref "IC82") (pin "3") (pinfunction "3_3") (pintype "passive"))
      (node (ref "IC83") (pin "3") (pinfunction "3_3") (pintype "passive"))
      (node (ref "IC84") (pin "3") (pinfunction "3_3") (pintype "passive"))
      (node (ref "IC85") (pin "3") (pinfunction "3_3") (pintype "passive"))
    )
    (net (code "491") (name "Net-(IC82-Pad4)") (class "Default")
      (node (ref "IC82") (pin "4") (pinfunction "4_4") (pintype "passive"))
      (node (ref "IC83") (pin "4") (pinfunction "4_4") (pintype "passive"))
      (node (ref "IC84") (pin "4") (pinfunction "4_4") (pintype "passive"))
      (node (ref "IC85") (pin "4") (pinfunction "4_4") (pintype "passive"))
    )
    (net (code "492") (name "Net-(IC82-Pad5)") (class "Default")
      (node (ref "IC82") (pin "5") (pinfunction "5_5") (pintype "passive"))
      (node (ref "IC83") (pin "5") (pinfunction "5_5") (pintype "passive"))
      (node (ref "IC84") (pin "5") (pinfunction "5_5") (pintype "passive"))
      (node (ref "IC85") (pin "5") (pinfunction "5_5") (pintype "passive"))
    )
    (net (code "493") (name "Net-(IC82-Pad6)") (class "Default")
      (node (ref "IC82") (pin "6") (pinfunction "6_6") (pintype "passive"))
      (node (ref "IC83") (pin "6") (pinfunction "6_6") (pintype "passive"))
      (node (ref "IC84") (pin "6") (pinfunction "6_6") (pintype "passive"))
      (node (ref "IC85") (pin "6") (pinfunction "6_6") (pintype "passive"))
    )
    (net (code "494") (name "Net-(IC82-Pad7)") (class "Default")
      (node (ref "IC82") (pin "7") (pinfunction "7_7") (pintype "passive"))
      (node (ref "IC83") (pin "7") (pinfunction "7_7") (pintype "passive"))
      (node (ref "IC84") (pin "7") (pinfunction "7_7") (pintype "passive"))
      (node (ref "IC85") (pin "7") (pinfunction "7_7") (pintype "passive"))
    )
    (net (code "495") (name "Net-(IC82-Pad8)") (class "Default")
      (node (ref "IC82") (pin "8") (pinfunction "8_8") (pintype "passive"))
      (node (ref "IC83") (pin "8") (pinfunction "8_8") (pintype "passive"))
      (node (ref "IC84") (pin "8") (pinfunction "8_8") (pintype "passive"))
      (node (ref "IC85") (pin "8") (pinfunction "8_8") (pintype "passive"))
    )
    (net (code "496") (name "Net-(IC82-Pad9)") (class "Default")
      (node (ref "IC82") (pin "9") (pinfunction "9_9") (pintype "passive"))
      (node (ref "IC83") (pin "9") (pinfunction "9_9") (pintype "passive"))
      (node (ref "IC84") (pin "9") (pinfunction "9_9") (pintype "passive"))
      (node (ref "IC85") (pin "9") (pinfunction "9_9") (pintype "passive"))
    )
    (net (code "497") (name "Net-(IC82-Pad10)") (class "Default")
      (node (ref "IC82") (pin "10") (pinfunction "10_10") (pintype "passive"))
      (node (ref "IC83") (pin "10") (pinfunction "10_10") (pintype "passive"))
      (node (ref "IC84") (pin "10") (pinfunction "10_10") (pintype "passive"))
      (node (ref "IC85") (pin "10") (pinfunction "10_10") (pintype "passive"))
    )
    (net (code "498") (name "Net-(IC82-Pad11)") (class "Default")
      (node (ref "IC82") (pin "11") (pinfunction "11_11") (pintype "passive"))
      (node (ref "IC83") (pin "11") (pinfunction "11_11") (pintype "passive"))
      (node (ref "IC84") (pin "11") (pinfunction "11_11") (pintype "passive"))
      (node (ref "IC85") (pin "11") (pinfunction "11_11") (pintype "passive"))
    )
    (net (code "499") (name "Net-(IC82-Pad12)") (class "Default")
      (node (ref "IC82") (pin "12") (pinfunction "12_12") (pintype "passive"))
      (node (ref "IC83") (pin "12") (pinfunction "12_12") (pintype "passive"))
      (node (ref "IC84") (pin "12") (pinfunction "12_12") (pintype "passive"))
      (node (ref "IC85") (pin "12") (pinfunction "12_12") (pintype "passive"))
    )
    (net (code "500") (name "Net-(IC82-Pad13)") (class "Default")
      (node (ref "IC82") (pin "13") (pinfunction "13_13") (pintype "passive"))
      (node (ref "IC83") (pin "13") (pinfunction "13_13") (pintype "passive"))
      (node (ref "IC84") (pin "13") (pinfunction "13_13") (pintype "passive"))
      (node (ref "IC85") (pin "13") (pinfunction "13_13") (pintype "passive"))
    )
    (net (code "501") (name "Net-(IC82-Pad14)") (class "Default")
      (node (ref "IC82") (pin "14") (pinfunction "14_14") (pintype "passive"))
      (node (ref "IC83") (pin "14") (pinfunction "14_14") (pintype "passive"))
      (node (ref "IC84") (pin "14") (pinfunction "14_14") (pintype "passive"))
      (node (ref "IC85") (pin "14") (pinfunction "14_14") (pintype "passive"))
    )
    (net (code "502") (name "Net-(IC82-Pad15)") (class "Default")
      (node (ref "IC82") (pin "15") (pinfunction "15_15") (pintype "passive"))
      (node (ref "IC83") (pin "15") (pinfunction "15_15") (pintype "passive"))
      (node (ref "IC84") (pin "15") (pinfunction "15_15") (pintype "passive"))
      (node (ref "IC85") (pin "15") (pinfunction "15_15") (pintype "passive"))
    )
    (net (code "503") (name "Net-(IC82-Pad16)") (class "Default")
      (node (ref "IC82") (pin "16") (pinfunction "16_16") (pintype "passive"))
      (node (ref "IC83") (pin "16") (pinfunction "16_16") (pintype "passive"))
      (node (ref "IC84") (pin "16") (pinfunction "16_16") (pintype "passive"))
      (node (ref "IC85") (pin "16") (pinfunction "16_16") (pintype "passive"))
    )
    (net (code "504") (name "Net-(IC82-Pad17)") (class "Default")
      (node (ref "IC82") (pin "17") (pinfunction "17_17") (pintype "passive"))
      (node (ref "IC83") (pin "17") (pinfunction "17_17") (pintype "passive"))
      (node (ref "IC84") (pin "17") (pinfunction "17_17") (pintype "passive"))
      (node (ref "IC85") (pin "17") (pinfunction "17_17") (pintype "passive"))
    )
    (net (code "505") (name "Net-(IC82-Pad18)") (class "Default")
      (node (ref "IC82") (pin "18") (pinfunction "18_18") (pintype "passive"))
      (node (ref "IC83") (pin "18") (pinfunction "18_18") (pintype "passive"))
      (node (ref "IC84") (pin "18") (pinfunction "18_18") (pintype "passive"))
      (node (ref "IC85") (pin "18") (pinfunction "18_18") (pintype "passive"))
    )
    (net (code "506") (name "Net-(IC82-Pad19)") (class "Default")
      (node (ref "IC82") (pin "19") (pinfunction "19_19") (pintype "passive"))
      (node (ref "IC83") (pin "19") (pinfunction "19_19") (pintype "passive"))
      (node (ref "IC84") (pin "19") (pinfunction "19_19") (pintype "passive"))
      (node (ref "IC85") (pin "19") (pinfunction "19_19") (pintype "passive"))
    )
    (net (code "507") (name "Net-(IC82-Pad20)") (class "Default")
      (node (ref "IC82") (pin "20") (pinfunction "20_20") (pintype "passive"))
      (node (ref "IC83") (pin "20") (pinfunction "20_20") (pintype "passive"))
      (node (ref "IC84") (pin "20") (pinfunction "20_20") (pintype "passive"))
      (node (ref "IC85") (pin "20") (pinfunction "20_20") (pintype "passive"))
    )
    (net (code "508") (name "Net-(IC82-Pad21)") (class "Default")
      (node (ref "IC82") (pin "21") (pinfunction "21_21") (pintype "passive"))
      (node (ref "IC83") (pin "21") (pinfunction "21_21") (pintype "passive"))
      (node (ref "IC84") (pin "21") (pinfunction "21_21") (pintype "passive"))
      (node (ref "IC85") (pin "21") (pinfunction "21_21") (pintype "passive"))
    )
    (net (code "509") (name "Net-(IC82-Pad22)") (class "Default")
      (node (ref "IC82") (pin "22") (pinfunction "22_22") (pintype "passive"))
      (node (ref "IC83") (pin "22") (pinfunction "22_22") (pintype "passive"))
      (node (ref "IC84") (pin "22") (pinfunction "22_22") (pintype "passive"))
      (node (ref "IC85") (pin "22") (pinfunction "22_22") (pintype "passive"))
    )
    (net (code "510") (name "Net-(IC82-Pad23)") (class "Default")
      (node (ref "IC82") (pin "23") (pinfunction "23_23") (pintype "passive"))
      (node (ref "IC83") (pin "23") (pinfunction "23_23") (pintype "passive"))
      (node (ref "IC84") (pin "23") (pinfunction "23_23") (pintype "passive"))
      (node (ref "IC85") (pin "23") (pinfunction "23_23") (pintype "passive"))
    )
    (net (code "511") (name "Net-(IC82-Pad24)") (class "Default")
      (node (ref "IC82") (pin "24") (pinfunction "24_24") (pintype "passive"))
      (node (ref "IC83") (pin "24") (pinfunction "24_24") (pintype "passive"))
      (node (ref "IC84") (pin "24") (pinfunction "24_24") (pintype "passive"))
      (node (ref "IC85") (pin "24") (pinfunction "24_24") (pintype "passive"))
    )
    (net (code "512") (name "Net-(IC86-Pad1)") (class "Default")
      (node (ref "IC86") (pin "1") (pinfunction "1_1") (pintype "passive"))
      (node (ref "IC87") (pin "1") (pinfunction "1_1") (pintype "passive"))
      (node (ref "IC88") (pin "1") (pinfunction "1_1") (pintype "passive"))
      (node (ref "IC89") (pin "1") (pinfunction "1_1") (pintype "passive"))
    )
    (net (code "513") (name "Net-(IC86-Pad2)") (class "Default")
      (node (ref "IC86") (pin "2") (pinfunction "2_2") (pintype "passive"))
      (node (ref "IC87") (pin "2") (pinfunction "2_2") (pintype "passive"))
      (node (ref "IC88") (pin "2") (pinfunction "2_2") (pintype "passive"))
      (node (ref "IC89") (pin "2") (pinfunction "2_2") (pintype "passive"))
    )
    (net (code "514") (name "Net-(IC86-Pad3)") (class "Default")
      (node (ref "IC86") (pin "3") (pinfunction "3_3") (pintype "passive"))
      (node (ref "IC87") (pin "3") (pinfunction "3_3") (pintype "passive"))
      (node (ref "IC88") (pin "3") (pinfunction "3_3") (pintype "passive"))
      (node (ref "IC89") (pin "3") (pinfunction "3_3") (pintype "passive"))
    )
    (net (code "515") (name "Net-(IC86-Pad4)") (class "Default")
      (node (ref "IC86") (pin "4") (pinfunction "4_4") (pintype "passive"))
      (node (ref "IC87") (pin "4") (pinfunction "4_4") (pintype "passive"))
      (node (ref "IC88") (pin "4") (pinfunction "4_4") (pintype "passive"))
      (node (ref "IC89") (pin "4") (pinfunction "4_4") (pintype "passive"))
    )
    (net (code "516") (name "Net-(IC86-Pad5)") (class "Default")
      (node (ref "IC86") (pin "5") (pinfunction "5_5") (pintype "passive"))
      (node (ref "IC87") (pin "5") (pinfunction "5_5") (pintype "passive"))
      (node (ref "IC88") (pin "5") (pinfunction "5_5") (pintype "passive"))
      (node (ref "IC89") (pin "5") (pinfunction "5_5") (pintype "passive"))
    )
    (net (code "517") (name "Net-(IC86-Pad6)") (class "Default")
      (node (ref "IC86") (pin "6") (pinfunction "6_6") (pintype "passive"))
      (node (ref "IC87") (pin "6") (pinfunction "6_6") (pintype "passive"))
      (node (ref "IC88") (pin "6") (pinfunction "6_6") (pintype "passive"))
      (node (ref "IC89") (pin "6") (pinfunction "6_6") (pintype "passive"))
    )
    (net (code "518") (name "Net-(IC86-Pad7)") (class "Default")
      (node (ref "IC86") (pin "7") (pinfunction "7_7") (pintype "passive"))
      (node (ref "IC87") (pin "7") (pinfunction "7_7") (pintype "passive"))
      (node (ref "IC88") (pin "7") (pinfunction "7_7") (pintype "passive"))
      (node (ref "IC89") (pin "7") (pinfunction "7_7") (pintype "passive"))
    )
    (net (code "519") (name "Net-(IC86-Pad8)") (class "Default")
      (node (ref "IC86") (pin "8") (pinfunction "8_8") (pintype "passive"))
      (node (ref "IC87") (pin "8") (pinfunction "8_8") (pintype "passive"))
      (node (ref "IC88") (pin "8") (pinfunction "8_8") (pintype "passive"))
      (node (ref "IC89") (pin "8") (pinfunction "8_8") (pintype "passive"))
    )
    (net (code "520") (name "Net-(IC86-Pad9)") (class "Default")
      (node (ref "IC86") (pin "9") (pinfunction "9_9") (pintype "passive"))
      (node (ref "IC87") (pin "9") (pinfunction "9_9") (pintype "passive"))
      (node (ref "IC88") (pin "9") (pinfunction "9_9") (pintype "passive"))
      (node (ref "IC89") (pin "9") (pinfunction "9_9") (pintype "passive"))
    )
    (net (code "521") (name "Net-(IC86-Pad10)") (class "Default")
      (node (ref "IC86") (pin "10") (pinfunction "10_10") (pintype "passive"))
      (node (ref "IC87") (pin "10") (pinfunction "10_10") (pintype "passive"))
      (node (ref "IC88") (pin "10") (pinfunction "10_10") (pintype "passive"))
      (node (ref "IC89") (pin "10") (pinfunction "10_10") (pintype "passive"))
    )
    (net (code "522") (name "Net-(IC86-Pad11)") (class "Default")
      (node (ref "IC86") (pin "11") (pinfunction "11_11") (pintype "passive"))
      (node (ref "IC87") (pin "11") (pinfunction "11_11") (pintype "passive"))
      (node (ref "IC88") (pin "11") (pinfunction "11_11") (pintype "passive"))
      (node (ref "IC89") (pin "11") (pinfunction "11_11") (pintype "passive"))
    )
    (net (code "523") (name "Net-(IC86-Pad12)") (class "Default")
      (node (ref "IC86") (pin "12") (pinfunction "12_12") (pintype "passive"))
      (node (ref "IC87") (pin "12") (pinfunction "12_12") (pintype "passive"))
      (node (ref "IC88") (pin "12") (pinfunction "12_12") (pintype "passive"))
      (node (ref "IC89") (pin "12") (pinfunction "12_12") (pintype "passive"))
    )
    (net (code "524") (name "Net-(IC86-Pad13)") (class "Default")
      (node (ref "IC86") (pin "13") (pinfunction "13_13") (pintype "passive"))
      (node (ref "IC87") (pin "13") (pinfunction "13_13") (pintype "passive"))
      (node (ref "IC88") (pin "13") (pinfunction "13_13") (pintype "passive"))
      (node (ref "IC89") (pin "13") (pinfunction "13_13") (pintype "passive"))
    )
    (net (code "525") (name "Net-(IC86-Pad14)") (class "Default")
      (node (ref "IC86") (pin "14") (pinfunction "14_14") (pintype "passive"))
      (node (ref "IC87") (pin "14") (pinfunction "14_14") (pintype "passive"))
      (node (ref "IC88") (pin "14") (pinfunction "14_14") (pintype "passive"))
      (node (ref "IC89") (pin "14") (pinfunction "14_14") (pintype "passive"))
    )
    (net (code "526") (name "Net-(IC86-Pad15)") (class "Default")
      (node (ref "IC86") (pin "15") (pinfunction "15_15") (pintype "passive"))
      (node (ref "IC87") (pin "15") (pinfunction "15_15") (pintype "passive"))
      (node (ref "IC88") (pin "15") (pinfunction "15_15") (pintype "passive"))
      (node (ref "IC89") (pin "15") (pinfunction "15_15") (pintype "passive"))
    )
    (net (code "527") (name "Net-(IC86-Pad16)") (class "Default")
      (node (ref "IC86") (pin "16") (pinfunction "16_16") (pintype "passive"))
      (node (ref "IC87") (pin "16") (pinfunction "16_16") (pintype "passive"))
      (node (ref "IC88") (pin "16") (pinfunction "16_16") (pintype "passive"))
      (node (ref "IC89") (pin "16") (pinfunction "16_16") (pintype "passive"))
    )
    (net (code "528") (name "Net-(IC86-Pad17)") (class "Default")
      (node (ref "IC86") (pin "17") (pinfunction "17_17") (pintype "passive"))
      (node (ref "IC87") (pin "17") (pinfunction "17_17") (pintype "passive"))
      (node (ref "IC88") (pin "17") (pinfunction "17_17") (pintype "passive"))
      (node (ref "IC89") (pin "17") (pinfunction "17_17") (pintype "passive"))
    )
    (net (code "529") (name "Net-(IC86-Pad18)") (class "Default")
      (node (ref "IC86") (pin "18") (pinfunction "18_18") (pintype "passive"))
      (node (ref "IC87") (pin "18") (pinfunction "18_18") (pintype "passive"))
      (node (ref "IC88") (pin "18") (pinfunction "18_18") (pintype "passive"))
      (node (ref "IC89") (pin "18") (pinfunction "18_18") (pintype "passive"))
    )
    (net (code "530") (name "Net-(IC86-Pad19)") (class "Default")
      (node (ref "IC86") (pin "19") (pinfunction "19_19") (pintype "passive"))
      (node (ref "IC87") (pin "19") (pinfunction "19_19") (pintype "passive"))
      (node (ref "IC88") (pin "19") (pinfunction "19_19") (pintype "passive"))
      (node (ref "IC89") (pin "19") (pinfunction "19_19") (pintype "passive"))
    )
    (net (code "531") (name "Net-(IC86-Pad20)") (class "Default")
      (node (ref "IC86") (pin "20") (pinfunction "20_20") (pintype "passive"))
      (node (ref "IC87") (pin "20") (pinfunction "20_20") (pintype "passive"))
      (node (ref "IC88") (pin "20") (pinfunction "20_20") (pintype "passive"))
      (node (ref "IC89") (pin "20") (pinfunction "20_20") (pintype "passive"))
    )
    (net (code "532") (name "Net-(IC86-Pad21)") (class "Default")
      (node (ref "IC86") (pin "21") (pinfunction "21_21") (pintype "passive"))
      (node (ref "IC87") (pin "21") (pinfunction "21_21") (pintype "passive"))
      (node (ref "IC88") (pin "21") (pinfunction "21_21") (pintype "passive"))
      (node (ref "IC89") (pin "21") (pinfunction "21_21") (pintype "passive"))
    )
    (net (code "533") (name "Net-(IC86-Pad22)") (class "Default")
      (node (ref "IC86") (pin "22") (pinfunction "22_22") (pintype "passive"))
      (node (ref "IC87") (pin "22") (pinfunction "22_22") (pintype "passive"))
      (node (ref "IC88") (pin "22") (pinfunction "22_22") (pintype "passive"))
      (node (ref "IC89") (pin "22") (pinfunction "22_22") (pintype "passive"))
    )
    (net (code "534") (name "Net-(IC86-Pad23)") (class "Default")
      (node (ref "IC86") (pin "23") (pinfunction "23_23") (pintype "passive"))
      (node (ref "IC87") (pin "23") (pinfunction "23_23") (pintype "passive"))
      (node (ref "IC88") (pin "23") (pinfunction "23_23") (pintype "passive"))
      (node (ref "IC89") (pin "23") (pinfunction "23_23") (pintype "passive"))
    )
    (net (code "535") (name "Net-(IC86-Pad24)") (class "Default")
      (node (ref "IC86") (pin "24") (pinfunction "24_24") (pintype "passive"))
      (node (ref "IC87") (pin "24") (pinfunction "24_24") (pintype "passive"))
      (node (ref "IC88") (pin "24") (pinfunction "24_24") (pintype "passive"))
      (node (ref "IC89") (pin "24") (pinfunction "24_24") (pintype "passive"))
    )
    (net (code "536") (name "Net-(IC90-Pad1)") (class "Default")
      (node (ref "IC90") (pin "1") (pinfunction "1_1") (pintype "passive"))
      (node (ref "IC91") (pin "1") (pinfunction "1_1") (pintype "passive"))
      (node (ref "IC92") (pin "1") (pinfunction "1_1") (pintype "passive"))
      (node (ref "IC93") (pin "1") (pinfunction "1_1") (pintype "passive"))
    )
    (net (code "537") (name "Net-(IC90-Pad2)") (class "Default")
      (node (ref "IC90") (pin "2") (pinfunction "2_2") (pintype "passive"))
      (node (ref "IC91") (pin "2") (pinfunction "2_2") (pintype "passive"))
      (node (ref "IC92") (pin "2") (pinfunction "2_2") (pintype "passive"))
      (node (ref "IC93") (pin "2") (pinfunction "2_2") (pintype "passive"))
    )
    (net (code "538") (name "Net-(IC90-Pad3)") (class "Default")
      (node (ref "IC90") (pin "3") (pinfunction "3_3") (pintype "passive"))
      (node (ref "IC91") (pin "3") (pinfunction "3_3") (pintype "passive"))
      (node (ref "IC92") (pin "3") (pinfunction "3_3") (pintype "passive"))
      (node (ref "IC93") (pin "3") (pinfunction "3_3") (pintype "passive"))
    )
    (net (code "539") (name "Net-(IC90-Pad4)") (class "Default")
      (node (ref "IC90") (pin "4") (pinfunction "4_4") (pintype "passive"))
      (node (ref "IC91") (pin "4") (pinfunction "4_4") (pintype "passive"))
      (node (ref "IC92") (pin "4") (pinfunction "4_4") (pintype "passive"))
      (node (ref "IC93") (pin "4") (pinfunction "4_4") (pintype "passive"))
    )
    (net (code "540") (name "Net-(IC90-Pad5)") (class "Default")
      (node (ref "IC90") (pin "5") (pinfunction "5_5") (pintype "passive"))
      (node (ref "IC91") (pin "5") (pinfunction "5_5") (pintype "passive"))
      (node (ref "IC92") (pin "5") (pinfunction "5_5") (pintype "passive"))
      (node (ref "IC93") (pin "5") (pinfunction "5_5") (pintype "passive"))
    )
    (net (code "541") (name "Net-(IC90-Pad6)") (class "Default")
      (node (ref "IC90") (pin "6") (pinfunction "6_6") (pintype "passive"))
      (node (ref "IC91") (pin "6") (pinfunction "6_6") (pintype "passive"))
      (node (ref "IC92") (pin "6") (pinfunction "6_6") (pintype "passive"))
      (node (ref "IC93") (pin "6") (pinfunction "6_6") (pintype "passive"))
    )
    (net (code "542") (name "Net-(IC90-Pad7)") (class "Default")
      (node (ref "IC90") (pin "7") (pinfunction "7_7") (pintype "passive"))
      (node (ref "IC91") (pin "7") (pinfunction "7_7") (pintype "passive"))
      (node (ref "IC92") (pin "7") (pinfunction "7_7") (pintype "passive"))
      (node (ref "IC93") (pin "7") (pinfunction "7_7") (pintype "passive"))
    )
    (net (code "543") (name "Net-(IC90-Pad8)") (class "Default")
      (node (ref "IC90") (pin "8") (pinfunction "8_8") (pintype "passive"))
      (node (ref "IC91") (pin "8") (pinfunction "8_8") (pintype "passive"))
      (node (ref "IC92") (pin "8") (pinfunction "8_8") (pintype "passive"))
      (node (ref "IC93") (pin "8") (pinfunction "8_8") (pintype "passive"))
    )
    (net (code "544") (name "Net-(IC90-Pad9)") (class "Default")
      (node (ref "IC90") (pin "9") (pinfunction "9_9") (pintype "passive"))
      (node (ref "IC91") (pin "9") (pinfunction "9_9") (pintype "passive"))
      (node (ref "IC92") (pin "9") (pinfunction "9_9") (pintype "passive"))
      (node (ref "IC93") (pin "9") (pinfunction "9_9") (pintype "passive"))
    )
    (net (code "545") (name "Net-(IC90-Pad10)") (class "Default")
      (node (ref "IC90") (pin "10") (pinfunction "10_10") (pintype "passive"))
      (node (ref "IC91") (pin "10") (pinfunction "10_10") (pintype "passive"))
      (node (ref "IC92") (pin "10") (pinfunction "10_10") (pintype "passive"))
      (node (ref "IC93") (pin "10") (pinfunction "10_10") (pintype "passive"))
    )
    (net (code "546") (name "Net-(IC90-Pad11)") (class "Default")
      (node (ref "IC90") (pin "11") (pinfunction "11_11") (pintype "passive"))
      (node (ref "IC91") (pin "11") (pinfunction "11_11") (pintype "passive"))
      (node (ref "IC92") (pin "11") (pinfunction "11_11") (pintype "passive"))
      (node (ref "IC93") (pin "11") (pinfunction "11_11") (pintype "passive"))
    )
    (net (code "547") (name "Net-(IC90-Pad12)") (class "Default")
      (node (ref "IC90") (pin "12") (pinfunction "12_12") (pintype "passive"))
      (node (ref "IC91") (pin "12") (pinfunction "12_12") (pintype "passive"))
      (node (ref "IC92") (pin "12") (pinfunction "12_12") (pintype "passive"))
      (node (ref "IC93") (pin "12") (pinfunction "12_12") (pintype "passive"))
    )
    (net (code "548") (name "Net-(IC90-Pad13)") (class "Default")
      (node (ref "IC90") (pin "13") (pinfunction "13_13") (pintype "passive"))
      (node (ref "IC91") (pin "13") (pinfunction "13_13") (pintype "passive"))
      (node (ref "IC92") (pin "13") (pinfunction "13_13") (pintype "passive"))
      (node (ref "IC93") (pin "13") (pinfunction "13_13") (pintype "passive"))
    )
    (net (code "549") (name "Net-(IC90-Pad14)") (class "Default")
      (node (ref "IC90") (pin "14") (pinfunction "14_14") (pintype "passive"))
      (node (ref "IC91") (pin "14") (pinfunction "14_14") (pintype "passive"))
      (node (ref "IC92") (pin "14") (pinfunction "14_14") (pintype "passive"))
      (node (ref "IC93") (pin "14") (pinfunction "14_14") (pintype "passive"))
    )
    (net (code "550") (name "Net-(IC90-Pad15)") (class "Default")
      (node (ref "IC90") (pin "15") (pinfunction "15_15") (pintype "passive"))
      (node (ref "IC91") (pin "15") (pinfunction "15_15") (pintype "passive"))
      (node (ref "IC92") (pin "15") (pinfunction "15_15") (pintype "passive"))
      (node (ref "IC93") (pin "15") (pinfunction "15_15") (pintype "passive"))
    )
    (net (code "551") (name "Net-(IC90-Pad16)") (class "Default")
      (node (ref "IC90") (pin "16") (pinfunction "16_16") (pintype "passive"))
      (node (ref "IC91") (pin "16") (pinfunction "16_16") (pintype "passive"))
      (node (ref "IC92") (pin "16") (pinfunction "16_16") (pintype "passive"))
      (node (ref "IC93") (pin "16") (pinfunction "16_16") (pintype "passive"))
    )
    (net (code "552") (name "Net-(IC90-Pad17)") (class "Default")
      (node (ref "IC90") (pin "17") (pinfunction "17_17") (pintype "passive"))
      (node (ref "IC91") (pin "17") (pinfunction "17_17") (pintype "passive"))
      (node (ref "IC92") (pin "17") (pinfunction "17_17") (pintype "passive"))
      (node (ref "IC93") (pin "17") (pinfunction "17_17") (pintype "passive"))
    )
    (net (code "553") (name "Net-(IC90-Pad18)") (class "Default")
      (node (ref "IC90") (pin "18") (pinfunction "18_18") (pintype "passive"))
      (node (ref "IC91") (pin "18") (pinfunction "18_18") (pintype "passive"))
      (node (ref "IC92") (pin "18") (pinfunction "18_18") (pintype "passive"))
      (node (ref "IC93") (pin "18") (pinfunction "18_18") (pintype "passive"))
    )
    (net (code "554") (name "Net-(IC90-Pad19)") (class "Default")
      (node (ref "IC90") (pin "19") (pinfunction "19_19") (pintype "passive"))
      (node (ref "IC91") (pin "19") (pinfunction "19_19") (pintype "passive"))
      (node (ref "IC92") (pin "19") (pinfunction "19_19") (pintype "passive"))
      (node (ref "IC93") (pin "19") (pinfunction "19_19") (pintype "passive"))
    )
    (net (code "555") (name "Net-(IC90-Pad20)") (class "Default")
      (node (ref "IC90") (pin "20") (pinfunction "20_20") (pintype "passive"))
      (node (ref "IC91") (pin "20") (pinfunction "20_20") (pintype "passive"))
      (node (ref "IC92") (pin "20") (pinfunction "20_20") (pintype "passive"))
      (node (ref "IC93") (pin "20") (pinfunction "20_20") (pintype "passive"))
    )
    (net (code "556") (name "Net-(IC90-Pad21)") (class "Default")
      (node (ref "IC90") (pin "21") (pinfunction "21_21") (pintype "passive"))
      (node (ref "IC91") (pin "21") (pinfunction "21_21") (pintype "passive"))
      (node (ref "IC92") (pin "21") (pinfunction "21_21") (pintype "passive"))
      (node (ref "IC93") (pin "21") (pinfunction "21_21") (pintype "passive"))
    )
    (net (code "557") (name "Net-(IC90-Pad22)") (class "Default")
      (node (ref "IC90") (pin "22") (pinfunction "22_22") (pintype "passive"))
      (node (ref "IC91") (pin "22") (pinfunction "22_22") (pintype "passive"))
      (node (ref "IC92") (pin "22") (pinfunction "22_22") (pintype "passive"))
      (node (ref "IC93") (pin "22") (pinfunction "22_22") (pintype "passive"))
    )
    (net (code "558") (name "Net-(IC90-Pad23)") (class "Default")
      (node (ref "IC90") (pin "23") (pinfunction "23_23") (pintype "passive"))
      (node (ref "IC91") (pin "23") (pinfunction "23_23") (pintype "passive"))
      (node (ref "IC92") (pin "23") (pinfunction "23_23") (pintype "passive"))
      (node (ref "IC93") (pin "23") (pinfunction "23_23") (pintype "passive"))
    )
    (net (code "559") (name "Net-(IC90-Pad24)") (class "Default")
      (node (ref "IC90") (pin "24") (pinfunction "24_24") (pintype "passive"))
      (node (ref "IC91") (pin "24") (pinfunction "24_24") (pintype "passive"))
      (node (ref "IC92") (pin "24") (pinfunction "24_24") (pintype "passive"))
      (node (ref "IC93") (pin "24") (pinfunction "24_24") (pintype "passive"))
    )
    (net (code "560") (name "Net-(IC94-Pad1)") (class "Default")
      (node (ref "IC94") (pin "1") (pinfunction "1_1") (pintype "passive"))
      (node (ref "IC95") (pin "1") (pinfunction "1_1") (pintype "passive"))
      (node (ref "IC96") (pin "1") (pinfunction "1_1") (pintype "passive"))
      (node (ref "IC97") (pin "1") (pinfunction "1_1") (pintype "passive"))
    )
    (net (code "561") (name "Net-(IC94-Pad2)") (class "Default")
      (node (ref "IC94") (pin "2") (pinfunction "2_2") (pintype "passive"))
      (node (ref "IC95") (pin "2") (pinfunction "2_2") (pintype "passive"))
      (node (ref "IC96") (pin "2") (pinfunction "2_2") (pintype "passive"))
      (node (ref "IC97") (pin "2") (pinfunction "2_2") (pintype "passive"))
    )
    (net (code "562") (name "Net-(IC94-Pad3)") (class "Default")
      (node (ref "IC94") (pin "3") (pinfunction "3_3") (pintype "passive"))
      (node (ref "IC95") (pin "3") (pinfunction "3_3") (pintype "passive"))
      (node (ref "IC96") (pin "3") (pinfunction "3_3") (pintype "passive"))
      (node (ref "IC97") (pin "3") (pinfunction "3_3") (pintype "passive"))
    )
    (net (code "563") (name "Net-(IC94-Pad4)") (class "Default")
      (node (ref "IC94") (pin "4") (pinfunction "4_4") (pintype "passive"))
      (node (ref "IC95") (pin "4") (pinfunction "4_4") (pintype "passive"))
      (node (ref "IC96") (pin "4") (pinfunction "4_4") (pintype "passive"))
      (node (ref "IC97") (pin "4") (pinfunction "4_4") (pintype "passive"))
    )
    (net (code "564") (name "Net-(IC94-Pad5)") (class "Default")
      (node (ref "IC94") (pin "5") (pinfunction "5_5") (pintype "passive"))
      (node (ref "IC95") (pin "5") (pinfunction "5_5") (pintype "passive"))
      (node (ref "IC96") (pin "5") (pinfunction "5_5") (pintype "passive"))
      (node (ref "IC97") (pin "5") (pinfunction "5_5") (pintype "passive"))
    )
    (net (code "565") (name "Net-(IC94-Pad6)") (class "Default")
      (node (ref "IC94") (pin "6") (pinfunction "6_6") (pintype "passive"))
      (node (ref "IC95") (pin "6") (pinfunction "6_6") (pintype "passive"))
      (node (ref "IC96") (pin "6") (pinfunction "6_6") (pintype "passive"))
      (node (ref "IC97") (pin "6") (pinfunction "6_6") (pintype "passive"))
    )
    (net (code "566") (name "Net-(IC94-Pad7)") (class "Default")
      (node (ref "IC94") (pin "7") (pinfunction "7_7") (pintype "passive"))
      (node (ref "IC95") (pin "7") (pinfunction "7_7") (pintype "passive"))
      (node (ref "IC96") (pin "7") (pinfunction "7_7") (pintype "passive"))
      (node (ref "IC97") (pin "7") (pinfunction "7_7") (pintype "passive"))
    )
    (net (code "567") (name "Net-(IC94-Pad8)") (class "Default")
      (node (ref "IC94") (pin "8") (pinfunction "8_8") (pintype "passive"))
      (node (ref "IC95") (pin "8") (pinfunction "8_8") (pintype "passive"))
      (node (ref "IC96") (pin "8") (pinfunction "8_8") (pintype "passive"))
      (node (ref "IC97") (pin "8") (pinfunction "8_8") (pintype "passive"))
    )
    (net (code "568") (name "Net-(IC94-Pad9)") (class "Default")
      (node (ref "IC94") (pin "9") (pinfunction "9_9") (pintype "passive"))
      (node (ref "IC95") (pin "9") (pinfunction "9_9") (pintype "passive"))
      (node (ref "IC96") (pin "9") (pinfunction "9_9") (pintype "passive"))
      (node (ref "IC97") (pin "9") (pinfunction "9_9") (pintype "passive"))
    )
    (net (code "569") (name "Net-(IC94-Pad10)") (class "Default")
      (node (ref "IC94") (pin "10") (pinfunction "10_10") (pintype "passive"))
      (node (ref "IC95") (pin "10") (pinfunction "10_10") (pintype "passive"))
      (node (ref "IC96") (pin "10") (pinfunction "10_10") (pintype "passive"))
      (node (ref "IC97") (pin "10") (pinfunction "10_10") (pintype "passive"))
    )
    (net (code "570") (name "Net-(IC94-Pad11)") (class "Default")
      (node (ref "IC94") (pin "11") (pinfunction "11_11") (pintype "passive"))
      (node (ref "IC95") (pin "11") (pinfunction "11_11") (pintype "passive"))
      (node (ref "IC96") (pin "11") (pinfunction "11_11") (pintype "passive"))
      (node (ref "IC97") (pin "11") (pinfunction "11_11") (pintype "passive"))
    )
    (net (code "571") (name "Net-(IC94-Pad12)") (class "Default")
      (node (ref "IC94") (pin "12") (pinfunction "12_12") (pintype "passive"))
      (node (ref "IC95") (pin "12") (pinfunction "12_12") (pintype "passive"))
      (node (ref "IC96") (pin "12") (pinfunction "12_12") (pintype "passive"))
      (node (ref "IC97") (pin "12") (pinfunction "12_12") (pintype "passive"))
    )
    (net (code "572") (name "Net-(IC94-Pad13)") (class "Default")
      (node (ref "IC94") (pin "13") (pinfunction "13_13") (pintype "passive"))
      (node (ref "IC95") (pin "13") (pinfunction "13_13") (pintype "passive"))
      (node (ref "IC96") (pin "13") (pinfunction "13_13") (pintype "passive"))
      (node (ref "IC97") (pin "13") (pinfunction "13_13") (pintype "passive"))
    )
    (net (code "573") (name "Net-(IC94-Pad14)") (class "Default")
      (node (ref "IC94") (pin "14") (pinfunction "14_14") (pintype "passive"))
      (node (ref "IC95") (pin "14") (pinfunction "14_14") (pintype "passive"))
      (node (ref "IC96") (pin "14") (pinfunction "14_14") (pintype "passive"))
      (node (ref "IC97") (pin "14") (pinfunction "14_14") (pintype "passive"))
    )
    (net (code "574") (name "Net-(IC94-Pad15)") (class "Default")
      (node (ref "IC94") (pin "15") (pinfunction "15_15") (pintype "passive"))
      (node (ref "IC95") (pin "15") (pinfunction "15_15") (pintype "passive"))
      (node (ref "IC96") (pin "15") (pinfunction "15_15") (pintype "passive"))
      (node (ref "IC97") (pin "15") (pinfunction "15_15") (pintype "passive"))
    )
    (net (code "575") (name "Net-(IC94-Pad16)") (class "Default")
      (node (ref "IC94") (pin "16") (pinfunction "16_16") (pintype "passive"))
      (node (ref "IC95") (pin "16") (pinfunction "16_16") (pintype "passive"))
      (node (ref "IC96") (pin "16") (pinfunction "16_16") (pintype "passive"))
      (node (ref "IC97") (pin "16") (pinfunction "16_16") (pintype "passive"))
    )
    (net (code "576") (name "Net-(IC94-Pad17)") (class "Default")
      (node (ref "IC94") (pin "17") (pinfunction "17_17") (pintype "passive"))
      (node (ref "IC95") (pin "17") (pinfunction "17_17") (pintype "passive"))
      (node (ref "IC96") (pin "17") (pinfunction "17_17") (pintype "passive"))
      (node (ref "IC97") (pin "17") (pinfunction "17_17") (pintype "passive"))
    )
    (net (code "577") (name "Net-(IC94-Pad18)") (class "Default")
      (node (ref "IC94") (pin "18") (pinfunction "18_18") (pintype "passive"))
      (node (ref "IC95") (pin "18") (pinfunction "18_18") (pintype "passive"))
      (node (ref "IC96") (pin "18") (pinfunction "18_18") (pintype "passive"))
      (node (ref "IC97") (pin "18") (pinfunction "18_18") (pintype "passive"))
    )
    (net (code "578") (name "Net-(IC94-Pad19)") (class "Default")
      (node (ref "IC94") (pin "19") (pinfunction "19_19") (pintype "passive"))
      (node (ref "IC95") (pin "19") (pinfunction "19_19") (pintype "passive"))
      (node (ref "IC96") (pin "19") (pinfunction "19_19") (pintype "passive"))
      (node (ref "IC97") (pin "19") (pinfunction "19_19") (pintype "passive"))
    )
    (net (code "579") (name "Net-(IC94-Pad20)") (class "Default")
      (node (ref "IC94") (pin "20") (pinfunction "20_20") (pintype "passive"))
      (node (ref "IC95") (pin "20") (pinfunction "20_20") (pintype "passive"))
      (node (ref "IC96") (pin "20") (pinfunction "20_20") (pintype "passive"))
      (node (ref "IC97") (pin "20") (pinfunction "20_20") (pintype "passive"))
    )
    (net (code "580") (name "Net-(IC94-Pad21)") (class "Default")
      (node (ref "IC94") (pin "21") (pinfunction "21_21") (pintype "passive"))
      (node (ref "IC95") (pin "21") (pinfunction "21_21") (pintype "passive"))
      (node (ref "IC96") (pin "21") (pinfunction "21_21") (pintype "passive"))
      (node (ref "IC97") (pin "21") (pinfunction "21_21") (pintype "passive"))
    )
    (net (code "581") (name "Net-(IC94-Pad22)") (class "Default")
      (node (ref "IC94") (pin "22") (pinfunction "22_22") (pintype "passive"))
      (node (ref "IC95") (pin "22") (pinfunction "22_22") (pintype "passive"))
      (node (ref "IC96") (pin "22") (pinfunction "22_22") (pintype "passive"))
      (node (ref "IC97") (pin "22") (pinfunction "22_22") (pintype "passive"))
    )
    (net (code "582") (name "Net-(IC94-Pad23)") (class "Default")
      (node (ref "IC94") (pin "23") (pinfunction "23_23") (pintype "passive"))
      (node (ref "IC95") (pin "23") (pinfunction "23_23") (pintype "passive"))
      (node (ref "IC96") (pin "23") (pinfunction "23_23") (pintype "passive"))
      (node (ref "IC97") (pin "23") (pinfunction "23_23") (pintype "passive"))
    )
    (net (code "583") (name "Net-(IC94-Pad24)") (class "Default")
      (node (ref "IC94") (pin "24") (pinfunction "24_24") (pintype "passive"))
      (node (ref "IC95") (pin "24") (pinfunction "24_24") (pintype "passive"))
      (node (ref "IC96") (pin "24") (pinfunction "24_24") (pintype "passive"))
      (node (ref "IC97") (pin "24") (pinfunction "24_24") (pintype "passive"))
    )
    (net (code "584") (name "Net-(IC100-Pad1)") (class "Default")
      (node (ref "IC100") (pin "1") (pinfunction "1_1") (pintype "passive"))
      (node (ref "IC101") (pin "1") (pinfunction "1_1") (pintype "passive"))
      (node (ref "IC98") (pin "1") (pinfunction "1_1") (pintype "passive"))
      (node (ref "IC99") (pin "1") (pinfunction "1_1") (pintype "passive"))
    )
    (net (code "585") (name "Net-(IC100-Pad2)") (class "Default")
      (node (ref "IC100") (pin "2") (pinfunction "2_2") (pintype "passive"))
      (node (ref "IC101") (pin "2") (pinfunction "2_2") (pintype "passive"))
      (node (ref "IC98") (pin "2") (pinfunction "2_2") (pintype "passive"))
      (node (ref "IC99") (pin "2") (pinfunction "2_2") (pintype "passive"))
    )
    (net (code "586") (name "Net-(IC100-Pad3)") (class "Default")
      (node (ref "IC100") (pin "3") (pinfunction "3_3") (pintype "passive"))
      (node (ref "IC101") (pin "3") (pinfunction "3_3") (pintype "passive"))
      (node (ref "IC98") (pin "3") (pinfunction "3_3") (pintype "passive"))
      (node (ref "IC99") (pin "3") (pinfunction "3_3") (pintype "passive"))
    )
    (net (code "587") (name "Net-(IC100-Pad4)") (class "Default")
      (node (ref "IC100") (pin "4") (pinfunction "4_4") (pintype "passive"))
      (node (ref "IC101") (pin "4") (pinfunction "4_4") (pintype "passive"))
      (node (ref "IC98") (pin "4") (pinfunction "4_4") (pintype "passive"))
      (node (ref "IC99") (pin "4") (pinfunction "4_4") (pintype "passive"))
    )
    (net (code "588") (name "Net-(IC100-Pad5)") (class "Default")
      (node (ref "IC100") (pin "5") (pinfunction "5_5") (pintype "passive"))
      (node (ref "IC101") (pin "5") (pinfunction "5_5") (pintype "passive"))
      (node (ref "IC98") (pin "5") (pinfunction "5_5") (pintype "passive"))
      (node (ref "IC99") (pin "5") (pinfunction "5_5") (pintype "passive"))
    )
    (net (code "589") (name "Net-(IC100-Pad6)") (class "Default")
      (node (ref "IC100") (pin "6") (pinfunction "6_6") (pintype "passive"))
      (node (ref "IC101") (pin "6") (pinfunction "6_6") (pintype "passive"))
      (node (ref "IC98") (pin "6") (pinfunction "6_6") (pintype "passive"))
      (node (ref "IC99") (pin "6") (pinfunction "6_6") (pintype "passive"))
    )
    (net (code "590") (name "Net-(IC100-Pad7)") (class "Default")
      (node (ref "IC100") (pin "7") (pinfunction "7_7") (pintype "passive"))
      (node (ref "IC101") (pin "7") (pinfunction "7_7") (pintype "passive"))
      (node (ref "IC98") (pin "7") (pinfunction "7_7") (pintype "passive"))
      (node (ref "IC99") (pin "7") (pinfunction "7_7") (pintype "passive"))
    )
    (net (code "591") (name "Net-(IC100-Pad8)") (class "Default")
      (node (ref "IC100") (pin "8") (pinfunction "8_8") (pintype "passive"))
      (node (ref "IC101") (pin "8") (pinfunction "8_8") (pintype "passive"))
      (node (ref "IC98") (pin "8") (pinfunction "8_8") (pintype "passive"))
      (node (ref "IC99") (pin "8") (pinfunction "8_8") (pintype "passive"))
    )
    (net (code "592") (name "Net-(IC100-Pad9)") (class "Default")
      (node (ref "IC100") (pin "9") (pinfunction "9_9") (pintype "passive"))
      (node (ref "IC101") (pin "9") (pinfunction "9_9") (pintype "passive"))
      (node (ref "IC98") (pin "9") (pinfunction "9_9") (pintype "passive"))
      (node (ref "IC99") (pin "9") (pinfunction "9_9") (pintype "passive"))
    )
    (net (code "593") (name "Net-(IC100-Pad10)") (class "Default")
      (node (ref "IC100") (pin "10") (pinfunction "10_10") (pintype "passive"))
      (node (ref "IC101") (pin "10") (pinfunction "10_10") (pintype "passive"))
      (node (ref "IC98") (pin "10") (pinfunction "10_10") (pintype "passive"))
      (node (ref "IC99") (pin "10") (pinfunction "10_10") (pintype "passive"))
    )
    (net (code "594") (name "Net-(IC100-Pad11)") (class "Default")
      (node (ref "IC100") (pin "11") (pinfunction "11_11") (pintype "passive"))
      (node (ref "IC101") (pin "11") (pinfunction "11_11") (pintype "passive"))
      (node (ref "IC98") (pin "11") (pinfunction "11_11") (pintype "passive"))
      (node (ref "IC99") (pin "11") (pinfunction "11_11") (pintype "passive"))
    )
    (net (code "595") (name "Net-(IC100-Pad12)") (class "Default")
      (node (ref "IC100") (pin "12") (pinfunction "12_12") (pintype "passive"))
      (node (ref "IC101") (pin "12") (pinfunction "12_12") (pintype "passive"))
      (node (ref "IC98") (pin "12") (pinfunction "12_12") (pintype "passive"))
      (node (ref "IC99") (pin "12") (pinfunction "12_12") (pintype "passive"))
    )
    (net (code "596") (name "Net-(IC100-Pad13)") (class "Default")
      (node (ref "IC100") (pin "13") (pinfunction "13_13") (pintype "passive"))
      (node (ref "IC101") (pin "13") (pinfunction "13_13") (pintype "passive"))
      (node (ref "IC98") (pin "13") (pinfunction "13_13") (pintype "passive"))
      (node (ref "IC99") (pin "13") (pinfunction "13_13") (pintype "passive"))
    )
    (net (code "597") (name "Net-(IC100-Pad14)") (class "Default")
      (node (ref "IC100") (pin "14") (pinfunction "14_14") (pintype "passive"))
      (node (ref "IC101") (pin "14") (pinfunction "14_14") (pintype "passive"))
      (node (ref "IC98") (pin "14") (pinfunction "14_14") (pintype "passive"))
      (node (ref "IC99") (pin "14") (pinfunction "14_14") (pintype "passive"))
    )
    (net (code "598") (name "Net-(IC100-Pad15)") (class "Default")
      (node (ref "IC100") (pin "15") (pinfunction "15_15") (pintype "passive"))
      (node (ref "IC101") (pin "15") (pinfunction "15_15") (pintype "passive"))
      (node (ref "IC98") (pin "15") (pinfunction "15_15") (pintype "passive"))
      (node (ref "IC99") (pin "15") (pinfunction "15_15") (pintype "passive"))
    )
    (net (code "599") (name "Net-(IC100-Pad16)") (class "Default")
      (node (ref "IC100") (pin "16") (pinfunction "16_16") (pintype "passive"))
      (node (ref "IC101") (pin "16") (pinfunction "16_16") (pintype "passive"))
      (node (ref "IC98") (pin "16") (pinfunction "16_16") (pintype "passive"))
      (node (ref "IC99") (pin "16") (pinfunction "16_16") (pintype "passive"))
    )
    (net (code "600") (name "Net-(IC100-Pad17)") (class "Default")
      (node (ref "IC100") (pin "17") (pinfunction "17_17") (pintype "passive"))
      (node (ref "IC101") (pin "17") (pinfunction "17_17") (pintype "passive"))
      (node (ref "IC98") (pin "17") (pinfunction "17_17") (pintype "passive"))
      (node (ref "IC99") (pin "17") (pinfunction "17_17") (pintype "passive"))
    )
    (net (code "601") (name "Net-(IC100-Pad18)") (class "Default")
      (node (ref "IC100") (pin "18") (pinfunction "18_18") (pintype "passive"))
      (node (ref "IC101") (pin "18") (pinfunction "18_18") (pintype "passive"))
      (node (ref "IC98") (pin "18") (pinfunction "18_18") (pintype "passive"))
      (node (ref "IC99") (pin "18") (pinfunction "18_18") (pintype "passive"))
    )
    (net (code "602") (name "Net-(IC100-Pad19)") (class "Default")
      (node (ref "IC100") (pin "19") (pinfunction "19_19") (pintype "passive"))
      (node (ref "IC101") (pin "19") (pinfunction "19_19") (pintype "passive"))
      (node (ref "IC98") (pin "19") (pinfunction "19_19") (pintype "passive"))
      (node (ref "IC99") (pin "19") (pinfunction "19_19") (pintype "passive"))
    )
    (net (code "603") (name "Net-(IC100-Pad20)") (class "Default")
      (node (ref "IC100") (pin "20") (pinfunction "20_20") (pintype "passive"))
      (node (ref "IC101") (pin "20") (pinfunction "20_20") (pintype "passive"))
      (node (ref "IC98") (pin "20") (pinfunction "20_20") (pintype "passive"))
      (node (ref "IC99") (pin "20") (pinfunction "20_20") (pintype "passive"))
    )
    (net (code "604") (name "Net-(IC100-Pad21)") (class "Default")
      (node (ref "IC100") (pin "21") (pinfunction "21_21") (pintype "passive"))
      (node (ref "IC101") (pin "21") (pinfunction "21_21") (pintype "passive"))
      (node (ref "IC98") (pin "21") (pinfunction "21_21") (pintype "passive"))
      (node (ref "IC99") (pin "21") (pinfunction "21_21") (pintype "passive"))
    )
    (net (code "605") (name "Net-(IC100-Pad22)") (class "Default")
      (node (ref "IC100") (pin "22") (pinfunction "22_22") (pintype "passive"))
      (node (ref "IC101") (pin "22") (pinfunction "22_22") (pintype "passive"))
      (node (ref "IC98") (pin "22") (pinfunction "22_22") (pintype "passive"))
      (node (ref "IC99") (pin "22") (pinfunction "22_22") (pintype "passive"))
    )
    (net (code "606") (name "Net-(IC100-Pad23)") (class "Default")
      (node (ref "IC100") (pin "23") (pinfunction "23_23") (pintype "passive"))
      (node (ref "IC101") (pin "23") (pinfunction "23_23") (pintype "passive"))
      (node (ref "IC98") (pin "23") (pinfunction "23_23") (pintype "passive"))
      (node (ref "IC99") (pin "23") (pinfunction "23_23") (pintype "passive"))
    )
    (net (code "607") (name "Net-(IC100-Pad24)") (class "Default")
      (node (ref "IC100") (pin "24") (pinfunction "24_24") (pintype "passive"))
      (node (ref "IC101") (pin "24") (pinfunction "24_24") (pintype "passive"))
      (node (ref "IC98") (pin "24") (pinfunction "24_24") (pintype "passive"))
      (node (ref "IC99") (pin "24") (pinfunction "24_24") (pintype "passive"))
    )
    (net (code "608") (name "Net-(IC102-Pad1)") (class "Default")
      (node (ref "IC102") (pin "1") (pinfunction "1_1") (pintype "passive"))
      (node (ref "IC103") (pin "1") (pinfunction "1_1") (pintype "passive"))
      (node (ref "IC104") (pin "1") (pinfunction "1_1") (pintype "passive"))
      (node (ref "IC105") (pin "1") (pinfunction "1_1") (pintype "passive"))
    )
    (net (code "609") (name "Net-(IC102-Pad2)") (class "Default")
      (node (ref "IC102") (pin "2") (pinfunction "2_2") (pintype "passive"))
      (node (ref "IC103") (pin "2") (pinfunction "2_2") (pintype "passive"))
      (node (ref "IC104") (pin "2") (pinfunction "2_2") (pintype "passive"))
      (node (ref "IC105") (pin "2") (pinfunction "2_2") (pintype "passive"))
    )
    (net (code "610") (name "Net-(IC102-Pad3)") (class "Default")
      (node (ref "IC102") (pin "3") (pinfunction "3_3") (pintype "passive"))
      (node (ref "IC103") (pin "3") (pinfunction "3_3") (pintype "passive"))
      (node (ref "IC104") (pin "3") (pinfunction "3_3") (pintype "passive"))
      (node (ref "IC105") (pin "3") (pinfunction "3_3") (pintype "passive"))
    )
    (net (code "611") (name "Net-(IC102-Pad4)") (class "Default")
      (node (ref "IC102") (pin "4") (pinfunction "4_4") (pintype "passive"))
      (node (ref "IC103") (pin "4") (pinfunction "4_4") (pintype "passive"))
      (node (ref "IC104") (pin "4") (pinfunction "4_4") (pintype "passive"))
      (node (ref "IC105") (pin "4") (pinfunction "4_4") (pintype "passive"))
    )
    (net (code "612") (name "Net-(IC102-Pad5)") (class "Default")
      (node (ref "IC102") (pin "5") (pinfunction "5_5") (pintype "passive"))
      (node (ref "IC103") (pin "5") (pinfunction "5_5") (pintype "passive"))
      (node (ref "IC104") (pin "5") (pinfunction "5_5") (pintype "passive"))
      (node (ref "IC105") (pin "5") (pinfunction "5_5") (pintype "passive"))
    )
    (net (code "613") (name "Net-(IC102-Pad6)") (class "Default")
      (node (ref "IC102") (pin "6") (pinfunction "6_6") (pintype "passive"))
      (node (ref "IC103") (pin "6") (pinfunction "6_6") (pintype "passive"))
      (node (ref "IC104") (pin "6") (pinfunction "6_6") (pintype "passive"))
      (node (ref "IC105") (pin "6") (pinfunction "6_6") (pintype "passive"))
    )
    (net (code "614") (name "Net-(IC102-Pad7)") (class "Default")
      (node (ref "IC102") (pin "7") (pinfunction "7_7") (pintype "passive"))
      (node (ref "IC103") (pin "7") (pinfunction "7_7") (pintype "passive"))
      (node (ref "IC104") (pin "7") (pinfunction "7_7") (pintype "passive"))
      (node (ref "IC105") (pin "7") (pinfunction "7_7") (pintype "passive"))
    )
    (net (code "615") (name "Net-(IC102-Pad8)") (class "Default")
      (node (ref "IC102") (pin "8") (pinfunction "8_8") (pintype "passive"))
      (node (ref "IC103") (pin "8") (pinfunction "8_8") (pintype "passive"))
      (node (ref "IC104") (pin "8") (pinfunction "8_8") (pintype "passive"))
      (node (ref "IC105") (pin "8") (pinfunction "8_8") (pintype "passive"))
    )
    (net (code "616") (name "Net-(IC102-Pad9)") (class "Default")
      (node (ref "IC102") (pin "9") (pinfunction "9_9") (pintype "passive"))
      (node (ref "IC103") (pin "9") (pinfunction "9_9") (pintype "passive"))
      (node (ref "IC104") (pin "9") (pinfunction "9_9") (pintype "passive"))
      (node (ref "IC105") (pin "9") (pinfunction "9_9") (pintype "passive"))
    )
    (net (code "617") (name "Net-(IC102-Pad10)") (class "Default")
      (node (ref "IC102") (pin "10") (pinfunction "10_10") (pintype "passive"))
      (node (ref "IC103") (pin "10") (pinfunction "10_10") (pintype "passive"))
      (node (ref "IC104") (pin "10") (pinfunction "10_10") (pintype "passive"))
      (node (ref "IC105") (pin "10") (pinfunction "10_10") (pintype "passive"))
    )
    (net (code "618") (name "Net-(IC102-Pad11)") (class "Default")
      (node (ref "IC102") (pin "11") (pinfunction "11_11") (pintype "passive"))
      (node (ref "IC103") (pin "11") (pinfunction "11_11") (pintype "passive"))
      (node (ref "IC104") (pin "11") (pinfunction "11_11") (pintype "passive"))
      (node (ref "IC105") (pin "11") (pinfunction "11_11") (pintype "passive"))
    )
    (net (code "619") (name "Net-(IC102-Pad12)") (class "Default")
      (node (ref "IC102") (pin "12") (pinfunction "12_12") (pintype "passive"))
      (node (ref "IC103") (pin "12") (pinfunction "12_12") (pintype "passive"))
      (node (ref "IC104") (pin "12") (pinfunction "12_12") (pintype "passive"))
      (node (ref "IC105") (pin "12") (pinfunction "12_12") (pintype "passive"))
    )
    (net (code "620") (name "Net-(IC102-Pad13)") (class "Default")
      (node (ref "IC102") (pin "13") (pinfunction "13_13") (pintype "passive"))
      (node (ref "IC103") (pin "13") (pinfunction "13_13") (pintype "passive"))
      (node (ref "IC104") (pin "13") (pinfunction "13_13") (pintype "passive"))
      (node (ref "IC105") (pin "13") (pinfunction "13_13") (pintype "passive"))
    )
    (net (code "621") (name "Net-(IC102-Pad14)") (class "Default")
      (node (ref "IC102") (pin "14") (pinfunction "14_14") (pintype "passive"))
      (node (ref "IC103") (pin "14") (pinfunction "14_14") (pintype "passive"))
      (node (ref "IC104") (pin "14") (pinfunction "14_14") (pintype "passive"))
      (node (ref "IC105") (pin "14") (pinfunction "14_14") (pintype "passive"))
    )
    (net (code "622") (name "Net-(IC102-Pad15)") (class "Default")
      (node (ref "IC102") (pin "15") (pinfunction "15_15") (pintype "passive"))
      (node (ref "IC103") (pin "15") (pinfunction "15_15") (pintype "passive"))
      (node (ref "IC104") (pin "15") (pinfunction "15_15") (pintype "passive"))
      (node (ref "IC105") (pin "15") (pinfunction "15_15") (pintype "passive"))
    )
    (net (code "623") (name "Net-(IC102-Pad16)") (class "Default")
      (node (ref "IC102") (pin "16") (pinfunction "16_16") (pintype "passive"))
      (node (ref "IC103") (pin "16") (pinfunction "16_16") (pintype "passive"))
      (node (ref "IC104") (pin "16") (pinfunction "16_16") (pintype "passive"))
      (node (ref "IC105") (pin "16") (pinfunction "16_16") (pintype "passive"))
    )
    (net (code "624") (name "Net-(IC102-Pad17)") (class "Default")
      (node (ref "IC102") (pin "17") (pinfunction "17_17") (pintype "passive"))
      (node (ref "IC103") (pin "17") (pinfunction "17_17") (pintype "passive"))
      (node (ref "IC104") (pin "17") (pinfunction "17_17") (pintype "passive"))
      (node (ref "IC105") (pin "17") (pinfunction "17_17") (pintype "passive"))
    )
    (net (code "625") (name "Net-(IC102-Pad18)") (class "Default")
      (node (ref "IC102") (pin "18") (pinfunction "18_18") (pintype "passive"))
      (node (ref "IC103") (pin "18") (pinfunction "18_18") (pintype "passive"))
      (node (ref "IC104") (pin "18") (pinfunction "18_18") (pintype "passive"))
      (node (ref "IC105") (pin "18") (pinfunction "18_18") (pintype "passive"))
    )
    (net (code "626") (name "Net-(IC102-Pad19)") (class "Default")
      (node (ref "IC102") (pin "19") (pinfunction "19_19") (pintype "passive"))
      (node (ref "IC103") (pin "19") (pinfunction "19_19") (pintype "passive"))
      (node (ref "IC104") (pin "19") (pinfunction "19_19") (pintype "passive"))
      (node (ref "IC105") (pin "19") (pinfunction "19_19") (pintype "passive"))
    )
    (net (code "627") (name "Net-(IC102-Pad20)") (class "Default")
      (node (ref "IC102") (pin "20") (pinfunction "20_20") (pintype "passive"))
      (node (ref "IC103") (pin "20") (pinfunction "20_20") (pintype "passive"))
      (node (ref "IC104") (pin "20") (pinfunction "20_20") (pintype "passive"))
      (node (ref "IC105") (pin "20") (pinfunction "20_20") (pintype "passive"))
    )
    (net (code "628") (name "Net-(IC102-Pad21)") (class "Default")
      (node (ref "IC102") (pin "21") (pinfunction "21_21") (pintype "passive"))
      (node (ref "IC103") (pin "21") (pinfunction "21_21") (pintype "passive"))
      (node (ref "IC104") (pin "21") (pinfunction "21_21") (pintype "passive"))
      (node (ref "IC105") (pin "21") (pinfunction "21_21") (pintype "passive"))
    )
    (net (code "629") (name "Net-(IC102-Pad22)") (class "Default")
      (node (ref "IC102") (pin "22") (pinfunction "22_22") (pintype "passive"))
      (node (ref "IC103") (pin "22") (pinfunction "22_22") (pintype "passive"))
      (node (ref "IC104") (pin "22") (pinfunction "22_22") (pintype "passive"))
      (node (ref "IC105") (pin "22") (pinfunction "22_22") (pintype "passive"))
    )
    (net (code "630") (name "Net-(IC102-Pad23)") (class "Default")
      (node (ref "IC102") (pin "23") (pinfunction "23_23") (pintype "passive"))
      (node (ref "IC103") (pin "23") (pinfunction "23_23") (pintype "passive"))
      (node (ref "IC104") (pin "23") (pinfunction "23_23") (pintype "passive"))
      (node (ref "IC105") (pin "23") (pinfunction "23_23") (pintype "passive"))
    )
    (net (code "631") (name "Net-(IC102-Pad24)") (class "Default")
      (node (ref "IC102") (pin "24") (pinfunction "24_24") (pintype "passive"))
      (node (ref "IC103") (pin "24") (pinfunction "24_24") (pintype "passive"))
      (node (ref "IC104") (pin "24") (pinfunction "24_24") (pintype "passive"))
      (node (ref "IC105") (pin "24") (pinfunction "24_24") (pintype "passive"))
    )
    (net (code "632") (name "Net-(IC106-Pad1)") (class "Default")
      (node (ref "IC106") (pin "1") (pinfunction "1_1") (pintype "passive"))
      (node (ref "IC107") (pin "1") (pinfunction "1_1") (pintype "passive"))
      (node (ref "IC108") (pin "1") (pinfunction "1_1") (pintype "passive"))
      (node (ref "IC109") (pin "1") (pinfunction "1_1") (pintype "passive"))
    )
    (net (code "633") (name "Net-(IC106-Pad2)") (class "Default")
      (node (ref "IC106") (pin "2") (pinfunction "2_2") (pintype "passive"))
      (node (ref "IC107") (pin "2") (pinfunction "2_2") (pintype "passive"))
      (node (ref "IC108") (pin "2") (pinfunction "2_2") (pintype "passive"))
      (node (ref "IC109") (pin "2") (pinfunction "2_2") (pintype "passive"))
    )
    (net (code "634") (name "Net-(IC106-Pad3)") (class "Default")
      (node (ref "IC106") (pin "3") (pinfunction "3_3") (pintype "passive"))
      (node (ref "IC107") (pin "3") (pinfunction "3_3") (pintype "passive"))
      (node (ref "IC108") (pin "3") (pinfunction "3_3") (pintype "passive"))
      (node (ref "IC109") (pin "3") (pinfunction "3_3") (pintype "passive"))
    )
    (net (code "635") (name "Net-(IC106-Pad4)") (class "Default")
      (node (ref "IC106") (pin "4") (pinfunction "4_4") (pintype "passive"))
      (node (ref "IC107") (pin "4") (pinfunction "4_4") (pintype "passive"))
      (node (ref "IC108") (pin "4") (pinfunction "4_4") (pintype "passive"))
      (node (ref "IC109") (pin "4") (pinfunction "4_4") (pintype "passive"))
    )
    (net (code "636") (name "Net-(IC106-Pad5)") (class "Default")
      (node (ref "IC106") (pin "5") (pinfunction "5_5") (pintype "passive"))
      (node (ref "IC107") (pin "5") (pinfunction "5_5") (pintype "passive"))
      (node (ref "IC108") (pin "5") (pinfunction "5_5") (pintype "passive"))
      (node (ref "IC109") (pin "5") (pinfunction "5_5") (pintype "passive"))
    )
    (net (code "637") (name "Net-(IC106-Pad6)") (class "Default")
      (node (ref "IC106") (pin "6") (pinfunction "6_6") (pintype "passive"))
      (node (ref "IC107") (pin "6") (pinfunction "6_6") (pintype "passive"))
      (node (ref "IC108") (pin "6") (pinfunction "6_6") (pintype "passive"))
      (node (ref "IC109") (pin "6") (pinfunction "6_6") (pintype "passive"))
    )
    (net (code "638") (name "Net-(IC106-Pad7)") (class "Default")
      (node (ref "IC106") (pin "7") (pinfunction "7_7") (pintype "passive"))
      (node (ref "IC107") (pin "7") (pinfunction "7_7") (pintype "passive"))
      (node (ref "IC108") (pin "7") (pinfunction "7_7") (pintype "passive"))
      (node (ref "IC109") (pin "7") (pinfunction "7_7") (pintype "passive"))
    )
    (net (code "639") (name "Net-(IC106-Pad8)") (class "Default")
      (node (ref "IC106") (pin "8") (pinfunction "8_8") (pintype "passive"))
      (node (ref "IC107") (pin "8") (pinfunction "8_8") (pintype "passive"))
      (node (ref "IC108") (pin "8") (pinfunction "8_8") (pintype "passive"))
      (node (ref "IC109") (pin "8") (pinfunction "8_8") (pintype "passive"))
    )
    (net (code "640") (name "Net-(IC106-Pad9)") (class "Default")
      (node (ref "IC106") (pin "9") (pinfunction "9_9") (pintype "passive"))
      (node (ref "IC107") (pin "9") (pinfunction "9_9") (pintype "passive"))
      (node (ref "IC108") (pin "9") (pinfunction "9_9") (pintype "passive"))
      (node (ref "IC109") (pin "9") (pinfunction "9_9") (pintype "passive"))
    )
    (net (code "641") (name "Net-(IC106-Pad10)") (class "Default")
      (node (ref "IC106") (pin "10") (pinfunction "10_10") (pintype "passive"))
      (node (ref "IC107") (pin "10") (pinfunction "10_10") (pintype "passive"))
      (node (ref "IC108") (pin "10") (pinfunction "10_10") (pintype "passive"))
      (node (ref "IC109") (pin "10") (pinfunction "10_10") (pintype "passive"))
    )
    (net (code "642") (name "Net-(IC106-Pad11)") (class "Default")
      (node (ref "IC106") (pin "11") (pinfunction "11_11") (pintype "passive"))
      (node (ref "IC107") (pin "11") (pinfunction "11_11") (pintype "passive"))
      (node (ref "IC108") (pin "11") (pinfunction "11_11") (pintype "passive"))
      (node (ref "IC109") (pin "11") (pinfunction "11_11") (pintype "passive"))
    )
    (net (code "643") (name "Net-(IC106-Pad12)") (class "Default")
      (node (ref "IC106") (pin "12") (pinfunction "12_12") (pintype "passive"))
      (node (ref "IC107") (pin "12") (pinfunction "12_12") (pintype "passive"))
      (node (ref "IC108") (pin "12") (pinfunction "12_12") (pintype "passive"))
      (node (ref "IC109") (pin "12") (pinfunction "12_12") (pintype "passive"))
    )
    (net (code "644") (name "Net-(IC106-Pad13)") (class "Default")
      (node (ref "IC106") (pin "13") (pinfunction "13_13") (pintype "passive"))
      (node (ref "IC107") (pin "13") (pinfunction "13_13") (pintype "passive"))
      (node (ref "IC108") (pin "13") (pinfunction "13_13") (pintype "passive"))
      (node (ref "IC109") (pin "13") (pinfunction "13_13") (pintype "passive"))
    )
    (net (code "645") (name "Net-(IC106-Pad14)") (class "Default")
      (node (ref "IC106") (pin "14") (pinfunction "14_14") (pintype "passive"))
      (node (ref "IC107") (pin "14") (pinfunction "14_14") (pintype "passive"))
      (node (ref "IC108") (pin "14") (pinfunction "14_14") (pintype "passive"))
      (node (ref "IC109") (pin "14") (pinfunction "14_14") (pintype "passive"))
    )
    (net (code "646") (name "Net-(IC106-Pad15)") (class "Default")
      (node (ref "IC106") (pin "15") (pinfunction "15_15") (pintype "passive"))
      (node (ref "IC107") (pin "15") (pinfunction "15_15") (pintype "passive"))
      (node (ref "IC108") (pin "15") (pinfunction "15_15") (pintype "passive"))
      (node (ref "IC109") (pin "15") (pinfunction "15_15") (pintype "passive"))
    )
    (net (code "647") (name "Net-(IC106-Pad16)") (class "Default")
      (node (ref "IC106") (pin "16") (pinfunction "16_16") (pintype "passive"))
      (node (ref "IC107") (pin "16") (pinfunction "16_16") (pintype "passive"))
      (node (ref "IC108") (pin "16") (pinfunction "16_16") (pintype "passive"))
      (node (ref "IC109") (pin "16") (pinfunction "16_16") (pintype "passive"))
    )
    (net (code "648") (name "Net-(IC106-Pad17)") (class "Default")
      (node (ref "IC106") (pin "17") (pinfunction "17_17") (pintype "passive"))
      (node (ref "IC107") (pin "17") (pinfunction "17_17") (pintype "passive"))
      (node (ref "IC108") (pin "17") (pinfunction "17_17") (pintype "passive"))
      (node (ref "IC109") (pin "17") (pinfunction "17_17") (pintype "passive"))
    )
    (net (code "649") (name "Net-(IC106-Pad18)") (class "Default")
      (node (ref "IC106") (pin "18") (pinfunction "18_18") (pintype "passive"))
      (node (ref "IC107") (pin "18") (pinfunction "18_18") (pintype "passive"))
      (node (ref "IC108") (pin "18") (pinfunction "18_18") (pintype "passive"))
      (node (ref "IC109") (pin "18") (pinfunction "18_18") (pintype "passive"))
    )
    (net (code "650") (name "Net-(IC106-Pad19)") (class "Default")
      (node (ref "IC106") (pin "19") (pinfunction "19_19") (pintype "passive"))
      (node (ref "IC107") (pin "19") (pinfunction "19_19") (pintype "passive"))
      (node (ref "IC108") (pin "19") (pinfunction "19_19") (pintype "passive"))
      (node (ref "IC109") (pin "19") (pinfunction "19_19") (pintype "passive"))
    )
    (net (code "651") (name "Net-(IC106-Pad20)") (class "Default")
      (node (ref "IC106") (pin "20") (pinfunction "20_20") (pintype "passive"))
      (node (ref "IC107") (pin "20") (pinfunction "20_20") (pintype "passive"))
      (node (ref "IC108") (pin "20") (pinfunction "20_20") (pintype "passive"))
      (node (ref "IC109") (pin "20") (pinfunction "20_20") (pintype "passive"))
    )
    (net (code "652") (name "Net-(IC106-Pad21)") (class "Default")
      (node (ref "IC106") (pin "21") (pinfunction "21_21") (pintype "passive"))
      (node (ref "IC107") (pin "21") (pinfunction "21_21") (pintype "passive"))
      (node (ref "IC108") (pin "21") (pinfunction "21_21") (pintype "passive"))
      (node (ref "IC109") (pin "21") (pinfunction "21_21") (pintype "passive"))
    )
    (net (code "653") (name "Net-(IC106-Pad22)") (class "Default")
      (node (ref "IC106") (pin "22") (pinfunction "22_22") (pintype "passive"))
      (node (ref "IC107") (pin "22") (pinfunction "22_22") (pintype "passive"))
      (node (ref "IC108") (pin "22") (pinfunction "22_22") (pintype "passive"))
      (node (ref "IC109") (pin "22") (pinfunction "22_22") (pintype "passive"))
    )
    (net (code "654") (name "Net-(IC106-Pad23)") (class "Default")
      (node (ref "IC106") (pin "23") (pinfunction "23_23") (pintype "passive"))
      (node (ref "IC107") (pin "23") (pinfunction "23_23") (pintype "passive"))
      (node (ref "IC108") (pin "23") (pinfunction "23_23") (pintype "passive"))
      (node (ref "IC109") (pin "23") (pinfunction "23_23") (pintype "passive"))
    )
    (net (code "655") (name "Net-(IC106-Pad24)") (class "Default")
      (node (ref "IC106") (pin "24") (pinfunction "24_24") (pintype "passive"))
      (node (ref "IC107") (pin "24") (pinfunction "24_24") (pintype "passive"))
      (node (ref "IC108") (pin "24") (pinfunction "24_24") (pintype "passive"))
      (node (ref "IC109") (pin "24") (pinfunction "24_24") (pintype "passive"))
    )
    (net (code "656") (name "Net-(IC110-Pad1)") (class "Default")
      (node (ref "IC110") (pin "1") (pinfunction "1_1") (pintype "passive"))
      (node (ref "IC111") (pin "1") (pinfunction "1_1") (pintype "passive"))
      (node (ref "IC112") (pin "1") (pinfunction "1_1") (pintype "passive"))
      (node (ref "IC9") (pin "1") (pinfunction "1_1") (pintype "passive"))
    )
    (net (code "657") (name "Net-(IC110-Pad2)") (class "Default")
      (node (ref "IC110") (pin "2") (pinfunction "2_2") (pintype "passive"))
      (node (ref "IC111") (pin "2") (pinfunction "2_2") (pintype "passive"))
      (node (ref "IC112") (pin "2") (pinfunction "2_2") (pintype "passive"))
      (node (ref "IC9") (pin "2") (pinfunction "2_2") (pintype "passive"))
    )
    (net (code "658") (name "Net-(IC110-Pad3)") (class "Default")
      (node (ref "IC110") (pin "3") (pinfunction "3_3") (pintype "passive"))
      (node (ref "IC111") (pin "3") (pinfunction "3_3") (pintype "passive"))
      (node (ref "IC112") (pin "3") (pinfunction "3_3") (pintype "passive"))
      (node (ref "IC9") (pin "3") (pinfunction "3_3") (pintype "passive"))
    )
    (net (code "659") (name "Net-(IC110-Pad4)") (class "Default")
      (node (ref "IC110") (pin "4") (pinfunction "4_4") (pintype "passive"))
      (node (ref "IC111") (pin "4") (pinfunction "4_4") (pintype "passive"))
      (node (ref "IC112") (pin "4") (pinfunction "4_4") (pintype "passive"))
      (node (ref "IC9") (pin "4") (pinfunction "4_4") (pintype "passive"))
    )
    (net (code "660") (name "Net-(IC110-Pad5)") (class "Default")
      (node (ref "IC110") (pin "5") (pinfunction "5_5") (pintype "passive"))
      (node (ref "IC111") (pin "5") (pinfunction "5_5") (pintype "passive"))
      (node (ref "IC112") (pin "5") (pinfunction "5_5") (pintype "passive"))
      (node (ref "IC9") (pin "5") (pinfunction "5_5") (pintype "passive"))
    )
    (net (code "661") (name "Net-(IC110-Pad6)") (class "Default")
      (node (ref "IC110") (pin "6") (pinfunction "6_6") (pintype "passive"))
      (node (ref "IC111") (pin "6") (pinfunction "6_6") (pintype "passive"))
      (node (ref "IC112") (pin "6") (pinfunction "6_6") (pintype "passive"))
      (node (ref "IC9") (pin "6") (pinfunction "6_6") (pintype "passive"))
    )
    (net (code "662") (name "Net-(IC110-Pad7)") (class "Default")
      (node (ref "IC110") (pin "7") (pinfunction "7_7") (pintype "passive"))
      (node (ref "IC111") (pin "7") (pinfunction "7_7") (pintype "passive"))
      (node (ref "IC112") (pin "7") (pinfunction "7_7") (pintype "passive"))
      (node (ref "IC9") (pin "7") (pinfunction "7_7") (pintype "passive"))
    )
    (net (code "663") (name "Net-(IC110-Pad8)") (class "Default")
      (node (ref "IC110") (pin "8") (pinfunction "8_8") (pintype "passive"))
      (node (ref "IC111") (pin "8") (pinfunction "8_8") (pintype "passive"))
      (node (ref "IC112") (pin "8") (pinfunction "8_8") (pintype "passive"))
      (node (ref "IC9") (pin "8") (pinfunction "8_8") (pintype "passive"))
    )
    (net (code "664") (name "Net-(IC110-Pad9)") (class "Default")
      (node (ref "IC110") (pin "9") (pinfunction "9_9") (pintype "passive"))
      (node (ref "IC111") (pin "9") (pinfunction "9_9") (pintype "passive"))
      (node (ref "IC112") (pin "9") (pinfunction "9_9") (pintype "passive"))
      (node (ref "IC9") (pin "9") (pinfunction "9_9") (pintype "passive"))
    )
    (net (code "665") (name "Net-(IC110-Pad10)") (class "Default")
      (node (ref "IC110") (pin "10") (pinfunction "10_10") (pintype "passive"))
      (node (ref "IC111") (pin "10") (pinfunction "10_10") (pintype "passive"))
      (node (ref "IC112") (pin "10") (pinfunction "10_10") (pintype "passive"))
      (node (ref "IC9") (pin "10") (pinfunction "10_10") (pintype "passive"))
    )
    (net (code "666") (name "Net-(IC110-Pad11)") (class "Default")
      (node (ref "IC110") (pin "11") (pinfunction "11_11") (pintype "passive"))
      (node (ref "IC111") (pin "11") (pinfunction "11_11") (pintype "passive"))
      (node (ref "IC112") (pin "11") (pinfunction "11_11") (pintype "passive"))
      (node (ref "IC9") (pin "11") (pinfunction "11_11") (pintype "passive"))
    )
    (net (code "667") (name "Net-(IC110-Pad12)") (class "Default")
      (node (ref "IC110") (pin "12") (pinfunction "12_12") (pintype "passive"))
      (node (ref "IC111") (pin "12") (pinfunction "12_12") (pintype "passive"))
      (node (ref "IC112") (pin "12") (pinfunction "12_12") (pintype "passive"))
      (node (ref "IC9") (pin "12") (pinfunction "12_12") (pintype "passive"))
    )
    (net (code "668") (name "Net-(IC110-Pad13)") (class "Default")
      (node (ref "IC110") (pin "13") (pinfunction "13_13") (pintype "passive"))
      (node (ref "IC111") (pin "13") (pinfunction "13_13") (pintype "passive"))
      (node (ref "IC112") (pin "13") (pinfunction "13_13") (pintype "passive"))
      (node (ref "IC9") (pin "13") (pinfunction "13_13") (pintype "passive"))
    )
    (net (code "669") (name "Net-(IC110-Pad14)") (class "Default")
      (node (ref "IC110") (pin "14") (pinfunction "14_14") (pintype "passive"))
      (node (ref "IC111") (pin "14") (pinfunction "14_14") (pintype "passive"))
      (node (ref "IC112") (pin "14") (pinfunction "14_14") (pintype "passive"))
      (node (ref "IC9") (pin "14") (pinfunction "14_14") (pintype "passive"))
    )
    (net (code "670") (name "Net-(IC110-Pad15)") (class "Default")
      (node (ref "IC110") (pin "15") (pinfunction "15_15") (pintype "passive"))
      (node (ref "IC111") (pin "15") (pinfunction "15_15") (pintype "passive"))
      (node (ref "IC112") (pin "15") (pinfunction "15_15") (pintype "passive"))
      (node (ref "IC9") (pin "15") (pinfunction "15_15") (pintype "passive"))
    )
    (net (code "671") (name "Net-(IC110-Pad16)") (class "Default")
      (node (ref "IC110") (pin "16") (pinfunction "16_16") (pintype "passive"))
      (node (ref "IC111") (pin "16") (pinfunction "16_16") (pintype "passive"))
      (node (ref "IC112") (pin "16") (pinfunction "16_16") (pintype "passive"))
      (node (ref "IC9") (pin "16") (pinfunction "16_16") (pintype "passive"))
    )
    (net (code "672") (name "Net-(IC110-Pad17)") (class "Default")
      (node (ref "IC110") (pin "17") (pinfunction "17_17") (pintype "passive"))
      (node (ref "IC111") (pin "17") (pinfunction "17_17") (pintype "passive"))
      (node (ref "IC112") (pin "17") (pinfunction "17_17") (pintype "passive"))
      (node (ref "IC9") (pin "17") (pinfunction "17_17") (pintype "passive"))
    )
    (net (code "673") (name "Net-(IC110-Pad18)") (class "Default")
      (node (ref "IC110") (pin "18") (pinfunction "18_18") (pintype "passive"))
      (node (ref "IC111") (pin "18") (pinfunction "18_18") (pintype "passive"))
      (node (ref "IC112") (pin "18") (pinfunction "18_18") (pintype "passive"))
      (node (ref "IC9") (pin "18") (pinfunction "18_18") (pintype "passive"))
    )
    (net (code "674") (name "Net-(IC110-Pad19)") (class "Default")
      (node (ref "IC110") (pin "19") (pinfunction "19_19") (pintype "passive"))
      (node (ref "IC111") (pin "19") (pinfunction "19_19") (pintype "passive"))
      (node (ref "IC112") (pin "19") (pinfunction "19_19") (pintype "passive"))
      (node (ref "IC9") (pin "19") (pinfunction "19_19") (pintype "passive"))
    )
    (net (code "675") (name "Net-(IC110-Pad20)") (class "Default")
      (node (ref "IC110") (pin "20") (pinfunction "20_20") (pintype "passive"))
      (node (ref "IC111") (pin "20") (pinfunction "20_20") (pintype "passive"))
      (node (ref "IC112") (pin "20") (pinfunction "20_20") (pintype "passive"))
      (node (ref "IC9") (pin "20") (pinfunction "20_20") (pintype "passive"))
    )
    (net (code "676") (name "Net-(IC110-Pad21)") (class "Default")
      (node (ref "IC110") (pin "21") (pinfunction "21_21") (pintype "passive"))
      (node (ref "IC111") (pin "21") (pinfunction "21_21") (pintype "passive"))
      (node (ref "IC112") (pin "21") (pinfunction "21_21") (pintype "passive"))
      (node (ref "IC9") (pin "21") (pinfunction "21_21") (pintype "passive"))
    )
    (net (code "677") (name "Net-(IC110-Pad22)") (class "Default")
      (node (ref "IC110") (pin "22") (pinfunction "22_22") (pintype "passive"))
      (node (ref "IC111") (pin "22") (pinfunction "22_22") (pintype "passive"))
      (node (ref "IC112") (pin "22") (pinfunction "22_22") (pintype "passive"))
      (node (ref "IC9") (pin "22") (pinfunction "22_22") (pintype "passive"))
    )
    (net (code "678") (name "Net-(IC110-Pad23)") (class "Default")
      (node (ref "IC110") (pin "23") (pinfunction "23_23") (pintype "passive"))
      (node (ref "IC111") (pin "23") (pinfunction "23_23") (pintype "passive"))
      (node (ref "IC112") (pin "23") (pinfunction "23_23") (pintype "passive"))
      (node (ref "IC9") (pin "23") (pinfunction "23_23") (pintype "passive"))
    )
    (net (code "679") (name "Net-(IC110-Pad24)") (class "Default")
      (node (ref "IC110") (pin "24") (pinfunction "24_24") (pintype "passive"))
      (node (ref "IC111") (pin "24") (pinfunction "24_24") (pintype "passive"))
      (node (ref "IC112") (pin "24") (pinfunction "24_24") (pintype "passive"))
      (node (ref "IC9") (pin "24") (pinfunction "24_24") (pintype "passive"))
    )
    (net (code "680") (name "Net-(IC113-Pad1)") (class "Default")
      (node (ref "IC113") (pin "1") (pinfunction "1_1") (pintype "passive"))
      (node (ref "IC114") (pin "1") (pinfunction "1_1") (pintype "passive"))
      (node (ref "IC115") (pin "1") (pinfunction "1_1") (pintype "passive"))
      (node (ref "IC116") (pin "1") (pinfunction "1_1") (pintype "passive"))
    )
    (net (code "681") (name "Net-(IC113-Pad2)") (class "Default")
      (node (ref "IC113") (pin "2") (pinfunction "2_2") (pintype "passive"))
      (node (ref "IC114") (pin "2") (pinfunction "2_2") (pintype "passive"))
      (node (ref "IC115") (pin "2") (pinfunction "2_2") (pintype "passive"))
      (node (ref "IC116") (pin "2") (pinfunction "2_2") (pintype "passive"))
    )
    (net (code "682") (name "Net-(IC113-Pad3)") (class "Default")
      (node (ref "IC113") (pin "3") (pinfunction "3_3") (pintype "passive"))
      (node (ref "IC114") (pin "3") (pinfunction "3_3") (pintype "passive"))
      (node (ref "IC115") (pin "3") (pinfunction "3_3") (pintype "passive"))
      (node (ref "IC116") (pin "3") (pinfunction "3_3") (pintype "passive"))
    )
    (net (code "683") (name "Net-(IC113-Pad4)") (class "Default")
      (node (ref "IC113") (pin "4") (pinfunction "4_4") (pintype "passive"))
      (node (ref "IC114") (pin "4") (pinfunction "4_4") (pintype "passive"))
      (node (ref "IC115") (pin "4") (pinfunction "4_4") (pintype "passive"))
      (node (ref "IC116") (pin "4") (pinfunction "4_4") (pintype "passive"))
    )
    (net (code "684") (name "Net-(IC113-Pad5)") (class "Default")
      (node (ref "IC113") (pin "5") (pinfunction "5_5") (pintype "passive"))
      (node (ref "IC114") (pin "5") (pinfunction "5_5") (pintype "passive"))
      (node (ref "IC115") (pin "5") (pinfunction "5_5") (pintype "passive"))
      (node (ref "IC116") (pin "5") (pinfunction "5_5") (pintype "passive"))
    )
    (net (code "685") (name "Net-(IC113-Pad6)") (class "Default")
      (node (ref "IC113") (pin "6") (pinfunction "6_6") (pintype "passive"))
      (node (ref "IC114") (pin "6") (pinfunction "6_6") (pintype "passive"))
      (node (ref "IC115") (pin "6") (pinfunction "6_6") (pintype "passive"))
      (node (ref "IC116") (pin "6") (pinfunction "6_6") (pintype "passive"))
    )
    (net (code "686") (name "Net-(IC113-Pad7)") (class "Default")
      (node (ref "IC113") (pin "7") (pinfunction "7_7") (pintype "passive"))
      (node (ref "IC114") (pin "7") (pinfunction "7_7") (pintype "passive"))
      (node (ref "IC115") (pin "7") (pinfunction "7_7") (pintype "passive"))
      (node (ref "IC116") (pin "7") (pinfunction "7_7") (pintype "passive"))
    )
    (net (code "687") (name "Net-(IC113-Pad8)") (class "Default")
      (node (ref "IC113") (pin "8") (pinfunction "8_8") (pintype "passive"))
      (node (ref "IC114") (pin "8") (pinfunction "8_8") (pintype "passive"))
      (node (ref "IC115") (pin "8") (pinfunction "8_8") (pintype "passive"))
      (node (ref "IC116") (pin "8") (pinfunction "8_8") (pintype "passive"))
    )
    (net (code "688") (name "Net-(IC113-Pad9)") (class "Default")
      (node (ref "IC113") (pin "9") (pinfunction "9_9") (pintype "passive"))
      (node (ref "IC114") (pin "9") (pinfunction "9_9") (pintype "passive"))
      (node (ref "IC115") (pin "9") (pinfunction "9_9") (pintype "passive"))
      (node (ref "IC116") (pin "9") (pinfunction "9_9") (pintype "passive"))
    )
    (net (code "689") (name "Net-(IC113-Pad10)") (class "Default")
      (node (ref "IC113") (pin "10") (pinfunction "10_10") (pintype "passive"))
      (node (ref "IC114") (pin "10") (pinfunction "10_10") (pintype "passive"))
      (node (ref "IC115") (pin "10") (pinfunction "10_10") (pintype "passive"))
      (node (ref "IC116") (pin "10") (pinfunction "10_10") (pintype "passive"))
    )
    (net (code "690") (name "Net-(IC113-Pad11)") (class "Default")
      (node (ref "IC113") (pin "11") (pinfunction "11_11") (pintype "passive"))
      (node (ref "IC114") (pin "11") (pinfunction "11_11") (pintype "passive"))
      (node (ref "IC115") (pin "11") (pinfunction "11_11") (pintype "passive"))
      (node (ref "IC116") (pin "11") (pinfunction "11_11") (pintype "passive"))
    )
    (net (code "691") (name "Net-(IC113-Pad12)") (class "Default")
      (node (ref "IC113") (pin "12") (pinfunction "12_12") (pintype "passive"))
      (node (ref "IC114") (pin "12") (pinfunction "12_12") (pintype "passive"))
      (node (ref "IC115") (pin "12") (pinfunction "12_12") (pintype "passive"))
      (node (ref "IC116") (pin "12") (pinfunction "12_12") (pintype "passive"))
    )
    (net (code "692") (name "Net-(IC113-Pad13)") (class "Default")
      (node (ref "IC113") (pin "13") (pinfunction "13_13") (pintype "passive"))
      (node (ref "IC114") (pin "13") (pinfunction "13_13") (pintype "passive"))
      (node (ref "IC115") (pin "13") (pinfunction "13_13") (pintype "passive"))
      (node (ref "IC116") (pin "13") (pinfunction "13_13") (pintype "passive"))
    )
    (net (code "693") (name "Net-(IC113-Pad14)") (class "Default")
      (node (ref "IC113") (pin "14") (pinfunction "14_14") (pintype "passive"))
      (node (ref "IC114") (pin "14") (pinfunction "14_14") (pintype "passive"))
      (node (ref "IC115") (pin "14") (pinfunction "14_14") (pintype "passive"))
      (node (ref "IC116") (pin "14") (pinfunction "14_14") (pintype "passive"))
    )
    (net (code "694") (name "Net-(IC113-Pad15)") (class "Default")
      (node (ref "IC113") (pin "15") (pinfunction "15_15") (pintype "passive"))
      (node (ref "IC114") (pin "15") (pinfunction "15_15") (pintype "passive"))
      (node (ref "IC115") (pin "15") (pinfunction "15_15") (pintype "passive"))
      (node (ref "IC116") (pin "15") (pinfunction "15_15") (pintype "passive"))
    )
    (net (code "695") (name "Net-(IC113-Pad16)") (class "Default")
      (node (ref "IC113") (pin "16") (pinfunction "16_16") (pintype "passive"))
      (node (ref "IC114") (pin "16") (pinfunction "16_16") (pintype "passive"))
      (node (ref "IC115") (pin "16") (pinfunction "16_16") (pintype "passive"))
      (node (ref "IC116") (pin "16") (pinfunction "16_16") (pintype "passive"))
    )
    (net (code "696") (name "Net-(IC113-Pad17)") (class "Default")
      (node (ref "IC113") (pin "17") (pinfunction "17_17") (pintype "passive"))
      (node (ref "IC114") (pin "17") (pinfunction "17_17") (pintype "passive"))
      (node (ref "IC115") (pin "17") (pinfunction "17_17") (pintype "passive"))
      (node (ref "IC116") (pin "17") (pinfunction "17_17") (pintype "passive"))
    )
    (net (code "697") (name "Net-(IC113-Pad18)") (class "Default")
      (node (ref "IC113") (pin "18") (pinfunction "18_18") (pintype "passive"))
      (node (ref "IC114") (pin "18") (pinfunction "18_18") (pintype "passive"))
      (node (ref "IC115") (pin "18") (pinfunction "18_18") (pintype "passive"))
      (node (ref "IC116") (pin "18") (pinfunction "18_18") (pintype "passive"))
    )
    (net (code "698") (name "Net-(IC113-Pad19)") (class "Default")
      (node (ref "IC113") (pin "19") (pinfunction "19_19") (pintype "passive"))
      (node (ref "IC114") (pin "19") (pinfunction "19_19") (pintype "passive"))
      (node (ref "IC115") (pin "19") (pinfunction "19_19") (pintype "passive"))
      (node (ref "IC116") (pin "19") (pinfunction "19_19") (pintype "passive"))
    )
    (net (code "699") (name "Net-(IC113-Pad20)") (class "Default")
      (node (ref "IC113") (pin "20") (pinfunction "20_20") (pintype "passive"))
      (node (ref "IC114") (pin "20") (pinfunction "20_20") (pintype "passive"))
      (node (ref "IC115") (pin "20") (pinfunction "20_20") (pintype "passive"))
      (node (ref "IC116") (pin "20") (pinfunction "20_20") (pintype "passive"))
    )
    (net (code "700") (name "Net-(IC113-Pad21)") (class "Default")
      (node (ref "IC113") (pin "21") (pinfunction "21_21") (pintype "passive"))
      (node (ref "IC114") (pin "21") (pinfunction "21_21") (pintype "passive"))
      (node (ref "IC115") (pin "21") (pinfunction "21_21") (pintype "passive"))
      (node (ref "IC116") (pin "21") (pinfunction "21_21") (pintype "passive"))
    )
    (net (code "701") (name "Net-(IC113-Pad22)") (class "Default")
      (node (ref "IC113") (pin "22") (pinfunction "22_22") (pintype "passive"))
      (node (ref "IC114") (pin "22") (pinfunction "22_22") (pintype "passive"))
      (node (ref "IC115") (pin "22") (pinfunction "22_22") (pintype "passive"))
      (node (ref "IC116") (pin "22") (pinfunction "22_22") (pintype "passive"))
    )
    (net (code "702") (name "Net-(IC113-Pad23)") (class "Default")
      (node (ref "IC113") (pin "23") (pinfunction "23_23") (pintype "passive"))
      (node (ref "IC114") (pin "23") (pinfunction "23_23") (pintype "passive"))
      (node (ref "IC115") (pin "23") (pinfunction "23_23") (pintype "passive"))
      (node (ref "IC116") (pin "23") (pinfunction "23_23") (pintype "passive"))
    )
    (net (code "703") (name "Net-(IC113-Pad24)") (class "Default")
      (node (ref "IC113") (pin "24") (pinfunction "24_24") (pintype "passive"))
      (node (ref "IC114") (pin "24") (pinfunction "24_24") (pintype "passive"))
      (node (ref "IC115") (pin "24") (pinfunction "24_24") (pintype "passive"))
      (node (ref "IC116") (pin "24") (pinfunction "24_24") (pintype "passive"))
    )
    (net (code "704") (name "Net-(IC117-Pad1)") (class "Default")
      (node (ref "IC117") (pin "1") (pinfunction "1_1") (pintype "passive"))
      (node (ref "IC118") (pin "1") (pinfunction "1_1") (pintype "passive"))
      (node (ref "IC119") (pin "1") (pinfunction "1_1") (pintype "passive"))
      (node (ref "IC120") (pin "1") (pinfunction "1_1") (pintype "passive"))
    )
    (net (code "705") (name "Net-(IC117-Pad2)") (class "Default")
      (node (ref "IC117") (pin "2") (pinfunction "2_2") (pintype "passive"))
      (node (ref "IC118") (pin "2") (pinfunction "2_2") (pintype "passive"))
      (node (ref "IC119") (pin "2") (pinfunction "2_2") (pintype "passive"))
      (node (ref "IC120") (pin "2") (pinfunction "2_2") (pintype "passive"))
    )
    (net (code "706") (name "Net-(IC117-Pad3)") (class "Default")
      (node (ref "IC117") (pin "3") (pinfunction "3_3") (pintype "passive"))
      (node (ref "IC118") (pin "3") (pinfunction "3_3") (pintype "passive"))
      (node (ref "IC119") (pin "3") (pinfunction "3_3") (pintype "passive"))
      (node (ref "IC120") (pin "3") (pinfunction "3_3") (pintype "passive"))
    )
    (net (code "707") (name "Net-(IC117-Pad4)") (class "Default")
      (node (ref "IC117") (pin "4") (pinfunction "4_4") (pintype "passive"))
      (node (ref "IC118") (pin "4") (pinfunction "4_4") (pintype "passive"))
      (node (ref "IC119") (pin "4") (pinfunction "4_4") (pintype "passive"))
      (node (ref "IC120") (pin "4") (pinfunction "4_4") (pintype "passive"))
    )
    (net (code "708") (name "Net-(IC117-Pad5)") (class "Default")
      (node (ref "IC117") (pin "5") (pinfunction "5_5") (pintype "passive"))
      (node (ref "IC118") (pin "5") (pinfunction "5_5") (pintype "passive"))
      (node (ref "IC119") (pin "5") (pinfunction "5_5") (pintype "passive"))
      (node (ref "IC120") (pin "5") (pinfunction "5_5") (pintype "passive"))
    )
    (net (code "709") (name "Net-(IC117-Pad6)") (class "Default")
      (node (ref "IC117") (pin "6") (pinfunction "6_6") (pintype "passive"))
      (node (ref "IC118") (pin "6") (pinfunction "6_6") (pintype "passive"))
      (node (ref "IC119") (pin "6") (pinfunction "6_6") (pintype "passive"))
      (node (ref "IC120") (pin "6") (pinfunction "6_6") (pintype "passive"))
    )
    (net (code "710") (name "Net-(IC117-Pad7)") (class "Default")
      (node (ref "IC117") (pin "7") (pinfunction "7_7") (pintype "passive"))
      (node (ref "IC118") (pin "7") (pinfunction "7_7") (pintype "passive"))
      (node (ref "IC119") (pin "7") (pinfunction "7_7") (pintype "passive"))
      (node (ref "IC120") (pin "7") (pinfunction "7_7") (pintype "passive"))
    )
    (net (code "711") (name "Net-(IC117-Pad8)") (class "Default")
      (node (ref "IC117") (pin "8") (pinfunction "8_8") (pintype "passive"))
      (node (ref "IC118") (pin "8") (pinfunction "8_8") (pintype "passive"))
      (node (ref "IC119") (pin "8") (pinfunction "8_8") (pintype "passive"))
      (node (ref "IC120") (pin "8") (pinfunction "8_8") (pintype "passive"))
    )
    (net (code "712") (name "Net-(IC117-Pad9)") (class "Default")
      (node (ref "IC117") (pin "9") (pinfunction "9_9") (pintype "passive"))
      (node (ref "IC118") (pin "9") (pinfunction "9_9") (pintype "passive"))
      (node (ref "IC119") (pin "9") (pinfunction "9_9") (pintype "passive"))
      (node (ref "IC120") (pin "9") (pinfunction "9_9") (pintype "passive"))
    )
    (net (code "713") (name "Net-(IC117-Pad10)") (class "Default")
      (node (ref "IC117") (pin "10") (pinfunction "10_10") (pintype "passive"))
      (node (ref "IC118") (pin "10") (pinfunction "10_10") (pintype "passive"))
      (node (ref "IC119") (pin "10") (pinfunction "10_10") (pintype "passive"))
      (node (ref "IC120") (pin "10") (pinfunction "10_10") (pintype "passive"))
    )
    (net (code "714") (name "Net-(IC117-Pad11)") (class "Default")
      (node (ref "IC117") (pin "11") (pinfunction "11_11") (pintype "passive"))
      (node (ref "IC118") (pin "11") (pinfunction "11_11") (pintype "passive"))
      (node (ref "IC119") (pin "11") (pinfunction "11_11") (pintype "passive"))
      (node (ref "IC120") (pin "11") (pinfunction "11_11") (pintype "passive"))
    )
    (net (code "715") (name "Net-(IC117-Pad12)") (class "Default")
      (node (ref "IC117") (pin "12") (pinfunction "12_12") (pintype "passive"))
      (node (ref "IC118") (pin "12") (pinfunction "12_12") (pintype "passive"))
      (node (ref "IC119") (pin "12") (pinfunction "12_12") (pintype "passive"))
      (node (ref "IC120") (pin "12") (pinfunction "12_12") (pintype "passive"))
    )
    (net (code "716") (name "Net-(IC117-Pad13)") (class "Default")
      (node (ref "IC117") (pin "13") (pinfunction "13_13") (pintype "passive"))
      (node (ref "IC118") (pin "13") (pinfunction "13_13") (pintype "passive"))
      (node (ref "IC119") (pin "13") (pinfunction "13_13") (pintype "passive"))
      (node (ref "IC120") (pin "13") (pinfunction "13_13") (pintype "passive"))
    )
    (net (code "717") (name "Net-(IC117-Pad14)") (class "Default")
      (node (ref "IC117") (pin "14") (pinfunction "14_14") (pintype "passive"))
      (node (ref "IC118") (pin "14") (pinfunction "14_14") (pintype "passive"))
      (node (ref "IC119") (pin "14") (pinfunction "14_14") (pintype "passive"))
      (node (ref "IC120") (pin "14") (pinfunction "14_14") (pintype "passive"))
    )
    (net (code "718") (name "Net-(IC117-Pad15)") (class "Default")
      (node (ref "IC117") (pin "15") (pinfunction "15_15") (pintype "passive"))
      (node (ref "IC118") (pin "15") (pinfunction "15_15") (pintype "passive"))
      (node (ref "IC119") (pin "15") (pinfunction "15_15") (pintype "passive"))
      (node (ref "IC120") (pin "15") (pinfunction "15_15") (pintype "passive"))
    )
    (net (code "719") (name "Net-(IC117-Pad16)") (class "Default")
      (node (ref "IC117") (pin "16") (pinfunction "16_16") (pintype "passive"))
      (node (ref "IC118") (pin "16") (pinfunction "16_16") (pintype "passive"))
      (node (ref "IC119") (pin "16") (pinfunction "16_16") (pintype "passive"))
      (node (ref "IC120") (pin "16") (pinfunction "16_16") (pintype "passive"))
    )
    (net (code "720") (name "Net-(IC117-Pad17)") (class "Default")
      (node (ref "IC117") (pin "17") (pinfunction "17_17") (pintype "passive"))
      (node (ref "IC118") (pin "17") (pinfunction "17_17") (pintype "passive"))
      (node (ref "IC119") (pin "17") (pinfunction "17_17") (pintype "passive"))
      (node (ref "IC120") (pin "17") (pinfunction "17_17") (pintype "passive"))
    )
    (net (code "721") (name "Net-(IC117-Pad18)") (class "Default")
      (node (ref "IC117") (pin "18") (pinfunction "18_18") (pintype "passive"))
      (node (ref "IC118") (pin "18") (pinfunction "18_18") (pintype "passive"))
      (node (ref "IC119") (pin "18") (pinfunction "18_18") (pintype "passive"))
      (node (ref "IC120") (pin "18") (pinfunction "18_18") (pintype "passive"))
    )
    (net (code "722") (name "Net-(IC117-Pad19)") (class "Default")
      (node (ref "IC117") (pin "19") (pinfunction "19_19") (pintype "passive"))
      (node (ref "IC118") (pin "19") (pinfunction "19_19") (pintype "passive"))
      (node (ref "IC119") (pin "19") (pinfunction "19_19") (pintype "passive"))
      (node (ref "IC120") (pin "19") (pinfunction "19_19") (pintype "passive"))
    )
    (net (code "723") (name "Net-(IC117-Pad20)") (class "Default")
      (node (ref "IC117") (pin "20") (pinfunction "20_20") (pintype "passive"))
      (node (ref "IC118") (pin "20") (pinfunction "20_20") (pintype "passive"))
      (node (ref "IC119") (pin "20") (pinfunction "20_20") (pintype "passive"))
      (node (ref "IC120") (pin "20") (pinfunction "20_20") (pintype "passive"))
    )
    (net (code "724") (name "Net-(IC117-Pad21)") (class "Default")
      (node (ref "IC117") (pin "21") (pinfunction "21_21") (pintype "passive"))
      (node (ref "IC118") (pin "21") (pinfunction "21_21") (pintype "passive"))
      (node (ref "IC119") (pin "21") (pinfunction "21_21") (pintype "passive"))
      (node (ref "IC120") (pin "21") (pinfunction "21_21") (pintype "passive"))
    )
    (net (code "725") (name "Net-(IC117-Pad22)") (class "Default")
      (node (ref "IC117") (pin "22") (pinfunction "22_22") (pintype "passive"))
      (node (ref "IC118") (pin "22") (pinfunction "22_22") (pintype "passive"))
      (node (ref "IC119") (pin "22") (pinfunction "22_22") (pintype "passive"))
      (node (ref "IC120") (pin "22") (pinfunction "22_22") (pintype "passive"))
    )
    (net (code "726") (name "Net-(IC117-Pad23)") (class "Default")
      (node (ref "IC117") (pin "23") (pinfunction "23_23") (pintype "passive"))
      (node (ref "IC118") (pin "23") (pinfunction "23_23") (pintype "passive"))
      (node (ref "IC119") (pin "23") (pinfunction "23_23") (pintype "passive"))
      (node (ref "IC120") (pin "23") (pinfunction "23_23") (pintype "passive"))
    )
    (net (code "727") (name "Net-(IC117-Pad24)") (class "Default")
      (node (ref "IC117") (pin "24") (pinfunction "24_24") (pintype "passive"))
      (node (ref "IC118") (pin "24") (pinfunction "24_24") (pintype "passive"))
      (node (ref "IC119") (pin "24") (pinfunction "24_24") (pintype "passive"))
      (node (ref "IC120") (pin "24") (pinfunction "24_24") (pintype "passive"))
    )
    (net (code "728") (name "Net-(IC121-Pad1)") (class "Default")
      (node (ref "IC121") (pin "1") (pinfunction "1_1") (pintype "passive"))
      (node (ref "IC122") (pin "1") (pinfunction "1_1") (pintype "passive"))
      (node (ref "IC123") (pin "1") (pinfunction "1_1") (pintype "passive"))
      (node (ref "IC124") (pin "1") (pinfunction "1_1") (pintype "passive"))
    )
    (net (code "729") (name "Net-(IC121-Pad2)") (class "Default")
      (node (ref "IC121") (pin "2") (pinfunction "2_2") (pintype "passive"))
      (node (ref "IC122") (pin "2") (pinfunction "2_2") (pintype "passive"))
      (node (ref "IC123") (pin "2") (pinfunction "2_2") (pintype "passive"))
      (node (ref "IC124") (pin "2") (pinfunction "2_2") (pintype "passive"))
    )
    (net (code "730") (name "Net-(IC121-Pad3)") (class "Default")
      (node (ref "IC121") (pin "3") (pinfunction "3_3") (pintype "passive"))
      (node (ref "IC122") (pin "3") (pinfunction "3_3") (pintype "passive"))
      (node (ref "IC123") (pin "3") (pinfunction "3_3") (pintype "passive"))
      (node (ref "IC124") (pin "3") (pinfunction "3_3") (pintype "passive"))
    )
    (net (code "731") (name "Net-(IC121-Pad4)") (class "Default")
      (node (ref "IC121") (pin "4") (pinfunction "4_4") (pintype "passive"))
      (node (ref "IC122") (pin "4") (pinfunction "4_4") (pintype "passive"))
      (node (ref "IC123") (pin "4") (pinfunction "4_4") (pintype "passive"))
      (node (ref "IC124") (pin "4") (pinfunction "4_4") (pintype "passive"))
    )
    (net (code "732") (name "Net-(IC121-Pad5)") (class "Default")
      (node (ref "IC121") (pin "5") (pinfunction "5_5") (pintype "passive"))
      (node (ref "IC122") (pin "5") (pinfunction "5_5") (pintype "passive"))
      (node (ref "IC123") (pin "5") (pinfunction "5_5") (pintype "passive"))
      (node (ref "IC124") (pin "5") (pinfunction "5_5") (pintype "passive"))
    )
    (net (code "733") (name "Net-(IC121-Pad6)") (class "Default")
      (node (ref "IC121") (pin "6") (pinfunction "6_6") (pintype "passive"))
      (node (ref "IC122") (pin "6") (pinfunction "6_6") (pintype "passive"))
      (node (ref "IC123") (pin "6") (pinfunction "6_6") (pintype "passive"))
      (node (ref "IC124") (pin "6") (pinfunction "6_6") (pintype "passive"))
    )
    (net (code "734") (name "Net-(IC121-Pad7)") (class "Default")
      (node (ref "IC121") (pin "7") (pinfunction "7_7") (pintype "passive"))
      (node (ref "IC122") (pin "7") (pinfunction "7_7") (pintype "passive"))
      (node (ref "IC123") (pin "7") (pinfunction "7_7") (pintype "passive"))
      (node (ref "IC124") (pin "7") (pinfunction "7_7") (pintype "passive"))
    )
    (net (code "735") (name "Net-(IC121-Pad8)") (class "Default")
      (node (ref "IC121") (pin "8") (pinfunction "8_8") (pintype "passive"))
      (node (ref "IC122") (pin "8") (pinfunction "8_8") (pintype "passive"))
      (node (ref "IC123") (pin "8") (pinfunction "8_8") (pintype "passive"))
      (node (ref "IC124") (pin "8") (pinfunction "8_8") (pintype "passive"))
    )
    (net (code "736") (name "Net-(IC121-Pad9)") (class "Default")
      (node (ref "IC121") (pin "9") (pinfunction "9_9") (pintype "passive"))
      (node (ref "IC122") (pin "9") (pinfunction "9_9") (pintype "passive"))
      (node (ref "IC123") (pin "9") (pinfunction "9_9") (pintype "passive"))
      (node (ref "IC124") (pin "9") (pinfunction "9_9") (pintype "passive"))
    )
    (net (code "737") (name "Net-(IC121-Pad10)") (class "Default")
      (node (ref "IC121") (pin "10") (pinfunction "10_10") (pintype "passive"))
      (node (ref "IC122") (pin "10") (pinfunction "10_10") (pintype "passive"))
      (node (ref "IC123") (pin "10") (pinfunction "10_10") (pintype "passive"))
      (node (ref "IC124") (pin "10") (pinfunction "10_10") (pintype "passive"))
    )
    (net (code "738") (name "Net-(IC121-Pad11)") (class "Default")
      (node (ref "IC121") (pin "11") (pinfunction "11_11") (pintype "passive"))
      (node (ref "IC122") (pin "11") (pinfunction "11_11") (pintype "passive"))
      (node (ref "IC123") (pin "11") (pinfunction "11_11") (pintype "passive"))
      (node (ref "IC124") (pin "11") (pinfunction "11_11") (pintype "passive"))
    )
    (net (code "739") (name "Net-(IC121-Pad12)") (class "Default")
      (node (ref "IC121") (pin "12") (pinfunction "12_12") (pintype "passive"))
      (node (ref "IC122") (pin "12") (pinfunction "12_12") (pintype "passive"))
      (node (ref "IC123") (pin "12") (pinfunction "12_12") (pintype "passive"))
      (node (ref "IC124") (pin "12") (pinfunction "12_12") (pintype "passive"))
    )
    (net (code "740") (name "Net-(IC121-Pad13)") (class "Default")
      (node (ref "IC121") (pin "13") (pinfunction "13_13") (pintype "passive"))
      (node (ref "IC122") (pin "13") (pinfunction "13_13") (pintype "passive"))
      (node (ref "IC123") (pin "13") (pinfunction "13_13") (pintype "passive"))
      (node (ref "IC124") (pin "13") (pinfunction "13_13") (pintype "passive"))
    )
    (net (code "741") (name "Net-(IC121-Pad14)") (class "Default")
      (node (ref "IC121") (pin "14") (pinfunction "14_14") (pintype "passive"))
      (node (ref "IC122") (pin "14") (pinfunction "14_14") (pintype "passive"))
      (node (ref "IC123") (pin "14") (pinfunction "14_14") (pintype "passive"))
      (node (ref "IC124") (pin "14") (pinfunction "14_14") (pintype "passive"))
    )
    (net (code "742") (name "Net-(IC121-Pad15)") (class "Default")
      (node (ref "IC121") (pin "15") (pinfunction "15_15") (pintype "passive"))
      (node (ref "IC122") (pin "15") (pinfunction "15_15") (pintype "passive"))
      (node (ref "IC123") (pin "15") (pinfunction "15_15") (pintype "passive"))
      (node (ref "IC124") (pin "15") (pinfunction "15_15") (pintype "passive"))
    )
    (net (code "743") (name "Net-(IC121-Pad16)") (class "Default")
      (node (ref "IC121") (pin "16") (pinfunction "16_16") (pintype "passive"))
      (node (ref "IC122") (pin "16") (pinfunction "16_16") (pintype "passive"))
      (node (ref "IC123") (pin "16") (pinfunction "16_16") (pintype "passive"))
      (node (ref "IC124") (pin "16") (pinfunction "16_16") (pintype "passive"))
    )
    (net (code "744") (name "Net-(IC121-Pad17)") (class "Default")
      (node (ref "IC121") (pin "17") (pinfunction "17_17") (pintype "passive"))
      (node (ref "IC122") (pin "17") (pinfunction "17_17") (pintype "passive"))
      (node (ref "IC123") (pin "17") (pinfunction "17_17") (pintype "passive"))
      (node (ref "IC124") (pin "17") (pinfunction "17_17") (pintype "passive"))
    )
    (net (code "745") (name "Net-(IC121-Pad18)") (class "Default")
      (node (ref "IC121") (pin "18") (pinfunction "18_18") (pintype "passive"))
      (node (ref "IC122") (pin "18") (pinfunction "18_18") (pintype "passive"))
      (node (ref "IC123") (pin "18") (pinfunction "18_18") (pintype "passive"))
      (node (ref "IC124") (pin "18") (pinfunction "18_18") (pintype "passive"))
    )
    (net (code "746") (name "Net-(IC121-Pad19)") (class "Default")
      (node (ref "IC121") (pin "19") (pinfunction "19_19") (pintype "passive"))
      (node (ref "IC122") (pin "19") (pinfunction "19_19") (pintype "passive"))
      (node (ref "IC123") (pin "19") (pinfunction "19_19") (pintype "passive"))
      (node (ref "IC124") (pin "19") (pinfunction "19_19") (pintype "passive"))
    )
    (net (code "747") (name "Net-(IC121-Pad20)") (class "Default")
      (node (ref "IC121") (pin "20") (pinfunction "20_20") (pintype "passive"))
      (node (ref "IC122") (pin "20") (pinfunction "20_20") (pintype "passive"))
      (node (ref "IC123") (pin "20") (pinfunction "20_20") (pintype "passive"))
      (node (ref "IC124") (pin "20") (pinfunction "20_20") (pintype "passive"))
    )
    (net (code "748") (name "Net-(IC121-Pad21)") (class "Default")
      (node (ref "IC121") (pin "21") (pinfunction "21_21") (pintype "passive"))
      (node (ref "IC122") (pin "21") (pinfunction "21_21") (pintype "passive"))
      (node (ref "IC123") (pin "21") (pinfunction "21_21") (pintype "passive"))
      (node (ref "IC124") (pin "21") (pinfunction "21_21") (pintype "passive"))
    )
    (net (code "749") (name "Net-(IC121-Pad22)") (class "Default")
      (node (ref "IC121") (pin "22") (pinfunction "22_22") (pintype "passive"))
      (node (ref "IC122") (pin "22") (pinfunction "22_22") (pintype "passive"))
      (node (ref "IC123") (pin "22") (pinfunction "22_22") (pintype "passive"))
      (node (ref "IC124") (pin "22") (pinfunction "22_22") (pintype "passive"))
    )
    (net (code "750") (name "Net-(IC121-Pad23)") (class "Default")
      (node (ref "IC121") (pin "23") (pinfunction "23_23") (pintype "passive"))
      (node (ref "IC122") (pin "23") (pinfunction "23_23") (pintype "passive"))
      (node (ref "IC123") (pin "23") (pinfunction "23_23") (pintype "passive"))
      (node (ref "IC124") (pin "23") (pinfunction "23_23") (pintype "passive"))
    )
    (net (code "751") (name "Net-(IC121-Pad24)") (class "Default")
      (node (ref "IC121") (pin "24") (pinfunction "24_24") (pintype "passive"))
      (node (ref "IC122") (pin "24") (pinfunction "24_24") (pintype "passive"))
      (node (ref "IC123") (pin "24") (pinfunction "24_24") (pintype "passive"))
      (node (ref "IC124") (pin "24") (pinfunction "24_24") (pintype "passive"))
    )
    (net (code "752") (name "Net-(IC125-Pad1)") (class "Default")
      (node (ref "IC125") (pin "1") (pinfunction "1_1") (pintype "passive"))
      (node (ref "IC126") (pin "1") (pinfunction "1_1") (pintype "passive"))
      (node (ref "IC127") (pin "1") (pinfunction "1_1") (pintype "passive"))
      (node (ref "IC128") (pin "1") (pinfunction "1_1") (pintype "passive"))
    )
    (net (code "753") (name "Net-(IC125-Pad2)") (class "Default")
      (node (ref "IC125") (pin "2") (pinfunction "2_2") (pintype "passive"))
      (node (ref "IC126") (pin "2") (pinfunction "2_2") (pintype "passive"))
      (node (ref "IC127") (pin "2") (pinfunction "2_2") (pintype "passive"))
      (node (ref "IC128") (pin "2") (pinfunction "2_2") (pintype "passive"))
    )
    (net (code "754") (name "Net-(IC125-Pad3)") (class "Default")
      (node (ref "IC125") (pin "3") (pinfunction "3_3") (pintype "passive"))
      (node (ref "IC126") (pin "3") (pinfunction "3_3") (pintype "passive"))
      (node (ref "IC127") (pin "3") (pinfunction "3_3") (pintype "passive"))
      (node (ref "IC128") (pin "3") (pinfunction "3_3") (pintype "passive"))
    )
    (net (code "755") (name "Net-(IC125-Pad4)") (class "Default")
      (node (ref "IC125") (pin "4") (pinfunction "4_4") (pintype "passive"))
      (node (ref "IC126") (pin "4") (pinfunction "4_4") (pintype "passive"))
      (node (ref "IC127") (pin "4") (pinfunction "4_4") (pintype "passive"))
      (node (ref "IC128") (pin "4") (pinfunction "4_4") (pintype "passive"))
    )
    (net (code "756") (name "Net-(IC125-Pad5)") (class "Default")
      (node (ref "IC125") (pin "5") (pinfunction "5_5") (pintype "passive"))
      (node (ref "IC126") (pin "5") (pinfunction "5_5") (pintype "passive"))
      (node (ref "IC127") (pin "5") (pinfunction "5_5") (pintype "passive"))
      (node (ref "IC128") (pin "5") (pinfunction "5_5") (pintype "passive"))
    )
    (net (code "757") (name "Net-(IC125-Pad6)") (class "Default")
      (node (ref "IC125") (pin "6") (pinfunction "6_6") (pintype "passive"))
      (node (ref "IC126") (pin "6") (pinfunction "6_6") (pintype "passive"))
      (node (ref "IC127") (pin "6") (pinfunction "6_6") (pintype "passive"))
      (node (ref "IC128") (pin "6") (pinfunction "6_6") (pintype "passive"))
    )
    (net (code "758") (name "Net-(IC125-Pad7)") (class "Default")
      (node (ref "IC125") (pin "7") (pinfunction "7_7") (pintype "passive"))
      (node (ref "IC126") (pin "7") (pinfunction "7_7") (pintype "passive"))
      (node (ref "IC127") (pin "7") (pinfunction "7_7") (pintype "passive"))
      (node (ref "IC128") (pin "7") (pinfunction "7_7") (pintype "passive"))
    )
    (net (code "759") (name "Net-(IC125-Pad8)") (class "Default")
      (node (ref "IC125") (pin "8") (pinfunction "8_8") (pintype "passive"))
      (node (ref "IC126") (pin "8") (pinfunction "8_8") (pintype "passive"))
      (node (ref "IC127") (pin "8") (pinfunction "8_8") (pintype "passive"))
      (node (ref "IC128") (pin "8") (pinfunction "8_8") (pintype "passive"))
    )
    (net (code "760") (name "Net-(IC125-Pad9)") (class "Default")
      (node (ref "IC125") (pin "9") (pinfunction "9_9") (pintype "passive"))
      (node (ref "IC126") (pin "9") (pinfunction "9_9") (pintype "passive"))
      (node (ref "IC127") (pin "9") (pinfunction "9_9") (pintype "passive"))
      (node (ref "IC128") (pin "9") (pinfunction "9_9") (pintype "passive"))
    )
    (net (code "761") (name "Net-(IC125-Pad10)") (class "Default")
      (node (ref "IC125") (pin "10") (pinfunction "10_10") (pintype "passive"))
      (node (ref "IC126") (pin "10") (pinfunction "10_10") (pintype "passive"))
      (node (ref "IC127") (pin "10") (pinfunction "10_10") (pintype "passive"))
      (node (ref "IC128") (pin "10") (pinfunction "10_10") (pintype "passive"))
    )
    (net (code "762") (name "Net-(IC125-Pad11)") (class "Default")
      (node (ref "IC125") (pin "11") (pinfunction "11_11") (pintype "passive"))
      (node (ref "IC126") (pin "11") (pinfunction "11_11") (pintype "passive"))
      (node (ref "IC127") (pin "11") (pinfunction "11_11") (pintype "passive"))
      (node (ref "IC128") (pin "11") (pinfunction "11_11") (pintype "passive"))
    )
    (net (code "763") (name "Net-(IC125-Pad12)") (class "Default")
      (node (ref "IC125") (pin "12") (pinfunction "12_12") (pintype "passive"))
      (node (ref "IC126") (pin "12") (pinfunction "12_12") (pintype "passive"))
      (node (ref "IC127") (pin "12") (pinfunction "12_12") (pintype "passive"))
      (node (ref "IC128") (pin "12") (pinfunction "12_12") (pintype "passive"))
    )
    (net (code "764") (name "Net-(IC125-Pad13)") (class "Default")
      (node (ref "IC125") (pin "13") (pinfunction "13_13") (pintype "passive"))
      (node (ref "IC126") (pin "13") (pinfunction "13_13") (pintype "passive"))
      (node (ref "IC127") (pin "13") (pinfunction "13_13") (pintype "passive"))
      (node (ref "IC128") (pin "13") (pinfunction "13_13") (pintype "passive"))
    )
    (net (code "765") (name "Net-(IC125-Pad14)") (class "Default")
      (node (ref "IC125") (pin "14") (pinfunction "14_14") (pintype "passive"))
      (node (ref "IC126") (pin "14") (pinfunction "14_14") (pintype "passive"))
      (node (ref "IC127") (pin "14") (pinfunction "14_14") (pintype "passive"))
      (node (ref "IC128") (pin "14") (pinfunction "14_14") (pintype "passive"))
    )
    (net (code "766") (name "Net-(IC125-Pad15)") (class "Default")
      (node (ref "IC125") (pin "15") (pinfunction "15_15") (pintype "passive"))
      (node (ref "IC126") (pin "15") (pinfunction "15_15") (pintype "passive"))
      (node (ref "IC127") (pin "15") (pinfunction "15_15") (pintype "passive"))
      (node (ref "IC128") (pin "15") (pinfunction "15_15") (pintype "passive"))
    )
    (net (code "767") (name "Net-(IC125-Pad16)") (class "Default")
      (node (ref "IC125") (pin "16") (pinfunction "16_16") (pintype "passive"))
      (node (ref "IC126") (pin "16") (pinfunction "16_16") (pintype "passive"))
      (node (ref "IC127") (pin "16") (pinfunction "16_16") (pintype "passive"))
      (node (ref "IC128") (pin "16") (pinfunction "16_16") (pintype "passive"))
    )
    (net (code "768") (name "Net-(IC125-Pad17)") (class "Default")
      (node (ref "IC125") (pin "17") (pinfunction "17_17") (pintype "passive"))
      (node (ref "IC126") (pin "17") (pinfunction "17_17") (pintype "passive"))
      (node (ref "IC127") (pin "17") (pinfunction "17_17") (pintype "passive"))
      (node (ref "IC128") (pin "17") (pinfunction "17_17") (pintype "passive"))
    )
    (net (code "769") (name "Net-(IC125-Pad18)") (class "Default")
      (node (ref "IC125") (pin "18") (pinfunction "18_18") (pintype "passive"))
      (node (ref "IC126") (pin "18") (pinfunction "18_18") (pintype "passive"))
      (node (ref "IC127") (pin "18") (pinfunction "18_18") (pintype "passive"))
      (node (ref "IC128") (pin "18") (pinfunction "18_18") (pintype "passive"))
    )
    (net (code "770") (name "Net-(IC125-Pad19)") (class "Default")
      (node (ref "IC125") (pin "19") (pinfunction "19_19") (pintype "passive"))
      (node (ref "IC126") (pin "19") (pinfunction "19_19") (pintype "passive"))
      (node (ref "IC127") (pin "19") (pinfunction "19_19") (pintype "passive"))
      (node (ref "IC128") (pin "19") (pinfunction "19_19") (pintype "passive"))
    )
    (net (code "771") (name "Net-(IC125-Pad20)") (class "Default")
      (node (ref "IC125") (pin "20") (pinfunction "20_20") (pintype "passive"))
      (node (ref "IC126") (pin "20") (pinfunction "20_20") (pintype "passive"))
      (node (ref "IC127") (pin "20") (pinfunction "20_20") (pintype "passive"))
      (node (ref "IC128") (pin "20") (pinfunction "20_20") (pintype "passive"))
    )
    (net (code "772") (name "Net-(IC125-Pad21)") (class "Default")
      (node (ref "IC125") (pin "21") (pinfunction "21_21") (pintype "passive"))
      (node (ref "IC126") (pin "21") (pinfunction "21_21") (pintype "passive"))
      (node (ref "IC127") (pin "21") (pinfunction "21_21") (pintype "passive"))
      (node (ref "IC128") (pin "21") (pinfunction "21_21") (pintype "passive"))
    )
    (net (code "773") (name "Net-(IC125-Pad22)") (class "Default")
      (node (ref "IC125") (pin "22") (pinfunction "22_22") (pintype "passive"))
      (node (ref "IC126") (pin "22") (pinfunction "22_22") (pintype "passive"))
      (node (ref "IC127") (pin "22") (pinfunction "22_22") (pintype "passive"))
      (node (ref "IC128") (pin "22") (pinfunction "22_22") (pintype "passive"))
    )
    (net (code "774") (name "Net-(IC125-Pad23)") (class "Default")
      (node (ref "IC125") (pin "23") (pinfunction "23_23") (pintype "passive"))
      (node (ref "IC126") (pin "23") (pinfunction "23_23") (pintype "passive"))
      (node (ref "IC127") (pin "23") (pinfunction "23_23") (pintype "passive"))
      (node (ref "IC128") (pin "23") (pinfunction "23_23") (pintype "passive"))
    )
    (net (code "775") (name "Net-(IC125-Pad24)") (class "Default")
      (node (ref "IC125") (pin "24") (pinfunction "24_24") (pintype "passive"))
      (node (ref "IC126") (pin "24") (pinfunction "24_24") (pintype "passive"))
      (node (ref "IC127") (pin "24") (pinfunction "24_24") (pintype "passive"))
      (node (ref "IC128") (pin "24") (pinfunction "24_24") (pintype "passive"))
    )
    (net (code "776") (name "Net-(IC129-Pad1)") (class "Default")
      (node (ref "IC129") (pin "1") (pinfunction "1_1") (pintype "passive"))
      (node (ref "IC130") (pin "1") (pinfunction "1_1") (pintype "passive"))
      (node (ref "IC131") (pin "1") (pinfunction "1_1") (pintype "passive"))
      (node (ref "IC132") (pin "1") (pinfunction "1_1") (pintype "passive"))
    )
    (net (code "777") (name "Net-(IC129-Pad2)") (class "Default")
      (node (ref "IC129") (pin "2") (pinfunction "2_2") (pintype "passive"))
      (node (ref "IC130") (pin "2") (pinfunction "2_2") (pintype "passive"))
      (node (ref "IC131") (pin "2") (pinfunction "2_2") (pintype "passive"))
      (node (ref "IC132") (pin "2") (pinfunction "2_2") (pintype "passive"))
    )
    (net (code "778") (name "Net-(IC129-Pad3)") (class "Default")
      (node (ref "IC129") (pin "3") (pinfunction "3_3") (pintype "passive"))
      (node (ref "IC130") (pin "3") (pinfunction "3_3") (pintype "passive"))
      (node (ref "IC131") (pin "3") (pinfunction "3_3") (pintype "passive"))
      (node (ref "IC132") (pin "3") (pinfunction "3_3") (pintype "passive"))
    )
    (net (code "779") (name "Net-(IC129-Pad4)") (class "Default")
      (node (ref "IC129") (pin "4") (pinfunction "4_4") (pintype "passive"))
      (node (ref "IC130") (pin "4") (pinfunction "4_4") (pintype "passive"))
      (node (ref "IC131") (pin "4") (pinfunction "4_4") (pintype "passive"))
      (node (ref "IC132") (pin "4") (pinfunction "4_4") (pintype "passive"))
    )
    (net (code "780") (name "Net-(IC129-Pad5)") (class "Default")
      (node (ref "IC129") (pin "5") (pinfunction "5_5") (pintype "passive"))
      (node (ref "IC130") (pin "5") (pinfunction "5_5") (pintype "passive"))
      (node (ref "IC131") (pin "5") (pinfunction "5_5") (pintype "passive"))
      (node (ref "IC132") (pin "5") (pinfunction "5_5") (pintype "passive"))
    )
    (net (code "781") (name "Net-(IC129-Pad6)") (class "Default")
      (node (ref "IC129") (pin "6") (pinfunction "6_6") (pintype "passive"))
      (node (ref "IC130") (pin "6") (pinfunction "6_6") (pintype "passive"))
      (node (ref "IC131") (pin "6") (pinfunction "6_6") (pintype "passive"))
      (node (ref "IC132") (pin "6") (pinfunction "6_6") (pintype "passive"))
    )
    (net (code "782") (name "Net-(IC129-Pad7)") (class "Default")
      (node (ref "IC129") (pin "7") (pinfunction "7_7") (pintype "passive"))
      (node (ref "IC130") (pin "7") (pinfunction "7_7") (pintype "passive"))
      (node (ref "IC131") (pin "7") (pinfunction "7_7") (pintype "passive"))
      (node (ref "IC132") (pin "7") (pinfunction "7_7") (pintype "passive"))
    )
    (net (code "783") (name "Net-(IC129-Pad8)") (class "Default")
      (node (ref "IC129") (pin "8") (pinfunction "8_8") (pintype "passive"))
      (node (ref "IC130") (pin "8") (pinfunction "8_8") (pintype "passive"))
      (node (ref "IC131") (pin "8") (pinfunction "8_8") (pintype "passive"))
      (node (ref "IC132") (pin "8") (pinfunction "8_8") (pintype "passive"))
    )
    (net (code "784") (name "Net-(IC129-Pad9)") (class "Default")
      (node (ref "IC129") (pin "9") (pinfunction "9_9") (pintype "passive"))
      (node (ref "IC130") (pin "9") (pinfunction "9_9") (pintype "passive"))
      (node (ref "IC131") (pin "9") (pinfunction "9_9") (pintype "passive"))
      (node (ref "IC132") (pin "9") (pinfunction "9_9") (pintype "passive"))
    )
    (net (code "785") (name "Net-(IC129-Pad10)") (class "Default")
      (node (ref "IC129") (pin "10") (pinfunction "10_10") (pintype "passive"))
      (node (ref "IC130") (pin "10") (pinfunction "10_10") (pintype "passive"))
      (node (ref "IC131") (pin "10") (pinfunction "10_10") (pintype "passive"))
      (node (ref "IC132") (pin "10") (pinfunction "10_10") (pintype "passive"))
    )
    (net (code "786") (name "Net-(IC129-Pad11)") (class "Default")
      (node (ref "IC129") (pin "11") (pinfunction "11_11") (pintype "passive"))
      (node (ref "IC130") (pin "11") (pinfunction "11_11") (pintype "passive"))
      (node (ref "IC131") (pin "11") (pinfunction "11_11") (pintype "passive"))
      (node (ref "IC132") (pin "11") (pinfunction "11_11") (pintype "passive"))
    )
    (net (code "787") (name "Net-(IC129-Pad12)") (class "Default")
      (node (ref "IC129") (pin "12") (pinfunction "12_12") (pintype "passive"))
      (node (ref "IC130") (pin "12") (pinfunction "12_12") (pintype "passive"))
      (node (ref "IC131") (pin "12") (pinfunction "12_12") (pintype "passive"))
      (node (ref "IC132") (pin "12") (pinfunction "12_12") (pintype "passive"))
    )
    (net (code "788") (name "Net-(IC129-Pad13)") (class "Default")
      (node (ref "IC129") (pin "13") (pinfunction "13_13") (pintype "passive"))
      (node (ref "IC130") (pin "13") (pinfunction "13_13") (pintype "passive"))
      (node (ref "IC131") (pin "13") (pinfunction "13_13") (pintype "passive"))
      (node (ref "IC132") (pin "13") (pinfunction "13_13") (pintype "passive"))
    )
    (net (code "789") (name "Net-(IC129-Pad14)") (class "Default")
      (node (ref "IC129") (pin "14") (pinfunction "14_14") (pintype "passive"))
      (node (ref "IC130") (pin "14") (pinfunction "14_14") (pintype "passive"))
      (node (ref "IC131") (pin "14") (pinfunction "14_14") (pintype "passive"))
      (node (ref "IC132") (pin "14") (pinfunction "14_14") (pintype "passive"))
    )
    (net (code "790") (name "Net-(IC129-Pad15)") (class "Default")
      (node (ref "IC129") (pin "15") (pinfunction "15_15") (pintype "passive"))
      (node (ref "IC130") (pin "15") (pinfunction "15_15") (pintype "passive"))
      (node (ref "IC131") (pin "15") (pinfunction "15_15") (pintype "passive"))
      (node (ref "IC132") (pin "15") (pinfunction "15_15") (pintype "passive"))
    )
    (net (code "791") (name "Net-(IC129-Pad16)") (class "Default")
      (node (ref "IC129") (pin "16") (pinfunction "16_16") (pintype "passive"))
      (node (ref "IC130") (pin "16") (pinfunction "16_16") (pintype "passive"))
      (node (ref "IC131") (pin "16") (pinfunction "16_16") (pintype "passive"))
      (node (ref "IC132") (pin "16") (pinfunction "16_16") (pintype "passive"))
    )
    (net (code "792") (name "Net-(IC129-Pad17)") (class "Default")
      (node (ref "IC129") (pin "17") (pinfunction "17_17") (pintype "passive"))
      (node (ref "IC130") (pin "17") (pinfunction "17_17") (pintype "passive"))
      (node (ref "IC131") (pin "17") (pinfunction "17_17") (pintype "passive"))
      (node (ref "IC132") (pin "17") (pinfunction "17_17") (pintype "passive"))
    )
    (net (code "793") (name "Net-(IC129-Pad18)") (class "Default")
      (node (ref "IC129") (pin "18") (pinfunction "18_18") (pintype "passive"))
      (node (ref "IC130") (pin "18") (pinfunction "18_18") (pintype "passive"))
      (node (ref "IC131") (pin "18") (pinfunction "18_18") (pintype "passive"))
      (node (ref "IC132") (pin "18") (pinfunction "18_18") (pintype "passive"))
    )
    (net (code "794") (name "Net-(IC129-Pad19)") (class "Default")
      (node (ref "IC129") (pin "19") (pinfunction "19_19") (pintype "passive"))
      (node (ref "IC130") (pin "19") (pinfunction "19_19") (pintype "passive"))
      (node (ref "IC131") (pin "19") (pinfunction "19_19") (pintype "passive"))
      (node (ref "IC132") (pin "19") (pinfunction "19_19") (pintype "passive"))
    )
    (net (code "795") (name "Net-(IC129-Pad20)") (class "Default")
      (node (ref "IC129") (pin "20") (pinfunction "20_20") (pintype "passive"))
      (node (ref "IC130") (pin "20") (pinfunction "20_20") (pintype "passive"))
      (node (ref "IC131") (pin "20") (pinfunction "20_20") (pintype "passive"))
      (node (ref "IC132") (pin "20") (pinfunction "20_20") (pintype "passive"))
    )
    (net (code "796") (name "Net-(IC129-Pad21)") (class "Default")
      (node (ref "IC129") (pin "21") (pinfunction "21_21") (pintype "passive"))
      (node (ref "IC130") (pin "21") (pinfunction "21_21") (pintype "passive"))
      (node (ref "IC131") (pin "21") (pinfunction "21_21") (pintype "passive"))
      (node (ref "IC132") (pin "21") (pinfunction "21_21") (pintype "passive"))
    )
    (net (code "797") (name "Net-(IC129-Pad22)") (class "Default")
      (node (ref "IC129") (pin "22") (pinfunction "22_22") (pintype "passive"))
      (node (ref "IC130") (pin "22") (pinfunction "22_22") (pintype "passive"))
      (node (ref "IC131") (pin "22") (pinfunction "22_22") (pintype "passive"))
      (node (ref "IC132") (pin "22") (pinfunction "22_22") (pintype "passive"))
    )
    (net (code "798") (name "Net-(IC129-Pad23)") (class "Default")
      (node (ref "IC129") (pin "23") (pinfunction "23_23") (pintype "passive"))
      (node (ref "IC130") (pin "23") (pinfunction "23_23") (pintype "passive"))
      (node (ref "IC131") (pin "23") (pinfunction "23_23") (pintype "passive"))
      (node (ref "IC132") (pin "23") (pinfunction "23_23") (pintype "passive"))
    )
    (net (code "799") (name "Net-(IC129-Pad24)") (class "Default")
      (node (ref "IC129") (pin "24") (pinfunction "24_24") (pintype "passive"))
      (node (ref "IC130") (pin "24") (pinfunction "24_24") (pintype "passive"))
      (node (ref "IC131") (pin "24") (pinfunction "24_24") (pintype "passive"))
      (node (ref "IC132") (pin "24") (pinfunction "24_24") (pintype "passive"))
    )
    (net (code "800") (name "Net-(IC133-Pad1)") (class "Default")
      (node (ref "IC133") (pin "1") (pinfunction "1_1") (pintype "passive"))
      (node (ref "IC134") (pin "1") (pinfunction "1_1") (pintype "passive"))
      (node (ref "IC135") (pin "1") (pinfunction "1_1") (pintype "passive"))
      (node (ref "IC136") (pin "1") (pinfunction "1_1") (pintype "passive"))
    )
    (net (code "801") (name "Net-(IC133-Pad2)") (class "Default")
      (node (ref "IC133") (pin "2") (pinfunction "2_2") (pintype "passive"))
      (node (ref "IC134") (pin "2") (pinfunction "2_2") (pintype "passive"))
      (node (ref "IC135") (pin "2") (pinfunction "2_2") (pintype "passive"))
      (node (ref "IC136") (pin "2") (pinfunction "2_2") (pintype "passive"))
    )
    (net (code "802") (name "Net-(IC133-Pad3)") (class "Default")
      (node (ref "IC133") (pin "3") (pinfunction "3_3") (pintype "passive"))
      (node (ref "IC134") (pin "3") (pinfunction "3_3") (pintype "passive"))
      (node (ref "IC135") (pin "3") (pinfunction "3_3") (pintype "passive"))
      (node (ref "IC136") (pin "3") (pinfunction "3_3") (pintype "passive"))
    )
    (net (code "803") (name "Net-(IC133-Pad4)") (class "Default")
      (node (ref "IC133") (pin "4") (pinfunction "4_4") (pintype "passive"))
      (node (ref "IC134") (pin "4") (pinfunction "4_4") (pintype "passive"))
      (node (ref "IC135") (pin "4") (pinfunction "4_4") (pintype "passive"))
      (node (ref "IC136") (pin "4") (pinfunction "4_4") (pintype "passive"))
    )
    (net (code "804") (name "Net-(IC133-Pad5)") (class "Default")
      (node (ref "IC133") (pin "5") (pinfunction "5_5") (pintype "passive"))
      (node (ref "IC134") (pin "5") (pinfunction "5_5") (pintype "passive"))
      (node (ref "IC135") (pin "5") (pinfunction "5_5") (pintype "passive"))
      (node (ref "IC136") (pin "5") (pinfunction "5_5") (pintype "passive"))
    )
    (net (code "805") (name "Net-(IC133-Pad6)") (class "Default")
      (node (ref "IC133") (pin "6") (pinfunction "6_6") (pintype "passive"))
      (node (ref "IC134") (pin "6") (pinfunction "6_6") (pintype "passive"))
      (node (ref "IC135") (pin "6") (pinfunction "6_6") (pintype "passive"))
      (node (ref "IC136") (pin "6") (pinfunction "6_6") (pintype "passive"))
    )
    (net (code "806") (name "Net-(IC133-Pad7)") (class "Default")
      (node (ref "IC133") (pin "7") (pinfunction "7_7") (pintype "passive"))
      (node (ref "IC134") (pin "7") (pinfunction "7_7") (pintype "passive"))
      (node (ref "IC135") (pin "7") (pinfunction "7_7") (pintype "passive"))
      (node (ref "IC136") (pin "7") (pinfunction "7_7") (pintype "passive"))
    )
    (net (code "807") (name "Net-(IC133-Pad8)") (class "Default")
      (node (ref "IC133") (pin "8") (pinfunction "8_8") (pintype "passive"))
      (node (ref "IC134") (pin "8") (pinfunction "8_8") (pintype "passive"))
      (node (ref "IC135") (pin "8") (pinfunction "8_8") (pintype "passive"))
      (node (ref "IC136") (pin "8") (pinfunction "8_8") (pintype "passive"))
    )
    (net (code "808") (name "Net-(IC133-Pad9)") (class "Default")
      (node (ref "IC133") (pin "9") (pinfunction "9_9") (pintype "passive"))
      (node (ref "IC134") (pin "9") (pinfunction "9_9") (pintype "passive"))
      (node (ref "IC135") (pin "9") (pinfunction "9_9") (pintype "passive"))
      (node (ref "IC136") (pin "9") (pinfunction "9_9") (pintype "passive"))
    )
    (net (code "809") (name "Net-(IC133-Pad10)") (class "Default")
      (node (ref "IC133") (pin "10") (pinfunction "10_10") (pintype "passive"))
      (node (ref "IC134") (pin "10") (pinfunction "10_10") (pintype "passive"))
      (node (ref "IC135") (pin "10") (pinfunction "10_10") (pintype "passive"))
      (node (ref "IC136") (pin "10") (pinfunction "10_10") (pintype "passive"))
    )
    (net (code "810") (name "Net-(IC133-Pad11)") (class "Default")
      (node (ref "IC133") (pin "11") (pinfunction "11_11") (pintype "passive"))
      (node (ref "IC134") (pin "11") (pinfunction "11_11") (pintype "passive"))
      (node (ref "IC135") (pin "11") (pinfunction "11_11") (pintype "passive"))
      (node (ref "IC136") (pin "11") (pinfunction "11_11") (pintype "passive"))
    )
    (net (code "811") (name "Net-(IC133-Pad12)") (class "Default")
      (node (ref "IC133") (pin "12") (pinfunction "12_12") (pintype "passive"))
      (node (ref "IC134") (pin "12") (pinfunction "12_12") (pintype "passive"))
      (node (ref "IC135") (pin "12") (pinfunction "12_12") (pintype "passive"))
      (node (ref "IC136") (pin "12") (pinfunction "12_12") (pintype "passive"))
    )
    (net (code "812") (name "Net-(IC133-Pad13)") (class "Default")
      (node (ref "IC133") (pin "13") (pinfunction "13_13") (pintype "passive"))
      (node (ref "IC134") (pin "13") (pinfunction "13_13") (pintype "passive"))
      (node (ref "IC135") (pin "13") (pinfunction "13_13") (pintype "passive"))
      (node (ref "IC136") (pin "13") (pinfunction "13_13") (pintype "passive"))
    )
    (net (code "813") (name "Net-(IC133-Pad14)") (class "Default")
      (node (ref "IC133") (pin "14") (pinfunction "14_14") (pintype "passive"))
      (node (ref "IC134") (pin "14") (pinfunction "14_14") (pintype "passive"))
      (node (ref "IC135") (pin "14") (pinfunction "14_14") (pintype "passive"))
      (node (ref "IC136") (pin "14") (pinfunction "14_14") (pintype "passive"))
    )
    (net (code "814") (name "Net-(IC133-Pad15)") (class "Default")
      (node (ref "IC133") (pin "15") (pinfunction "15_15") (pintype "passive"))
      (node (ref "IC134") (pin "15") (pinfunction "15_15") (pintype "passive"))
      (node (ref "IC135") (pin "15") (pinfunction "15_15") (pintype "passive"))
      (node (ref "IC136") (pin "15") (pinfunction "15_15") (pintype "passive"))
    )
    (net (code "815") (name "Net-(IC133-Pad16)") (class "Default")
      (node (ref "IC133") (pin "16") (pinfunction "16_16") (pintype "passive"))
      (node (ref "IC134") (pin "16") (pinfunction "16_16") (pintype "passive"))
      (node (ref "IC135") (pin "16") (pinfunction "16_16") (pintype "passive"))
      (node (ref "IC136") (pin "16") (pinfunction "16_16") (pintype "passive"))
    )
    (net (code "816") (name "Net-(IC133-Pad17)") (class "Default")
      (node (ref "IC133") (pin "17") (pinfunction "17_17") (pintype "passive"))
      (node (ref "IC134") (pin "17") (pinfunction "17_17") (pintype "passive"))
      (node (ref "IC135") (pin "17") (pinfunction "17_17") (pintype "passive"))
      (node (ref "IC136") (pin "17") (pinfunction "17_17") (pintype "passive"))
    )
    (net (code "817") (name "Net-(IC133-Pad18)") (class "Default")
      (node (ref "IC133") (pin "18") (pinfunction "18_18") (pintype "passive"))
      (node (ref "IC134") (pin "18") (pinfunction "18_18") (pintype "passive"))
      (node (ref "IC135") (pin "18") (pinfunction "18_18") (pintype "passive"))
      (node (ref "IC136") (pin "18") (pinfunction "18_18") (pintype "passive"))
    )
    (net (code "818") (name "Net-(IC133-Pad19)") (class "Default")
      (node (ref "IC133") (pin "19") (pinfunction "19_19") (pintype "passive"))
      (node (ref "IC134") (pin "19") (pinfunction "19_19") (pintype "passive"))
      (node (ref "IC135") (pin "19") (pinfunction "19_19") (pintype "passive"))
      (node (ref "IC136") (pin "19") (pinfunction "19_19") (pintype "passive"))
    )
    (net (code "819") (name "Net-(IC133-Pad20)") (class "Default")
      (node (ref "IC133") (pin "20") (pinfunction "20_20") (pintype "passive"))
      (node (ref "IC134") (pin "20") (pinfunction "20_20") (pintype "passive"))
      (node (ref "IC135") (pin "20") (pinfunction "20_20") (pintype "passive"))
      (node (ref "IC136") (pin "20") (pinfunction "20_20") (pintype "passive"))
    )
    (net (code "820") (name "Net-(IC133-Pad21)") (class "Default")
      (node (ref "IC133") (pin "21") (pinfunction "21_21") (pintype "passive"))
      (node (ref "IC134") (pin "21") (pinfunction "21_21") (pintype "passive"))
      (node (ref "IC135") (pin "21") (pinfunction "21_21") (pintype "passive"))
      (node (ref "IC136") (pin "21") (pinfunction "21_21") (pintype "passive"))
    )
    (net (code "821") (name "Net-(IC133-Pad22)") (class "Default")
      (node (ref "IC133") (pin "22") (pinfunction "22_22") (pintype "passive"))
      (node (ref "IC134") (pin "22") (pinfunction "22_22") (pintype "passive"))
      (node (ref "IC135") (pin "22") (pinfunction "22_22") (pintype "passive"))
      (node (ref "IC136") (pin "22") (pinfunction "22_22") (pintype "passive"))
    )
    (net (code "822") (name "Net-(IC133-Pad23)") (class "Default")
      (node (ref "IC133") (pin "23") (pinfunction "23_23") (pintype "passive"))
      (node (ref "IC134") (pin "23") (pinfunction "23_23") (pintype "passive"))
      (node (ref "IC135") (pin "23") (pinfunction "23_23") (pintype "passive"))
      (node (ref "IC136") (pin "23") (pinfunction "23_23") (pintype "passive"))
    )
    (net (code "823") (name "Net-(IC133-Pad24)") (class "Default")
      (node (ref "IC133") (pin "24") (pinfunction "24_24") (pintype "passive"))
      (node (ref "IC134") (pin "24") (pinfunction "24_24") (pintype "passive"))
      (node (ref "IC135") (pin "24") (pinfunction "24_24") (pintype "passive"))
      (node (ref "IC136") (pin "24") (pinfunction "24_24") (pintype "passive"))
    )
    (net (code "824") (name "Net-(IC137-Pad1)") (class "Default")
      (node (ref "IC137") (pin "1") (pinfunction "1_1") (pintype "passive"))
      (node (ref "IC138") (pin "1") (pinfunction "1_1") (pintype "passive"))
      (node (ref "IC139") (pin "1") (pinfunction "1_1") (pintype "passive"))
      (node (ref "IC140") (pin "1") (pinfunction "1_1") (pintype "passive"))
    )
    (net (code "825") (name "Net-(IC137-Pad2)") (class "Default")
      (node (ref "IC137") (pin "2") (pinfunction "2_2") (pintype "passive"))
      (node (ref "IC138") (pin "2") (pinfunction "2_2") (pintype "passive"))
      (node (ref "IC139") (pin "2") (pinfunction "2_2") (pintype "passive"))
      (node (ref "IC140") (pin "2") (pinfunction "2_2") (pintype "passive"))
    )
    (net (code "826") (name "Net-(IC137-Pad3)") (class "Default")
      (node (ref "IC137") (pin "3") (pinfunction "3_3") (pintype "passive"))
      (node (ref "IC138") (pin "3") (pinfunction "3_3") (pintype "passive"))
      (node (ref "IC139") (pin "3") (pinfunction "3_3") (pintype "passive"))
      (node (ref "IC140") (pin "3") (pinfunction "3_3") (pintype "passive"))
    )
    (net (code "827") (name "Net-(IC137-Pad4)") (class "Default")
      (node (ref "IC137") (pin "4") (pinfunction "4_4") (pintype "passive"))
      (node (ref "IC138") (pin "4") (pinfunction "4_4") (pintype "passive"))
      (node (ref "IC139") (pin "4") (pinfunction "4_4") (pintype "passive"))
      (node (ref "IC140") (pin "4") (pinfunction "4_4") (pintype "passive"))
    )
    (net (code "828") (name "Net-(IC137-Pad5)") (class "Default")
      (node (ref "IC137") (pin "5") (pinfunction "5_5") (pintype "passive"))
      (node (ref "IC138") (pin "5") (pinfunction "5_5") (pintype "passive"))
      (node (ref "IC139") (pin "5") (pinfunction "5_5") (pintype "passive"))
      (node (ref "IC140") (pin "5") (pinfunction "5_5") (pintype "passive"))
    )
    (net (code "829") (name "Net-(IC137-Pad6)") (class "Default")
      (node (ref "IC137") (pin "6") (pinfunction "6_6") (pintype "passive"))
      (node (ref "IC138") (pin "6") (pinfunction "6_6") (pintype "passive"))
      (node (ref "IC139") (pin "6") (pinfunction "6_6") (pintype "passive"))
      (node (ref "IC140") (pin "6") (pinfunction "6_6") (pintype "passive"))
    )
    (net (code "830") (name "Net-(IC137-Pad7)") (class "Default")
      (node (ref "IC137") (pin "7") (pinfunction "7_7") (pintype "passive"))
      (node (ref "IC138") (pin "7") (pinfunction "7_7") (pintype "passive"))
      (node (ref "IC139") (pin "7") (pinfunction "7_7") (pintype "passive"))
      (node (ref "IC140") (pin "7") (pinfunction "7_7") (pintype "passive"))
    )
    (net (code "831") (name "Net-(IC137-Pad8)") (class "Default")
      (node (ref "IC137") (pin "8") (pinfunction "8_8") (pintype "passive"))
      (node (ref "IC138") (pin "8") (pinfunction "8_8") (pintype "passive"))
      (node (ref "IC139") (pin "8") (pinfunction "8_8") (pintype "passive"))
      (node (ref "IC140") (pin "8") (pinfunction "8_8") (pintype "passive"))
    )
    (net (code "832") (name "Net-(IC137-Pad9)") (class "Default")
      (node (ref "IC137") (pin "9") (pinfunction "9_9") (pintype "passive"))
      (node (ref "IC138") (pin "9") (pinfunction "9_9") (pintype "passive"))
      (node (ref "IC139") (pin "9") (pinfunction "9_9") (pintype "passive"))
      (node (ref "IC140") (pin "9") (pinfunction "9_9") (pintype "passive"))
    )
    (net (code "833") (name "Net-(IC137-Pad10)") (class "Default")
      (node (ref "IC137") (pin "10") (pinfunction "10_10") (pintype "passive"))
      (node (ref "IC138") (pin "10") (pinfunction "10_10") (pintype "passive"))
      (node (ref "IC139") (pin "10") (pinfunction "10_10") (pintype "passive"))
      (node (ref "IC140") (pin "10") (pinfunction "10_10") (pintype "passive"))
    )
    (net (code "834") (name "Net-(IC137-Pad11)") (class "Default")
      (node (ref "IC137") (pin "11") (pinfunction "11_11") (pintype "passive"))
      (node (ref "IC138") (pin "11") (pinfunction "11_11") (pintype "passive"))
      (node (ref "IC139") (pin "11") (pinfunction "11_11") (pintype "passive"))
      (node (ref "IC140") (pin "11") (pinfunction "11_11") (pintype "passive"))
    )
    (net (code "835") (name "Net-(IC137-Pad12)") (class "Default")
      (node (ref "IC137") (pin "12") (pinfunction "12_12") (pintype "passive"))
      (node (ref "IC138") (pin "12") (pinfunction "12_12") (pintype "passive"))
      (node (ref "IC139") (pin "12") (pinfunction "12_12") (pintype "passive"))
      (node (ref "IC140") (pin "12") (pinfunction "12_12") (pintype "passive"))
    )
    (net (code "836") (name "Net-(IC137-Pad13)") (class "Default")
      (node (ref "IC137") (pin "13") (pinfunction "13_13") (pintype "passive"))
      (node (ref "IC138") (pin "13") (pinfunction "13_13") (pintype "passive"))
      (node (ref "IC139") (pin "13") (pinfunction "13_13") (pintype "passive"))
      (node (ref "IC140") (pin "13") (pinfunction "13_13") (pintype "passive"))
    )
    (net (code "837") (name "Net-(IC137-Pad14)") (class "Default")
      (node (ref "IC137") (pin "14") (pinfunction "14_14") (pintype "passive"))
      (node (ref "IC138") (pin "14") (pinfunction "14_14") (pintype "passive"))
      (node (ref "IC139") (pin "14") (pinfunction "14_14") (pintype "passive"))
      (node (ref "IC140") (pin "14") (pinfunction "14_14") (pintype "passive"))
    )
    (net (code "838") (name "Net-(IC137-Pad15)") (class "Default")
      (node (ref "IC137") (pin "15") (pinfunction "15_15") (pintype "passive"))
      (node (ref "IC138") (pin "15") (pinfunction "15_15") (pintype "passive"))
      (node (ref "IC139") (pin "15") (pinfunction "15_15") (pintype "passive"))
      (node (ref "IC140") (pin "15") (pinfunction "15_15") (pintype "passive"))
    )
    (net (code "839") (name "Net-(IC137-Pad16)") (class "Default")
      (node (ref "IC137") (pin "16") (pinfunction "16_16") (pintype "passive"))
      (node (ref "IC138") (pin "16") (pinfunction "16_16") (pintype "passive"))
      (node (ref "IC139") (pin "16") (pinfunction "16_16") (pintype "passive"))
      (node (ref "IC140") (pin "16") (pinfunction "16_16") (pintype "passive"))
    )
    (net (code "840") (name "Net-(IC137-Pad17)") (class "Default")
      (node (ref "IC137") (pin "17") (pinfunction "17_17") (pintype "passive"))
      (node (ref "IC138") (pin "17") (pinfunction "17_17") (pintype "passive"))
      (node (ref "IC139") (pin "17") (pinfunction "17_17") (pintype "passive"))
      (node (ref "IC140") (pin "17") (pinfunction "17_17") (pintype "passive"))
    )
    (net (code "841") (name "Net-(IC137-Pad18)") (class "Default")
      (node (ref "IC137") (pin "18") (pinfunction "18_18") (pintype "passive"))
      (node (ref "IC138") (pin "18") (pinfunction "18_18") (pintype "passive"))
      (node (ref "IC139") (pin "18") (pinfunction "18_18") (pintype "passive"))
      (node (ref "IC140") (pin "18") (pinfunction "18_18") (pintype "passive"))
    )
    (net (code "842") (name "Net-(IC137-Pad19)") (class "Default")
      (node (ref "IC137") (pin "19") (pinfunction "19_19") (pintype "passive"))
      (node (ref "IC138") (pin "19") (pinfunction "19_19") (pintype "passive"))
      (node (ref "IC139") (pin "19") (pinfunction "19_19") (pintype "passive"))
      (node (ref "IC140") (pin "19") (pinfunction "19_19") (pintype "passive"))
    )
    (net (code "843") (name "Net-(IC137-Pad20)") (class "Default")
      (node (ref "IC137") (pin "20") (pinfunction "20_20") (pintype "passive"))
      (node (ref "IC138") (pin "20") (pinfunction "20_20") (pintype "passive"))
      (node (ref "IC139") (pin "20") (pinfunction "20_20") (pintype "passive"))
      (node (ref "IC140") (pin "20") (pinfunction "20_20") (pintype "passive"))
    )
    (net (code "844") (name "Net-(IC137-Pad21)") (class "Default")
      (node (ref "IC137") (pin "21") (pinfunction "21_21") (pintype "passive"))
      (node (ref "IC138") (pin "21") (pinfunction "21_21") (pintype "passive"))
      (node (ref "IC139") (pin "21") (pinfunction "21_21") (pintype "passive"))
      (node (ref "IC140") (pin "21") (pinfunction "21_21") (pintype "passive"))
    )
    (net (code "845") (name "Net-(IC137-Pad22)") (class "Default")
      (node (ref "IC137") (pin "22") (pinfunction "22_22") (pintype "passive"))
      (node (ref "IC138") (pin "22") (pinfunction "22_22") (pintype "passive"))
      (node (ref "IC139") (pin "22") (pinfunction "22_22") (pintype "passive"))
      (node (ref "IC140") (pin "22") (pinfunction "22_22") (pintype "passive"))
    )
    (net (code "846") (name "Net-(IC137-Pad23)") (class "Default")
      (node (ref "IC137") (pin "23") (pinfunction "23_23") (pintype "passive"))
      (node (ref "IC138") (pin "23") (pinfunction "23_23") (pintype "passive"))
      (node (ref "IC139") (pin "23") (pinfunction "23_23") (pintype "passive"))
      (node (ref "IC140") (pin "23") (pinfunction "23_23") (pintype "passive"))
    )
    (net (code "847") (name "Net-(IC137-Pad24)") (class "Default")
      (node (ref "IC137") (pin "24") (pinfunction "24_24") (pintype "passive"))
      (node (ref "IC138") (pin "24") (pinfunction "24_24") (pintype "passive"))
      (node (ref "IC139") (pin "24") (pinfunction "24_24") (pintype "passive"))
      (node (ref "IC140") (pin "24") (pinfunction "24_24") (pintype "passive"))
    )
    (net (code "848") (name "Net-(IC141-Pad1)") (class "Default")
      (node (ref "IC141") (pin "1") (pinfunction "1_1") (pintype "passive"))
      (node (ref "IC142") (pin "1") (pinfunction "1_1") (pintype "passive"))
      (node (ref "IC143") (pin "1") (pinfunction "1_1") (pintype "passive"))
      (node (ref "IC144") (pin "1") (pinfunction "1_1") (pintype "passive"))
    )
    (net (code "849") (name "Net-(IC141-Pad2)") (class "Default")
      (node (ref "IC141") (pin "2") (pinfunction "2_2") (pintype "passive"))
      (node (ref "IC142") (pin "2") (pinfunction "2_2") (pintype "passive"))
      (node (ref "IC143") (pin "2") (pinfunction "2_2") (pintype "passive"))
      (node (ref "IC144") (pin "2") (pinfunction "2_2") (pintype "passive"))
    )
    (net (code "850") (name "Net-(IC141-Pad3)") (class "Default")
      (node (ref "IC141") (pin "3") (pinfunction "3_3") (pintype "passive"))
      (node (ref "IC142") (pin "3") (pinfunction "3_3") (pintype "passive"))
      (node (ref "IC143") (pin "3") (pinfunction "3_3") (pintype "passive"))
      (node (ref "IC144") (pin "3") (pinfunction "3_3") (pintype "passive"))
    )
    (net (code "851") (name "Net-(IC141-Pad4)") (class "Default")
      (node (ref "IC141") (pin "4") (pinfunction "4_4") (pintype "passive"))
      (node (ref "IC142") (pin "4") (pinfunction "4_4") (pintype "passive"))
      (node (ref "IC143") (pin "4") (pinfunction "4_4") (pintype "passive"))
      (node (ref "IC144") (pin "4") (pinfunction "4_4") (pintype "passive"))
    )
    (net (code "852") (name "Net-(IC141-Pad5)") (class "Default")
      (node (ref "IC141") (pin "5") (pinfunction "5_5") (pintype "passive"))
      (node (ref "IC142") (pin "5") (pinfunction "5_5") (pintype "passive"))
      (node (ref "IC143") (pin "5") (pinfunction "5_5") (pintype "passive"))
      (node (ref "IC144") (pin "5") (pinfunction "5_5") (pintype "passive"))
    )
    (net (code "853") (name "Net-(IC141-Pad6)") (class "Default")
      (node (ref "IC141") (pin "6") (pinfunction "6_6") (pintype "passive"))
      (node (ref "IC142") (pin "6") (pinfunction "6_6") (pintype "passive"))
      (node (ref "IC143") (pin "6") (pinfunction "6_6") (pintype "passive"))
      (node (ref "IC144") (pin "6") (pinfunction "6_6") (pintype "passive"))
    )
    (net (code "854") (name "Net-(IC141-Pad7)") (class "Default")
      (node (ref "IC141") (pin "7") (pinfunction "7_7") (pintype "passive"))
      (node (ref "IC142") (pin "7") (pinfunction "7_7") (pintype "passive"))
      (node (ref "IC143") (pin "7") (pinfunction "7_7") (pintype "passive"))
      (node (ref "IC144") (pin "7") (pinfunction "7_7") (pintype "passive"))
    )
    (net (code "855") (name "Net-(IC141-Pad8)") (class "Default")
      (node (ref "IC141") (pin "8") (pinfunction "8_8") (pintype "passive"))
      (node (ref "IC142") (pin "8") (pinfunction "8_8") (pintype "passive"))
      (node (ref "IC143") (pin "8") (pinfunction "8_8") (pintype "passive"))
      (node (ref "IC144") (pin "8") (pinfunction "8_8") (pintype "passive"))
    )
    (net (code "856") (name "Net-(IC141-Pad9)") (class "Default")
      (node (ref "IC141") (pin "9") (pinfunction "9_9") (pintype "passive"))
      (node (ref "IC142") (pin "9") (pinfunction "9_9") (pintype "passive"))
      (node (ref "IC143") (pin "9") (pinfunction "9_9") (pintype "passive"))
      (node (ref "IC144") (pin "9") (pinfunction "9_9") (pintype "passive"))
    )
    (net (code "857") (name "Net-(IC141-Pad10)") (class "Default")
      (node (ref "IC141") (pin "10") (pinfunction "10_10") (pintype "passive"))
      (node (ref "IC142") (pin "10") (pinfunction "10_10") (pintype "passive"))
      (node (ref "IC143") (pin "10") (pinfunction "10_10") (pintype "passive"))
      (node (ref "IC144") (pin "10") (pinfunction "10_10") (pintype "passive"))
    )
    (net (code "858") (name "Net-(IC141-Pad11)") (class "Default")
      (node (ref "IC141") (pin "11") (pinfunction "11_11") (pintype "passive"))
      (node (ref "IC142") (pin "11") (pinfunction "11_11") (pintype "passive"))
      (node (ref "IC143") (pin "11") (pinfunction "11_11") (pintype "passive"))
      (node (ref "IC144") (pin "11") (pinfunction "11_11") (pintype "passive"))
    )
    (net (code "859") (name "Net-(IC141-Pad12)") (class "Default")
      (node (ref "IC141") (pin "12") (pinfunction "12_12") (pintype "passive"))
      (node (ref "IC142") (pin "12") (pinfunction "12_12") (pintype "passive"))
      (node (ref "IC143") (pin "12") (pinfunction "12_12") (pintype "passive"))
      (node (ref "IC144") (pin "12") (pinfunction "12_12") (pintype "passive"))
    )
    (net (code "860") (name "Net-(IC141-Pad13)") (class "Default")
      (node (ref "IC141") (pin "13") (pinfunction "13_13") (pintype "passive"))
      (node (ref "IC142") (pin "13") (pinfunction "13_13") (pintype "passive"))
      (node (ref "IC143") (pin "13") (pinfunction "13_13") (pintype "passive"))
      (node (ref "IC144") (pin "13") (pinfunction "13_13") (pintype "passive"))
    )
    (net (code "861") (name "Net-(IC141-Pad14)") (class "Default")
      (node (ref "IC141") (pin "14") (pinfunction "14_14") (pintype "passive"))
      (node (ref "IC142") (pin "14") (pinfunction "14_14") (pintype "passive"))
      (node (ref "IC143") (pin "14") (pinfunction "14_14") (pintype "passive"))
      (node (ref "IC144") (pin "14") (pinfunction "14_14") (pintype "passive"))
    )
    (net (code "862") (name "Net-(IC141-Pad15)") (class "Default")
      (node (ref "IC141") (pin "15") (pinfunction "15_15") (pintype "passive"))
      (node (ref "IC142") (pin "15") (pinfunction "15_15") (pintype "passive"))
      (node (ref "IC143") (pin "15") (pinfunction "15_15") (pintype "passive"))
      (node (ref "IC144") (pin "15") (pinfunction "15_15") (pintype "passive"))
    )
    (net (code "863") (name "Net-(IC141-Pad16)") (class "Default")
      (node (ref "IC141") (pin "16") (pinfunction "16_16") (pintype "passive"))
      (node (ref "IC142") (pin "16") (pinfunction "16_16") (pintype "passive"))
      (node (ref "IC143") (pin "16") (pinfunction "16_16") (pintype "passive"))
      (node (ref "IC144") (pin "16") (pinfunction "16_16") (pintype "passive"))
    )
    (net (code "864") (name "Net-(IC141-Pad17)") (class "Default")
      (node (ref "IC141") (pin "17") (pinfunction "17_17") (pintype "passive"))
      (node (ref "IC142") (pin "17") (pinfunction "17_17") (pintype "passive"))
      (node (ref "IC143") (pin "17") (pinfunction "17_17") (pintype "passive"))
      (node (ref "IC144") (pin "17") (pinfunction "17_17") (pintype "passive"))
    )
    (net (code "865") (name "Net-(IC141-Pad18)") (class "Default")
      (node (ref "IC141") (pin "18") (pinfunction "18_18") (pintype "passive"))
      (node (ref "IC142") (pin "18") (pinfunction "18_18") (pintype "passive"))
      (node (ref "IC143") (pin "18") (pinfunction "18_18") (pintype "passive"))
      (node (ref "IC144") (pin "18") (pinfunction "18_18") (pintype "passive"))
    )
    (net (code "866") (name "Net-(IC141-Pad19)") (class "Default")
      (node (ref "IC141") (pin "19") (pinfunction "19_19") (pintype "passive"))
      (node (ref "IC142") (pin "19") (pinfunction "19_19") (pintype "passive"))
      (node (ref "IC143") (pin "19") (pinfunction "19_19") (pintype "passive"))
      (node (ref "IC144") (pin "19") (pinfunction "19_19") (pintype "passive"))
    )
    (net (code "867") (name "Net-(IC141-Pad20)") (class "Default")
      (node (ref "IC141") (pin "20") (pinfunction "20_20") (pintype "passive"))
      (node (ref "IC142") (pin "20") (pinfunction "20_20") (pintype "passive"))
      (node (ref "IC143") (pin "20") (pinfunction "20_20") (pintype "passive"))
      (node (ref "IC144") (pin "20") (pinfunction "20_20") (pintype "passive"))
    )
    (net (code "868") (name "Net-(IC141-Pad21)") (class "Default")
      (node (ref "IC141") (pin "21") (pinfunction "21_21") (pintype "passive"))
      (node (ref "IC142") (pin "21") (pinfunction "21_21") (pintype "passive"))
      (node (ref "IC143") (pin "21") (pinfunction "21_21") (pintype "passive"))
      (node (ref "IC144") (pin "21") (pinfunction "21_21") (pintype "passive"))
    )
    (net (code "869") (name "Net-(IC141-Pad22)") (class "Default")
      (node (ref "IC141") (pin "22") (pinfunction "22_22") (pintype "passive"))
      (node (ref "IC142") (pin "22") (pinfunction "22_22") (pintype "passive"))
      (node (ref "IC143") (pin "22") (pinfunction "22_22") (pintype "passive"))
      (node (ref "IC144") (pin "22") (pinfunction "22_22") (pintype "passive"))
    )
    (net (code "870") (name "Net-(IC141-Pad23)") (class "Default")
      (node (ref "IC141") (pin "23") (pinfunction "23_23") (pintype "passive"))
      (node (ref "IC142") (pin "23") (pinfunction "23_23") (pintype "passive"))
      (node (ref "IC143") (pin "23") (pinfunction "23_23") (pintype "passive"))
      (node (ref "IC144") (pin "23") (pinfunction "23_23") (pintype "passive"))
    )
    (net (code "871") (name "Net-(IC141-Pad24)") (class "Default")
      (node (ref "IC141") (pin "24") (pinfunction "24_24") (pintype "passive"))
      (node (ref "IC142") (pin "24") (pinfunction "24_24") (pintype "passive"))
      (node (ref "IC143") (pin "24") (pinfunction "24_24") (pintype "passive"))
      (node (ref "IC144") (pin "24") (pinfunction "24_24") (pintype "passive"))
    )
    (net (code "872") (name "Net-(IC145-Pad1)") (class "Default")
      (node (ref "IC145") (pin "1") (pinfunction "1_1") (pintype "passive"))
      (node (ref "IC146") (pin "1") (pinfunction "1_1") (pintype "passive"))
      (node (ref "IC147") (pin "1") (pinfunction "1_1") (pintype "passive"))
      (node (ref "IC148") (pin "1") (pinfunction "1_1") (pintype "passive"))
    )
    (net (code "873") (name "Net-(IC145-Pad2)") (class "Default")
      (node (ref "IC145") (pin "2") (pinfunction "2_2") (pintype "passive"))
      (node (ref "IC146") (pin "2") (pinfunction "2_2") (pintype "passive"))
      (node (ref "IC147") (pin "2") (pinfunction "2_2") (pintype "passive"))
      (node (ref "IC148") (pin "2") (pinfunction "2_2") (pintype "passive"))
    )
    (net (code "874") (name "Net-(IC145-Pad3)") (class "Default")
      (node (ref "IC145") (pin "3") (pinfunction "3_3") (pintype "passive"))
      (node (ref "IC146") (pin "3") (pinfunction "3_3") (pintype "passive"))
      (node (ref "IC147") (pin "3") (pinfunction "3_3") (pintype "passive"))
      (node (ref "IC148") (pin "3") (pinfunction "3_3") (pintype "passive"))
    )
    (net (code "875") (name "Net-(IC145-Pad4)") (class "Default")
      (node (ref "IC145") (pin "4") (pinfunction "4_4") (pintype "passive"))
      (node (ref "IC146") (pin "4") (pinfunction "4_4") (pintype "passive"))
      (node (ref "IC147") (pin "4") (pinfunction "4_4") (pintype "passive"))
      (node (ref "IC148") (pin "4") (pinfunction "4_4") (pintype "passive"))
    )
    (net (code "876") (name "Net-(IC145-Pad5)") (class "Default")
      (node (ref "IC145") (pin "5") (pinfunction "5_5") (pintype "passive"))
      (node (ref "IC146") (pin "5") (pinfunction "5_5") (pintype "passive"))
      (node (ref "IC147") (pin "5") (pinfunction "5_5") (pintype "passive"))
      (node (ref "IC148") (pin "5") (pinfunction "5_5") (pintype "passive"))
    )
    (net (code "877") (name "Net-(IC145-Pad6)") (class "Default")
      (node (ref "IC145") (pin "6") (pinfunction "6_6") (pintype "passive"))
      (node (ref "IC146") (pin "6") (pinfunction "6_6") (pintype "passive"))
      (node (ref "IC147") (pin "6") (pinfunction "6_6") (pintype "passive"))
      (node (ref "IC148") (pin "6") (pinfunction "6_6") (pintype "passive"))
    )
    (net (code "878") (name "Net-(IC145-Pad7)") (class "Default")
      (node (ref "IC145") (pin "7") (pinfunction "7_7") (pintype "passive"))
      (node (ref "IC146") (pin "7") (pinfunction "7_7") (pintype "passive"))
      (node (ref "IC147") (pin "7") (pinfunction "7_7") (pintype "passive"))
      (node (ref "IC148") (pin "7") (pinfunction "7_7") (pintype "passive"))
    )
    (net (code "879") (name "Net-(IC145-Pad8)") (class "Default")
      (node (ref "IC145") (pin "8") (pinfunction "8_8") (pintype "passive"))
      (node (ref "IC146") (pin "8") (pinfunction "8_8") (pintype "passive"))
      (node (ref "IC147") (pin "8") (pinfunction "8_8") (pintype "passive"))
      (node (ref "IC148") (pin "8") (pinfunction "8_8") (pintype "passive"))
    )
    (net (code "880") (name "Net-(IC145-Pad9)") (class "Default")
      (node (ref "IC145") (pin "9") (pinfunction "9_9") (pintype "passive"))
      (node (ref "IC146") (pin "9") (pinfunction "9_9") (pintype "passive"))
      (node (ref "IC147") (pin "9") (pinfunction "9_9") (pintype "passive"))
      (node (ref "IC148") (pin "9") (pinfunction "9_9") (pintype "passive"))
    )
    (net (code "881") (name "Net-(IC145-Pad10)") (class "Default")
      (node (ref "IC145") (pin "10") (pinfunction "10_10") (pintype "passive"))
      (node (ref "IC146") (pin "10") (pinfunction "10_10") (pintype "passive"))
      (node (ref "IC147") (pin "10") (pinfunction "10_10") (pintype "passive"))
      (node (ref "IC148") (pin "10") (pinfunction "10_10") (pintype "passive"))
    )
    (net (code "882") (name "Net-(IC145-Pad11)") (class "Default")
      (node (ref "IC145") (pin "11") (pinfunction "11_11") (pintype "passive"))
      (node (ref "IC146") (pin "11") (pinfunction "11_11") (pintype "passive"))
      (node (ref "IC147") (pin "11") (pinfunction "11_11") (pintype "passive"))
      (node (ref "IC148") (pin "11") (pinfunction "11_11") (pintype "passive"))
    )
    (net (code "883") (name "Net-(IC145-Pad12)") (class "Default")
      (node (ref "IC145") (pin "12") (pinfunction "12_12") (pintype "passive"))
      (node (ref "IC146") (pin "12") (pinfunction "12_12") (pintype "passive"))
      (node (ref "IC147") (pin "12") (pinfunction "12_12") (pintype "passive"))
      (node (ref "IC148") (pin "12") (pinfunction "12_12") (pintype "passive"))
    )
    (net (code "884") (name "Net-(IC145-Pad13)") (class "Default")
      (node (ref "IC145") (pin "13") (pinfunction "13_13") (pintype "passive"))
      (node (ref "IC146") (pin "13") (pinfunction "13_13") (pintype "passive"))
      (node (ref "IC147") (pin "13") (pinfunction "13_13") (pintype "passive"))
      (node (ref "IC148") (pin "13") (pinfunction "13_13") (pintype "passive"))
    )
    (net (code "885") (name "Net-(IC145-Pad14)") (class "Default")
      (node (ref "IC145") (pin "14") (pinfunction "14_14") (pintype "passive"))
      (node (ref "IC146") (pin "14") (pinfunction "14_14") (pintype "passive"))
      (node (ref "IC147") (pin "14") (pinfunction "14_14") (pintype "passive"))
      (node (ref "IC148") (pin "14") (pinfunction "14_14") (pintype "passive"))
    )
    (net (code "886") (name "Net-(IC145-Pad15)") (class "Default")
      (node (ref "IC145") (pin "15") (pinfunction "15_15") (pintype "passive"))
      (node (ref "IC146") (pin "15") (pinfunction "15_15") (pintype "passive"))
      (node (ref "IC147") (pin "15") (pinfunction "15_15") (pintype "passive"))
      (node (ref "IC148") (pin "15") (pinfunction "15_15") (pintype "passive"))
    )
    (net (code "887") (name "Net-(IC145-Pad16)") (class "Default")
      (node (ref "IC145") (pin "16") (pinfunction "16_16") (pintype "passive"))
      (node (ref "IC146") (pin "16") (pinfunction "16_16") (pintype "passive"))
      (node (ref "IC147") (pin "16") (pinfunction "16_16") (pintype "passive"))
      (node (ref "IC148") (pin "16") (pinfunction "16_16") (pintype "passive"))
    )
    (net (code "888") (name "Net-(IC145-Pad17)") (class "Default")
      (node (ref "IC145") (pin "17") (pinfunction "17_17") (pintype "passive"))
      (node (ref "IC146") (pin "17") (pinfunction "17_17") (pintype "passive"))
      (node (ref "IC147") (pin "17") (pinfunction "17_17") (pintype "passive"))
      (node (ref "IC148") (pin "17") (pinfunction "17_17") (pintype "passive"))
    )
    (net (code "889") (name "Net-(IC145-Pad18)") (class "Default")
      (node (ref "IC145") (pin "18") (pinfunction "18_18") (pintype "passive"))
      (node (ref "IC146") (pin "18") (pinfunction "18_18") (pintype "passive"))
      (node (ref "IC147") (pin "18") (pinfunction "18_18") (pintype "passive"))
      (node (ref "IC148") (pin "18") (pinfunction "18_18") (pintype "passive"))
    )
    (net (code "890") (name "Net-(IC145-Pad19)") (class "Default")
      (node (ref "IC145") (pin "19") (pinfunction "19_19") (pintype "passive"))
      (node (ref "IC146") (pin "19") (pinfunction "19_19") (pintype "passive"))
      (node (ref "IC147") (pin "19") (pinfunction "19_19") (pintype "passive"))
      (node (ref "IC148") (pin "19") (pinfunction "19_19") (pintype "passive"))
    )
    (net (code "891") (name "Net-(IC145-Pad20)") (class "Default")
      (node (ref "IC145") (pin "20") (pinfunction "20_20") (pintype "passive"))
      (node (ref "IC146") (pin "20") (pinfunction "20_20") (pintype "passive"))
      (node (ref "IC147") (pin "20") (pinfunction "20_20") (pintype "passive"))
      (node (ref "IC148") (pin "20") (pinfunction "20_20") (pintype "passive"))
    )
    (net (code "892") (name "Net-(IC145-Pad21)") (class "Default")
      (node (ref "IC145") (pin "21") (pinfunction "21_21") (pintype "passive"))
      (node (ref "IC146") (pin "21") (pinfunction "21_21") (pintype "passive"))
      (node (ref "IC147") (pin "21") (pinfunction "21_21") (pintype "passive"))
      (node (ref "IC148") (pin "21") (pinfunction "21_21") (pintype "passive"))
    )
    (net (code "893") (name "Net-(IC145-Pad22)") (class "Default")
      (node (ref "IC145") (pin "22") (pinfunction "22_22") (pintype "passive"))
      (node (ref "IC146") (pin "22") (pinfunction "22_22") (pintype "passive"))
      (node (ref "IC147") (pin "22") (pinfunction "22_22") (pintype "passive"))
      (node (ref "IC148") (pin "22") (pinfunction "22_22") (pintype "passive"))
    )
    (net (code "894") (name "Net-(IC145-Pad23)") (class "Default")
      (node (ref "IC145") (pin "23") (pinfunction "23_23") (pintype "passive"))
      (node (ref "IC146") (pin "23") (pinfunction "23_23") (pintype "passive"))
      (node (ref "IC147") (pin "23") (pinfunction "23_23") (pintype "passive"))
      (node (ref "IC148") (pin "23") (pinfunction "23_23") (pintype "passive"))
    )
    (net (code "895") (name "Net-(IC145-Pad24)") (class "Default")
      (node (ref "IC145") (pin "24") (pinfunction "24_24") (pintype "passive"))
      (node (ref "IC146") (pin "24") (pinfunction "24_24") (pintype "passive"))
      (node (ref "IC147") (pin "24") (pinfunction "24_24") (pintype "passive"))
      (node (ref "IC148") (pin "24") (pinfunction "24_24") (pintype "passive"))
    )
    (net (code "896") (name "Net-(IC149-Pad1)") (class "Default")
      (node (ref "IC149") (pin "1") (pinfunction "1_1") (pintype "passive"))
      (node (ref "IC150") (pin "1") (pinfunction "1_1") (pintype "passive"))
      (node (ref "IC151") (pin "1") (pinfunction "1_1") (pintype "passive"))
      (node (ref "IC152") (pin "1") (pinfunction "1_1") (pintype "passive"))
    )
    (net (code "897") (name "Net-(IC149-Pad2)") (class "Default")
      (node (ref "IC149") (pin "2") (pinfunction "2_2") (pintype "passive"))
      (node (ref "IC150") (pin "2") (pinfunction "2_2") (pintype "passive"))
      (node (ref "IC151") (pin "2") (pinfunction "2_2") (pintype "passive"))
      (node (ref "IC152") (pin "2") (pinfunction "2_2") (pintype "passive"))
    )
    (net (code "898") (name "Net-(IC149-Pad3)") (class "Default")
      (node (ref "IC149") (pin "3") (pinfunction "3_3") (pintype "passive"))
      (node (ref "IC150") (pin "3") (pinfunction "3_3") (pintype "passive"))
      (node (ref "IC151") (pin "3") (pinfunction "3_3") (pintype "passive"))
      (node (ref "IC152") (pin "3") (pinfunction "3_3") (pintype "passive"))
    )
    (net (code "899") (name "Net-(IC149-Pad4)") (class "Default")
      (node (ref "IC149") (pin "4") (pinfunction "4_4") (pintype "passive"))
      (node (ref "IC150") (pin "4") (pinfunction "4_4") (pintype "passive"))
      (node (ref "IC151") (pin "4") (pinfunction "4_4") (pintype "passive"))
      (node (ref "IC152") (pin "4") (pinfunction "4_4") (pintype "passive"))
    )
    (net (code "900") (name "Net-(IC149-Pad5)") (class "Default")
      (node (ref "IC149") (pin "5") (pinfunction "5_5") (pintype "passive"))
      (node (ref "IC150") (pin "5") (pinfunction "5_5") (pintype "passive"))
      (node (ref "IC151") (pin "5") (pinfunction "5_5") (pintype "passive"))
      (node (ref "IC152") (pin "5") (pinfunction "5_5") (pintype "passive"))
    )
    (net (code "901") (name "Net-(IC149-Pad6)") (class "Default")
      (node (ref "IC149") (pin "6") (pinfunction "6_6") (pintype "passive"))
      (node (ref "IC150") (pin "6") (pinfunction "6_6") (pintype "passive"))
      (node (ref "IC151") (pin "6") (pinfunction "6_6") (pintype "passive"))
      (node (ref "IC152") (pin "6") (pinfunction "6_6") (pintype "passive"))
    )
    (net (code "902") (name "Net-(IC149-Pad7)") (class "Default")
      (node (ref "IC149") (pin "7") (pinfunction "7_7") (pintype "passive"))
      (node (ref "IC150") (pin "7") (pinfunction "7_7") (pintype "passive"))
      (node (ref "IC151") (pin "7") (pinfunction "7_7") (pintype "passive"))
      (node (ref "IC152") (pin "7") (pinfunction "7_7") (pintype "passive"))
    )
    (net (code "903") (name "Net-(IC149-Pad8)") (class "Default")
      (node (ref "IC149") (pin "8") (pinfunction "8_8") (pintype "passive"))
      (node (ref "IC150") (pin "8") (pinfunction "8_8") (pintype "passive"))
      (node (ref "IC151") (pin "8") (pinfunction "8_8") (pintype "passive"))
      (node (ref "IC152") (pin "8") (pinfunction "8_8") (pintype "passive"))
    )
    (net (code "904") (name "Net-(IC149-Pad9)") (class "Default")
      (node (ref "IC149") (pin "9") (pinfunction "9_9") (pintype "passive"))
      (node (ref "IC150") (pin "9") (pinfunction "9_9") (pintype "passive"))
      (node (ref "IC151") (pin "9") (pinfunction "9_9") (pintype "passive"))
      (node (ref "IC152") (pin "9") (pinfunction "9_9") (pintype "passive"))
    )
    (net (code "905") (name "Net-(IC149-Pad10)") (class "Default")
      (node (ref "IC149") (pin "10") (pinfunction "10_10") (pintype "passive"))
      (node (ref "IC150") (pin "10") (pinfunction "10_10") (pintype "passive"))
      (node (ref "IC151") (pin "10") (pinfunction "10_10") (pintype "passive"))
      (node (ref "IC152") (pin "10") (pinfunction "10_10") (pintype "passive"))
    )
    (net (code "906") (name "Net-(IC149-Pad11)") (class "Default")
      (node (ref "IC149") (pin "11") (pinfunction "11_11") (pintype "passive"))
      (node (ref "IC150") (pin "11") (pinfunction "11_11") (pintype "passive"))
      (node (ref "IC151") (pin "11") (pinfunction "11_11") (pintype "passive"))
      (node (ref "IC152") (pin "11") (pinfunction "11_11") (pintype "passive"))
    )
    (net (code "907") (name "Net-(IC149-Pad12)") (class "Default")
      (node (ref "IC149") (pin "12") (pinfunction "12_12") (pintype "passive"))
      (node (ref "IC150") (pin "12") (pinfunction "12_12") (pintype "passive"))
      (node (ref "IC151") (pin "12") (pinfunction "12_12") (pintype "passive"))
      (node (ref "IC152") (pin "12") (pinfunction "12_12") (pintype "passive"))
    )
    (net (code "908") (name "Net-(IC149-Pad13)") (class "Default")
      (node (ref "IC149") (pin "13") (pinfunction "13_13") (pintype "passive"))
      (node (ref "IC150") (pin "13") (pinfunction "13_13") (pintype "passive"))
      (node (ref "IC151") (pin "13") (pinfunction "13_13") (pintype "passive"))
      (node (ref "IC152") (pin "13") (pinfunction "13_13") (pintype "passive"))
    )
    (net (code "909") (name "Net-(IC149-Pad14)") (class "Default")
      (node (ref "IC149") (pin "14") (pinfunction "14_14") (pintype "passive"))
      (node (ref "IC150") (pin "14") (pinfunction "14_14") (pintype "passive"))
      (node (ref "IC151") (pin "14") (pinfunction "14_14") (pintype "passive"))
      (node (ref "IC152") (pin "14") (pinfunction "14_14") (pintype "passive"))
    )
    (net (code "910") (name "Net-(IC149-Pad15)") (class "Default")
      (node (ref "IC149") (pin "15") (pinfunction "15_15") (pintype "passive"))
      (node (ref "IC150") (pin "15") (pinfunction "15_15") (pintype "passive"))
      (node (ref "IC151") (pin "15") (pinfunction "15_15") (pintype "passive"))
      (node (ref "IC152") (pin "15") (pinfunction "15_15") (pintype "passive"))
    )
    (net (code "911") (name "Net-(IC149-Pad16)") (class "Default")
      (node (ref "IC149") (pin "16") (pinfunction "16_16") (pintype "passive"))
      (node (ref "IC150") (pin "16") (pinfunction "16_16") (pintype "passive"))
      (node (ref "IC151") (pin "16") (pinfunction "16_16") (pintype "passive"))
      (node (ref "IC152") (pin "16") (pinfunction "16_16") (pintype "passive"))
    )
    (net (code "912") (name "Net-(IC149-Pad17)") (class "Default")
      (node (ref "IC149") (pin "17") (pinfunction "17_17") (pintype "passive"))
      (node (ref "IC150") (pin "17") (pinfunction "17_17") (pintype "passive"))
      (node (ref "IC151") (pin "17") (pinfunction "17_17") (pintype "passive"))
      (node (ref "IC152") (pin "17") (pinfunction "17_17") (pintype "passive"))
    )
    (net (code "913") (name "Net-(IC149-Pad18)") (class "Default")
      (node (ref "IC149") (pin "18") (pinfunction "18_18") (pintype "passive"))
      (node (ref "IC150") (pin "18") (pinfunction "18_18") (pintype "passive"))
      (node (ref "IC151") (pin "18") (pinfunction "18_18") (pintype "passive"))
      (node (ref "IC152") (pin "18") (pinfunction "18_18") (pintype "passive"))
    )
    (net (code "914") (name "Net-(IC149-Pad19)") (class "Default")
      (node (ref "IC149") (pin "19") (pinfunction "19_19") (pintype "passive"))
      (node (ref "IC150") (pin "19") (pinfunction "19_19") (pintype "passive"))
      (node (ref "IC151") (pin "19") (pinfunction "19_19") (pintype "passive"))
      (node (ref "IC152") (pin "19") (pinfunction "19_19") (pintype "passive"))
    )
    (net (code "915") (name "Net-(IC149-Pad20)") (class "Default")
      (node (ref "IC149") (pin "20") (pinfunction "20_20") (pintype "passive"))
      (node (ref "IC150") (pin "20") (pinfunction "20_20") (pintype "passive"))
      (node (ref "IC151") (pin "20") (pinfunction "20_20") (pintype "passive"))
      (node (ref "IC152") (pin "20") (pinfunction "20_20") (pintype "passive"))
    )
    (net (code "916") (name "Net-(IC149-Pad21)") (class "Default")
      (node (ref "IC149") (pin "21") (pinfunction "21_21") (pintype "passive"))
      (node (ref "IC150") (pin "21") (pinfunction "21_21") (pintype "passive"))
      (node (ref "IC151") (pin "21") (pinfunction "21_21") (pintype "passive"))
      (node (ref "IC152") (pin "21") (pinfunction "21_21") (pintype "passive"))
    )
    (net (code "917") (name "Net-(IC149-Pad22)") (class "Default")
      (node (ref "IC149") (pin "22") (pinfunction "22_22") (pintype "passive"))
      (node (ref "IC150") (pin "22") (pinfunction "22_22") (pintype "passive"))
      (node (ref "IC151") (pin "22") (pinfunction "22_22") (pintype "passive"))
      (node (ref "IC152") (pin "22") (pinfunction "22_22") (pintype "passive"))
    )
    (net (code "918") (name "Net-(IC149-Pad23)") (class "Default")
      (node (ref "IC149") (pin "23") (pinfunction "23_23") (pintype "passive"))
      (node (ref "IC150") (pin "23") (pinfunction "23_23") (pintype "passive"))
      (node (ref "IC151") (pin "23") (pinfunction "23_23") (pintype "passive"))
      (node (ref "IC152") (pin "23") (pinfunction "23_23") (pintype "passive"))
    )
    (net (code "919") (name "Net-(IC149-Pad24)") (class "Default")
      (node (ref "IC149") (pin "24") (pinfunction "24_24") (pintype "passive"))
      (node (ref "IC150") (pin "24") (pinfunction "24_24") (pintype "passive"))
      (node (ref "IC151") (pin "24") (pinfunction "24_24") (pintype "passive"))
      (node (ref "IC152") (pin "24") (pinfunction "24_24") (pintype "passive"))
    )
    (net (code "920") (name "Net-(IC153-Pad1)") (class "Default")
      (node (ref "IC153") (pin "1") (pinfunction "1_1") (pintype "passive"))
      (node (ref "IC154") (pin "1") (pinfunction "1_1") (pintype "passive"))
      (node (ref "IC155") (pin "1") (pinfunction "1_1") (pintype "passive"))
      (node (ref "IC156") (pin "1") (pinfunction "1_1") (pintype "passive"))
    )
    (net (code "921") (name "Net-(IC153-Pad2)") (class "Default")
      (node (ref "IC153") (pin "2") (pinfunction "2_2") (pintype "passive"))
      (node (ref "IC154") (pin "2") (pinfunction "2_2") (pintype "passive"))
      (node (ref "IC155") (pin "2") (pinfunction "2_2") (pintype "passive"))
      (node (ref "IC156") (pin "2") (pinfunction "2_2") (pintype "passive"))
    )
    (net (code "922") (name "Net-(IC153-Pad3)") (class "Default")
      (node (ref "IC153") (pin "3") (pinfunction "3_3") (pintype "passive"))
      (node (ref "IC154") (pin "3") (pinfunction "3_3") (pintype "passive"))
      (node (ref "IC155") (pin "3") (pinfunction "3_3") (pintype "passive"))
      (node (ref "IC156") (pin "3") (pinfunction "3_3") (pintype "passive"))
    )
    (net (code "923") (name "Net-(IC153-Pad4)") (class "Default")
      (node (ref "IC153") (pin "4") (pinfunction "4_4") (pintype "passive"))
      (node (ref "IC154") (pin "4") (pinfunction "4_4") (pintype "passive"))
      (node (ref "IC155") (pin "4") (pinfunction "4_4") (pintype "passive"))
      (node (ref "IC156") (pin "4") (pinfunction "4_4") (pintype "passive"))
    )
    (net (code "924") (name "Net-(IC153-Pad5)") (class "Default")
      (node (ref "IC153") (pin "5") (pinfunction "5_5") (pintype "passive"))
      (node (ref "IC154") (pin "5") (pinfunction "5_5") (pintype "passive"))
      (node (ref "IC155") (pin "5") (pinfunction "5_5") (pintype "passive"))
      (node (ref "IC156") (pin "5") (pinfunction "5_5") (pintype "passive"))
    )
    (net (code "925") (name "Net-(IC153-Pad6)") (class "Default")
      (node (ref "IC153") (pin "6") (pinfunction "6_6") (pintype "passive"))
      (node (ref "IC154") (pin "6") (pinfunction "6_6") (pintype "passive"))
      (node (ref "IC155") (pin "6") (pinfunction "6_6") (pintype "passive"))
      (node (ref "IC156") (pin "6") (pinfunction "6_6") (pintype "passive"))
    )
    (net (code "926") (name "Net-(IC153-Pad7)") (class "Default")
      (node (ref "IC153") (pin "7") (pinfunction "7_7") (pintype "passive"))
      (node (ref "IC154") (pin "7") (pinfunction "7_7") (pintype "passive"))
      (node (ref "IC155") (pin "7") (pinfunction "7_7") (pintype "passive"))
      (node (ref "IC156") (pin "7") (pinfunction "7_7") (pintype "passive"))
    )
    (net (code "927") (name "Net-(IC153-Pad8)") (class "Default")
      (node (ref "IC153") (pin "8") (pinfunction "8_8") (pintype "passive"))
      (node (ref "IC154") (pin "8") (pinfunction "8_8") (pintype "passive"))
      (node (ref "IC155") (pin "8") (pinfunction "8_8") (pintype "passive"))
      (node (ref "IC156") (pin "8") (pinfunction "8_8") (pintype "passive"))
    )
    (net (code "928") (name "Net-(IC153-Pad9)") (class "Default")
      (node (ref "IC153") (pin "9") (pinfunction "9_9") (pintype "passive"))
      (node (ref "IC154") (pin "9") (pinfunction "9_9") (pintype "passive"))
      (node (ref "IC155") (pin "9") (pinfunction "9_9") (pintype "passive"))
      (node (ref "IC156") (pin "9") (pinfunction "9_9") (pintype "passive"))
    )
    (net (code "929") (name "Net-(IC153-Pad10)") (class "Default")
      (node (ref "IC153") (pin "10") (pinfunction "10_10") (pintype "passive"))
      (node (ref "IC154") (pin "10") (pinfunction "10_10") (pintype "passive"))
      (node (ref "IC155") (pin "10") (pinfunction "10_10") (pintype "passive"))
      (node (ref "IC156") (pin "10") (pinfunction "10_10") (pintype "passive"))
    )
    (net (code "930") (name "Net-(IC153-Pad11)") (class "Default")
      (node (ref "IC153") (pin "11") (pinfunction "11_11") (pintype "passive"))
      (node (ref "IC154") (pin "11") (pinfunction "11_11") (pintype "passive"))
      (node (ref "IC155") (pin "11") (pinfunction "11_11") (pintype "passive"))
      (node (ref "IC156") (pin "11") (pinfunction "11_11") (pintype "passive"))
    )
    (net (code "931") (name "Net-(IC153-Pad12)") (class "Default")
      (node (ref "IC153") (pin "12") (pinfunction "12_12") (pintype "passive"))
      (node (ref "IC154") (pin "12") (pinfunction "12_12") (pintype "passive"))
      (node (ref "IC155") (pin "12") (pinfunction "12_12") (pintype "passive"))
      (node (ref "IC156") (pin "12") (pinfunction "12_12") (pintype "passive"))
    )
    (net (code "932") (name "Net-(IC153-Pad13)") (class "Default")
      (node (ref "IC153") (pin "13") (pinfunction "13_13") (pintype "passive"))
      (node (ref "IC154") (pin "13") (pinfunction "13_13") (pintype "passive"))
      (node (ref "IC155") (pin "13") (pinfunction "13_13") (pintype "passive"))
      (node (ref "IC156") (pin "13") (pinfunction "13_13") (pintype "passive"))
    )
    (net (code "933") (name "Net-(IC153-Pad14)") (class "Default")
      (node (ref "IC153") (pin "14") (pinfunction "14_14") (pintype "passive"))
      (node (ref "IC154") (pin "14") (pinfunction "14_14") (pintype "passive"))
      (node (ref "IC155") (pin "14") (pinfunction "14_14") (pintype "passive"))
      (node (ref "IC156") (pin "14") (pinfunction "14_14") (pintype "passive"))
    )
    (net (code "934") (name "Net-(IC153-Pad15)") (class "Default")
      (node (ref "IC153") (pin "15") (pinfunction "15_15") (pintype "passive"))
      (node (ref "IC154") (pin "15") (pinfunction "15_15") (pintype "passive"))
      (node (ref "IC155") (pin "15") (pinfunction "15_15") (pintype "passive"))
      (node (ref "IC156") (pin "15") (pinfunction "15_15") (pintype "passive"))
    )
    (net (code "935") (name "Net-(IC153-Pad16)") (class "Default")
      (node (ref "IC153") (pin "16") (pinfunction "16_16") (pintype "passive"))
      (node (ref "IC154") (pin "16") (pinfunction "16_16") (pintype "passive"))
      (node (ref "IC155") (pin "16") (pinfunction "16_16") (pintype "passive"))
      (node (ref "IC156") (pin "16") (pinfunction "16_16") (pintype "passive"))
    )
    (net (code "936") (name "Net-(IC153-Pad17)") (class "Default")
      (node (ref "IC153") (pin "17") (pinfunction "17_17") (pintype "passive"))
      (node (ref "IC154") (pin "17") (pinfunction "17_17") (pintype "passive"))
      (node (ref "IC155") (pin "17") (pinfunction "17_17") (pintype "passive"))
      (node (ref "IC156") (pin "17") (pinfunction "17_17") (pintype "passive"))
    )
    (net (code "937") (name "Net-(IC153-Pad18)") (class "Default")
      (node (ref "IC153") (pin "18") (pinfunction "18_18") (pintype "passive"))
      (node (ref "IC154") (pin "18") (pinfunction "18_18") (pintype "passive"))
      (node (ref "IC155") (pin "18") (pinfunction "18_18") (pintype "passive"))
      (node (ref "IC156") (pin "18") (pinfunction "18_18") (pintype "passive"))
    )
    (net (code "938") (name "Net-(IC153-Pad19)") (class "Default")
      (node (ref "IC153") (pin "19") (pinfunction "19_19") (pintype "passive"))
      (node (ref "IC154") (pin "19") (pinfunction "19_19") (pintype "passive"))
      (node (ref "IC155") (pin "19") (pinfunction "19_19") (pintype "passive"))
      (node (ref "IC156") (pin "19") (pinfunction "19_19") (pintype "passive"))
    )
    (net (code "939") (name "Net-(IC153-Pad20)") (class "Default")
      (node (ref "IC153") (pin "20") (pinfunction "20_20") (pintype "passive"))
      (node (ref "IC154") (pin "20") (pinfunction "20_20") (pintype "passive"))
      (node (ref "IC155") (pin "20") (pinfunction "20_20") (pintype "passive"))
      (node (ref "IC156") (pin "20") (pinfunction "20_20") (pintype "passive"))
    )
    (net (code "940") (name "Net-(IC153-Pad21)") (class "Default")
      (node (ref "IC153") (pin "21") (pinfunction "21_21") (pintype "passive"))
      (node (ref "IC154") (pin "21") (pinfunction "21_21") (pintype "passive"))
      (node (ref "IC155") (pin "21") (pinfunction "21_21") (pintype "passive"))
      (node (ref "IC156") (pin "21") (pinfunction "21_21") (pintype "passive"))
    )
    (net (code "941") (name "Net-(IC153-Pad22)") (class "Default")
      (node (ref "IC153") (pin "22") (pinfunction "22_22") (pintype "passive"))
      (node (ref "IC154") (pin "22") (pinfunction "22_22") (pintype "passive"))
      (node (ref "IC155") (pin "22") (pinfunction "22_22") (pintype "passive"))
      (node (ref "IC156") (pin "22") (pinfunction "22_22") (pintype "passive"))
    )
    (net (code "942") (name "Net-(IC153-Pad23)") (class "Default")
      (node (ref "IC153") (pin "23") (pinfunction "23_23") (pintype "passive"))
      (node (ref "IC154") (pin "23") (pinfunction "23_23") (pintype "passive"))
      (node (ref "IC155") (pin "23") (pinfunction "23_23") (pintype "passive"))
      (node (ref "IC156") (pin "23") (pinfunction "23_23") (pintype "passive"))
    )
    (net (code "943") (name "Net-(IC153-Pad24)") (class "Default")
      (node (ref "IC153") (pin "24") (pinfunction "24_24") (pintype "passive"))
      (node (ref "IC154") (pin "24") (pinfunction "24_24") (pintype "passive"))
      (node (ref "IC155") (pin "24") (pinfunction "24_24") (pintype "passive"))
      (node (ref "IC156") (pin "24") (pinfunction "24_24") (pintype "passive"))
    )
    (net (code "944") (name "Net-(IC157-Pad1)") (class "Default")
      (node (ref "IC157") (pin "1") (pinfunction "1_1") (pintype "passive"))
      (node (ref "IC158") (pin "1") (pinfunction "1_1") (pintype "passive"))
      (node (ref "IC159") (pin "1") (pinfunction "1_1") (pintype "passive"))
      (node (ref "IC160") (pin "1") (pinfunction "1_1") (pintype "passive"))
    )
    (net (code "945") (name "Net-(IC157-Pad2)") (class "Default")
      (node (ref "IC157") (pin "2") (pinfunction "2_2") (pintype "passive"))
      (node (ref "IC158") (pin "2") (pinfunction "2_2") (pintype "passive"))
      (node (ref "IC159") (pin "2") (pinfunction "2_2") (pintype "passive"))
      (node (ref "IC160") (pin "2") (pinfunction "2_2") (pintype "passive"))
    )
    (net (code "946") (name "Net-(IC157-Pad3)") (class "Default")
      (node (ref "IC157") (pin "3") (pinfunction "3_3") (pintype "passive"))
      (node (ref "IC158") (pin "3") (pinfunction "3_3") (pintype "passive"))
      (node (ref "IC159") (pin "3") (pinfunction "3_3") (pintype "passive"))
      (node (ref "IC160") (pin "3") (pinfunction "3_3") (pintype "passive"))
    )
    (net (code "947") (name "Net-(IC157-Pad4)") (class "Default")
      (node (ref "IC157") (pin "4") (pinfunction "4_4") (pintype "passive"))
      (node (ref "IC158") (pin "4") (pinfunction "4_4") (pintype "passive"))
      (node (ref "IC159") (pin "4") (pinfunction "4_4") (pintype "passive"))
      (node (ref "IC160") (pin "4") (pinfunction "4_4") (pintype "passive"))
    )
    (net (code "948") (name "Net-(IC157-Pad5)") (class "Default")
      (node (ref "IC157") (pin "5") (pinfunction "5_5") (pintype "passive"))
      (node (ref "IC158") (pin "5") (pinfunction "5_5") (pintype "passive"))
      (node (ref "IC159") (pin "5") (pinfunction "5_5") (pintype "passive"))
      (node (ref "IC160") (pin "5") (pinfunction "5_5") (pintype "passive"))
    )
    (net (code "949") (name "Net-(IC157-Pad6)") (class "Default")
      (node (ref "IC157") (pin "6") (pinfunction "6_6") (pintype "passive"))
      (node (ref "IC158") (pin "6") (pinfunction "6_6") (pintype "passive"))
      (node (ref "IC159") (pin "6") (pinfunction "6_6") (pintype "passive"))
      (node (ref "IC160") (pin "6") (pinfunction "6_6") (pintype "passive"))
    )
    (net (code "950") (name "Net-(IC157-Pad7)") (class "Default")
      (node (ref "IC157") (pin "7") (pinfunction "7_7") (pintype "passive"))
      (node (ref "IC158") (pin "7") (pinfunction "7_7") (pintype "passive"))
      (node (ref "IC159") (pin "7") (pinfunction "7_7") (pintype "passive"))
      (node (ref "IC160") (pin "7") (pinfunction "7_7") (pintype "passive"))
    )
    (net (code "951") (name "Net-(IC157-Pad8)") (class "Default")
      (node (ref "IC157") (pin "8") (pinfunction "8_8") (pintype "passive"))
      (node (ref "IC158") (pin "8") (pinfunction "8_8") (pintype "passive"))
      (node (ref "IC159") (pin "8") (pinfunction "8_8") (pintype "passive"))
      (node (ref "IC160") (pin "8") (pinfunction "8_8") (pintype "passive"))
    )
    (net (code "952") (name "Net-(IC157-Pad9)") (class "Default")
      (node (ref "IC157") (pin "9") (pinfunction "9_9") (pintype "passive"))
      (node (ref "IC158") (pin "9") (pinfunction "9_9") (pintype "passive"))
      (node (ref "IC159") (pin "9") (pinfunction "9_9") (pintype "passive"))
      (node (ref "IC160") (pin "9") (pinfunction "9_9") (pintype "passive"))
    )
    (net (code "953") (name "Net-(IC157-Pad10)") (class "Default")
      (node (ref "IC157") (pin "10") (pinfunction "10_10") (pintype "passive"))
      (node (ref "IC158") (pin "10") (pinfunction "10_10") (pintype "passive"))
      (node (ref "IC159") (pin "10") (pinfunction "10_10") (pintype "passive"))
      (node (ref "IC160") (pin "10") (pinfunction "10_10") (pintype "passive"))
    )
    (net (code "954") (name "Net-(IC157-Pad11)") (class "Default")
      (node (ref "IC157") (pin "11") (pinfunction "11_11") (pintype "passive"))
      (node (ref "IC158") (pin "11") (pinfunction "11_11") (pintype "passive"))
      (node (ref "IC159") (pin "11") (pinfunction "11_11") (pintype "passive"))
      (node (ref "IC160") (pin "11") (pinfunction "11_11") (pintype "passive"))
    )
    (net (code "955") (name "Net-(IC157-Pad12)") (class "Default")
      (node (ref "IC157") (pin "12") (pinfunction "12_12") (pintype "passive"))
      (node (ref "IC158") (pin "12") (pinfunction "12_12") (pintype "passive"))
      (node (ref "IC159") (pin "12") (pinfunction "12_12") (pintype "passive"))
      (node (ref "IC160") (pin "12") (pinfunction "12_12") (pintype "passive"))
    )
    (net (code "956") (name "Net-(IC157-Pad13)") (class "Default")
      (node (ref "IC157") (pin "13") (pinfunction "13_13") (pintype "passive"))
      (node (ref "IC158") (pin "13") (pinfunction "13_13") (pintype "passive"))
      (node (ref "IC159") (pin "13") (pinfunction "13_13") (pintype "passive"))
      (node (ref "IC160") (pin "13") (pinfunction "13_13") (pintype "passive"))
    )
    (net (code "957") (name "Net-(IC157-Pad14)") (class "Default")
      (node (ref "IC157") (pin "14") (pinfunction "14_14") (pintype "passive"))
      (node (ref "IC158") (pin "14") (pinfunction "14_14") (pintype "passive"))
      (node (ref "IC159") (pin "14") (pinfunction "14_14") (pintype "passive"))
      (node (ref "IC160") (pin "14") (pinfunction "14_14") (pintype "passive"))
    )
    (net (code "958") (name "Net-(IC157-Pad15)") (class "Default")
      (node (ref "IC157") (pin "15") (pinfunction "15_15") (pintype "passive"))
      (node (ref "IC158") (pin "15") (pinfunction "15_15") (pintype "passive"))
      (node (ref "IC159") (pin "15") (pinfunction "15_15") (pintype "passive"))
      (node (ref "IC160") (pin "15") (pinfunction "15_15") (pintype "passive"))
    )
    (net (code "959") (name "Net-(IC157-Pad16)") (class "Default")
      (node (ref "IC157") (pin "16") (pinfunction "16_16") (pintype "passive"))
      (node (ref "IC158") (pin "16") (pinfunction "16_16") (pintype "passive"))
      (node (ref "IC159") (pin "16") (pinfunction "16_16") (pintype "passive"))
      (node (ref "IC160") (pin "16") (pinfunction "16_16") (pintype "passive"))
    )
    (net (code "960") (name "Net-(IC157-Pad17)") (class "Default")
      (node (ref "IC157") (pin "17") (pinfunction "17_17") (pintype "passive"))
      (node (ref "IC158") (pin "17") (pinfunction "17_17") (pintype "passive"))
      (node (ref "IC159") (pin "17") (pinfunction "17_17") (pintype "passive"))
      (node (ref "IC160") (pin "17") (pinfunction "17_17") (pintype "passive"))
    )
    (net (code "961") (name "Net-(IC157-Pad18)") (class "Default")
      (node (ref "IC157") (pin "18") (pinfunction "18_18") (pintype "passive"))
      (node (ref "IC158") (pin "18") (pinfunction "18_18") (pintype "passive"))
      (node (ref "IC159") (pin "18") (pinfunction "18_18") (pintype "passive"))
      (node (ref "IC160") (pin "18") (pinfunction "18_18") (pintype "passive"))
    )
    (net (code "962") (name "Net-(IC157-Pad19)") (class "Default")
      (node (ref "IC157") (pin "19") (pinfunction "19_19") (pintype "passive"))
      (node (ref "IC158") (pin "19") (pinfunction "19_19") (pintype "passive"))
      (node (ref "IC159") (pin "19") (pinfunction "19_19") (pintype "passive"))
      (node (ref "IC160") (pin "19") (pinfunction "19_19") (pintype "passive"))
    )
    (net (code "963") (name "Net-(IC157-Pad20)") (class "Default")
      (node (ref "IC157") (pin "20") (pinfunction "20_20") (pintype "passive"))
      (node (ref "IC158") (pin "20") (pinfunction "20_20") (pintype "passive"))
      (node (ref "IC159") (pin "20") (pinfunction "20_20") (pintype "passive"))
      (node (ref "IC160") (pin "20") (pinfunction "20_20") (pintype "passive"))
    )
    (net (code "964") (name "Net-(IC157-Pad21)") (class "Default")
      (node (ref "IC157") (pin "21") (pinfunction "21_21") (pintype "passive"))
      (node (ref "IC158") (pin "21") (pinfunction "21_21") (pintype "passive"))
      (node (ref "IC159") (pin "21") (pinfunction "21_21") (pintype "passive"))
      (node (ref "IC160") (pin "21") (pinfunction "21_21") (pintype "passive"))
    )
    (net (code "965") (name "Net-(IC157-Pad22)") (class "Default")
      (node (ref "IC157") (pin "22") (pinfunction "22_22") (pintype "passive"))
      (node (ref "IC158") (pin "22") (pinfunction "22_22") (pintype "passive"))
      (node (ref "IC159") (pin "22") (pinfunction "22_22") (pintype "passive"))
      (node (ref "IC160") (pin "22") (pinfunction "22_22") (pintype "passive"))
    )
    (net (code "966") (name "Net-(IC157-Pad23)") (class "Default")
      (node (ref "IC157") (pin "23") (pinfunction "23_23") (pintype "passive"))
      (node (ref "IC158") (pin "23") (pinfunction "23_23") (pintype "passive"))
      (node (ref "IC159") (pin "23") (pinfunction "23_23") (pintype "passive"))
      (node (ref "IC160") (pin "23") (pinfunction "23_23") (pintype "passive"))
    )
    (net (code "967") (name "Net-(IC157-Pad24)") (class "Default")
      (node (ref "IC157") (pin "24") (pinfunction "24_24") (pintype "passive"))
      (node (ref "IC158") (pin "24") (pinfunction "24_24") (pintype "passive"))
      (node (ref "IC159") (pin "24") (pinfunction "24_24") (pintype "passive"))
      (node (ref "IC160") (pin "24") (pinfunction "24_24") (pintype "passive"))
    )
    (net (code "968") (name "Net-(IC161-Pad1)") (class "Default")
      (node (ref "IC161") (pin "1") (pinfunction "1_1") (pintype "passive"))
      (node (ref "IC162") (pin "1") (pinfunction "1_1") (pintype "passive"))
      (node (ref "IC163") (pin "1") (pinfunction "1_1") (pintype "passive"))
      (node (ref "IC164") (pin "1") (pinfunction "1_1") (pintype "passive"))
    )
    (net (code "969") (name "Net-(IC161-Pad2)") (class "Default")
      (node (ref "IC161") (pin "2") (pinfunction "2_2") (pintype "passive"))
      (node (ref "IC162") (pin "2") (pinfunction "2_2") (pintype "passive"))
      (node (ref "IC163") (pin "2") (pinfunction "2_2") (pintype "passive"))
      (node (ref "IC164") (pin "2") (pinfunction "2_2") (pintype "passive"))
    )
    (net (code "970") (name "Net-(IC161-Pad3)") (class "Default")
      (node (ref "IC161") (pin "3") (pinfunction "3_3") (pintype "passive"))
      (node (ref "IC162") (pin "3") (pinfunction "3_3") (pintype "passive"))
      (node (ref "IC163") (pin "3") (pinfunction "3_3") (pintype "passive"))
      (node (ref "IC164") (pin "3") (pinfunction "3_3") (pintype "passive"))
    )
    (net (code "971") (name "Net-(IC161-Pad4)") (class "Default")
      (node (ref "IC161") (pin "4") (pinfunction "4_4") (pintype "passive"))
      (node (ref "IC162") (pin "4") (pinfunction "4_4") (pintype "passive"))
      (node (ref "IC163") (pin "4") (pinfunction "4_4") (pintype "passive"))
      (node (ref "IC164") (pin "4") (pinfunction "4_4") (pintype "passive"))
    )
    (net (code "972") (name "Net-(IC161-Pad5)") (class "Default")
      (node (ref "IC161") (pin "5") (pinfunction "5_5") (pintype "passive"))
      (node (ref "IC162") (pin "5") (pinfunction "5_5") (pintype "passive"))
      (node (ref "IC163") (pin "5") (pinfunction "5_5") (pintype "passive"))
      (node (ref "IC164") (pin "5") (pinfunction "5_5") (pintype "passive"))
    )
    (net (code "973") (name "Net-(IC161-Pad6)") (class "Default")
      (node (ref "IC161") (pin "6") (pinfunction "6_6") (pintype "passive"))
      (node (ref "IC162") (pin "6") (pinfunction "6_6") (pintype "passive"))
      (node (ref "IC163") (pin "6") (pinfunction "6_6") (pintype "passive"))
      (node (ref "IC164") (pin "6") (pinfunction "6_6") (pintype "passive"))
    )
    (net (code "974") (name "Net-(IC161-Pad7)") (class "Default")
      (node (ref "IC161") (pin "7") (pinfunction "7_7") (pintype "passive"))
      (node (ref "IC162") (pin "7") (pinfunction "7_7") (pintype "passive"))
      (node (ref "IC163") (pin "7") (pinfunction "7_7") (pintype "passive"))
      (node (ref "IC164") (pin "7") (pinfunction "7_7") (pintype "passive"))
    )
    (net (code "975") (name "Net-(IC161-Pad8)") (class "Default")
      (node (ref "IC161") (pin "8") (pinfunction "8_8") (pintype "passive"))
      (node (ref "IC162") (pin "8") (pinfunction "8_8") (pintype "passive"))
      (node (ref "IC163") (pin "8") (pinfunction "8_8") (pintype "passive"))
      (node (ref "IC164") (pin "8") (pinfunction "8_8") (pintype "passive"))
    )
    (net (code "976") (name "Net-(IC161-Pad9)") (class "Default")
      (node (ref "IC161") (pin "9") (pinfunction "9_9") (pintype "passive"))
      (node (ref "IC162") (pin "9") (pinfunction "9_9") (pintype "passive"))
      (node (ref "IC163") (pin "9") (pinfunction "9_9") (pintype "passive"))
      (node (ref "IC164") (pin "9") (pinfunction "9_9") (pintype "passive"))
    )
    (net (code "977") (name "Net-(IC161-Pad10)") (class "Default")
      (node (ref "IC161") (pin "10") (pinfunction "10_10") (pintype "passive"))
      (node (ref "IC162") (pin "10") (pinfunction "10_10") (pintype "passive"))
      (node (ref "IC163") (pin "10") (pinfunction "10_10") (pintype "passive"))
      (node (ref "IC164") (pin "10") (pinfunction "10_10") (pintype "passive"))
    )
    (net (code "978") (name "Net-(IC161-Pad11)") (class "Default")
      (node (ref "IC161") (pin "11") (pinfunction "11_11") (pintype "passive"))
      (node (ref "IC162") (pin "11") (pinfunction "11_11") (pintype "passive"))
      (node (ref "IC163") (pin "11") (pinfunction "11_11") (pintype "passive"))
      (node (ref "IC164") (pin "11") (pinfunction "11_11") (pintype "passive"))
    )
    (net (code "979") (name "Net-(IC161-Pad12)") (class "Default")
      (node (ref "IC161") (pin "12") (pinfunction "12_12") (pintype "passive"))
      (node (ref "IC162") (pin "12") (pinfunction "12_12") (pintype "passive"))
      (node (ref "IC163") (pin "12") (pinfunction "12_12") (pintype "passive"))
      (node (ref "IC164") (pin "12") (pinfunction "12_12") (pintype "passive"))
    )
    (net (code "980") (name "Net-(IC161-Pad13)") (class "Default")
      (node (ref "IC161") (pin "13") (pinfunction "13_13") (pintype "passive"))
      (node (ref "IC162") (pin "13") (pinfunction "13_13") (pintype "passive"))
      (node (ref "IC163") (pin "13") (pinfunction "13_13") (pintype "passive"))
      (node (ref "IC164") (pin "13") (pinfunction "13_13") (pintype "passive"))
    )
    (net (code "981") (name "Net-(IC161-Pad14)") (class "Default")
      (node (ref "IC161") (pin "14") (pinfunction "14_14") (pintype "passive"))
      (node (ref "IC162") (pin "14") (pinfunction "14_14") (pintype "passive"))
      (node (ref "IC163") (pin "14") (pinfunction "14_14") (pintype "passive"))
      (node (ref "IC164") (pin "14") (pinfunction "14_14") (pintype "passive"))
    )
    (net (code "982") (name "Net-(IC161-Pad15)") (class "Default")
      (node (ref "IC161") (pin "15") (pinfunction "15_15") (pintype "passive"))
      (node (ref "IC162") (pin "15") (pinfunction "15_15") (pintype "passive"))
      (node (ref "IC163") (pin "15") (pinfunction "15_15") (pintype "passive"))
      (node (ref "IC164") (pin "15") (pinfunction "15_15") (pintype "passive"))
    )
    (net (code "983") (name "Net-(IC161-Pad16)") (class "Default")
      (node (ref "IC161") (pin "16") (pinfunction "16_16") (pintype "passive"))
      (node (ref "IC162") (pin "16") (pinfunction "16_16") (pintype "passive"))
      (node (ref "IC163") (pin "16") (pinfunction "16_16") (pintype "passive"))
      (node (ref "IC164") (pin "16") (pinfunction "16_16") (pintype "passive"))
    )
    (net (code "984") (name "Net-(IC161-Pad17)") (class "Default")
      (node (ref "IC161") (pin "17") (pinfunction "17_17") (pintype "passive"))
      (node (ref "IC162") (pin "17") (pinfunction "17_17") (pintype "passive"))
      (node (ref "IC163") (pin "17") (pinfunction "17_17") (pintype "passive"))
      (node (ref "IC164") (pin "17") (pinfunction "17_17") (pintype "passive"))
    )
    (net (code "985") (name "Net-(IC161-Pad18)") (class "Default")
      (node (ref "IC161") (pin "18") (pinfunction "18_18") (pintype "passive"))
      (node (ref "IC162") (pin "18") (pinfunction "18_18") (pintype "passive"))
      (node (ref "IC163") (pin "18") (pinfunction "18_18") (pintype "passive"))
      (node (ref "IC164") (pin "18") (pinfunction "18_18") (pintype "passive"))
    )
    (net (code "986") (name "Net-(IC161-Pad19)") (class "Default")
      (node (ref "IC161") (pin "19") (pinfunction "19_19") (pintype "passive"))
      (node (ref "IC162") (pin "19") (pinfunction "19_19") (pintype "passive"))
      (node (ref "IC163") (pin "19") (pinfunction "19_19") (pintype "passive"))
      (node (ref "IC164") (pin "19") (pinfunction "19_19") (pintype "passive"))
    )
    (net (code "987") (name "Net-(IC161-Pad20)") (class "Default")
      (node (ref "IC161") (pin "20") (pinfunction "20_20") (pintype "passive"))
      (node (ref "IC162") (pin "20") (pinfunction "20_20") (pintype "passive"))
      (node (ref "IC163") (pin "20") (pinfunction "20_20") (pintype "passive"))
      (node (ref "IC164") (pin "20") (pinfunction "20_20") (pintype "passive"))
    )
    (net (code "988") (name "Net-(IC161-Pad21)") (class "Default")
      (node (ref "IC161") (pin "21") (pinfunction "21_21") (pintype "passive"))
      (node (ref "IC162") (pin "21") (pinfunction "21_21") (pintype "passive"))
      (node (ref "IC163") (pin "21") (pinfunction "21_21") (pintype "passive"))
      (node (ref "IC164") (pin "21") (pinfunction "21_21") (pintype "passive"))
    )
    (net (code "989") (name "Net-(IC161-Pad22)") (class "Default")
      (node (ref "IC161") (pin "22") (pinfunction "22_22") (pintype "passive"))
      (node (ref "IC162") (pin "22") (pinfunction "22_22") (pintype "passive"))
      (node (ref "IC163") (pin "22") (pinfunction "22_22") (pintype "passive"))
      (node (ref "IC164") (pin "22") (pinfunction "22_22") (pintype "passive"))
    )
    (net (code "990") (name "Net-(IC161-Pad23)") (class "Default")
      (node (ref "IC161") (pin "23") (pinfunction "23_23") (pintype "passive"))
      (node (ref "IC162") (pin "23") (pinfunction "23_23") (pintype "passive"))
      (node (ref "IC163") (pin "23") (pinfunction "23_23") (pintype "passive"))
      (node (ref "IC164") (pin "23") (pinfunction "23_23") (pintype "passive"))
    )
    (net (code "991") (name "Net-(IC161-Pad24)") (class "Default")
      (node (ref "IC161") (pin "24") (pinfunction "24_24") (pintype "passive"))
      (node (ref "IC162") (pin "24") (pinfunction "24_24") (pintype "passive"))
      (node (ref "IC163") (pin "24") (pinfunction "24_24") (pintype "passive"))
      (node (ref "IC164") (pin "24") (pinfunction "24_24") (pintype "passive"))
    )
    (net (code "992") (name "Net-(IC165-Pad1)") (class "Default")
      (node (ref "IC165") (pin "1") (pinfunction "1_1") (pintype "passive"))
      (node (ref "IC166") (pin "1") (pinfunction "1_1") (pintype "passive"))
      (node (ref "IC167") (pin "1") (pinfunction "1_1") (pintype "passive"))
      (node (ref "IC168") (pin "1") (pinfunction "1_1") (pintype "passive"))
    )
    (net (code "993") (name "Net-(IC165-Pad2)") (class "Default")
      (node (ref "IC165") (pin "2") (pinfunction "2_2") (pintype "passive"))
      (node (ref "IC166") (pin "2") (pinfunction "2_2") (pintype "passive"))
      (node (ref "IC167") (pin "2") (pinfunction "2_2") (pintype "passive"))
      (node (ref "IC168") (pin "2") (pinfunction "2_2") (pintype "passive"))
    )
    (net (code "994") (name "Net-(IC165-Pad3)") (class "Default")
      (node (ref "IC165") (pin "3") (pinfunction "3_3") (pintype "passive"))
      (node (ref "IC166") (pin "3") (pinfunction "3_3") (pintype "passive"))
      (node (ref "IC167") (pin "3") (pinfunction "3_3") (pintype "passive"))
      (node (ref "IC168") (pin "3") (pinfunction "3_3") (pintype "passive"))
    )
    (net (code "995") (name "Net-(IC165-Pad4)") (class "Default")
      (node (ref "IC165") (pin "4") (pinfunction "4_4") (pintype "passive"))
      (node (ref "IC166") (pin "4") (pinfunction "4_4") (pintype "passive"))
      (node (ref "IC167") (pin "4") (pinfunction "4_4") (pintype "passive"))
      (node (ref "IC168") (pin "4") (pinfunction "4_4") (pintype "passive"))
    )
    (net (code "996") (name "Net-(IC165-Pad5)") (class "Default")
      (node (ref "IC165") (pin "5") (pinfunction "5_5") (pintype "passive"))
      (node (ref "IC166") (pin "5") (pinfunction "5_5") (pintype "passive"))
      (node (ref "IC167") (pin "5") (pinfunction "5_5") (pintype "passive"))
      (node (ref "IC168") (pin "5") (pinfunction "5_5") (pintype "passive"))
    )
    (net (code "997") (name "Net-(IC165-Pad6)") (class "Default")
      (node (ref "IC165") (pin "6") (pinfunction "6_6") (pintype "passive"))
      (node (ref "IC166") (pin "6") (pinfunction "6_6") (pintype "passive"))
      (node (ref "IC167") (pin "6") (pinfunction "6_6") (pintype "passive"))
      (node (ref "IC168") (pin "6") (pinfunction "6_6") (pintype "passive"))
    )
    (net (code "998") (name "Net-(IC165-Pad7)") (class "Default")
      (node (ref "IC165") (pin "7") (pinfunction "7_7") (pintype "passive"))
      (node (ref "IC166") (pin "7") (pinfunction "7_7") (pintype "passive"))
      (node (ref "IC167") (pin "7") (pinfunction "7_7") (pintype "passive"))
      (node (ref "IC168") (pin "7") (pinfunction "7_7") (pintype "passive"))
    )
    (net (code "999") (name "Net-(IC165-Pad8)") (class "Default")
      (node (ref "IC165") (pin "8") (pinfunction "8_8") (pintype "passive"))
      (node (ref "IC166") (pin "8") (pinfunction "8_8") (pintype "passive"))
      (node (ref "IC167") (pin "8") (pinfunction "8_8") (pintype "passive"))
      (node (ref "IC168") (pin "8") (pinfunction "8_8") (pintype "passive"))
    )
    (net (code "1000") (name "Net-(IC165-Pad9)") (class "Default")
      (node (ref "IC165") (pin "9") (pinfunction "9_9") (pintype "passive"))
      (node (ref "IC166") (pin "9") (pinfunction "9_9") (pintype "passive"))
      (node (ref "IC167") (pin "9") (pinfunction "9_9") (pintype "passive"))
      (node (ref "IC168") (pin "9") (pinfunction "9_9") (pintype "passive"))
    )
    (net (code "1001") (name "Net-(IC165-Pad10)") (class "Default")
      (node (ref "IC165") (pin "10") (pinfunction "10_10") (pintype "passive"))
      (node (ref "IC166") (pin "10") (pinfunction "10_10") (pintype "passive"))
      (node (ref "IC167") (pin "10") (pinfunction "10_10") (pintype "passive"))
      (node (ref "IC168") (pin "10") (pinfunction "10_10") (pintype "passive"))
    )
    (net (code "1002") (name "Net-(IC165-Pad11)") (class "Default")
      (node (ref "IC165") (pin "11") (pinfunction "11_11") (pintype "passive"))
      (node (ref "IC166") (pin "11") (pinfunction "11_11") (pintype "passive"))
      (node (ref "IC167") (pin "11") (pinfunction "11_11") (pintype "passive"))
      (node (ref "IC168") (pin "11") (pinfunction "11_11") (pintype "passive"))
    )
    (net (code "1003") (name "Net-(IC165-Pad12)") (class "Default")
      (node (ref "IC165") (pin "12") (pinfunction "12_12") (pintype "passive"))
      (node (ref "IC166") (pin "12") (pinfunction "12_12") (pintype "passive"))
      (node (ref "IC167") (pin "12") (pinfunction "12_12") (pintype "passive"))
      (node (ref "IC168") (pin "12") (pinfunction "12_12") (pintype "passive"))
    )
    (net (code "1004") (name "Net-(IC165-Pad13)") (class "Default")
      (node (ref "IC165") (pin "13") (pinfunction "13_13") (pintype "passive"))
      (node (ref "IC166") (pin "13") (pinfunction "13_13") (pintype "passive"))
      (node (ref "IC167") (pin "13") (pinfunction "13_13") (pintype "passive"))
      (node (ref "IC168") (pin "13") (pinfunction "13_13") (pintype "passive"))
    )
    (net (code "1005") (name "Net-(IC165-Pad14)") (class "Default")
      (node (ref "IC165") (pin "14") (pinfunction "14_14") (pintype "passive"))
      (node (ref "IC166") (pin "14") (pinfunction "14_14") (pintype "passive"))
      (node (ref "IC167") (pin "14") (pinfunction "14_14") (pintype "passive"))
      (node (ref "IC168") (pin "14") (pinfunction "14_14") (pintype "passive"))
    )
    (net (code "1006") (name "Net-(IC165-Pad15)") (class "Default")
      (node (ref "IC165") (pin "15") (pinfunction "15_15") (pintype "passive"))
      (node (ref "IC166") (pin "15") (pinfunction "15_15") (pintype "passive"))
      (node (ref "IC167") (pin "15") (pinfunction "15_15") (pintype "passive"))
      (node (ref "IC168") (pin "15") (pinfunction "15_15") (pintype "passive"))
    )
    (net (code "1007") (name "Net-(IC165-Pad16)") (class "Default")
      (node (ref "IC165") (pin "16") (pinfunction "16_16") (pintype "passive"))
      (node (ref "IC166") (pin "16") (pinfunction "16_16") (pintype "passive"))
      (node (ref "IC167") (pin "16") (pinfunction "16_16") (pintype "passive"))
      (node (ref "IC168") (pin "16") (pinfunction "16_16") (pintype "passive"))
    )
    (net (code "1008") (name "Net-(IC165-Pad17)") (class "Default")
      (node (ref "IC165") (pin "17") (pinfunction "17_17") (pintype "passive"))
      (node (ref "IC166") (pin "17") (pinfunction "17_17") (pintype "passive"))
      (node (ref "IC167") (pin "17") (pinfunction "17_17") (pintype "passive"))
      (node (ref "IC168") (pin "17") (pinfunction "17_17") (pintype "passive"))
    )
    (net (code "1009") (name "Net-(IC165-Pad18)") (class "Default")
      (node (ref "IC165") (pin "18") (pinfunction "18_18") (pintype "passive"))
      (node (ref "IC166") (pin "18") (pinfunction "18_18") (pintype "passive"))
      (node (ref "IC167") (pin "18") (pinfunction "18_18") (pintype "passive"))
      (node (ref "IC168") (pin "18") (pinfunction "18_18") (pintype "passive"))
    )
    (net (code "1010") (name "Net-(IC165-Pad19)") (class "Default")
      (node (ref "IC165") (pin "19") (pinfunction "19_19") (pintype "passive"))
      (node (ref "IC166") (pin "19") (pinfunction "19_19") (pintype "passive"))
      (node (ref "IC167") (pin "19") (pinfunction "19_19") (pintype "passive"))
      (node (ref "IC168") (pin "19") (pinfunction "19_19") (pintype "passive"))
    )
    (net (code "1011") (name "Net-(IC165-Pad20)") (class "Default")
      (node (ref "IC165") (pin "20") (pinfunction "20_20") (pintype "passive"))
      (node (ref "IC166") (pin "20") (pinfunction "20_20") (pintype "passive"))
      (node (ref "IC167") (pin "20") (pinfunction "20_20") (pintype "passive"))
      (node (ref "IC168") (pin "20") (pinfunction "20_20") (pintype "passive"))
    )
    (net (code "1012") (name "Net-(IC165-Pad21)") (class "Default")
      (node (ref "IC165") (pin "21") (pinfunction "21_21") (pintype "passive"))
      (node (ref "IC166") (pin "21") (pinfunction "21_21") (pintype "passive"))
      (node (ref "IC167") (pin "21") (pinfunction "21_21") (pintype "passive"))
      (node (ref "IC168") (pin "21") (pinfunction "21_21") (pintype "passive"))
    )
    (net (code "1013") (name "Net-(IC165-Pad22)") (class "Default")
      (node (ref "IC165") (pin "22") (pinfunction "22_22") (pintype "passive"))
      (node (ref "IC166") (pin "22") (pinfunction "22_22") (pintype "passive"))
      (node (ref "IC167") (pin "22") (pinfunction "22_22") (pintype "passive"))
      (node (ref "IC168") (pin "22") (pinfunction "22_22") (pintype "passive"))
    )
    (net (code "1014") (name "Net-(IC165-Pad23)") (class "Default")
      (node (ref "IC165") (pin "23") (pinfunction "23_23") (pintype "passive"))
      (node (ref "IC166") (pin "23") (pinfunction "23_23") (pintype "passive"))
      (node (ref "IC167") (pin "23") (pinfunction "23_23") (pintype "passive"))
      (node (ref "IC168") (pin "23") (pinfunction "23_23") (pintype "passive"))
    )
    (net (code "1015") (name "Net-(IC165-Pad24)") (class "Default")
      (node (ref "IC165") (pin "24") (pinfunction "24_24") (pintype "passive"))
      (node (ref "IC166") (pin "24") (pinfunction "24_24") (pintype "passive"))
      (node (ref "IC167") (pin "24") (pinfunction "24_24") (pintype "passive"))
      (node (ref "IC168") (pin "24") (pinfunction "24_24") (pintype "passive"))
    )
    (net (code "1016") (name "Net-(IC169-Pad1)") (class "Default")
      (node (ref "IC169") (pin "1") (pinfunction "1_1") (pintype "passive"))
      (node (ref "IC170") (pin "1") (pinfunction "1_1") (pintype "passive"))
      (node (ref "IC171") (pin "1") (pinfunction "1_1") (pintype "passive"))
      (node (ref "IC172") (pin "1") (pinfunction "1_1") (pintype "passive"))
    )
    (net (code "1017") (name "Net-(IC169-Pad2)") (class "Default")
      (node (ref "IC169") (pin "2") (pinfunction "2_2") (pintype "passive"))
      (node (ref "IC170") (pin "2") (pinfunction "2_2") (pintype "passive"))
      (node (ref "IC171") (pin "2") (pinfunction "2_2") (pintype "passive"))
      (node (ref "IC172") (pin "2") (pinfunction "2_2") (pintype "passive"))
    )
    (net (code "1018") (name "Net-(IC169-Pad3)") (class "Default")
      (node (ref "IC169") (pin "3") (pinfunction "3_3") (pintype "passive"))
      (node (ref "IC170") (pin "3") (pinfunction "3_3") (pintype "passive"))
      (node (ref "IC171") (pin "3") (pinfunction "3_3") (pintype "passive"))
      (node (ref "IC172") (pin "3") (pinfunction "3_3") (pintype "passive"))
    )
    (net (code "1019") (name "Net-(IC169-Pad4)") (class "Default")
      (node (ref "IC169") (pin "4") (pinfunction "4_4") (pintype "passive"))
      (node (ref "IC170") (pin "4") (pinfunction "4_4") (pintype "passive"))
      (node (ref "IC171") (pin "4") (pinfunction "4_4") (pintype "passive"))
      (node (ref "IC172") (pin "4") (pinfunction "4_4") (pintype "passive"))
    )
    (net (code "1020") (name "Net-(IC169-Pad5)") (class "Default")
      (node (ref "IC169") (pin "5") (pinfunction "5_5") (pintype "passive"))
      (node (ref "IC170") (pin "5") (pinfunction "5_5") (pintype "passive"))
      (node (ref "IC171") (pin "5") (pinfunction "5_5") (pintype "passive"))
      (node (ref "IC172") (pin "5") (pinfunction "5_5") (pintype "passive"))
    )
    (net (code "1021") (name "Net-(IC169-Pad6)") (class "Default")
      (node (ref "IC169") (pin "6") (pinfunction "6_6") (pintype "passive"))
      (node (ref "IC170") (pin "6") (pinfunction "6_6") (pintype "passive"))
      (node (ref "IC171") (pin "6") (pinfunction "6_6") (pintype "passive"))
      (node (ref "IC172") (pin "6") (pinfunction "6_6") (pintype "passive"))
    )
    (net (code "1022") (name "Net-(IC169-Pad7)") (class "Default")
      (node (ref "IC169") (pin "7") (pinfunction "7_7") (pintype "passive"))
      (node (ref "IC170") (pin "7") (pinfunction "7_7") (pintype "passive"))
      (node (ref "IC171") (pin "7") (pinfunction "7_7") (pintype "passive"))
      (node (ref "IC172") (pin "7") (pinfunction "7_7") (pintype "passive"))
    )
    (net (code "1023") (name "Net-(IC169-Pad8)") (class "Default")
      (node (ref "IC169") (pin "8") (pinfunction "8_8") (pintype "passive"))
      (node (ref "IC170") (pin "8") (pinfunction "8_8") (pintype "passive"))
      (node (ref "IC171") (pin "8") (pinfunction "8_8") (pintype "passive"))
      (node (ref "IC172") (pin "8") (pinfunction "8_8") (pintype "passive"))
    )
    (net (code "1024") (name "Net-(IC169-Pad9)") (class "Default")
      (node (ref "IC169") (pin "9") (pinfunction "9_9") (pintype "passive"))
      (node (ref "IC170") (pin "9") (pinfunction "9_9") (pintype "passive"))
      (node (ref "IC171") (pin "9") (pinfunction "9_9") (pintype "passive"))
      (node (ref "IC172") (pin "9") (pinfunction "9_9") (pintype "passive"))
    )
    (net (code "1025") (name "Net-(IC169-Pad10)") (class "Default")
      (node (ref "IC169") (pin "10") (pinfunction "10_10") (pintype "passive"))
      (node (ref "IC170") (pin "10") (pinfunction "10_10") (pintype "passive"))
      (node (ref "IC171") (pin "10") (pinfunction "10_10") (pintype "passive"))
      (node (ref "IC172") (pin "10") (pinfunction "10_10") (pintype "passive"))
    )
    (net (code "1026") (name "Net-(IC169-Pad11)") (class "Default")
      (node (ref "IC169") (pin "11") (pinfunction "11_11") (pintype "passive"))
      (node (ref "IC170") (pin "11") (pinfunction "11_11") (pintype "passive"))
      (node (ref "IC171") (pin "11") (pinfunction "11_11") (pintype "passive"))
      (node (ref "IC172") (pin "11") (pinfunction "11_11") (pintype "passive"))
    )
    (net (code "1027") (name "Net-(IC169-Pad12)") (class "Default")
      (node (ref "IC169") (pin "12") (pinfunction "12_12") (pintype "passive"))
      (node (ref "IC170") (pin "12") (pinfunction "12_12") (pintype "passive"))
      (node (ref "IC171") (pin "12") (pinfunction "12_12") (pintype "passive"))
      (node (ref "IC172") (pin "12") (pinfunction "12_12") (pintype "passive"))
    )
    (net (code "1028") (name "Net-(IC169-Pad13)") (class "Default")
      (node (ref "IC169") (pin "13") (pinfunction "13_13") (pintype "passive"))
      (node (ref "IC170") (pin "13") (pinfunction "13_13") (pintype "passive"))
      (node (ref "IC171") (pin "13") (pinfunction "13_13") (pintype "passive"))
      (node (ref "IC172") (pin "13") (pinfunction "13_13") (pintype "passive"))
    )
    (net (code "1029") (name "Net-(IC169-Pad14)") (class "Default")
      (node (ref "IC169") (pin "14") (pinfunction "14_14") (pintype "passive"))
      (node (ref "IC170") (pin "14") (pinfunction "14_14") (pintype "passive"))
      (node (ref "IC171") (pin "14") (pinfunction "14_14") (pintype "passive"))
      (node (ref "IC172") (pin "14") (pinfunction "14_14") (pintype "passive"))
    )
    (net (code "1030") (name "Net-(IC169-Pad15)") (class "Default")
      (node (ref "IC169") (pin "15") (pinfunction "15_15") (pintype "passive"))
      (node (ref "IC170") (pin "15") (pinfunction "15_15") (pintype "passive"))
      (node (ref "IC171") (pin "15") (pinfunction "15_15") (pintype "passive"))
      (node (ref "IC172") (pin "15") (pinfunction "15_15") (pintype "passive"))
    )
    (net (code "1031") (name "Net-(IC169-Pad16)") (class "Default")
      (node (ref "IC169") (pin "16") (pinfunction "16_16") (pintype "passive"))
      (node (ref "IC170") (pin "16") (pinfunction "16_16") (pintype "passive"))
      (node (ref "IC171") (pin "16") (pinfunction "16_16") (pintype "passive"))
      (node (ref "IC172") (pin "16") (pinfunction "16_16") (pintype "passive"))
    )
    (net (code "1032") (name "Net-(IC169-Pad17)") (class "Default")
      (node (ref "IC169") (pin "17") (pinfunction "17_17") (pintype "passive"))
      (node (ref "IC170") (pin "17") (pinfunction "17_17") (pintype "passive"))
      (node (ref "IC171") (pin "17") (pinfunction "17_17") (pintype "passive"))
      (node (ref "IC172") (pin "17") (pinfunction "17_17") (pintype "passive"))
    )
    (net (code "1033") (name "Net-(IC169-Pad18)") (class "Default")
      (node (ref "IC169") (pin "18") (pinfunction "18_18") (pintype "passive"))
      (node (ref "IC170") (pin "18") (pinfunction "18_18") (pintype "passive"))
      (node (ref "IC171") (pin "18") (pinfunction "18_18") (pintype "passive"))
      (node (ref "IC172") (pin "18") (pinfunction "18_18") (pintype "passive"))
    )
    (net (code "1034") (name "Net-(IC169-Pad19)") (class "Default")
      (node (ref "IC169") (pin "19") (pinfunction "19_19") (pintype "passive"))
      (node (ref "IC170") (pin "19") (pinfunction "19_19") (pintype "passive"))
      (node (ref "IC171") (pin "19") (pinfunction "19_19") (pintype "passive"))
      (node (ref "IC172") (pin "19") (pinfunction "19_19") (pintype "passive"))
    )
    (net (code "1035") (name "Net-(IC169-Pad20)") (class "Default")
      (node (ref "IC169") (pin "20") (pinfunction "20_20") (pintype "passive"))
      (node (ref "IC170") (pin "20") (pinfunction "20_20") (pintype "passive"))
      (node (ref "IC171") (pin "20") (pinfunction "20_20") (pintype "passive"))
      (node (ref "IC172") (pin "20") (pinfunction "20_20") (pintype "passive"))
    )
    (net (code "1036") (name "Net-(IC169-Pad21)") (class "Default")
      (node (ref "IC169") (pin "21") (pinfunction "21_21") (pintype "passive"))
      (node (ref "IC170") (pin "21") (pinfunction "21_21") (pintype "passive"))
      (node (ref "IC171") (pin "21") (pinfunction "21_21") (pintype "passive"))
      (node (ref "IC172") (pin "21") (pinfunction "21_21") (pintype "passive"))
    )
    (net (code "1037") (name "Net-(IC169-Pad22)") (class "Default")
      (node (ref "IC169") (pin "22") (pinfunction "22_22") (pintype "passive"))
      (node (ref "IC170") (pin "22") (pinfunction "22_22") (pintype "passive"))
      (node (ref "IC171") (pin "22") (pinfunction "22_22") (pintype "passive"))
      (node (ref "IC172") (pin "22") (pinfunction "22_22") (pintype "passive"))
    )
    (net (code "1038") (name "Net-(IC169-Pad23)") (class "Default")
      (node (ref "IC169") (pin "23") (pinfunction "23_23") (pintype "passive"))
      (node (ref "IC170") (pin "23") (pinfunction "23_23") (pintype "passive"))
      (node (ref "IC171") (pin "23") (pinfunction "23_23") (pintype "passive"))
      (node (ref "IC172") (pin "23") (pinfunction "23_23") (pintype "passive"))
    )
    (net (code "1039") (name "Net-(IC169-Pad24)") (class "Default")
      (node (ref "IC169") (pin "24") (pinfunction "24_24") (pintype "passive"))
      (node (ref "IC170") (pin "24") (pinfunction "24_24") (pintype "passive"))
      (node (ref "IC171") (pin "24") (pinfunction "24_24") (pintype "passive"))
      (node (ref "IC172") (pin "24") (pinfunction "24_24") (pintype "passive"))
    )
    (net (code "1040") (name "Net-(IC173-Pad1)") (class "Default")
      (node (ref "IC173") (pin "1") (pinfunction "1_1") (pintype "passive"))
      (node (ref "IC174") (pin "1") (pinfunction "1_1") (pintype "passive"))
      (node (ref "IC175") (pin "1") (pinfunction "1_1") (pintype "passive"))
      (node (ref "IC176") (pin "1") (pinfunction "1_1") (pintype "passive"))
    )
    (net (code "1041") (name "Net-(IC173-Pad2)") (class "Default")
      (node (ref "IC173") (pin "2") (pinfunction "2_2") (pintype "passive"))
      (node (ref "IC174") (pin "2") (pinfunction "2_2") (pintype "passive"))
      (node (ref "IC175") (pin "2") (pinfunction "2_2") (pintype "passive"))
      (node (ref "IC176") (pin "2") (pinfunction "2_2") (pintype "passive"))
    )
    (net (code "1042") (name "Net-(IC173-Pad3)") (class "Default")
      (node (ref "IC173") (pin "3") (pinfunction "3_3") (pintype "passive"))
      (node (ref "IC174") (pin "3") (pinfunction "3_3") (pintype "passive"))
      (node (ref "IC175") (pin "3") (pinfunction "3_3") (pintype "passive"))
      (node (ref "IC176") (pin "3") (pinfunction "3_3") (pintype "passive"))
    )
    (net (code "1043") (name "Net-(IC173-Pad4)") (class "Default")
      (node (ref "IC173") (pin "4") (pinfunction "4_4") (pintype "passive"))
      (node (ref "IC174") (pin "4") (pinfunction "4_4") (pintype "passive"))
      (node (ref "IC175") (pin "4") (pinfunction "4_4") (pintype "passive"))
      (node (ref "IC176") (pin "4") (pinfunction "4_4") (pintype "passive"))
    )
    (net (code "1044") (name "Net-(IC173-Pad5)") (class "Default")
      (node (ref "IC173") (pin "5") (pinfunction "5_5") (pintype "passive"))
      (node (ref "IC174") (pin "5") (pinfunction "5_5") (pintype "passive"))
      (node (ref "IC175") (pin "5") (pinfunction "5_5") (pintype "passive"))
      (node (ref "IC176") (pin "5") (pinfunction "5_5") (pintype "passive"))
    )
    (net (code "1045") (name "Net-(IC173-Pad6)") (class "Default")
      (node (ref "IC173") (pin "6") (pinfunction "6_6") (pintype "passive"))
      (node (ref "IC174") (pin "6") (pinfunction "6_6") (pintype "passive"))
      (node (ref "IC175") (pin "6") (pinfunction "6_6") (pintype "passive"))
      (node (ref "IC176") (pin "6") (pinfunction "6_6") (pintype "passive"))
    )
    (net (code "1046") (name "Net-(IC173-Pad7)") (class "Default")
      (node (ref "IC173") (pin "7") (pinfunction "7_7") (pintype "passive"))
      (node (ref "IC174") (pin "7") (pinfunction "7_7") (pintype "passive"))
      (node (ref "IC175") (pin "7") (pinfunction "7_7") (pintype "passive"))
      (node (ref "IC176") (pin "7") (pinfunction "7_7") (pintype "passive"))
    )
    (net (code "1047") (name "Net-(IC173-Pad8)") (class "Default")
      (node (ref "IC173") (pin "8") (pinfunction "8_8") (pintype "passive"))
      (node (ref "IC174") (pin "8") (pinfunction "8_8") (pintype "passive"))
      (node (ref "IC175") (pin "8") (pinfunction "8_8") (pintype "passive"))
      (node (ref "IC176") (pin "8") (pinfunction "8_8") (pintype "passive"))
    )
    (net (code "1048") (name "Net-(IC173-Pad9)") (class "Default")
      (node (ref "IC173") (pin "9") (pinfunction "9_9") (pintype "passive"))
      (node (ref "IC174") (pin "9") (pinfunction "9_9") (pintype "passive"))
      (node (ref "IC175") (pin "9") (pinfunction "9_9") (pintype "passive"))
      (node (ref "IC176") (pin "9") (pinfunction "9_9") (pintype "passive"))
    )
    (net (code "1049") (name "Net-(IC173-Pad10)") (class "Default")
      (node (ref "IC173") (pin "10") (pinfunction "10_10") (pintype "passive"))
      (node (ref "IC174") (pin "10") (pinfunction "10_10") (pintype "passive"))
      (node (ref "IC175") (pin "10") (pinfunction "10_10") (pintype "passive"))
      (node (ref "IC176") (pin "10") (pinfunction "10_10") (pintype "passive"))
    )
    (net (code "1050") (name "Net-(IC173-Pad11)") (class "Default")
      (node (ref "IC173") (pin "11") (pinfunction "11_11") (pintype "passive"))
      (node (ref "IC174") (pin "11") (pinfunction "11_11") (pintype "passive"))
      (node (ref "IC175") (pin "11") (pinfunction "11_11") (pintype "passive"))
      (node (ref "IC176") (pin "11") (pinfunction "11_11") (pintype "passive"))
    )
    (net (code "1051") (name "Net-(IC173-Pad12)") (class "Default")
      (node (ref "IC173") (pin "12") (pinfunction "12_12") (pintype "passive"))
      (node (ref "IC174") (pin "12") (pinfunction "12_12") (pintype "passive"))
      (node (ref "IC175") (pin "12") (pinfunction "12_12") (pintype "passive"))
      (node (ref "IC176") (pin "12") (pinfunction "12_12") (pintype "passive"))
    )
    (net (code "1052") (name "Net-(IC173-Pad13)") (class "Default")
      (node (ref "IC173") (pin "13") (pinfunction "13_13") (pintype "passive"))
      (node (ref "IC174") (pin "13") (pinfunction "13_13") (pintype "passive"))
      (node (ref "IC175") (pin "13") (pinfunction "13_13") (pintype "passive"))
      (node (ref "IC176") (pin "13") (pinfunction "13_13") (pintype "passive"))
    )
    (net (code "1053") (name "Net-(IC173-Pad14)") (class "Default")
      (node (ref "IC173") (pin "14") (pinfunction "14_14") (pintype "passive"))
      (node (ref "IC174") (pin "14") (pinfunction "14_14") (pintype "passive"))
      (node (ref "IC175") (pin "14") (pinfunction "14_14") (pintype "passive"))
      (node (ref "IC176") (pin "14") (pinfunction "14_14") (pintype "passive"))
    )
    (net (code "1054") (name "Net-(IC173-Pad15)") (class "Default")
      (node (ref "IC173") (pin "15") (pinfunction "15_15") (pintype "passive"))
      (node (ref "IC174") (pin "15") (pinfunction "15_15") (pintype "passive"))
      (node (ref "IC175") (pin "15") (pinfunction "15_15") (pintype "passive"))
      (node (ref "IC176") (pin "15") (pinfunction "15_15") (pintype "passive"))
    )
    (net (code "1055") (name "Net-(IC173-Pad16)") (class "Default")
      (node (ref "IC173") (pin "16") (pinfunction "16_16") (pintype "passive"))
      (node (ref "IC174") (pin "16") (pinfunction "16_16") (pintype "passive"))
      (node (ref "IC175") (pin "16") (pinfunction "16_16") (pintype "passive"))
      (node (ref "IC176") (pin "16") (pinfunction "16_16") (pintype "passive"))
    )
    (net (code "1056") (name "Net-(IC173-Pad17)") (class "Default")
      (node (ref "IC173") (pin "17") (pinfunction "17_17") (pintype "passive"))
      (node (ref "IC174") (pin "17") (pinfunction "17_17") (pintype "passive"))
      (node (ref "IC175") (pin "17") (pinfunction "17_17") (pintype "passive"))
      (node (ref "IC176") (pin "17") (pinfunction "17_17") (pintype "passive"))
    )
    (net (code "1057") (name "Net-(IC173-Pad18)") (class "Default")
      (node (ref "IC173") (pin "18") (pinfunction "18_18") (pintype "passive"))
      (node (ref "IC174") (pin "18") (pinfunction "18_18") (pintype "passive"))
      (node (ref "IC175") (pin "18") (pinfunction "18_18") (pintype "passive"))
      (node (ref "IC176") (pin "18") (pinfunction "18_18") (pintype "passive"))
    )
    (net (code "1058") (name "Net-(IC173-Pad19)") (class "Default")
      (node (ref "IC173") (pin "19") (pinfunction "19_19") (pintype "passive"))
      (node (ref "IC174") (pin "19") (pinfunction "19_19") (pintype "passive"))
      (node (ref "IC175") (pin "19") (pinfunction "19_19") (pintype "passive"))
      (node (ref "IC176") (pin "19") (pinfunction "19_19") (pintype "passive"))
    )
    (net (code "1059") (name "Net-(IC173-Pad20)") (class "Default")
      (node (ref "IC173") (pin "20") (pinfunction "20_20") (pintype "passive"))
      (node (ref "IC174") (pin "20") (pinfunction "20_20") (pintype "passive"))
      (node (ref "IC175") (pin "20") (pinfunction "20_20") (pintype "passive"))
      (node (ref "IC176") (pin "20") (pinfunction "20_20") (pintype "passive"))
    )
    (net (code "1060") (name "Net-(IC173-Pad21)") (class "Default")
      (node (ref "IC173") (pin "21") (pinfunction "21_21") (pintype "passive"))
      (node (ref "IC174") (pin "21") (pinfunction "21_21") (pintype "passive"))
      (node (ref "IC175") (pin "21") (pinfunction "21_21") (pintype "passive"))
      (node (ref "IC176") (pin "21") (pinfunction "21_21") (pintype "passive"))
    )
    (net (code "1061") (name "Net-(IC173-Pad22)") (class "Default")
      (node (ref "IC173") (pin "22") (pinfunction "22_22") (pintype "passive"))
      (node (ref "IC174") (pin "22") (pinfunction "22_22") (pintype "passive"))
      (node (ref "IC175") (pin "22") (pinfunction "22_22") (pintype "passive"))
      (node (ref "IC176") (pin "22") (pinfunction "22_22") (pintype "passive"))
    )
    (net (code "1062") (name "Net-(IC173-Pad23)") (class "Default")
      (node (ref "IC173") (pin "23") (pinfunction "23_23") (pintype "passive"))
      (node (ref "IC174") (pin "23") (pinfunction "23_23") (pintype "passive"))
      (node (ref "IC175") (pin "23") (pinfunction "23_23") (pintype "passive"))
      (node (ref "IC176") (pin "23") (pinfunction "23_23") (pintype "passive"))
    )
    (net (code "1063") (name "Net-(IC173-Pad24)") (class "Default")
      (node (ref "IC173") (pin "24") (pinfunction "24_24") (pintype "passive"))
      (node (ref "IC174") (pin "24") (pinfunction "24_24") (pintype "passive"))
      (node (ref "IC175") (pin "24") (pinfunction "24_24") (pintype "passive"))
      (node (ref "IC176") (pin "24") (pinfunction "24_24") (pintype "passive"))
    )
    (net (code "1064") (name "Net-(IC177-Pad1)") (class "Default")
      (node (ref "IC177") (pin "1") (pinfunction "1_1") (pintype "passive"))
      (node (ref "IC178") (pin "1") (pinfunction "1_1") (pintype "passive"))
      (node (ref "IC179") (pin "1") (pinfunction "1_1") (pintype "passive"))
      (node (ref "IC180") (pin "1") (pinfunction "1_1") (pintype "passive"))
    )
    (net (code "1065") (name "Net-(IC177-Pad2)") (class "Default")
      (node (ref "IC177") (pin "2") (pinfunction "2_2") (pintype "passive"))
      (node (ref "IC178") (pin "2") (pinfunction "2_2") (pintype "passive"))
      (node (ref "IC179") (pin "2") (pinfunction "2_2") (pintype "passive"))
      (node (ref "IC180") (pin "2") (pinfunction "2_2") (pintype "passive"))
    )
    (net (code "1066") (name "Net-(IC177-Pad3)") (class "Default")
      (node (ref "IC177") (pin "3") (pinfunction "3_3") (pintype "passive"))
      (node (ref "IC178") (pin "3") (pinfunction "3_3") (pintype "passive"))
      (node (ref "IC179") (pin "3") (pinfunction "3_3") (pintype "passive"))
      (node (ref "IC180") (pin "3") (pinfunction "3_3") (pintype "passive"))
    )
    (net (code "1067") (name "Net-(IC177-Pad4)") (class "Default")
      (node (ref "IC177") (pin "4") (pinfunction "4_4") (pintype "passive"))
      (node (ref "IC178") (pin "4") (pinfunction "4_4") (pintype "passive"))
      (node (ref "IC179") (pin "4") (pinfunction "4_4") (pintype "passive"))
      (node (ref "IC180") (pin "4") (pinfunction "4_4") (pintype "passive"))
    )
    (net (code "1068") (name "Net-(IC177-Pad5)") (class "Default")
      (node (ref "IC177") (pin "5") (pinfunction "5_5") (pintype "passive"))
      (node (ref "IC178") (pin "5") (pinfunction "5_5") (pintype "passive"))
      (node (ref "IC179") (pin "5") (pinfunction "5_5") (pintype "passive"))
      (node (ref "IC180") (pin "5") (pinfunction "5_5") (pintype "passive"))
    )
    (net (code "1069") (name "Net-(IC177-Pad6)") (class "Default")
      (node (ref "IC177") (pin "6") (pinfunction "6_6") (pintype "passive"))
      (node (ref "IC178") (pin "6") (pinfunction "6_6") (pintype "passive"))
      (node (ref "IC179") (pin "6") (pinfunction "6_6") (pintype "passive"))
      (node (ref "IC180") (pin "6") (pinfunction "6_6") (pintype "passive"))
    )
    (net (code "1070") (name "Net-(IC177-Pad7)") (class "Default")
      (node (ref "IC177") (pin "7") (pinfunction "7_7") (pintype "passive"))
      (node (ref "IC178") (pin "7") (pinfunction "7_7") (pintype "passive"))
      (node (ref "IC179") (pin "7") (pinfunction "7_7") (pintype "passive"))
      (node (ref "IC180") (pin "7") (pinfunction "7_7") (pintype "passive"))
    )
    (net (code "1071") (name "Net-(IC177-Pad8)") (class "Default")
      (node (ref "IC177") (pin "8") (pinfunction "8_8") (pintype "passive"))
      (node (ref "IC178") (pin "8") (pinfunction "8_8") (pintype "passive"))
      (node (ref "IC179") (pin "8") (pinfunction "8_8") (pintype "passive"))
      (node (ref "IC180") (pin "8") (pinfunction "8_8") (pintype "passive"))
    )
    (net (code "1072") (name "Net-(IC177-Pad9)") (class "Default")
      (node (ref "IC177") (pin "9") (pinfunction "9_9") (pintype "passive"))
      (node (ref "IC178") (pin "9") (pinfunction "9_9") (pintype "passive"))
      (node (ref "IC179") (pin "9") (pinfunction "9_9") (pintype "passive"))
      (node (ref "IC180") (pin "9") (pinfunction "9_9") (pintype "passive"))
    )
    (net (code "1073") (name "Net-(IC177-Pad10)") (class "Default")
      (node (ref "IC177") (pin "10") (pinfunction "10_10") (pintype "passive"))
      (node (ref "IC178") (pin "10") (pinfunction "10_10") (pintype "passive"))
      (node (ref "IC179") (pin "10") (pinfunction "10_10") (pintype "passive"))
      (node (ref "IC180") (pin "10") (pinfunction "10_10") (pintype "passive"))
    )
    (net (code "1074") (name "Net-(IC177-Pad11)") (class "Default")
      (node (ref "IC177") (pin "11") (pinfunction "11_11") (pintype "passive"))
      (node (ref "IC178") (pin "11") (pinfunction "11_11") (pintype "passive"))
      (node (ref "IC179") (pin "11") (pinfunction "11_11") (pintype "passive"))
      (node (ref "IC180") (pin "11") (pinfunction "11_11") (pintype "passive"))
    )
    (net (code "1075") (name "Net-(IC177-Pad12)") (class "Default")
      (node (ref "IC177") (pin "12") (pinfunction "12_12") (pintype "passive"))
      (node (ref "IC178") (pin "12") (pinfunction "12_12") (pintype "passive"))
      (node (ref "IC179") (pin "12") (pinfunction "12_12") (pintype "passive"))
      (node (ref "IC180") (pin "12") (pinfunction "12_12") (pintype "passive"))
    )
    (net (code "1076") (name "Net-(IC177-Pad13)") (class "Default")
      (node (ref "IC177") (pin "13") (pinfunction "13_13") (pintype "passive"))
      (node (ref "IC178") (pin "13") (pinfunction "13_13") (pintype "passive"))
      (node (ref "IC179") (pin "13") (pinfunction "13_13") (pintype "passive"))
      (node (ref "IC180") (pin "13") (pinfunction "13_13") (pintype "passive"))
    )
    (net (code "1077") (name "Net-(IC177-Pad14)") (class "Default")
      (node (ref "IC177") (pin "14") (pinfunction "14_14") (pintype "passive"))
      (node (ref "IC178") (pin "14") (pinfunction "14_14") (pintype "passive"))
      (node (ref "IC179") (pin "14") (pinfunction "14_14") (pintype "passive"))
      (node (ref "IC180") (pin "14") (pinfunction "14_14") (pintype "passive"))
    )
    (net (code "1078") (name "Net-(IC177-Pad15)") (class "Default")
      (node (ref "IC177") (pin "15") (pinfunction "15_15") (pintype "passive"))
      (node (ref "IC178") (pin "15") (pinfunction "15_15") (pintype "passive"))
      (node (ref "IC179") (pin "15") (pinfunction "15_15") (pintype "passive"))
      (node (ref "IC180") (pin "15") (pinfunction "15_15") (pintype "passive"))
    )
    (net (code "1079") (name "Net-(IC177-Pad16)") (class "Default")
      (node (ref "IC177") (pin "16") (pinfunction "16_16") (pintype "passive"))
      (node (ref "IC178") (pin "16") (pinfunction "16_16") (pintype "passive"))
      (node (ref "IC179") (pin "16") (pinfunction "16_16") (pintype "passive"))
      (node (ref "IC180") (pin "16") (pinfunction "16_16") (pintype "passive"))
    )
    (net (code "1080") (name "Net-(IC177-Pad17)") (class "Default")
      (node (ref "IC177") (pin "17") (pinfunction "17_17") (pintype "passive"))
      (node (ref "IC178") (pin "17") (pinfunction "17_17") (pintype "passive"))
      (node (ref "IC179") (pin "17") (pinfunction "17_17") (pintype "passive"))
      (node (ref "IC180") (pin "17") (pinfunction "17_17") (pintype "passive"))
    )
    (net (code "1081") (name "Net-(IC177-Pad18)") (class "Default")
      (node (ref "IC177") (pin "18") (pinfunction "18_18") (pintype "passive"))
      (node (ref "IC178") (pin "18") (pinfunction "18_18") (pintype "passive"))
      (node (ref "IC179") (pin "18") (pinfunction "18_18") (pintype "passive"))
      (node (ref "IC180") (pin "18") (pinfunction "18_18") (pintype "passive"))
    )
    (net (code "1082") (name "Net-(IC177-Pad19)") (class "Default")
      (node (ref "IC177") (pin "19") (pinfunction "19_19") (pintype "passive"))
      (node (ref "IC178") (pin "19") (pinfunction "19_19") (pintype "passive"))
      (node (ref "IC179") (pin "19") (pinfunction "19_19") (pintype "passive"))
      (node (ref "IC180") (pin "19") (pinfunction "19_19") (pintype "passive"))
    )
    (net (code "1083") (name "Net-(IC177-Pad20)") (class "Default")
      (node (ref "IC177") (pin "20") (pinfunction "20_20") (pintype "passive"))
      (node (ref "IC178") (pin "20") (pinfunction "20_20") (pintype "passive"))
      (node (ref "IC179") (pin "20") (pinfunction "20_20") (pintype "passive"))
      (node (ref "IC180") (pin "20") (pinfunction "20_20") (pintype "passive"))
    )
    (net (code "1084") (name "Net-(IC177-Pad21)") (class "Default")
      (node (ref "IC177") (pin "21") (pinfunction "21_21") (pintype "passive"))
      (node (ref "IC178") (pin "21") (pinfunction "21_21") (pintype "passive"))
      (node (ref "IC179") (pin "21") (pinfunction "21_21") (pintype "passive"))
      (node (ref "IC180") (pin "21") (pinfunction "21_21") (pintype "passive"))
    )
    (net (code "1085") (name "Net-(IC177-Pad22)") (class "Default")
      (node (ref "IC177") (pin "22") (pinfunction "22_22") (pintype "passive"))
      (node (ref "IC178") (pin "22") (pinfunction "22_22") (pintype "passive"))
      (node (ref "IC179") (pin "22") (pinfunction "22_22") (pintype "passive"))
      (node (ref "IC180") (pin "22") (pinfunction "22_22") (pintype "passive"))
    )
    (net (code "1086") (name "Net-(IC177-Pad23)") (class "Default")
      (node (ref "IC177") (pin "23") (pinfunction "23_23") (pintype "passive"))
      (node (ref "IC178") (pin "23") (pinfunction "23_23") (pintype "passive"))
      (node (ref "IC179") (pin "23") (pinfunction "23_23") (pintype "passive"))
      (node (ref "IC180") (pin "23") (pinfunction "23_23") (pintype "passive"))
    )
    (net (code "1087") (name "Net-(IC177-Pad24)") (class "Default")
      (node (ref "IC177") (pin "24") (pinfunction "24_24") (pintype "passive"))
      (node (ref "IC178") (pin "24") (pinfunction "24_24") (pintype "passive"))
      (node (ref "IC179") (pin "24") (pinfunction "24_24") (pintype "passive"))
      (node (ref "IC180") (pin "24") (pinfunction "24_24") (pintype "passive"))
    )
    (net (code "1088") (name "Net-(IC181-Pad1)") (class "Default")
      (node (ref "IC181") (pin "1") (pinfunction "1_1") (pintype "passive"))
      (node (ref "IC182") (pin "1") (pinfunction "1_1") (pintype "passive"))
      (node (ref "IC183") (pin "1") (pinfunction "1_1") (pintype "passive"))
      (node (ref "IC184") (pin "1") (pinfunction "1_1") (pintype "passive"))
    )
    (net (code "1089") (name "Net-(IC181-Pad2)") (class "Default")
      (node (ref "IC181") (pin "2") (pinfunction "2_2") (pintype "passive"))
      (node (ref "IC182") (pin "2") (pinfunction "2_2") (pintype "passive"))
      (node (ref "IC183") (pin "2") (pinfunction "2_2") (pintype "passive"))
      (node (ref "IC184") (pin "2") (pinfunction "2_2") (pintype "passive"))
    )
    (net (code "1090") (name "Net-(IC181-Pad3)") (class "Default")
      (node (ref "IC181") (pin "3") (pinfunction "3_3") (pintype "passive"))
      (node (ref "IC182") (pin "3") (pinfunction "3_3") (pintype "passive"))
      (node (ref "IC183") (pin "3") (pinfunction "3_3") (pintype "passive"))
      (node (ref "IC184") (pin "3") (pinfunction "3_3") (pintype "passive"))
    )
    (net (code "1091") (name "Net-(IC181-Pad4)") (class "Default")
      (node (ref "IC181") (pin "4") (pinfunction "4_4") (pintype "passive"))
      (node (ref "IC182") (pin "4") (pinfunction "4_4") (pintype "passive"))
      (node (ref "IC183") (pin "4") (pinfunction "4_4") (pintype "passive"))
      (node (ref "IC184") (pin "4") (pinfunction "4_4") (pintype "passive"))
    )
    (net (code "1092") (name "Net-(IC181-Pad5)") (class "Default")
      (node (ref "IC181") (pin "5") (pinfunction "5_5") (pintype "passive"))
      (node (ref "IC182") (pin "5") (pinfunction "5_5") (pintype "passive"))
      (node (ref "IC183") (pin "5") (pinfunction "5_5") (pintype "passive"))
      (node (ref "IC184") (pin "5") (pinfunction "5_5") (pintype "passive"))
    )
    (net (code "1093") (name "Net-(IC181-Pad6)") (class "Default")
      (node (ref "IC181") (pin "6") (pinfunction "6_6") (pintype "passive"))
      (node (ref "IC182") (pin "6") (pinfunction "6_6") (pintype "passive"))
      (node (ref "IC183") (pin "6") (pinfunction "6_6") (pintype "passive"))
      (node (ref "IC184") (pin "6") (pinfunction "6_6") (pintype "passive"))
    )
    (net (code "1094") (name "Net-(IC181-Pad7)") (class "Default")
      (node (ref "IC181") (pin "7") (pinfunction "7_7") (pintype "passive"))
      (node (ref "IC182") (pin "7") (pinfunction "7_7") (pintype "passive"))
      (node (ref "IC183") (pin "7") (pinfunction "7_7") (pintype "passive"))
      (node (ref "IC184") (pin "7") (pinfunction "7_7") (pintype "passive"))
    )
    (net (code "1095") (name "Net-(IC181-Pad8)") (class "Default")
      (node (ref "IC181") (pin "8") (pinfunction "8_8") (pintype "passive"))
      (node (ref "IC182") (pin "8") (pinfunction "8_8") (pintype "passive"))
      (node (ref "IC183") (pin "8") (pinfunction "8_8") (pintype "passive"))
      (node (ref "IC184") (pin "8") (pinfunction "8_8") (pintype "passive"))
    )
    (net (code "1096") (name "Net-(IC181-Pad9)") (class "Default")
      (node (ref "IC181") (pin "9") (pinfunction "9_9") (pintype "passive"))
      (node (ref "IC182") (pin "9") (pinfunction "9_9") (pintype "passive"))
      (node (ref "IC183") (pin "9") (pinfunction "9_9") (pintype "passive"))
      (node (ref "IC184") (pin "9") (pinfunction "9_9") (pintype "passive"))
    )
    (net (code "1097") (name "Net-(IC181-Pad10)") (class "Default")
      (node (ref "IC181") (pin "10") (pinfunction "10_10") (pintype "passive"))
      (node (ref "IC182") (pin "10") (pinfunction "10_10") (pintype "passive"))
      (node (ref "IC183") (pin "10") (pinfunction "10_10") (pintype "passive"))
      (node (ref "IC184") (pin "10") (pinfunction "10_10") (pintype "passive"))
    )
    (net (code "1098") (name "Net-(IC181-Pad11)") (class "Default")
      (node (ref "IC181") (pin "11") (pinfunction "11_11") (pintype "passive"))
      (node (ref "IC182") (pin "11") (pinfunction "11_11") (pintype "passive"))
      (node (ref "IC183") (pin "11") (pinfunction "11_11") (pintype "passive"))
      (node (ref "IC184") (pin "11") (pinfunction "11_11") (pintype "passive"))
    )
    (net (code "1099") (name "Net-(IC181-Pad12)") (class "Default")
      (node (ref "IC181") (pin "12") (pinfunction "12_12") (pintype "passive"))
      (node (ref "IC182") (pin "12") (pinfunction "12_12") (pintype "passive"))
      (node (ref "IC183") (pin "12") (pinfunction "12_12") (pintype "passive"))
      (node (ref "IC184") (pin "12") (pinfunction "12_12") (pintype "passive"))
    )
    (net (code "1100") (name "Net-(IC181-Pad13)") (class "Default")
      (node (ref "IC181") (pin "13") (pinfunction "13_13") (pintype "passive"))
      (node (ref "IC182") (pin "13") (pinfunction "13_13") (pintype "passive"))
      (node (ref "IC183") (pin "13") (pinfunction "13_13") (pintype "passive"))
      (node (ref "IC184") (pin "13") (pinfunction "13_13") (pintype "passive"))
    )
    (net (code "1101") (name "Net-(IC181-Pad14)") (class "Default")
      (node (ref "IC181") (pin "14") (pinfunction "14_14") (pintype "passive"))
      (node (ref "IC182") (pin "14") (pinfunction "14_14") (pintype "passive"))
      (node (ref "IC183") (pin "14") (pinfunction "14_14") (pintype "passive"))
      (node (ref "IC184") (pin "14") (pinfunction "14_14") (pintype "passive"))
    )
    (net (code "1102") (name "Net-(IC181-Pad15)") (class "Default")
      (node (ref "IC181") (pin "15") (pinfunction "15_15") (pintype "passive"))
      (node (ref "IC182") (pin "15") (pinfunction "15_15") (pintype "passive"))
      (node (ref "IC183") (pin "15") (pinfunction "15_15") (pintype "passive"))
      (node (ref "IC184") (pin "15") (pinfunction "15_15") (pintype "passive"))
    )
    (net (code "1103") (name "Net-(IC181-Pad16)") (class "Default")
      (node (ref "IC181") (pin "16") (pinfunction "16_16") (pintype "passive"))
      (node (ref "IC182") (pin "16") (pinfunction "16_16") (pintype "passive"))
      (node (ref "IC183") (pin "16") (pinfunction "16_16") (pintype "passive"))
      (node (ref "IC184") (pin "16") (pinfunction "16_16") (pintype "passive"))
    )
    (net (code "1104") (name "Net-(IC181-Pad17)") (class "Default")
      (node (ref "IC181") (pin "17") (pinfunction "17_17") (pintype "passive"))
      (node (ref "IC182") (pin "17") (pinfunction "17_17") (pintype "passive"))
      (node (ref "IC183") (pin "17") (pinfunction "17_17") (pintype "passive"))
      (node (ref "IC184") (pin "17") (pinfunction "17_17") (pintype "passive"))
    )
    (net (code "1105") (name "Net-(IC181-Pad18)") (class "Default")
      (node (ref "IC181") (pin "18") (pinfunction "18_18") (pintype "passive"))
      (node (ref "IC182") (pin "18") (pinfunction "18_18") (pintype "passive"))
      (node (ref "IC183") (pin "18") (pinfunction "18_18") (pintype "passive"))
      (node (ref "IC184") (pin "18") (pinfunction "18_18") (pintype "passive"))
    )
    (net (code "1106") (name "Net-(IC181-Pad19)") (class "Default")
      (node (ref "IC181") (pin "19") (pinfunction "19_19") (pintype "passive"))
      (node (ref "IC182") (pin "19") (pinfunction "19_19") (pintype "passive"))
      (node (ref "IC183") (pin "19") (pinfunction "19_19") (pintype "passive"))
      (node (ref "IC184") (pin "19") (pinfunction "19_19") (pintype "passive"))
    )
    (net (code "1107") (name "Net-(IC181-Pad20)") (class "Default")
      (node (ref "IC181") (pin "20") (pinfunction "20_20") (pintype "passive"))
      (node (ref "IC182") (pin "20") (pinfunction "20_20") (pintype "passive"))
      (node (ref "IC183") (pin "20") (pinfunction "20_20") (pintype "passive"))
      (node (ref "IC184") (pin "20") (pinfunction "20_20") (pintype "passive"))
    )
    (net (code "1108") (name "Net-(IC181-Pad21)") (class "Default")
      (node (ref "IC181") (pin "21") (pinfunction "21_21") (pintype "passive"))
      (node (ref "IC182") (pin "21") (pinfunction "21_21") (pintype "passive"))
      (node (ref "IC183") (pin "21") (pinfunction "21_21") (pintype "passive"))
      (node (ref "IC184") (pin "21") (pinfunction "21_21") (pintype "passive"))
    )
    (net (code "1109") (name "Net-(IC181-Pad22)") (class "Default")
      (node (ref "IC181") (pin "22") (pinfunction "22_22") (pintype "passive"))
      (node (ref "IC182") (pin "22") (pinfunction "22_22") (pintype "passive"))
      (node (ref "IC183") (pin "22") (pinfunction "22_22") (pintype "passive"))
      (node (ref "IC184") (pin "22") (pinfunction "22_22") (pintype "passive"))
    )
    (net (code "1110") (name "Net-(IC181-Pad23)") (class "Default")
      (node (ref "IC181") (pin "23") (pinfunction "23_23") (pintype "passive"))
      (node (ref "IC182") (pin "23") (pinfunction "23_23") (pintype "passive"))
      (node (ref "IC183") (pin "23") (pinfunction "23_23") (pintype "passive"))
      (node (ref "IC184") (pin "23") (pinfunction "23_23") (pintype "passive"))
    )
    (net (code "1111") (name "Net-(IC181-Pad24)") (class "Default")
      (node (ref "IC181") (pin "24") (pinfunction "24_24") (pintype "passive"))
      (node (ref "IC182") (pin "24") (pinfunction "24_24") (pintype "passive"))
      (node (ref "IC183") (pin "24") (pinfunction "24_24") (pintype "passive"))
      (node (ref "IC184") (pin "24") (pinfunction "24_24") (pintype "passive"))
    )
    (net (code "1112") (name "Net-(IC185-Pad1)") (class "Default")
      (node (ref "IC185") (pin "1") (pinfunction "1_1") (pintype "passive"))
      (node (ref "IC186") (pin "1") (pinfunction "1_1") (pintype "passive"))
      (node (ref "IC187") (pin "1") (pinfunction "1_1") (pintype "passive"))
      (node (ref "IC188") (pin "1") (pinfunction "1_1") (pintype "passive"))
    )
    (net (code "1113") (name "Net-(IC185-Pad2)") (class "Default")
      (node (ref "IC185") (pin "2") (pinfunction "2_2") (pintype "passive"))
      (node (ref "IC186") (pin "2") (pinfunction "2_2") (pintype "passive"))
      (node (ref "IC187") (pin "2") (pinfunction "2_2") (pintype "passive"))
      (node (ref "IC188") (pin "2") (pinfunction "2_2") (pintype "passive"))
    )
    (net (code "1114") (name "Net-(IC185-Pad3)") (class "Default")
      (node (ref "IC185") (pin "3") (pinfunction "3_3") (pintype "passive"))
      (node (ref "IC186") (pin "3") (pinfunction "3_3") (pintype "passive"))
      (node (ref "IC187") (pin "3") (pinfunction "3_3") (pintype "passive"))
      (node (ref "IC188") (pin "3") (pinfunction "3_3") (pintype "passive"))
    )
    (net (code "1115") (name "Net-(IC185-Pad4)") (class "Default")
      (node (ref "IC185") (pin "4") (pinfunction "4_4") (pintype "passive"))
      (node (ref "IC186") (pin "4") (pinfunction "4_4") (pintype "passive"))
      (node (ref "IC187") (pin "4") (pinfunction "4_4") (pintype "passive"))
      (node (ref "IC188") (pin "4") (pinfunction "4_4") (pintype "passive"))
    )
    (net (code "1116") (name "Net-(IC185-Pad5)") (class "Default")
      (node (ref "IC185") (pin "5") (pinfunction "5_5") (pintype "passive"))
      (node (ref "IC186") (pin "5") (pinfunction "5_5") (pintype "passive"))
      (node (ref "IC187") (pin "5") (pinfunction "5_5") (pintype "passive"))
      (node (ref "IC188") (pin "5") (pinfunction "5_5") (pintype "passive"))
    )
    (net (code "1117") (name "Net-(IC185-Pad6)") (class "Default")
      (node (ref "IC185") (pin "6") (pinfunction "6_6") (pintype "passive"))
      (node (ref "IC186") (pin "6") (pinfunction "6_6") (pintype "passive"))
      (node (ref "IC187") (pin "6") (pinfunction "6_6") (pintype "passive"))
      (node (ref "IC188") (pin "6") (pinfunction "6_6") (pintype "passive"))
    )
    (net (code "1118") (name "Net-(IC185-Pad7)") (class "Default")
      (node (ref "IC185") (pin "7") (pinfunction "7_7") (pintype "passive"))
      (node (ref "IC186") (pin "7") (pinfunction "7_7") (pintype "passive"))
      (node (ref "IC187") (pin "7") (pinfunction "7_7") (pintype "passive"))
      (node (ref "IC188") (pin "7") (pinfunction "7_7") (pintype "passive"))
    )
    (net (code "1119") (name "Net-(IC185-Pad8)") (class "Default")
      (node (ref "IC185") (pin "8") (pinfunction "8_8") (pintype "passive"))
      (node (ref "IC186") (pin "8") (pinfunction "8_8") (pintype "passive"))
      (node (ref "IC187") (pin "8") (pinfunction "8_8") (pintype "passive"))
      (node (ref "IC188") (pin "8") (pinfunction "8_8") (pintype "passive"))
    )
    (net (code "1120") (name "Net-(IC185-Pad9)") (class "Default")
      (node (ref "IC185") (pin "9") (pinfunction "9_9") (pintype "passive"))
      (node (ref "IC186") (pin "9") (pinfunction "9_9") (pintype "passive"))
      (node (ref "IC187") (pin "9") (pinfunction "9_9") (pintype "passive"))
      (node (ref "IC188") (pin "9") (pinfunction "9_9") (pintype "passive"))
    )
    (net (code "1121") (name "Net-(IC185-Pad10)") (class "Default")
      (node (ref "IC185") (pin "10") (pinfunction "10_10") (pintype "passive"))
      (node (ref "IC186") (pin "10") (pinfunction "10_10") (pintype "passive"))
      (node (ref "IC187") (pin "10") (pinfunction "10_10") (pintype "passive"))
      (node (ref "IC188") (pin "10") (pinfunction "10_10") (pintype "passive"))
    )
    (net (code "1122") (name "Net-(IC185-Pad11)") (class "Default")
      (node (ref "IC185") (pin "11") (pinfunction "11_11") (pintype "passive"))
      (node (ref "IC186") (pin "11") (pinfunction "11_11") (pintype "passive"))
      (node (ref "IC187") (pin "11") (pinfunction "11_11") (pintype "passive"))
      (node (ref "IC188") (pin "11") (pinfunction "11_11") (pintype "passive"))
    )
    (net (code "1123") (name "Net-(IC185-Pad12)") (class "Default")
      (node (ref "IC185") (pin "12") (pinfunction "12_12") (pintype "passive"))
      (node (ref "IC186") (pin "12") (pinfunction "12_12") (pintype "passive"))
      (node (ref "IC187") (pin "12") (pinfunction "12_12") (pintype "passive"))
      (node (ref "IC188") (pin "12") (pinfunction "12_12") (pintype "passive"))
    )
    (net (code "1124") (name "Net-(IC185-Pad13)") (class "Default")
      (node (ref "IC185") (pin "13") (pinfunction "13_13") (pintype "passive"))
      (node (ref "IC186") (pin "13") (pinfunction "13_13") (pintype "passive"))
      (node (ref "IC187") (pin "13") (pinfunction "13_13") (pintype "passive"))
      (node (ref "IC188") (pin "13") (pinfunction "13_13") (pintype "passive"))
    )
    (net (code "1125") (name "Net-(IC185-Pad14)") (class "Default")
      (node (ref "IC185") (pin "14") (pinfunction "14_14") (pintype "passive"))
      (node (ref "IC186") (pin "14") (pinfunction "14_14") (pintype "passive"))
      (node (ref "IC187") (pin "14") (pinfunction "14_14") (pintype "passive"))
      (node (ref "IC188") (pin "14") (pinfunction "14_14") (pintype "passive"))
    )
    (net (code "1126") (name "Net-(IC185-Pad15)") (class "Default")
      (node (ref "IC185") (pin "15") (pinfunction "15_15") (pintype "passive"))
      (node (ref "IC186") (pin "15") (pinfunction "15_15") (pintype "passive"))
      (node (ref "IC187") (pin "15") (pinfunction "15_15") (pintype "passive"))
      (node (ref "IC188") (pin "15") (pinfunction "15_15") (pintype "passive"))
    )
    (net (code "1127") (name "Net-(IC185-Pad16)") (class "Default")
      (node (ref "IC185") (pin "16") (pinfunction "16_16") (pintype "passive"))
      (node (ref "IC186") (pin "16") (pinfunction "16_16") (pintype "passive"))
      (node (ref "IC187") (pin "16") (pinfunction "16_16") (pintype "passive"))
      (node (ref "IC188") (pin "16") (pinfunction "16_16") (pintype "passive"))
    )
    (net (code "1128") (name "Net-(IC185-Pad17)") (class "Default")
      (node (ref "IC185") (pin "17") (pinfunction "17_17") (pintype "passive"))
      (node (ref "IC186") (pin "17") (pinfunction "17_17") (pintype "passive"))
      (node (ref "IC187") (pin "17") (pinfunction "17_17") (pintype "passive"))
      (node (ref "IC188") (pin "17") (pinfunction "17_17") (pintype "passive"))
    )
    (net (code "1129") (name "Net-(IC185-Pad18)") (class "Default")
      (node (ref "IC185") (pin "18") (pinfunction "18_18") (pintype "passive"))
      (node (ref "IC186") (pin "18") (pinfunction "18_18") (pintype "passive"))
      (node (ref "IC187") (pin "18") (pinfunction "18_18") (pintype "passive"))
      (node (ref "IC188") (pin "18") (pinfunction "18_18") (pintype "passive"))
    )
    (net (code "1130") (name "Net-(IC185-Pad19)") (class "Default")
      (node (ref "IC185") (pin "19") (pinfunction "19_19") (pintype "passive"))
      (node (ref "IC186") (pin "19") (pinfunction "19_19") (pintype "passive"))
      (node (ref "IC187") (pin "19") (pinfunction "19_19") (pintype "passive"))
      (node (ref "IC188") (pin "19") (pinfunction "19_19") (pintype "passive"))
    )
    (net (code "1131") (name "Net-(IC185-Pad20)") (class "Default")
      (node (ref "IC185") (pin "20") (pinfunction "20_20") (pintype "passive"))
      (node (ref "IC186") (pin "20") (pinfunction "20_20") (pintype "passive"))
      (node (ref "IC187") (pin "20") (pinfunction "20_20") (pintype "passive"))
      (node (ref "IC188") (pin "20") (pinfunction "20_20") (pintype "passive"))
    )
    (net (code "1132") (name "Net-(IC185-Pad21)") (class "Default")
      (node (ref "IC185") (pin "21") (pinfunction "21_21") (pintype "passive"))
      (node (ref "IC186") (pin "21") (pinfunction "21_21") (pintype "passive"))
      (node (ref "IC187") (pin "21") (pinfunction "21_21") (pintype "passive"))
      (node (ref "IC188") (pin "21") (pinfunction "21_21") (pintype "passive"))
    )
    (net (code "1133") (name "Net-(IC185-Pad22)") (class "Default")
      (node (ref "IC185") (pin "22") (pinfunction "22_22") (pintype "passive"))
      (node (ref "IC186") (pin "22") (pinfunction "22_22") (pintype "passive"))
      (node (ref "IC187") (pin "22") (pinfunction "22_22") (pintype "passive"))
      (node (ref "IC188") (pin "22") (pinfunction "22_22") (pintype "passive"))
    )
    (net (code "1134") (name "Net-(IC185-Pad23)") (class "Default")
      (node (ref "IC185") (pin "23") (pinfunction "23_23") (pintype "passive"))
      (node (ref "IC186") (pin "23") (pinfunction "23_23") (pintype "passive"))
      (node (ref "IC187") (pin "23") (pinfunction "23_23") (pintype "passive"))
      (node (ref "IC188") (pin "23") (pinfunction "23_23") (pintype "passive"))
    )
    (net (code "1135") (name "Net-(IC185-Pad24)") (class "Default")
      (node (ref "IC185") (pin "24") (pinfunction "24_24") (pintype "passive"))
      (node (ref "IC186") (pin "24") (pinfunction "24_24") (pintype "passive"))
      (node (ref "IC187") (pin "24") (pinfunction "24_24") (pintype "passive"))
      (node (ref "IC188") (pin "24") (pinfunction "24_24") (pintype "passive"))
    )
    (net (code "1136") (name "Net-(IC189-Pad1)") (class "Default")
      (node (ref "IC189") (pin "1") (pinfunction "1_1") (pintype "passive"))
      (node (ref "IC190") (pin "1") (pinfunction "1_1") (pintype "passive"))
      (node (ref "IC191") (pin "1") (pinfunction "1_1") (pintype "passive"))
      (node (ref "IC192") (pin "1") (pinfunction "1_1") (pintype "passive"))
    )
    (net (code "1137") (name "Net-(IC189-Pad2)") (class "Default")
      (node (ref "IC189") (pin "2") (pinfunction "2_2") (pintype "passive"))
      (node (ref "IC190") (pin "2") (pinfunction "2_2") (pintype "passive"))
      (node (ref "IC191") (pin "2") (pinfunction "2_2") (pintype "passive"))
      (node (ref "IC192") (pin "2") (pinfunction "2_2") (pintype "passive"))
    )
    (net (code "1138") (name "Net-(IC189-Pad3)") (class "Default")
      (node (ref "IC189") (pin "3") (pinfunction "3_3") (pintype "passive"))
      (node (ref "IC190") (pin "3") (pinfunction "3_3") (pintype "passive"))
      (node (ref "IC191") (pin "3") (pinfunction "3_3") (pintype "passive"))
      (node (ref "IC192") (pin "3") (pinfunction "3_3") (pintype "passive"))
    )
    (net (code "1139") (name "Net-(IC189-Pad4)") (class "Default")
      (node (ref "IC189") (pin "4") (pinfunction "4_4") (pintype "passive"))
      (node (ref "IC190") (pin "4") (pinfunction "4_4") (pintype "passive"))
      (node (ref "IC191") (pin "4") (pinfunction "4_4") (pintype "passive"))
      (node (ref "IC192") (pin "4") (pinfunction "4_4") (pintype "passive"))
    )
    (net (code "1140") (name "Net-(IC189-Pad5)") (class "Default")
      (node (ref "IC189") (pin "5") (pinfunction "5_5") (pintype "passive"))
      (node (ref "IC190") (pin "5") (pinfunction "5_5") (pintype "passive"))
      (node (ref "IC191") (pin "5") (pinfunction "5_5") (pintype "passive"))
      (node (ref "IC192") (pin "5") (pinfunction "5_5") (pintype "passive"))
    )
    (net (code "1141") (name "Net-(IC189-Pad6)") (class "Default")
      (node (ref "IC189") (pin "6") (pinfunction "6_6") (pintype "passive"))
      (node (ref "IC190") (pin "6") (pinfunction "6_6") (pintype "passive"))
      (node (ref "IC191") (pin "6") (pinfunction "6_6") (pintype "passive"))
      (node (ref "IC192") (pin "6") (pinfunction "6_6") (pintype "passive"))
    )
    (net (code "1142") (name "Net-(IC189-Pad7)") (class "Default")
      (node (ref "IC189") (pin "7") (pinfunction "7_7") (pintype "passive"))
      (node (ref "IC190") (pin "7") (pinfunction "7_7") (pintype "passive"))
      (node (ref "IC191") (pin "7") (pinfunction "7_7") (pintype "passive"))
      (node (ref "IC192") (pin "7") (pinfunction "7_7") (pintype "passive"))
    )
    (net (code "1143") (name "Net-(IC189-Pad8)") (class "Default")
      (node (ref "IC189") (pin "8") (pinfunction "8_8") (pintype "passive"))
      (node (ref "IC190") (pin "8") (pinfunction "8_8") (pintype "passive"))
      (node (ref "IC191") (pin "8") (pinfunction "8_8") (pintype "passive"))
      (node (ref "IC192") (pin "8") (pinfunction "8_8") (pintype "passive"))
    )
    (net (code "1144") (name "Net-(IC189-Pad9)") (class "Default")
      (node (ref "IC189") (pin "9") (pinfunction "9_9") (pintype "passive"))
      (node (ref "IC190") (pin "9") (pinfunction "9_9") (pintype "passive"))
      (node (ref "IC191") (pin "9") (pinfunction "9_9") (pintype "passive"))
      (node (ref "IC192") (pin "9") (pinfunction "9_9") (pintype "passive"))
    )
    (net (code "1145") (name "Net-(IC189-Pad10)") (class "Default")
      (node (ref "IC189") (pin "10") (pinfunction "10_10") (pintype "passive"))
      (node (ref "IC190") (pin "10") (pinfunction "10_10") (pintype "passive"))
      (node (ref "IC191") (pin "10") (pinfunction "10_10") (pintype "passive"))
      (node (ref "IC192") (pin "10") (pinfunction "10_10") (pintype "passive"))
    )
    (net (code "1146") (name "Net-(IC189-Pad11)") (class "Default")
      (node (ref "IC189") (pin "11") (pinfunction "11_11") (pintype "passive"))
      (node (ref "IC190") (pin "11") (pinfunction "11_11") (pintype "passive"))
      (node (ref "IC191") (pin "11") (pinfunction "11_11") (pintype "passive"))
      (node (ref "IC192") (pin "11") (pinfunction "11_11") (pintype "passive"))
    )
    (net (code "1147") (name "Net-(IC189-Pad12)") (class "Default")
      (node (ref "IC189") (pin "12") (pinfunction "12_12") (pintype "passive"))
      (node (ref "IC190") (pin "12") (pinfunction "12_12") (pintype "passive"))
      (node (ref "IC191") (pin "12") (pinfunction "12_12") (pintype "passive"))
      (node (ref "IC192") (pin "12") (pinfunction "12_12") (pintype "passive"))
    )
    (net (code "1148") (name "Net-(IC189-Pad13)") (class "Default")
      (node (ref "IC189") (pin "13") (pinfunction "13_13") (pintype "passive"))
      (node (ref "IC190") (pin "13") (pinfunction "13_13") (pintype "passive"))
      (node (ref "IC191") (pin "13") (pinfunction "13_13") (pintype "passive"))
      (node (ref "IC192") (pin "13") (pinfunction "13_13") (pintype "passive"))
    )
    (net (code "1149") (name "Net-(IC189-Pad14)") (class "Default")
      (node (ref "IC189") (pin "14") (pinfunction "14_14") (pintype "passive"))
      (node (ref "IC190") (pin "14") (pinfunction "14_14") (pintype "passive"))
      (node (ref "IC191") (pin "14") (pinfunction "14_14") (pintype "passive"))
      (node (ref "IC192") (pin "14") (pinfunction "14_14") (pintype "passive"))
    )
    (net (code "1150") (name "Net-(IC189-Pad15)") (class "Default")
      (node (ref "IC189") (pin "15") (pinfunction "15_15") (pintype "passive"))
      (node (ref "IC190") (pin "15") (pinfunction "15_15") (pintype "passive"))
      (node (ref "IC191") (pin "15") (pinfunction "15_15") (pintype "passive"))
      (node (ref "IC192") (pin "15") (pinfunction "15_15") (pintype "passive"))
    )
    (net (code "1151") (name "Net-(IC189-Pad16)") (class "Default")
      (node (ref "IC189") (pin "16") (pinfunction "16_16") (pintype "passive"))
      (node (ref "IC190") (pin "16") (pinfunction "16_16") (pintype "passive"))
      (node (ref "IC191") (pin "16") (pinfunction "16_16") (pintype "passive"))
      (node (ref "IC192") (pin "16") (pinfunction "16_16") (pintype "passive"))
    )
    (net (code "1152") (name "Net-(IC189-Pad17)") (class "Default")
      (node (ref "IC189") (pin "17") (pinfunction "17_17") (pintype "passive"))
      (node (ref "IC190") (pin "17") (pinfunction "17_17") (pintype "passive"))
      (node (ref "IC191") (pin "17") (pinfunction "17_17") (pintype "passive"))
      (node (ref "IC192") (pin "17") (pinfunction "17_17") (pintype "passive"))
    )
    (net (code "1153") (name "Net-(IC189-Pad18)") (class "Default")
      (node (ref "IC189") (pin "18") (pinfunction "18_18") (pintype "passive"))
      (node (ref "IC190") (pin "18") (pinfunction "18_18") (pintype "passive"))
      (node (ref "IC191") (pin "18") (pinfunction "18_18") (pintype "passive"))
      (node (ref "IC192") (pin "18") (pinfunction "18_18") (pintype "passive"))
    )
    (net (code "1154") (name "Net-(IC189-Pad19)") (class "Default")
      (node (ref "IC189") (pin "19") (pinfunction "19_19") (pintype "passive"))
      (node (ref "IC190") (pin "19") (pinfunction "19_19") (pintype "passive"))
      (node (ref "IC191") (pin "19") (pinfunction "19_19") (pintype "passive"))
      (node (ref "IC192") (pin "19") (pinfunction "19_19") (pintype "passive"))
    )
    (net (code "1155") (name "Net-(IC189-Pad20)") (class "Default")
      (node (ref "IC189") (pin "20") (pinfunction "20_20") (pintype "passive"))
      (node (ref "IC190") (pin "20") (pinfunction "20_20") (pintype "passive"))
      (node (ref "IC191") (pin "20") (pinfunction "20_20") (pintype "passive"))
      (node (ref "IC192") (pin "20") (pinfunction "20_20") (pintype "passive"))
    )
    (net (code "1156") (name "Net-(IC189-Pad21)") (class "Default")
      (node (ref "IC189") (pin "21") (pinfunction "21_21") (pintype "passive"))
      (node (ref "IC190") (pin "21") (pinfunction "21_21") (pintype "passive"))
      (node (ref "IC191") (pin "21") (pinfunction "21_21") (pintype "passive"))
      (node (ref "IC192") (pin "21") (pinfunction "21_21") (pintype "passive"))
    )
    (net (code "1157") (name "Net-(IC189-Pad22)") (class "Default")
      (node (ref "IC189") (pin "22") (pinfunction "22_22") (pintype "passive"))
      (node (ref "IC190") (pin "22") (pinfunction "22_22") (pintype "passive"))
      (node (ref "IC191") (pin "22") (pinfunction "22_22") (pintype "passive"))
      (node (ref "IC192") (pin "22") (pinfunction "22_22") (pintype "passive"))
    )
    (net (code "1158") (name "Net-(IC189-Pad23)") (class "Default")
      (node (ref "IC189") (pin "23") (pinfunction "23_23") (pintype "passive"))
      (node (ref "IC190") (pin "23") (pinfunction "23_23") (pintype "passive"))
      (node (ref "IC191") (pin "23") (pinfunction "23_23") (pintype "passive"))
      (node (ref "IC192") (pin "23") (pinfunction "23_23") (pintype "passive"))
    )
    (net (code "1159") (name "Net-(IC189-Pad24)") (class "Default")
      (node (ref "IC189") (pin "24") (pinfunction "24_24") (pintype "passive"))
      (node (ref "IC190") (pin "24") (pinfunction "24_24") (pintype "passive"))
      (node (ref "IC191") (pin "24") (pinfunction "24_24") (pintype "passive"))
      (node (ref "IC192") (pin "24") (pinfunction "24_24") (pintype "passive"))
    )
    (net (code "1160") (name "Net-(IC193-Pad1)") (class "Default")
      (node (ref "IC193") (pin "1") (pinfunction "1_1") (pintype "passive"))
      (node (ref "IC194") (pin "1") (pinfunction "1_1") (pintype "passive"))
      (node (ref "IC195") (pin "1") (pinfunction "1_1") (pintype "passive"))
      (node (ref "IC196") (pin "1") (pinfunction "1_1") (pintype "passive"))
    )
    (net (code "1161") (name "Net-(IC193-Pad2)") (class "Default")
      (node (ref "IC193") (pin "2") (pinfunction "2_2") (pintype "passive"))
      (node (ref "IC194") (pin "2") (pinfunction "2_2") (pintype "passive"))
      (node (ref "IC195") (pin "2") (pinfunction "2_2") (pintype "passive"))
      (node (ref "IC196") (pin "2") (pinfunction "2_2") (pintype "passive"))
    )
    (net (code "1162") (name "Net-(IC193-Pad3)") (class "Default")
      (node (ref "IC193") (pin "3") (pinfunction "3_3") (pintype "passive"))
      (node (ref "IC194") (pin "3") (pinfunction "3_3") (pintype "passive"))
      (node (ref "IC195") (pin "3") (pinfunction "3_3") (pintype "passive"))
      (node (ref "IC196") (pin "3") (pinfunction "3_3") (pintype "passive"))
    )
    (net (code "1163") (name "Net-(IC193-Pad4)") (class "Default")
      (node (ref "IC193") (pin "4") (pinfunction "4_4") (pintype "passive"))
      (node (ref "IC194") (pin "4") (pinfunction "4_4") (pintype "passive"))
      (node (ref "IC195") (pin "4") (pinfunction "4_4") (pintype "passive"))
      (node (ref "IC196") (pin "4") (pinfunction "4_4") (pintype "passive"))
    )
    (net (code "1164") (name "Net-(IC193-Pad5)") (class "Default")
      (node (ref "IC193") (pin "5") (pinfunction "5_5") (pintype "passive"))
      (node (ref "IC194") (pin "5") (pinfunction "5_5") (pintype "passive"))
      (node (ref "IC195") (pin "5") (pinfunction "5_5") (pintype "passive"))
      (node (ref "IC196") (pin "5") (pinfunction "5_5") (pintype "passive"))
    )
    (net (code "1165") (name "Net-(IC193-Pad6)") (class "Default")
      (node (ref "IC193") (pin "6") (pinfunction "6_6") (pintype "passive"))
      (node (ref "IC194") (pin "6") (pinfunction "6_6") (pintype "passive"))
      (node (ref "IC195") (pin "6") (pinfunction "6_6") (pintype "passive"))
      (node (ref "IC196") (pin "6") (pinfunction "6_6") (pintype "passive"))
    )
    (net (code "1166") (name "Net-(IC193-Pad7)") (class "Default")
      (node (ref "IC193") (pin "7") (pinfunction "7_7") (pintype "passive"))
      (node (ref "IC194") (pin "7") (pinfunction "7_7") (pintype "passive"))
      (node (ref "IC195") (pin "7") (pinfunction "7_7") (pintype "passive"))
      (node (ref "IC196") (pin "7") (pinfunction "7_7") (pintype "passive"))
    )
    (net (code "1167") (name "Net-(IC193-Pad8)") (class "Default")
      (node (ref "IC193") (pin "8") (pinfunction "8_8") (pintype "passive"))
      (node (ref "IC194") (pin "8") (pinfunction "8_8") (pintype "passive"))
      (node (ref "IC195") (pin "8") (pinfunction "8_8") (pintype "passive"))
      (node (ref "IC196") (pin "8") (pinfunction "8_8") (pintype "passive"))
    )
    (net (code "1168") (name "Net-(IC193-Pad9)") (class "Default")
      (node (ref "IC193") (pin "9") (pinfunction "9_9") (pintype "passive"))
      (node (ref "IC194") (pin "9") (pinfunction "9_9") (pintype "passive"))
      (node (ref "IC195") (pin "9") (pinfunction "9_9") (pintype "passive"))
      (node (ref "IC196") (pin "9") (pinfunction "9_9") (pintype "passive"))
    )
    (net (code "1169") (name "Net-(IC193-Pad10)") (class "Default")
      (node (ref "IC193") (pin "10") (pinfunction "10_10") (pintype "passive"))
      (node (ref "IC194") (pin "10") (pinfunction "10_10") (pintype "passive"))
      (node (ref "IC195") (pin "10") (pinfunction "10_10") (pintype "passive"))
      (node (ref "IC196") (pin "10") (pinfunction "10_10") (pintype "passive"))
    )
    (net (code "1170") (name "Net-(IC193-Pad11)") (class "Default")
      (node (ref "IC193") (pin "11") (pinfunction "11_11") (pintype "passive"))
      (node (ref "IC194") (pin "11") (pinfunction "11_11") (pintype "passive"))
      (node (ref "IC195") (pin "11") (pinfunction "11_11") (pintype "passive"))
      (node (ref "IC196") (pin "11") (pinfunction "11_11") (pintype "passive"))
    )
    (net (code "1171") (name "Net-(IC193-Pad12)") (class "Default")
      (node (ref "IC193") (pin "12") (pinfunction "12_12") (pintype "passive"))
      (node (ref "IC194") (pin "12") (pinfunction "12_12") (pintype "passive"))
      (node (ref "IC195") (pin "12") (pinfunction "12_12") (pintype "passive"))
      (node (ref "IC196") (pin "12") (pinfunction "12_12") (pintype "passive"))
    )
    (net (code "1172") (name "Net-(IC193-Pad13)") (class "Default")
      (node (ref "IC193") (pin "13") (pinfunction "13_13") (pintype "passive"))
      (node (ref "IC194") (pin "13") (pinfunction "13_13") (pintype "passive"))
      (node (ref "IC195") (pin "13") (pinfunction "13_13") (pintype "passive"))
      (node (ref "IC196") (pin "13") (pinfunction "13_13") (pintype "passive"))
    )
    (net (code "1173") (name "Net-(IC193-Pad14)") (class "Default")
      (node (ref "IC193") (pin "14") (pinfunction "14_14") (pintype "passive"))
      (node (ref "IC194") (pin "14") (pinfunction "14_14") (pintype "passive"))
      (node (ref "IC195") (pin "14") (pinfunction "14_14") (pintype "passive"))
      (node (ref "IC196") (pin "14") (pinfunction "14_14") (pintype "passive"))
    )
    (net (code "1174") (name "Net-(IC193-Pad15)") (class "Default")
      (node (ref "IC193") (pin "15") (pinfunction "15_15") (pintype "passive"))
      (node (ref "IC194") (pin "15") (pinfunction "15_15") (pintype "passive"))
      (node (ref "IC195") (pin "15") (pinfunction "15_15") (pintype "passive"))
      (node (ref "IC196") (pin "15") (pinfunction "15_15") (pintype "passive"))
    )
    (net (code "1175") (name "Net-(IC193-Pad16)") (class "Default")
      (node (ref "IC193") (pin "16") (pinfunction "16_16") (pintype "passive"))
      (node (ref "IC194") (pin "16") (pinfunction "16_16") (pintype "passive"))
      (node (ref "IC195") (pin "16") (pinfunction "16_16") (pintype "passive"))
      (node (ref "IC196") (pin "16") (pinfunction "16_16") (pintype "passive"))
    )
    (net (code "1176") (name "Net-(IC193-Pad17)") (class "Default")
      (node (ref "IC193") (pin "17") (pinfunction "17_17") (pintype "passive"))
      (node (ref "IC194") (pin "17") (pinfunction "17_17") (pintype "passive"))
      (node (ref "IC195") (pin "17") (pinfunction "17_17") (pintype "passive"))
      (node (ref "IC196") (pin "17") (pinfunction "17_17") (pintype "passive"))
    )
    (net (code "1177") (name "Net-(IC193-Pad18)") (class "Default")
      (node (ref "IC193") (pin "18") (pinfunction "18_18") (pintype "passive"))
      (node (ref "IC194") (pin "18") (pinfunction "18_18") (pintype "passive"))
      (node (ref "IC195") (pin "18") (pinfunction "18_18") (pintype "passive"))
      (node (ref "IC196") (pin "18") (pinfunction "18_18") (pintype "passive"))
    )
    (net (code "1178") (name "Net-(IC193-Pad19)") (class "Default")
      (node (ref "IC193") (pin "19") (pinfunction "19_19") (pintype "passive"))
      (node (ref "IC194") (pin "19") (pinfunction "19_19") (pintype "passive"))
      (node (ref "IC195") (pin "19") (pinfunction "19_19") (pintype "passive"))
      (node (ref "IC196") (pin "19") (pinfunction "19_19") (pintype "passive"))
    )
    (net (code "1179") (name "Net-(IC193-Pad20)") (class "Default")
      (node (ref "IC193") (pin "20") (pinfunction "20_20") (pintype "passive"))
      (node (ref "IC194") (pin "20") (pinfunction "20_20") (pintype "passive"))
      (node (ref "IC195") (pin "20") (pinfunction "20_20") (pintype "passive"))
      (node (ref "IC196") (pin "20") (pinfunction "20_20") (pintype "passive"))
    )
    (net (code "1180") (name "Net-(IC193-Pad21)") (class "Default")
      (node (ref "IC193") (pin "21") (pinfunction "21_21") (pintype "passive"))
      (node (ref "IC194") (pin "21") (pinfunction "21_21") (pintype "passive"))
      (node (ref "IC195") (pin "21") (pinfunction "21_21") (pintype "passive"))
      (node (ref "IC196") (pin "21") (pinfunction "21_21") (pintype "passive"))
    )
    (net (code "1181") (name "Net-(IC193-Pad22)") (class "Default")
      (node (ref "IC193") (pin "22") (pinfunction "22_22") (pintype "passive"))
      (node (ref "IC194") (pin "22") (pinfunction "22_22") (pintype "passive"))
      (node (ref "IC195") (pin "22") (pinfunction "22_22") (pintype "passive"))
      (node (ref "IC196") (pin "22") (pinfunction "22_22") (pintype "passive"))
    )
    (net (code "1182") (name "Net-(IC193-Pad23)") (class "Default")
      (node (ref "IC193") (pin "23") (pinfunction "23_23") (pintype "passive"))
      (node (ref "IC194") (pin "23") (pinfunction "23_23") (pintype "passive"))
      (node (ref "IC195") (pin "23") (pinfunction "23_23") (pintype "passive"))
      (node (ref "IC196") (pin "23") (pinfunction "23_23") (pintype "passive"))
    )
    (net (code "1183") (name "Net-(IC193-Pad24)") (class "Default")
      (node (ref "IC193") (pin "24") (pinfunction "24_24") (pintype "passive"))
      (node (ref "IC194") (pin "24") (pinfunction "24_24") (pintype "passive"))
      (node (ref "IC195") (pin "24") (pinfunction "24_24") (pintype "passive"))
      (node (ref "IC196") (pin "24") (pinfunction "24_24") (pintype "passive"))
    )
    (net (code "1184") (name "Net-(IC197-Pad1)") (class "Default")
      (node (ref "IC197") (pin "1") (pinfunction "1_1") (pintype "passive"))
      (node (ref "IC198") (pin "1") (pinfunction "1_1") (pintype "passive"))
      (node (ref "IC199") (pin "1") (pinfunction "1_1") (pintype "passive"))
      (node (ref "IC200") (pin "1") (pinfunction "1_1") (pintype "passive"))
    )
    (net (code "1185") (name "Net-(IC197-Pad2)") (class "Default")
      (node (ref "IC197") (pin "2") (pinfunction "2_2") (pintype "passive"))
      (node (ref "IC198") (pin "2") (pinfunction "2_2") (pintype "passive"))
      (node (ref "IC199") (pin "2") (pinfunction "2_2") (pintype "passive"))
      (node (ref "IC200") (pin "2") (pinfunction "2_2") (pintype "passive"))
    )
    (net (code "1186") (name "Net-(IC197-Pad3)") (class "Default")
      (node (ref "IC197") (pin "3") (pinfunction "3_3") (pintype "passive"))
      (node (ref "IC198") (pin "3") (pinfunction "3_3") (pintype "passive"))
      (node (ref "IC199") (pin "3") (pinfunction "3_3") (pintype "passive"))
      (node (ref "IC200") (pin "3") (pinfunction "3_3") (pintype "passive"))
    )
    (net (code "1187") (name "Net-(IC197-Pad4)") (class "Default")
      (node (ref "IC197") (pin "4") (pinfunction "4_4") (pintype "passive"))
      (node (ref "IC198") (pin "4") (pinfunction "4_4") (pintype "passive"))
      (node (ref "IC199") (pin "4") (pinfunction "4_4") (pintype "passive"))
      (node (ref "IC200") (pin "4") (pinfunction "4_4") (pintype "passive"))
    )
    (net (code "1188") (name "Net-(IC197-Pad5)") (class "Default")
      (node (ref "IC197") (pin "5") (pinfunction "5_5") (pintype "passive"))
      (node (ref "IC198") (pin "5") (pinfunction "5_5") (pintype "passive"))
      (node (ref "IC199") (pin "5") (pinfunction "5_5") (pintype "passive"))
      (node (ref "IC200") (pin "5") (pinfunction "5_5") (pintype "passive"))
    )
    (net (code "1189") (name "Net-(IC197-Pad6)") (class "Default")
      (node (ref "IC197") (pin "6") (pinfunction "6_6") (pintype "passive"))
      (node (ref "IC198") (pin "6") (pinfunction "6_6") (pintype "passive"))
      (node (ref "IC199") (pin "6") (pinfunction "6_6") (pintype "passive"))
      (node (ref "IC200") (pin "6") (pinfunction "6_6") (pintype "passive"))
    )
    (net (code "1190") (name "Net-(IC197-Pad7)") (class "Default")
      (node (ref "IC197") (pin "7") (pinfunction "7_7") (pintype "passive"))
      (node (ref "IC198") (pin "7") (pinfunction "7_7") (pintype "passive"))
      (node (ref "IC199") (pin "7") (pinfunction "7_7") (pintype "passive"))
      (node (ref "IC200") (pin "7") (pinfunction "7_7") (pintype "passive"))
    )
    (net (code "1191") (name "Net-(IC197-Pad8)") (class "Default")
      (node (ref "IC197") (pin "8") (pinfunction "8_8") (pintype "passive"))
      (node (ref "IC198") (pin "8") (pinfunction "8_8") (pintype "passive"))
      (node (ref "IC199") (pin "8") (pinfunction "8_8") (pintype "passive"))
      (node (ref "IC200") (pin "8") (pinfunction "8_8") (pintype "passive"))
    )
    (net (code "1192") (name "Net-(IC197-Pad9)") (class "Default")
      (node (ref "IC197") (pin "9") (pinfunction "9_9") (pintype "passive"))
      (node (ref "IC198") (pin "9") (pinfunction "9_9") (pintype "passive"))
      (node (ref "IC199") (pin "9") (pinfunction "9_9") (pintype "passive"))
      (node (ref "IC200") (pin "9") (pinfunction "9_9") (pintype "passive"))
    )
    (net (code "1193") (name "Net-(IC197-Pad10)") (class "Default")
      (node (ref "IC197") (pin "10") (pinfunction "10_10") (pintype "passive"))
      (node (ref "IC198") (pin "10") (pinfunction "10_10") (pintype "passive"))
      (node (ref "IC199") (pin "10") (pinfunction "10_10") (pintype "passive"))
      (node (ref "IC200") (pin "10") (pinfunction "10_10") (pintype "passive"))
    )
    (net (code "1194") (name "Net-(IC197-Pad11)") (class "Default")
      (node (ref "IC197") (pin "11") (pinfunction "11_11") (pintype "passive"))
      (node (ref "IC198") (pin "11") (pinfunction "11_11") (pintype "passive"))
      (node (ref "IC199") (pin "11") (pinfunction "11_11") (pintype "passive"))
      (node (ref "IC200") (pin "11") (pinfunction "11_11") (pintype "passive"))
    )
    (net (code "1195") (name "Net-(IC197-Pad12)") (class "Default")
      (node (ref "IC197") (pin "12") (pinfunction "12_12") (pintype "passive"))
      (node (ref "IC198") (pin "12") (pinfunction "12_12") (pintype "passive"))
      (node (ref "IC199") (pin "12") (pinfunction "12_12") (pintype "passive"))
      (node (ref "IC200") (pin "12") (pinfunction "12_12") (pintype "passive"))
    )
    (net (code "1196") (name "Net-(IC197-Pad13)") (class "Default")
      (node (ref "IC197") (pin "13") (pinfunction "13_13") (pintype "passive"))
      (node (ref "IC198") (pin "13") (pinfunction "13_13") (pintype "passive"))
      (node (ref "IC199") (pin "13") (pinfunction "13_13") (pintype "passive"))
      (node (ref "IC200") (pin "13") (pinfunction "13_13") (pintype "passive"))
    )
    (net (code "1197") (name "Net-(IC197-Pad14)") (class "Default")
      (node (ref "IC197") (pin "14") (pinfunction "14_14") (pintype "passive"))
      (node (ref "IC198") (pin "14") (pinfunction "14_14") (pintype "passive"))
      (node (ref "IC199") (pin "14") (pinfunction "14_14") (pintype "passive"))
      (node (ref "IC200") (pin "14") (pinfunction "14_14") (pintype "passive"))
    )
    (net (code "1198") (name "Net-(IC197-Pad15)") (class "Default")
      (node (ref "IC197") (pin "15") (pinfunction "15_15") (pintype "passive"))
      (node (ref "IC198") (pin "15") (pinfunction "15_15") (pintype "passive"))
      (node (ref "IC199") (pin "15") (pinfunction "15_15") (pintype "passive"))
      (node (ref "IC200") (pin "15") (pinfunction "15_15") (pintype "passive"))
    )
    (net (code "1199") (name "Net-(IC197-Pad16)") (class "Default")
      (node (ref "IC197") (pin "16") (pinfunction "16_16") (pintype "passive"))
      (node (ref "IC198") (pin "16") (pinfunction "16_16") (pintype "passive"))
      (node (ref "IC199") (pin "16") (pinfunction "16_16") (pintype "passive"))
      (node (ref "IC200") (pin "16") (pinfunction "16_16") (pintype "passive"))
    )
    (net (code "1200") (name "Net-(IC197-Pad17)") (class "Default")
      (node (ref "IC197") (pin "17") (pinfunction "17_17") (pintype "passive"))
      (node (ref "IC198") (pin "17") (pinfunction "17_17") (pintype "passive"))
      (node (ref "IC199") (pin "17") (pinfunction "17_17") (pintype "passive"))
      (node (ref "IC200") (pin "17") (pinfunction "17_17") (pintype "passive"))
    )
    (net (code "1201") (name "Net-(IC197-Pad18)") (class "Default")
      (node (ref "IC197") (pin "18") (pinfunction "18_18") (pintype "passive"))
      (node (ref "IC198") (pin "18") (pinfunction "18_18") (pintype "passive"))
      (node (ref "IC199") (pin "18") (pinfunction "18_18") (pintype "passive"))
      (node (ref "IC200") (pin "18") (pinfunction "18_18") (pintype "passive"))
    )
    (net (code "1202") (name "Net-(IC197-Pad19)") (class "Default")
      (node (ref "IC197") (pin "19") (pinfunction "19_19") (pintype "passive"))
      (node (ref "IC198") (pin "19") (pinfunction "19_19") (pintype "passive"))
      (node (ref "IC199") (pin "19") (pinfunction "19_19") (pintype "passive"))
      (node (ref "IC200") (pin "19") (pinfunction "19_19") (pintype "passive"))
    )
    (net (code "1203") (name "Net-(IC197-Pad20)") (class "Default")
      (node (ref "IC197") (pin "20") (pinfunction "20_20") (pintype "passive"))
      (node (ref "IC198") (pin "20") (pinfunction "20_20") (pintype "passive"))
      (node (ref "IC199") (pin "20") (pinfunction "20_20") (pintype "passive"))
      (node (ref "IC200") (pin "20") (pinfunction "20_20") (pintype "passive"))
    )
    (net (code "1204") (name "Net-(IC197-Pad21)") (class "Default")
      (node (ref "IC197") (pin "21") (pinfunction "21_21") (pintype "passive"))
      (node (ref "IC198") (pin "21") (pinfunction "21_21") (pintype "passive"))
      (node (ref "IC199") (pin "21") (pinfunction "21_21") (pintype "passive"))
      (node (ref "IC200") (pin "21") (pinfunction "21_21") (pintype "passive"))
    )
    (net (code "1205") (name "Net-(IC197-Pad22)") (class "Default")
      (node (ref "IC197") (pin "22") (pinfunction "22_22") (pintype "passive"))
      (node (ref "IC198") (pin "22") (pinfunction "22_22") (pintype "passive"))
      (node (ref "IC199") (pin "22") (pinfunction "22_22") (pintype "passive"))
      (node (ref "IC200") (pin "22") (pinfunction "22_22") (pintype "passive"))
    )
    (net (code "1206") (name "Net-(IC197-Pad23)") (class "Default")
      (node (ref "IC197") (pin "23") (pinfunction "23_23") (pintype "passive"))
      (node (ref "IC198") (pin "23") (pinfunction "23_23") (pintype "passive"))
      (node (ref "IC199") (pin "23") (pinfunction "23_23") (pintype "passive"))
      (node (ref "IC200") (pin "23") (pinfunction "23_23") (pintype "passive"))
    )
    (net (code "1207") (name "Net-(IC197-Pad24)") (class "Default")
      (node (ref "IC197") (pin "24") (pinfunction "24_24") (pintype "passive"))
      (node (ref "IC198") (pin "24") (pinfunction "24_24") (pintype "passive"))
      (node (ref "IC199") (pin "24") (pinfunction "24_24") (pintype "passive"))
      (node (ref "IC200") (pin "24") (pinfunction "24_24") (pintype "passive"))
    )
    (net (code "1208") (name "Net-(U$2A-1)") (class "Default")
      (node (ref "D9") (pin "1") (pinfunction "1_1") (pintype "passive"))
      (node (ref "U$2") (pin "AA1") (pinfunction "1_AA1") (pintype "bidirectional"))
    )
    (net (code "1209") (name "Net-(U$2AK-1)") (class "Default")
      (node (ref "D7") (pin "1") (pinfunction "1_1") (pintype "passive"))
      (node (ref "U$2") (pin "BA1") (pinfunction "1_BA1") (pintype "bidirectional"))
    )
    (net (code "1210") (name "Net-(U$2AM-1)") (class "Default")
      (node (ref "D7") (pin "2") (pinfunction "2_2") (pintype "passive"))
      (node (ref "U$2") (pin "BB1") (pinfunction "1_BB1") (pintype "bidirectional"))
    )
    (net (code "1211") (name "Net-(U$2BN-1)") (class "Default")
      (node (ref "D8") (pin "15") (pinfunction "15_15") (pintype "passive"))
      (node (ref "U$2") (pin "BS2") (pinfunction "1_BS2") (pintype "bidirectional"))
    )
    (net (code "1212") (name "Net-(U$2BU-1)") (class "Default")
      (node (ref "D11") (pin "1") (pinfunction "1_1") (pintype "passive"))
      (node (ref "U$2") (pin "CA1") (pinfunction "1_CA1") (pintype "bidirectional"))
    )
    (net (code "1213") (name "Net-(U$2BW-1)") (class "Default")
      (node (ref "D11") (pin "2") (pinfunction "2_2") (pintype "passive"))
      (node (ref "U$2") (pin "CB1") (pinfunction "1_CB1") (pintype "bidirectional"))
    )
    (net (code "1214") (name "Net-(U$2C-1)") (class "Default")
      (node (ref "D9") (pin "2") (pinfunction "2_2") (pintype "passive"))
      (node (ref "U$2") (pin "AB1") (pinfunction "1_AB1") (pintype "bidirectional"))
    )
    (net (code "1215") (name "Net-(U$2DE-1)") (class "Default")
      (node (ref "D13") (pin "1") (pinfunction "1_1") (pintype "passive"))
      (node (ref "U$2") (pin "DA1") (pinfunction "1_DA1") (pintype "bidirectional"))
    )
    (net (code "1216") (name "Net-(U$2DG-1)") (class "Default")
      (node (ref "D13") (pin "2") (pinfunction "2_2") (pintype "passive"))
      (node (ref "U$2") (pin "DB1") (pinfunction "1_DB1") (pintype "bidirectional"))
    )
    (net (code "1217") (name "POWER_OK") (class "Default")
      (node (ref "D8") (pin "18") (pinfunction "18_18") (pintype "passive"))
      (node (ref "U$2") (pin "BV2") (pinfunction "1_BV2") (pintype "bidirectional"))
    )
    (net (code "1218") (name "PULSE_LA") (class "Default")
      (node (ref "D14") (pin "14") (pinfunction "14_14") (pintype "passive"))
      (node (ref "U$2") (pin "DR2") (pinfunction "1_DR2") (pintype "bidirectional"))
    )
    (net (code "1219") (name "RETURN") (class "Default")
      (node (ref "D10") (pin "14") (pinfunction "14_14") (pintype "passive"))
      (node (ref "U$2") (pin "AR2") (pinfunction "1_AR2") (pintype "bidirectional"))
    )
    (net (code "1220") (name "SOURCE") (class "Default")
      (node (ref "D10") (pin "10") (pinfunction "10_10") (pintype "passive"))
      (node (ref "U$2") (pin "AL2") (pinfunction "1_AL2") (pintype "bidirectional"))
    )
    (net (code "1221") (name "STROBE") (class "Default")
      (node (ref "D10") (pin "11") (pinfunction "11_11") (pintype "passive"))
      (node (ref "U$2") (pin "AM2") (pinfunction "1_AM2") (pintype "bidirectional"))
    )
    (net (code "1222") (name "SWITCH") (class "Default")
      (node (ref "D14") (pin "18") (pinfunction "18_18") (pintype "passive"))
      (node (ref "U$2") (pin "DV2") (pinfunction "1_DV2") (pintype "bidirectional"))
    )
    (net (code "1223") (name "TP1") (class "Default")
      (node (ref "D12") (pin "4") (pinfunction "4_4") (pintype "passive"))
      (node (ref "U$2") (pin "CD2") (pinfunction "1_CD2") (pintype "bidirectional"))
    )
    (net (code "1224") (name "TP2") (class "Default")
      (node (ref "D12") (pin "5") (pinfunction "5_5") (pintype "passive"))
      (node (ref "U$2") (pin "CE2") (pinfunction "1_CE2") (pintype "bidirectional"))
    )
    (net (code "1225") (name "TP3") (class "Default")
      (node (ref "D12") (pin "7") (pinfunction "7_7") (pintype "passive"))
      (node (ref "U$2") (pin "CH2") (pinfunction "1_CH2") (pintype "bidirectional"))
    )
    (net (code "1226") (name "TP4") (class "Default")
      (node (ref "D12") (pin "8") (pinfunction "8_8") (pintype "passive"))
      (node (ref "U$2") (pin "CJ2") (pinfunction "1_CJ2") (pintype "bidirectional"))
    )
    (net (code "1227") (name "VCC") (class "Default")
      (node (ref "C1") (pin "+") (pinfunction "+_+") (pintype "passive"))
      (node (ref "C2") (pin "+") (pinfunction "+_+") (pintype "passive"))
      (node (ref "C3") (pin "+") (pinfunction "+_+") (pintype "passive"))
      (node (ref "C4") (pin "+") (pinfunction "+_+") (pintype "passive"))
      (node (ref "D10") (pin "1") (pinfunction "1_1") (pintype "passive"))
      (node (ref "D12") (pin "1") (pinfunction "1_1") (pintype "passive"))
      (node (ref "D8") (pin "1") (pinfunction "1_1") (pintype "passive"))
      (node (ref "SV1") (pin "1") (pinfunction "1_1") (pintype "passive"))
      (node (ref "SV1") (pin "10") (pinfunction "10_10") (pintype "passive"))
      (node (ref "SV1") (pin "11") (pinfunction "11_11") (pintype "passive"))
      (node (ref "SV1") (pin "12") (pinfunction "12_12") (pintype "passive"))
      (node (ref "SV1") (pin "2") (pinfunction "2_2") (pintype "passive"))
      (node (ref "SV1") (pin "3") (pinfunction "3_3") (pintype "passive"))
      (node (ref "SV1") (pin "4") (pinfunction "4_4") (pintype "passive"))
      (node (ref "SV1") (pin "5") (pinfunction "5_5") (pintype "passive"))
      (node (ref "SV1") (pin "6") (pinfunction "6_6") (pintype "passive"))
      (node (ref "SV1") (pin "7") (pinfunction "7_7") (pintype "passive"))
      (node (ref "SV1") (pin "8") (pinfunction "8_8") (pintype "passive"))
      (node (ref "SV1") (pin "9") (pinfunction "9_9") (pintype "passive"))
      (node (ref "SV11") (pin "1") (pinfunction "1_1") (pintype "passive"))
      (node (ref "SV11") (pin "10") (pinfunction "10_10") (pintype "passive"))
      (node (ref "SV11") (pin "11") (pinfunction "11_11") (pintype "passive"))
      (node (ref "SV11") (pin "12") (pinfunction "12_12") (pintype "passive"))
      (node (ref "SV11") (pin "2") (pinfunction "2_2") (pintype "passive"))
      (node (ref "SV11") (pin "3") (pinfunction "3_3") (pintype "passive"))
      (node (ref "SV11") (pin "4") (pinfunction "4_4") (pintype "passive"))
      (node (ref "SV11") (pin "5") (pinfunction "5_5") (pintype "passive"))
      (node (ref "SV11") (pin "6") (pinfunction "6_6") (pintype "passive"))
      (node (ref "SV11") (pin "7") (pinfunction "7_7") (pintype "passive"))
      (node (ref "SV11") (pin "8") (pinfunction "8_8") (pintype "passive"))
      (node (ref "SV11") (pin "9") (pinfunction "9_9") (pintype "passive"))
      (node (ref "SV13") (pin "1") (pinfunction "1_1") (pintype "passive"))
      (node (ref "SV13") (pin "10") (pinfunction "10_10") (pintype "passive"))
      (node (ref "SV13") (pin "11") (pinfunction "11_11") (pintype "passive"))
      (node (ref "SV13") (pin "12") (pinfunction "12_12") (pintype "passive"))
      (node (ref "SV13") (pin "2") (pinfunction "2_2") (pintype "passive"))
      (node (ref "SV13") (pin "3") (pinfunction "3_3") (pintype "passive"))
      (node (ref "SV13") (pin "4") (pinfunction "4_4") (pintype "passive"))
      (node (ref "SV13") (pin "5") (pinfunction "5_5") (pintype "passive"))
      (node (ref "SV13") (pin "6") (pinfunction "6_6") (pintype "passive"))
      (node (ref "SV13") (pin "7") (pinfunction "7_7") (pintype "passive"))
      (node (ref "SV13") (pin "8") (pinfunction "8_8") (pintype "passive"))
      (node (ref "SV13") (pin "9") (pinfunction "9_9") (pintype "passive"))
      (node (ref "SV15") (pin "1") (pinfunction "1_1") (pintype "passive"))
      (node (ref "SV15") (pin "10") (pinfunction "10_10") (pintype "passive"))
      (node (ref "SV15") (pin "11") (pinfunction "11_11") (pintype "passive"))
      (node (ref "SV15") (pin "12") (pinfunction "12_12") (pintype "passive"))
      (node (ref "SV15") (pin "2") (pinfunction "2_2") (pintype "passive"))
      (node (ref "SV15") (pin "3") (pinfunction "3_3") (pintype "passive"))
      (node (ref "SV15") (pin "4") (pinfunction "4_4") (pintype "passive"))
      (node (ref "SV15") (pin "5") (pinfunction "5_5") (pintype "passive"))
      (node (ref "SV15") (pin "6") (pinfunction "6_6") (pintype "passive"))
      (node (ref "SV15") (pin "7") (pinfunction "7_7") (pintype "passive"))
      (node (ref "SV15") (pin "8") (pinfunction "8_8") (pintype "passive"))
      (node (ref "SV15") (pin "9") (pinfunction "9_9") (pintype "passive"))
      (node (ref "SV17") (pin "1") (pinfunction "1_1") (pintype "passive"))
      (node (ref "SV17") (pin "10") (pinfunction "10_10") (pintype "passive"))
      (node (ref "SV17") (pin "11") (pinfunction "11_11") (pintype "passive"))
      (node (ref "SV17") (pin "12") (pinfunction "12_12") (pintype "passive"))
      (node (ref "SV17") (pin "2") (pinfunction "2_2") (pintype "passive"))
      (node (ref "SV17") (pin "3") (pinfunction "3_3") (pintype "passive"))
      (node (ref "SV17") (pin "4") (pinfunction "4_4") (pintype "passive"))
      (node (ref "SV17") (pin "5") (pinfunction "5_5") (pintype "passive"))
      (node (ref "SV17") (pin "6") (pinfunction "6_6") (pintype "passive"))
      (node (ref "SV17") (pin "7") (pinfunction "7_7") (pintype "passive"))
      (node (ref "SV17") (pin "8") (pinfunction "8_8") (pintype "passive"))
      (node (ref "SV17") (pin "9") (pinfunction "9_9") (pintype "passive"))
      (node (ref "SV183") (pin "1") (pinfunction "1_1") (pintype "passive"))
      (node (ref "SV183") (pin "10") (pinfunction "10_10") (pintype "passive"))
      (node (ref "SV183") (pin "11") (pinfunction "11_11") (pintype "passive"))
      (node (ref "SV183") (pin "12") (pinfunction "12_12") (pintype "passive"))
      (node (ref "SV183") (pin "2") (pinfunction "2_2") (pintype "passive"))
      (node (ref "SV183") (pin "3") (pinfunction "3_3") (pintype "passive"))
      (node (ref "SV183") (pin "4") (pinfunction "4_4") (pintype "passive"))
      (node (ref "SV183") (pin "5") (pinfunction "5_5") (pintype "passive"))
      (node (ref "SV183") (pin "6") (pinfunction "6_6") (pintype "passive"))
      (node (ref "SV183") (pin "7") (pinfunction "7_7") (pintype "passive"))
      (node (ref "SV183") (pin "8") (pinfunction "8_8") (pintype "passive"))
      (node (ref "SV183") (pin "9") (pinfunction "9_9") (pintype "passive"))
      (node (ref "SV185") (pin "1") (pinfunction "1_1") (pintype "passive"))
      (node (ref "SV185") (pin "10") (pinfunction "10_10") (pintype "passive"))
      (node (ref "SV185") (pin "11") (pinfunction "11_11") (pintype "passive"))
      (node (ref "SV185") (pin "12") (pinfunction "12_12") (pintype "passive"))
      (node (ref "SV185") (pin "2") (pinfunction "2_2") (pintype "passive"))
      (node (ref "SV185") (pin "3") (pinfunction "3_3") (pintype "passive"))
      (node (ref "SV185") (pin "4") (pinfunction "4_4") (pintype "passive"))
      (node (ref "SV185") (pin "5") (pinfunction "5_5") (pintype "passive"))
      (node (ref "SV185") (pin "6") (pinfunction "6_6") (pintype "passive"))
      (node (ref "SV185") (pin "7") (pinfunction "7_7") (pintype "passive"))
      (node (ref "SV185") (pin "8") (pinfunction "8_8") (pintype "passive"))
      (node (ref "SV185") (pin "9") (pinfunction "9_9") (pintype "passive"))
      (node (ref "SV187") (pin "1") (pinfunction "1_1") (pintype "passive"))
      (node (ref "SV187") (pin "10") (pinfunction "10_10") (pintype "passive"))
      (node (ref "SV187") (pin "11") (pinfunction "11_11") (pintype "passive"))
      (node (ref "SV187") (pin "12") (pinfunction "12_12") (pintype "passive"))
      (node (ref "SV187") (pin "2") (pinfunction "2_2") (pintype "passive"))
      (node (ref "SV187") (pin "3") (pinfunction "3_3") (pintype "passive"))
      (node (ref "SV187") (pin "4") (pinfunction "4_4") (pintype "passive"))
      (node (ref "SV187") (pin "5") (pinfunction "5_5") (pintype "passive"))
      (node (ref "SV187") (pin "6") (pinfunction "6_6") (pintype "passive"))
      (node (ref "SV187") (pin "7") (pinfunction "7_7") (pintype "passive"))
      (node (ref "SV187") (pin "8") (pinfunction "8_8") (pintype "passive"))
      (node (ref "SV187") (pin "9") (pinfunction "9_9") (pintype "passive"))
      (node (ref "SV189") (pin "1") (pinfunction "1_1") (pintype "passive"))
      (node (ref "SV189") (pin "10") (pinfunction "10_10") (pintype "passive"))
      (node (ref "SV189") (pin "11") (pinfunction "11_11") (pintype "passive"))
      (node (ref "SV189") (pin "12") (pinfunction "12_12") (pintype "passive"))
      (node (ref "SV189") (pin "2") (pinfunction "2_2") (pintype "passive"))
      (node (ref "SV189") (pin "3") (pinfunction "3_3") (pintype "passive"))
      (node (ref "SV189") (pin "4") (pinfunction "4_4") (pintype "passive"))
      (node (ref "SV189") (pin "5") (pinfunction "5_5") (pintype "passive"))
      (node (ref "SV189") (pin "6") (pinfunction "6_6") (pintype "passive"))
      (node (ref "SV189") (pin "7") (pinfunction "7_7") (pintype "passive"))
      (node (ref "SV189") (pin "8") (pinfunction "8_8") (pintype "passive"))
      (node (ref "SV189") (pin "9") (pinfunction "9_9") (pintype "passive"))
      (node (ref "SV19") (pin "1") (pinfunction "1_1") (pintype "passive"))
      (node (ref "SV19") (pin "10") (pinfunction "10_10") (pintype "passive"))
      (node (ref "SV19") (pin "11") (pinfunction "11_11") (pintype "passive"))
      (node (ref "SV19") (pin "12") (pinfunction "12_12") (pintype "passive"))
      (node (ref "SV19") (pin "2") (pinfunction "2_2") (pintype "passive"))
      (node (ref "SV19") (pin "3") (pinfunction "3_3") (pintype "passive"))
      (node (ref "SV19") (pin "4") (pinfunction "4_4") (pintype "passive"))
      (node (ref "SV19") (pin "5") (pinfunction "5_5") (pintype "passive"))
      (node (ref "SV19") (pin "6") (pinfunction "6_6") (pintype "passive"))
      (node (ref "SV19") (pin "7") (pinfunction "7_7") (pintype "passive"))
      (node (ref "SV19") (pin "8") (pinfunction "8_8") (pintype "passive"))
      (node (ref "SV19") (pin "9") (pinfunction "9_9") (pintype "passive"))
      (node (ref "SV191") (pin "1") (pinfunction "1_1") (pintype "passive"))
      (node (ref "SV191") (pin "10") (pinfunction "10_10") (pintype "passive"))
      (node (ref "SV191") (pin "11") (pinfunction "11_11") (pintype "passive"))
      (node (ref "SV191") (pin "12") (pinfunction "12_12") (pintype "passive"))
      (node (ref "SV191") (pin "2") (pinfunction "2_2") (pintype "passive"))
      (node (ref "SV191") (pin "3") (pinfunction "3_3") (pintype "passive"))
      (node (ref "SV191") (pin "4") (pinfunction "4_4") (pintype "passive"))
      (node (ref "SV191") (pin "5") (pinfunction "5_5") (pintype "passive"))
      (node (ref "SV191") (pin "6") (pinfunction "6_6") (pintype "passive"))
      (node (ref "SV191") (pin "7") (pinfunction "7_7") (pintype "passive"))
      (node (ref "SV191") (pin "8") (pinfunction "8_8") (pintype "passive"))
      (node (ref "SV191") (pin "9") (pinfunction "9_9") (pintype "passive"))
      (node (ref "SV21") (pin "1") (pinfunction "1_1") (pintype "passive"))
      (node (ref "SV21") (pin "10") (pinfunction "10_10") (pintype "passive"))
      (node (ref "SV21") (pin "11") (pinfunction "11_11") (pintype "passive"))
      (node (ref "SV21") (pin "12") (pinfunction "12_12") (pintype "passive"))
      (node (ref "SV21") (pin "2") (pinfunction "2_2") (pintype "passive"))
      (node (ref "SV21") (pin "3") (pinfunction "3_3") (pintype "passive"))
      (node (ref "SV21") (pin "4") (pinfunction "4_4") (pintype "passive"))
      (node (ref "SV21") (pin "5") (pinfunction "5_5") (pintype "passive"))
      (node (ref "SV21") (pin "6") (pinfunction "6_6") (pintype "passive"))
      (node (ref "SV21") (pin "7") (pinfunction "7_7") (pintype "passive"))
      (node (ref "SV21") (pin "8") (pinfunction "8_8") (pintype "passive"))
      (node (ref "SV21") (pin "9") (pinfunction "9_9") (pintype "passive"))
      (node (ref "SV23") (pin "1") (pinfunction "1_1") (pintype "passive"))
      (node (ref "SV23") (pin "10") (pinfunction "10_10") (pintype "passive"))
      (node (ref "SV23") (pin "11") (pinfunction "11_11") (pintype "passive"))
      (node (ref "SV23") (pin "12") (pinfunction "12_12") (pintype "passive"))
      (node (ref "SV23") (pin "2") (pinfunction "2_2") (pintype "passive"))
      (node (ref "SV23") (pin "3") (pinfunction "3_3") (pintype "passive"))
      (node (ref "SV23") (pin "4") (pinfunction "4_4") (pintype "passive"))
      (node (ref "SV23") (pin "5") (pinfunction "5_5") (pintype "passive"))
      (node (ref "SV23") (pin "6") (pinfunction "6_6") (pintype "passive"))
      (node (ref "SV23") (pin "7") (pinfunction "7_7") (pintype "passive"))
      (node (ref "SV23") (pin "8") (pinfunction "8_8") (pintype "passive"))
      (node (ref "SV23") (pin "9") (pinfunction "9_9") (pintype "passive"))
      (node (ref "SV25") (pin "1") (pinfunction "1_1") (pintype "passive"))
      (node (ref "SV25") (pin "10") (pinfunction "10_10") (pintype "passive"))
      (node (ref "SV25") (pin "11") (pinfunction "11_11") (pintype "passive"))
      (node (ref "SV25") (pin "12") (pinfunction "12_12") (pintype "passive"))
      (node (ref "SV25") (pin "2") (pinfunction "2_2") (pintype "passive"))
      (node (ref "SV25") (pin "3") (pinfunction "3_3") (pintype "passive"))
      (node (ref "SV25") (pin "4") (pinfunction "4_4") (pintype "passive"))
      (node (ref "SV25") (pin "5") (pinfunction "5_5") (pintype "passive"))
      (node (ref "SV25") (pin "6") (pinfunction "6_6") (pintype "passive"))
      (node (ref "SV25") (pin "7") (pinfunction "7_7") (pintype "passive"))
      (node (ref "SV25") (pin "8") (pinfunction "8_8") (pintype "passive"))
      (node (ref "SV25") (pin "9") (pinfunction "9_9") (pintype "passive"))
      (node (ref "SV27") (pin "1") (pinfunction "1_1") (pintype "passive"))
      (node (ref "SV27") (pin "10") (pinfunction "10_10") (pintype "passive"))
      (node (ref "SV27") (pin "11") (pinfunction "11_11") (pintype "passive"))
      (node (ref "SV27") (pin "12") (pinfunction "12_12") (pintype "passive"))
      (node (ref "SV27") (pin "2") (pinfunction "2_2") (pintype "passive"))
      (node (ref "SV27") (pin "3") (pinfunction "3_3") (pintype "passive"))
      (node (ref "SV27") (pin "4") (pinfunction "4_4") (pintype "passive"))
      (node (ref "SV27") (pin "5") (pinfunction "5_5") (pintype "passive"))
      (node (ref "SV27") (pin "6") (pinfunction "6_6") (pintype "passive"))
      (node (ref "SV27") (pin "7") (pinfunction "7_7") (pintype "passive"))
      (node (ref "SV27") (pin "8") (pinfunction "8_8") (pintype "passive"))
      (node (ref "SV27") (pin "9") (pinfunction "9_9") (pintype "passive"))
      (node (ref "SV29") (pin "1") (pinfunction "1_1") (pintype "passive"))
      (node (ref "SV29") (pin "10") (pinfunction "10_10") (pintype "passive"))
      (node (ref "SV29") (pin "11") (pinfunction "11_11") (pintype "passive"))
      (node (ref "SV29") (pin "12") (pinfunction "12_12") (pintype "passive"))
      (node (ref "SV29") (pin "2") (pinfunction "2_2") (pintype "passive"))
      (node (ref "SV29") (pin "3") (pinfunction "3_3") (pintype "passive"))
      (node (ref "SV29") (pin "4") (pinfunction "4_4") (pintype "passive"))
      (node (ref "SV29") (pin "5") (pinfunction "5_5") (pintype "passive"))
      (node (ref "SV29") (pin "6") (pinfunction "6_6") (pintype "passive"))
      (node (ref "SV29") (pin "7") (pinfunction "7_7") (pintype "passive"))
      (node (ref "SV29") (pin "8") (pinfunction "8_8") (pintype "passive"))
      (node (ref "SV29") (pin "9") (pinfunction "9_9") (pintype "passive"))
      (node (ref "SV3") (pin "1") (pinfunction "1_1") (pintype "passive"))
      (node (ref "SV3") (pin "10") (pinfunction "10_10") (pintype "passive"))
      (node (ref "SV3") (pin "11") (pinfunction "11_11") (pintype "passive"))
      (node (ref "SV3") (pin "12") (pinfunction "12_12") (pintype "passive"))
      (node (ref "SV3") (pin "2") (pinfunction "2_2") (pintype "passive"))
      (node (ref "SV3") (pin "3") (pinfunction "3_3") (pintype "passive"))
      (node (ref "SV3") (pin "4") (pinfunction "4_4") (pintype "passive"))
      (node (ref "SV3") (pin "5") (pinfunction "5_5") (pintype "passive"))
      (node (ref "SV3") (pin "6") (pinfunction "6_6") (pintype "passive"))
      (node (ref "SV3") (pin "7") (pinfunction "7_7") (pintype "passive"))
      (node (ref "SV3") (pin "8") (pinfunction "8_8") (pintype "passive"))
      (node (ref "SV3") (pin "9") (pinfunction "9_9") (pintype "passive"))
      (node (ref "SV31") (pin "1") (pinfunction "1_1") (pintype "passive"))
      (node (ref "SV31") (pin "10") (pinfunction "10_10") (pintype "passive"))
      (node (ref "SV31") (pin "11") (pinfunction "11_11") (pintype "passive"))
      (node (ref "SV31") (pin "12") (pinfunction "12_12") (pintype "passive"))
      (node (ref "SV31") (pin "2") (pinfunction "2_2") (pintype "passive"))
      (node (ref "SV31") (pin "3") (pinfunction "3_3") (pintype "passive"))
      (node (ref "SV31") (pin "4") (pinfunction "4_4") (pintype "passive"))
      (node (ref "SV31") (pin "5") (pinfunction "5_5") (pintype "passive"))
      (node (ref "SV31") (pin "6") (pinfunction "6_6") (pintype "passive"))
      (node (ref "SV31") (pin "7") (pinfunction "7_7") (pintype "passive"))
      (node (ref "SV31") (pin "8") (pinfunction "8_8") (pintype "passive"))
      (node (ref "SV31") (pin "9") (pinfunction "9_9") (pintype "passive"))
      (node (ref "SV33") (pin "1") (pinfunction "1_1") (pintype "passive"))
      (node (ref "SV33") (pin "10") (pinfunction "10_10") (pintype "passive"))
      (node (ref "SV33") (pin "11") (pinfunction "11_11") (pintype "passive"))
      (node (ref "SV33") (pin "12") (pinfunction "12_12") (pintype "passive"))
      (node (ref "SV33") (pin "2") (pinfunction "2_2") (pintype "passive"))
      (node (ref "SV33") (pin "3") (pinfunction "3_3") (pintype "passive"))
      (node (ref "SV33") (pin "4") (pinfunction "4_4") (pintype "passive"))
      (node (ref "SV33") (pin "5") (pinfunction "5_5") (pintype "passive"))
      (node (ref "SV33") (pin "6") (pinfunction "6_6") (pintype "passive"))
      (node (ref "SV33") (pin "7") (pinfunction "7_7") (pintype "passive"))
      (node (ref "SV33") (pin "8") (pinfunction "8_8") (pintype "passive"))
      (node (ref "SV33") (pin "9") (pinfunction "9_9") (pintype "passive"))
      (node (ref "SV35") (pin "1") (pinfunction "1_1") (pintype "passive"))
      (node (ref "SV35") (pin "10") (pinfunction "10_10") (pintype "passive"))
      (node (ref "SV35") (pin "11") (pinfunction "11_11") (pintype "passive"))
      (node (ref "SV35") (pin "12") (pinfunction "12_12") (pintype "passive"))
      (node (ref "SV35") (pin "2") (pinfunction "2_2") (pintype "passive"))
      (node (ref "SV35") (pin "3") (pinfunction "3_3") (pintype "passive"))
      (node (ref "SV35") (pin "4") (pinfunction "4_4") (pintype "passive"))
      (node (ref "SV35") (pin "5") (pinfunction "5_5") (pintype "passive"))
      (node (ref "SV35") (pin "6") (pinfunction "6_6") (pintype "passive"))
      (node (ref "SV35") (pin "7") (pinfunction "7_7") (pintype "passive"))
      (node (ref "SV35") (pin "8") (pinfunction "8_8") (pintype "passive"))
      (node (ref "SV35") (pin "9") (pinfunction "9_9") (pintype "passive"))
      (node (ref "SV37") (pin "1") (pinfunction "1_1") (pintype "passive"))
      (node (ref "SV37") (pin "10") (pinfunction "10_10") (pintype "passive"))
      (node (ref "SV37") (pin "11") (pinfunction "11_11") (pintype "passive"))
      (node (ref "SV37") (pin "12") (pinfunction "12_12") (pintype "passive"))
      (node (ref "SV37") (pin "2") (pinfunction "2_2") (pintype "passive"))
      (node (ref "SV37") (pin "3") (pinfunction "3_3") (pintype "passive"))
      (node (ref "SV37") (pin "4") (pinfunction "4_4") (pintype "passive"))
      (node (ref "SV37") (pin "5") (pinfunction "5_5") (pintype "passive"))
      (node (ref "SV37") (pin "6") (pinfunction "6_6") (pintype "passive"))
      (node (ref "SV37") (pin "7") (pinfunction "7_7") (pintype "passive"))
      (node (ref "SV37") (pin "8") (pinfunction "8_8") (pintype "passive"))
      (node (ref "SV37") (pin "9") (pinfunction "9_9") (pintype "passive"))
      (node (ref "SV39") (pin "1") (pinfunction "1_1") (pintype "passive"))
      (node (ref "SV39") (pin "10") (pinfunction "10_10") (pintype "passive"))
      (node (ref "SV39") (pin "11") (pinfunction "11_11") (pintype "passive"))
      (node (ref "SV39") (pin "12") (pinfunction "12_12") (pintype "passive"))
      (node (ref "SV39") (pin "2") (pinfunction "2_2") (pintype "passive"))
      (node (ref "SV39") (pin "3") (pinfunction "3_3") (pintype "passive"))
      (node (ref "SV39") (pin "4") (pinfunction "4_4") (pintype "passive"))
      (node (ref "SV39") (pin "5") (pinfunction "5_5") (pintype "passive"))
      (node (ref "SV39") (pin "6") (pinfunction "6_6") (pintype "passive"))
      (node (ref "SV39") (pin "7") (pinfunction "7_7") (pintype "passive"))
      (node (ref "SV39") (pin "8") (pinfunction "8_8") (pintype "passive"))
      (node (ref "SV39") (pin "9") (pinfunction "9_9") (pintype "passive"))
      (node (ref "SV43") (pin "1") (pinfunction "1_1") (pintype "passive"))
      (node (ref "SV43") (pin "10") (pinfunction "10_10") (pintype "passive"))
      (node (ref "SV43") (pin "11") (pinfunction "11_11") (pintype "passive"))
      (node (ref "SV43") (pin "12") (pinfunction "12_12") (pintype "passive"))
      (node (ref "SV43") (pin "2") (pinfunction "2_2") (pintype "passive"))
      (node (ref "SV43") (pin "3") (pinfunction "3_3") (pintype "passive"))
      (node (ref "SV43") (pin "4") (pinfunction "4_4") (pintype "passive"))
      (node (ref "SV43") (pin "5") (pinfunction "5_5") (pintype "passive"))
      (node (ref "SV43") (pin "6") (pinfunction "6_6") (pintype "passive"))
      (node (ref "SV43") (pin "7") (pinfunction "7_7") (pintype "passive"))
      (node (ref "SV43") (pin "8") (pinfunction "8_8") (pintype "passive"))
      (node (ref "SV43") (pin "9") (pinfunction "9_9") (pintype "passive"))
      (node (ref "SV45") (pin "1") (pinfunction "1_1") (pintype "passive"))
      (node (ref "SV45") (pin "10") (pinfunction "10_10") (pintype "passive"))
      (node (ref "SV45") (pin "11") (pinfunction "11_11") (pintype "passive"))
      (node (ref "SV45") (pin "12") (pinfunction "12_12") (pintype "passive"))
      (node (ref "SV45") (pin "2") (pinfunction "2_2") (pintype "passive"))
      (node (ref "SV45") (pin "3") (pinfunction "3_3") (pintype "passive"))
      (node (ref "SV45") (pin "4") (pinfunction "4_4") (pintype "passive"))
      (node (ref "SV45") (pin "5") (pinfunction "5_5") (pintype "passive"))
      (node (ref "SV45") (pin "6") (pinfunction "6_6") (pintype "passive"))
      (node (ref "SV45") (pin "7") (pinfunction "7_7") (pintype "passive"))
      (node (ref "SV45") (pin "8") (pinfunction "8_8") (pintype "passive"))
      (node (ref "SV45") (pin "9") (pinfunction "9_9") (pintype "passive"))
      (node (ref "SV47") (pin "1") (pinfunction "1_1") (pintype "passive"))
      (node (ref "SV47") (pin "10") (pinfunction "10_10") (pintype "passive"))
      (node (ref "SV47") (pin "11") (pinfunction "11_11") (pintype "passive"))
      (node (ref "SV47") (pin "12") (pinfunction "12_12") (pintype "passive"))
      (node (ref "SV47") (pin "2") (pinfunction "2_2") (pintype "passive"))
      (node (ref "SV47") (pin "3") (pinfunction "3_3") (pintype "passive"))
      (node (ref "SV47") (pin "4") (pinfunction "4_4") (pintype "passive"))
      (node (ref "SV47") (pin "5") (pinfunction "5_5") (pintype "passive"))
      (node (ref "SV47") (pin "6") (pinfunction "6_6") (pintype "passive"))
      (node (ref "SV47") (pin "7") (pinfunction "7_7") (pintype "passive"))
      (node (ref "SV47") (pin "8") (pinfunction "8_8") (pintype "passive"))
      (node (ref "SV47") (pin "9") (pinfunction "9_9") (pintype "passive"))
      (node (ref "SV49") (pin "1") (pinfunction "1_1") (pintype "passive"))
      (node (ref "SV49") (pin "10") (pinfunction "10_10") (pintype "passive"))
      (node (ref "SV49") (pin "11") (pinfunction "11_11") (pintype "passive"))
      (node (ref "SV49") (pin "12") (pinfunction "12_12") (pintype "passive"))
      (node (ref "SV49") (pin "2") (pinfunction "2_2") (pintype "passive"))
      (node (ref "SV49") (pin "3") (pinfunction "3_3") (pintype "passive"))
      (node (ref "SV49") (pin "4") (pinfunction "4_4") (pintype "passive"))
      (node (ref "SV49") (pin "5") (pinfunction "5_5") (pintype "passive"))
      (node (ref "SV49") (pin "6") (pinfunction "6_6") (pintype "passive"))
      (node (ref "SV49") (pin "7") (pinfunction "7_7") (pintype "passive"))
      (node (ref "SV49") (pin "8") (pinfunction "8_8") (pintype "passive"))
      (node (ref "SV49") (pin "9") (pinfunction "9_9") (pintype "passive"))
      (node (ref "SV5") (pin "1") (pinfunction "1_1") (pintype "passive"))
      (node (ref "SV5") (pin "10") (pinfunction "10_10") (pintype "passive"))
      (node (ref "SV5") (pin "11") (pinfunction "11_11") (pintype "passive"))
      (node (ref "SV5") (pin "12") (pinfunction "12_12") (pintype "passive"))
      (node (ref "SV5") (pin "2") (pinfunction "2_2") (pintype "passive"))
      (node (ref "SV5") (pin "3") (pinfunction "3_3") (pintype "passive"))
      (node (ref "SV5") (pin "4") (pinfunction "4_4") (pintype "passive"))
      (node (ref "SV5") (pin "5") (pinfunction "5_5") (pintype "passive"))
      (node (ref "SV5") (pin "6") (pinfunction "6_6") (pintype "passive"))
      (node (ref "SV5") (pin "7") (pinfunction "7_7") (pintype "passive"))
      (node (ref "SV5") (pin "8") (pinfunction "8_8") (pintype "passive"))
      (node (ref "SV5") (pin "9") (pinfunction "9_9") (pintype "passive"))
      (node (ref "SV51") (pin "1") (pinfunction "1_1") (pintype "passive"))
      (node (ref "SV51") (pin "10") (pinfunction "10_10") (pintype "passive"))
      (node (ref "SV51") (pin "11") (pinfunction "11_11") (pintype "passive"))
      (node (ref "SV51") (pin "12") (pinfunction "12_12") (pintype "passive"))
      (node (ref "SV51") (pin "2") (pinfunction "2_2") (pintype "passive"))
      (node (ref "SV51") (pin "3") (pinfunction "3_3") (pintype "passive"))
      (node (ref "SV51") (pin "4") (pinfunction "4_4") (pintype "passive"))
      (node (ref "SV51") (pin "5") (pinfunction "5_5") (pintype "passive"))
      (node (ref "SV51") (pin "6") (pinfunction "6_6") (pintype "passive"))
      (node (ref "SV51") (pin "7") (pinfunction "7_7") (pintype "passive"))
      (node (ref "SV51") (pin "8") (pinfunction "8_8") (pintype "passive"))
      (node (ref "SV51") (pin "9") (pinfunction "9_9") (pintype "passive"))
      (node (ref "SV53") (pin "1") (pinfunction "1_1") (pintype "passive"))
      (node (ref "SV53") (pin "10") (pinfunction "10_10") (pintype "passive"))
      (node (ref "SV53") (pin "11") (pinfunction "11_11") (pintype "passive"))
      (node (ref "SV53") (pin "12") (pinfunction "12_12") (pintype "passive"))
      (node (ref "SV53") (pin "2") (pinfunction "2_2") (pintype "passive"))
      (node (ref "SV53") (pin "3") (pinfunction "3_3") (pintype "passive"))
      (node (ref "SV53") (pin "4") (pinfunction "4_4") (pintype "passive"))
      (node (ref "SV53") (pin "5") (pinfunction "5_5") (pintype "passive"))
      (node (ref "SV53") (pin "6") (pinfunction "6_6") (pintype "passive"))
      (node (ref "SV53") (pin "7") (pinfunction "7_7") (pintype "passive"))
      (node (ref "SV53") (pin "8") (pinfunction "8_8") (pintype "passive"))
      (node (ref "SV53") (pin "9") (pinfunction "9_9") (pintype "passive"))
      (node (ref "SV55") (pin "1") (pinfunction "1_1") (pintype "passive"))
      (node (ref "SV55") (pin "10") (pinfunction "10_10") (pintype "passive"))
      (node (ref "SV55") (pin "11") (pinfunction "11_11") (pintype "passive"))
      (node (ref "SV55") (pin "12") (pinfunction "12_12") (pintype "passive"))
      (node (ref "SV55") (pin "2") (pinfunction "2_2") (pintype "passive"))
      (node (ref "SV55") (pin "3") (pinfunction "3_3") (pintype "passive"))
      (node (ref "SV55") (pin "4") (pinfunction "4_4") (pintype "passive"))
      (node (ref "SV55") (pin "5") (pinfunction "5_5") (pintype "passive"))
      (node (ref "SV55") (pin "6") (pinfunction "6_6") (pintype "passive"))
      (node (ref "SV55") (pin "7") (pinfunction "7_7") (pintype "passive"))
      (node (ref "SV55") (pin "8") (pinfunction "8_8") (pintype "passive"))
      (node (ref "SV55") (pin "9") (pinfunction "9_9") (pintype "passive"))
      (node (ref "SV57") (pin "1") (pinfunction "1_1") (pintype "passive"))
      (node (ref "SV57") (pin "10") (pinfunction "10_10") (pintype "passive"))
      (node (ref "SV57") (pin "11") (pinfunction "11_11") (pintype "passive"))
      (node (ref "SV57") (pin "12") (pinfunction "12_12") (pintype "passive"))
      (node (ref "SV57") (pin "2") (pinfunction "2_2") (pintype "passive"))
      (node (ref "SV57") (pin "3") (pinfunction "3_3") (pintype "passive"))
      (node (ref "SV57") (pin "4") (pinfunction "4_4") (pintype "passive"))
      (node (ref "SV57") (pin "5") (pinfunction "5_5") (pintype "passive"))
      (node (ref "SV57") (pin "6") (pinfunction "6_6") (pintype "passive"))
      (node (ref "SV57") (pin "7") (pinfunction "7_7") (pintype "passive"))
      (node (ref "SV57") (pin "8") (pinfunction "8_8") (pintype "passive"))
      (node (ref "SV57") (pin "9") (pinfunction "9_9") (pintype "passive"))
      (node (ref "SV59") (pin "1") (pinfunction "1_1") (pintype "passive"))
      (node (ref "SV59") (pin "10") (pinfunction "10_10") (pintype "passive"))
      (node (ref "SV59") (pin "11") (pinfunction "11_11") (pintype "passive"))
      (node (ref "SV59") (pin "12") (pinfunction "12_12") (pintype "passive"))
      (node (ref "SV59") (pin "2") (pinfunction "2_2") (pintype "passive"))
      (node (ref "SV59") (pin "3") (pinfunction "3_3") (pintype "passive"))
      (node (ref "SV59") (pin "4") (pinfunction "4_4") (pintype "passive"))
      (node (ref "SV59") (pin "5") (pinfunction "5_5") (pintype "passive"))
      (node (ref "SV59") (pin "6") (pinfunction "6_6") (pintype "passive"))
      (node (ref "SV59") (pin "7") (pinfunction "7_7") (pintype "passive"))
      (node (ref "SV59") (pin "8") (pinfunction "8_8") (pintype "passive"))
      (node (ref "SV59") (pin "9") (pinfunction "9_9") (pintype "passive"))
      (node (ref "SV61") (pin "1") (pinfunction "1_1") (pintype "passive"))
      (node (ref "SV61") (pin "10") (pinfunction "10_10") (pintype "passive"))
      (node (ref "SV61") (pin "11") (pinfunction "11_11") (pintype "passive"))
      (node (ref "SV61") (pin "12") (pinfunction "12_12") (pintype "passive"))
      (node (ref "SV61") (pin "2") (pinfunction "2_2") (pintype "passive"))
      (node (ref "SV61") (pin "3") (pinfunction "3_3") (pintype "passive"))
      (node (ref "SV61") (pin "4") (pinfunction "4_4") (pintype "passive"))
      (node (ref "SV61") (pin "5") (pinfunction "5_5") (pintype "passive"))
      (node (ref "SV61") (pin "6") (pinfunction "6_6") (pintype "passive"))
      (node (ref "SV61") (pin "7") (pinfunction "7_7") (pintype "passive"))
      (node (ref "SV61") (pin "8") (pinfunction "8_8") (pintype "passive"))
      (node (ref "SV61") (pin "9") (pinfunction "9_9") (pintype "passive"))
      (node (ref "SV63") (pin "1") (pinfunction "1_1") (pintype "passive"))
      (node (ref "SV63") (pin "10") (pinfunction "10_10") (pintype "passive"))
      (node (ref "SV63") (pin "11") (pinfunction "11_11") (pintype "passive"))
      (node (ref "SV63") (pin "12") (pinfunction "12_12") (pintype "passive"))
      (node (ref "SV63") (pin "2") (pinfunction "2_2") (pintype "passive"))
      (node (ref "SV63") (pin "3") (pinfunction "3_3") (pintype "passive"))
      (node (ref "SV63") (pin "4") (pinfunction "4_4") (pintype "passive"))
      (node (ref "SV63") (pin "5") (pinfunction "5_5") (pintype "passive"))
      (node (ref "SV63") (pin "6") (pinfunction "6_6") (pintype "passive"))
      (node (ref "SV63") (pin "7") (pinfunction "7_7") (pintype "passive"))
      (node (ref "SV63") (pin "8") (pinfunction "8_8") (pintype "passive"))
      (node (ref "SV63") (pin "9") (pinfunction "9_9") (pintype "passive"))
      (node (ref "SV65") (pin "1") (pinfunction "1_1") (pintype "passive"))
      (node (ref "SV65") (pin "10") (pinfunction "10_10") (pintype "passive"))
      (node (ref "SV65") (pin "11") (pinfunction "11_11") (pintype "passive"))
      (node (ref "SV65") (pin "12") (pinfunction "12_12") (pintype "passive"))
      (node (ref "SV65") (pin "2") (pinfunction "2_2") (pintype "passive"))
      (node (ref "SV65") (pin "3") (pinfunction "3_3") (pintype "passive"))
      (node (ref "SV65") (pin "4") (pinfunction "4_4") (pintype "passive"))
      (node (ref "SV65") (pin "5") (pinfunction "5_5") (pintype "passive"))
      (node (ref "SV65") (pin "6") (pinfunction "6_6") (pintype "passive"))
      (node (ref "SV65") (pin "7") (pinfunction "7_7") (pintype "passive"))
      (node (ref "SV65") (pin "8") (pinfunction "8_8") (pintype "passive"))
      (node (ref "SV65") (pin "9") (pinfunction "9_9") (pintype "passive"))
      (node (ref "SV67") (pin "1") (pinfunction "1_1") (pintype "passive"))
      (node (ref "SV67") (pin "10") (pinfunction "10_10") (pintype "passive"))
      (node (ref "SV67") (pin "11") (pinfunction "11_11") (pintype "passive"))
      (node (ref "SV67") (pin "12") (pinfunction "12_12") (pintype "passive"))
      (node (ref "SV67") (pin "2") (pinfunction "2_2") (pintype "passive"))
      (node (ref "SV67") (pin "3") (pinfunction "3_3") (pintype "passive"))
      (node (ref "SV67") (pin "4") (pinfunction "4_4") (pintype "passive"))
      (node (ref "SV67") (pin "5") (pinfunction "5_5") (pintype "passive"))
      (node (ref "SV67") (pin "6") (pinfunction "6_6") (pintype "passive"))
      (node (ref "SV67") (pin "7") (pinfunction "7_7") (pintype "passive"))
      (node (ref "SV67") (pin "8") (pinfunction "8_8") (pintype "passive"))
      (node (ref "SV67") (pin "9") (pinfunction "9_9") (pintype "passive"))
      (node (ref "SV69") (pin "1") (pinfunction "1_1") (pintype "passive"))
      (node (ref "SV69") (pin "10") (pinfunction "10_10") (pintype "passive"))
      (node (ref "SV69") (pin "11") (pinfunction "11_11") (pintype "passive"))
      (node (ref "SV69") (pin "12") (pinfunction "12_12") (pintype "passive"))
      (node (ref "SV69") (pin "2") (pinfunction "2_2") (pintype "passive"))
      (node (ref "SV69") (pin "3") (pinfunction "3_3") (pintype "passive"))
      (node (ref "SV69") (pin "4") (pinfunction "4_4") (pintype "passive"))
      (node (ref "SV69") (pin "5") (pinfunction "5_5") (pintype "passive"))
      (node (ref "SV69") (pin "6") (pinfunction "6_6") (pintype "passive"))
      (node (ref "SV69") (pin "7") (pinfunction "7_7") (pintype "passive"))
      (node (ref "SV69") (pin "8") (pinfunction "8_8") (pintype "passive"))
      (node (ref "SV69") (pin "9") (pinfunction "9_9") (pintype "passive"))
      (node (ref "SV7") (pin "1") (pinfunction "1_1") (pintype "passive"))
      (node (ref "SV7") (pin "10") (pinfunction "10_10") (pintype "passive"))
      (node (ref "SV7") (pin "11") (pinfunction "11_11") (pintype "passive"))
      (node (ref "SV7") (pin "12") (pinfunction "12_12") (pintype "passive"))
      (node (ref "SV7") (pin "2") (pinfunction "2_2") (pintype "passive"))
      (node (ref "SV7") (pin "3") (pinfunction "3_3") (pintype "passive"))
      (node (ref "SV7") (pin "4") (pinfunction "4_4") (pintype "passive"))
      (node (ref "SV7") (pin "5") (pinfunction "5_5") (pintype "passive"))
      (node (ref "SV7") (pin "6") (pinfunction "6_6") (pintype "passive"))
      (node (ref "SV7") (pin "7") (pinfunction "7_7") (pintype "passive"))
      (node (ref "SV7") (pin "8") (pinfunction "8_8") (pintype "passive"))
      (node (ref "SV7") (pin "9") (pinfunction "9_9") (pintype "passive"))
      (node (ref "SV71") (pin "1") (pinfunction "1_1") (pintype "passive"))
      (node (ref "SV71") (pin "10") (pinfunction "10_10") (pintype "passive"))
      (node (ref "SV71") (pin "11") (pinfunction "11_11") (pintype "passive"))
      (node (ref "SV71") (pin "12") (pinfunction "12_12") (pintype "passive"))
      (node (ref "SV71") (pin "2") (pinfunction "2_2") (pintype "passive"))
      (node (ref "SV71") (pin "3") (pinfunction "3_3") (pintype "passive"))
      (node (ref "SV71") (pin "4") (pinfunction "4_4") (pintype "passive"))
      (node (ref "SV71") (pin "5") (pinfunction "5_5") (pintype "passive"))
      (node (ref "SV71") (pin "6") (pinfunction "6_6") (pintype "passive"))
      (node (ref "SV71") (pin "7") (pinfunction "7_7") (pintype "passive"))
      (node (ref "SV71") (pin "8") (pinfunction "8_8") (pintype "passive"))
      (node (ref "SV71") (pin "9") (pinfunction "9_9") (pintype "passive"))
      (node (ref "SV73") (pin "1") (pinfunction "1_1") (pintype "passive"))
      (node (ref "SV73") (pin "10") (pinfunction "10_10") (pintype "passive"))
      (node (ref "SV73") (pin "11") (pinfunction "11_11") (pintype "passive"))
      (node (ref "SV73") (pin "12") (pinfunction "12_12") (pintype "passive"))
      (node (ref "SV73") (pin "2") (pinfunction "2_2") (pintype "passive"))
      (node (ref "SV73") (pin "3") (pinfunction "3_3") (pintype "passive"))
      (node (ref "SV73") (pin "4") (pinfunction "4_4") (pintype "passive"))
      (node (ref "SV73") (pin "5") (pinfunction "5_5") (pintype "passive"))
      (node (ref "SV73") (pin "6") (pinfunction "6_6") (pintype "passive"))
      (node (ref "SV73") (pin "7") (pinfunction "7_7") (pintype "passive"))
      (node (ref "SV73") (pin "8") (pinfunction "8_8") (pintype "passive"))
      (node (ref "SV73") (pin "9") (pinfunction "9_9") (pintype "passive"))
      (node (ref "SV75") (pin "1") (pinfunction "1_1") (pintype "passive"))
      (node (ref "SV75") (pin "10") (pinfunction "10_10") (pintype "passive"))
      (node (ref "SV75") (pin "11") (pinfunction "11_11") (pintype "passive"))
      (node (ref "SV75") (pin "12") (pinfunction "12_12") (pintype "passive"))
      (node (ref "SV75") (pin "2") (pinfunction "2_2") (pintype "passive"))
      (node (ref "SV75") (pin "3") (pinfunction "3_3") (pintype "passive"))
      (node (ref "SV75") (pin "4") (pinfunction "4_4") (pintype "passive"))
      (node (ref "SV75") (pin "5") (pinfunction "5_5") (pintype "passive"))
      (node (ref "SV75") (pin "6") (pinfunction "6_6") (pintype "passive"))
      (node (ref "SV75") (pin "7") (pinfunction "7_7") (pintype "passive"))
      (node (ref "SV75") (pin "8") (pinfunction "8_8") (pintype "passive"))
      (node (ref "SV75") (pin "9") (pinfunction "9_9") (pintype "passive"))
      (node (ref "SV77") (pin "1") (pinfunction "1_1") (pintype "passive"))
      (node (ref "SV77") (pin "10") (pinfunction "10_10") (pintype "passive"))
      (node (ref "SV77") (pin "11") (pinfunction "11_11") (pintype "passive"))
      (node (ref "SV77") (pin "12") (pinfunction "12_12") (pintype "passive"))
      (node (ref "SV77") (pin "2") (pinfunction "2_2") (pintype "passive"))
      (node (ref "SV77") (pin "3") (pinfunction "3_3") (pintype "passive"))
      (node (ref "SV77") (pin "4") (pinfunction "4_4") (pintype "passive"))
      (node (ref "SV77") (pin "5") (pinfunction "5_5") (pintype "passive"))
      (node (ref "SV77") (pin "6") (pinfunction "6_6") (pintype "passive"))
      (node (ref "SV77") (pin "7") (pinfunction "7_7") (pintype "passive"))
      (node (ref "SV77") (pin "8") (pinfunction "8_8") (pintype "passive"))
      (node (ref "SV77") (pin "9") (pinfunction "9_9") (pintype "passive"))
      (node (ref "SV79") (pin "1") (pinfunction "1_1") (pintype "passive"))
      (node (ref "SV79") (pin "10") (pinfunction "10_10") (pintype "passive"))
      (node (ref "SV79") (pin "11") (pinfunction "11_11") (pintype "passive"))
      (node (ref "SV79") (pin "12") (pinfunction "12_12") (pintype "passive"))
      (node (ref "SV79") (pin "2") (pinfunction "2_2") (pintype "passive"))
      (node (ref "SV79") (pin "3") (pinfunction "3_3") (pintype "passive"))
      (node (ref "SV79") (pin "4") (pinfunction "4_4") (pintype "passive"))
      (node (ref "SV79") (pin "5") (pinfunction "5_5") (pintype "passive"))
      (node (ref "SV79") (pin "6") (pinfunction "6_6") (pintype "passive"))
      (node (ref "SV79") (pin "7") (pinfunction "7_7") (pintype "passive"))
      (node (ref "SV79") (pin "8") (pinfunction "8_8") (pintype "passive"))
      (node (ref "SV79") (pin "9") (pinfunction "9_9") (pintype "passive"))
      (node (ref "SV81") (pin "1") (pinfunction "1_1") (pintype "passive"))
      (node (ref "SV81") (pin "10") (pinfunction "10_10") (pintype "passive"))
      (node (ref "SV81") (pin "11") (pinfunction "11_11") (pintype "passive"))
      (node (ref "SV81") (pin "12") (pinfunction "12_12") (pintype "passive"))
      (node (ref "SV81") (pin "2") (pinfunction "2_2") (pintype "passive"))
      (node (ref "SV81") (pin "3") (pinfunction "3_3") (pintype "passive"))
      (node (ref "SV81") (pin "4") (pinfunction "4_4") (pintype "passive"))
      (node (ref "SV81") (pin "5") (pinfunction "5_5") (pintype "passive"))
      (node (ref "SV81") (pin "6") (pinfunction "6_6") (pintype "passive"))
      (node (ref "SV81") (pin "7") (pinfunction "7_7") (pintype "passive"))
      (node (ref "SV81") (pin "8") (pinfunction "8_8") (pintype "passive"))
      (node (ref "SV81") (pin "9") (pinfunction "9_9") (pintype "passive"))
      (node (ref "SV83") (pin "1") (pinfunction "1_1") (pintype "passive"))
      (node (ref "SV83") (pin "10") (pinfunction "10_10") (pintype "passive"))
      (node (ref "SV83") (pin "11") (pinfunction "11_11") (pintype "passive"))
      (node (ref "SV83") (pin "12") (pinfunction "12_12") (pintype "passive"))
      (node (ref "SV83") (pin "2") (pinfunction "2_2") (pintype "passive"))
      (node (ref "SV83") (pin "3") (pinfunction "3_3") (pintype "passive"))
      (node (ref "SV83") (pin "4") (pinfunction "4_4") (pintype "passive"))
      (node (ref "SV83") (pin "5") (pinfunction "5_5") (pintype "passive"))
      (node (ref "SV83") (pin "6") (pinfunction "6_6") (pintype "passive"))
      (node (ref "SV83") (pin "7") (pinfunction "7_7") (pintype "passive"))
      (node (ref "SV83") (pin "8") (pinfunction "8_8") (pintype "passive"))
      (node (ref "SV83") (pin "9") (pinfunction "9_9") (pintype "passive"))
      (node (ref "SV85") (pin "1") (pinfunction "1_1") (pintype "passive"))
      (node (ref "SV85") (pin "10") (pinfunction "10_10") (pintype "passive"))
      (node (ref "SV85") (pin "11") (pinfunction "11_11") (pintype "passive"))
      (node (ref "SV85") (pin "12") (pinfunction "12_12") (pintype "passive"))
      (node (ref "SV85") (pin "2") (pinfunction "2_2") (pintype "passive"))
      (node (ref "SV85") (pin "3") (pinfunction "3_3") (pintype "passive"))
      (node (ref "SV85") (pin "4") (pinfunction "4_4") (pintype "passive"))
      (node (ref "SV85") (pin "5") (pinfunction "5_5") (pintype "passive"))
      (node (ref "SV85") (pin "6") (pinfunction "6_6") (pintype "passive"))
      (node (ref "SV85") (pin "7") (pinfunction "7_7") (pintype "passive"))
      (node (ref "SV85") (pin "8") (pinfunction "8_8") (pintype "passive"))
      (node (ref "SV85") (pin "9") (pinfunction "9_9") (pintype "passive"))
      (node (ref "SV87") (pin "1") (pinfunction "1_1") (pintype "passive"))
      (node (ref "SV87") (pin "10") (pinfunction "10_10") (pintype "passive"))
      (node (ref "SV87") (pin "11") (pinfunction "11_11") (pintype "passive"))
      (node (ref "SV87") (pin "12") (pinfunction "12_12") (pintype "passive"))
      (node (ref "SV87") (pin "2") (pinfunction "2_2") (pintype "passive"))
      (node (ref "SV87") (pin "3") (pinfunction "3_3") (pintype "passive"))
      (node (ref "SV87") (pin "4") (pinfunction "4_4") (pintype "passive"))
      (node (ref "SV87") (pin "5") (pinfunction "5_5") (pintype "passive"))
      (node (ref "SV87") (pin "6") (pinfunction "6_6") (pintype "passive"))
      (node (ref "SV87") (pin "7") (pinfunction "7_7") (pintype "passive"))
      (node (ref "SV87") (pin "8") (pinfunction "8_8") (pintype "passive"))
      (node (ref "SV87") (pin "9") (pinfunction "9_9") (pintype "passive"))
      (node (ref "SV89") (pin "1") (pinfunction "1_1") (pintype "passive"))
      (node (ref "SV89") (pin "10") (pinfunction "10_10") (pintype "passive"))
      (node (ref "SV89") (pin "11") (pinfunction "11_11") (pintype "passive"))
      (node (ref "SV89") (pin "12") (pinfunction "12_12") (pintype "passive"))
      (node (ref "SV89") (pin "2") (pinfunction "2_2") (pintype "passive"))
      (node (ref "SV89") (pin "3") (pinfunction "3_3") (pintype "passive"))
      (node (ref "SV89") (pin "4") (pinfunction "4_4") (pintype "passive"))
      (node (ref "SV89") (pin "5") (pinfunction "5_5") (pintype "passive"))
      (node (ref "SV89") (pin "6") (pinfunction "6_6") (pintype "passive"))
      (node (ref "SV89") (pin "7") (pinfunction "7_7") (pintype "passive"))
      (node (ref "SV89") (pin "8") (pinfunction "8_8") (pintype "passive"))
      (node (ref "SV89") (pin "9") (pinfunction "9_9") (pintype "passive"))
      (node (ref "SV9") (pin "1") (pinfunction "1_1") (pintype "passive"))
      (node (ref "SV9") (pin "10") (pinfunction "10_10") (pintype "passive"))
      (node (ref "SV9") (pin "11") (pinfunction "11_11") (pintype "passive"))
      (node (ref "SV9") (pin "12") (pinfunction "12_12") (pintype "passive"))
      (node (ref "SV9") (pin "2") (pinfunction "2_2") (pintype "passive"))
      (node (ref "SV9") (pin "3") (pinfunction "3_3") (pintype "passive"))
      (node (ref "SV9") (pin "4") (pinfunction "4_4") (pintype "passive"))
      (node (ref "SV9") (pin "5") (pinfunction "5_5") (pintype "passive"))
      (node (ref "SV9") (pin "6") (pinfunction "6_6") (pintype "passive"))
      (node (ref "SV9") (pin "7") (pinfunction "7_7") (pintype "passive"))
      (node (ref "SV9") (pin "8") (pinfunction "8_8") (pintype "passive"))
      (node (ref "SV9") (pin "9") (pinfunction "9_9") (pintype "passive"))
      (node (ref "SV91") (pin "1") (pinfunction "1_1") (pintype "passive"))
      (node (ref "SV91") (pin "10") (pinfunction "10_10") (pintype "passive"))
      (node (ref "SV91") (pin "11") (pinfunction "11_11") (pintype "passive"))
      (node (ref "SV91") (pin "12") (pinfunction "12_12") (pintype "passive"))
      (node (ref "SV91") (pin "2") (pinfunction "2_2") (pintype "passive"))
      (node (ref "SV91") (pin "3") (pinfunction "3_3") (pintype "passive"))
      (node (ref "SV91") (pin "4") (pinfunction "4_4") (pintype "passive"))
      (node (ref "SV91") (pin "5") (pinfunction "5_5") (pintype "passive"))
      (node (ref "SV91") (pin "6") (pinfunction "6_6") (pintype "passive"))
      (node (ref "SV91") (pin "7") (pinfunction "7_7") (pintype "passive"))
      (node (ref "SV91") (pin "8") (pinfunction "8_8") (pintype "passive"))
      (node (ref "SV91") (pin "9") (pinfunction "9_9") (pintype "passive"))
      (node (ref "U$2") (pin "AA2") (pinfunction "1_AA2") (pintype "bidirectional"))
      (node (ref "U$2") (pin "BA2") (pinfunction "1_BA2") (pintype "bidirectional"))
      (node (ref "U$2") (pin "CA2") (pinfunction "1_CA2") (pintype "bidirectional"))
    )
    (net (code "1228") (name "WRITE") (class "Default")
      (node (ref "D10") (pin "15") (pinfunction "15_15") (pintype "passive"))
      (node (ref "U$2") (pin "AS2") (pinfunction "1_AS2") (pintype "bidirectional"))
    )
    (net (code "1229") (name "~{BREAK_CYCLE}") (class "Default")
      (node (ref "D8") (pin "10") (pinfunction "10_10") (pintype "passive"))
      (node (ref "U$2") (pin "BL2") (pinfunction "1_BL2") (pintype "bidirectional"))
    )
    (net (code "1230") (name "~{BRK_DATA_CONT}") (class "Default")
      (node (ref "D8") (pin "9") (pinfunction "9_9") (pintype "passive"))
      (node (ref "U$2") (pin "BK2") (pinfunction "1_BK2") (pintype "bidirectional"))
    )
    (net (code "1231") (name "~{BRK_IN_PROG}") (class "Default")
      (node (ref "D8") (pin "5") (pinfunction "5_5") (pintype "passive"))
      (node (ref "U$2") (pin "BE2") (pinfunction "1_BE2") (pintype "bidirectional"))
    )
    (net (code "1232") (name "~{BUS_STROBE}") (class "Default")
      (node (ref "D11") (pin "9") (pinfunction "9_9") (pintype "passive"))
      (node (ref "U$2") (pin "CK1") (pinfunction "1_CK1") (pintype "bidirectional"))
    )
    (net (code "1233") (name "~{C0}") (class "Default")
      (node (ref "D11") (pin "5") (pinfunction "5_5") (pintype "passive"))
      (node (ref "U$2") (pin "CE1") (pinfunction "1_CE1") (pintype "bidirectional"))
    )
    (net (code "1234") (name "~{C1}") (class "Default")
      (node (ref "D11") (pin "7") (pinfunction "7_7") (pintype "passive"))
      (node (ref "U$2") (pin "CH1") (pinfunction "1_CH1") (pintype "bidirectional"))
    )
    (net (code "1235") (name "~{C2}") (class "Default")
      (node (ref "D11") (pin "8") (pinfunction "8_8") (pintype "passive"))
      (node (ref "U$2") (pin "CJ1") (pinfunction "1_CJ1") (pintype "bidirectional"))
    )
    (net (code "1236") (name "~{CPMA_DISABLE}") (class "Default")
      (node (ref "D11") (pin "17") (pinfunction "17_17") (pintype "passive"))
      (node (ref "U$2") (pin "CU1") (pinfunction "1_CU1") (pintype "bidirectional"))
    )
    (net (code "1237") (name "~{DATA0}") (class "Default")
      (node (ref "D9") (pin "14") (pinfunction "14_14") (pintype "passive"))
      (node (ref "U$2") (pin "AR1") (pinfunction "1_AR1") (pintype "bidirectional"))
    )
    (net (code "1238") (name "~{DATA1}") (class "Default")
      (node (ref "D9") (pin "15") (pinfunction "15_15") (pintype "passive"))
      (node (ref "U$2") (pin "AS1") (pinfunction "1_AS1") (pintype "bidirectional"))
    )
    (net (code "1239") (name "~{DATA2}") (class "Default")
      (node (ref "D9") (pin "17") (pinfunction "17_17") (pintype "passive"))
      (node (ref "U$2") (pin "AU1") (pinfunction "1_AU1") (pintype "bidirectional"))
    )
    (net (code "1240") (name "~{DATA3}") (class "Default")
      (node (ref "D9") (pin "18") (pinfunction "18_18") (pintype "passive"))
      (node (ref "U$2") (pin "AV1") (pinfunction "1_AV1") (pintype "bidirectional"))
    )
    (net (code "1241") (name "~{DATA4}") (class "Default")
      (node (ref "D7") (pin "14") (pinfunction "14_14") (pintype "passive"))
      (node (ref "U$2") (pin "BR1") (pinfunction "1_BR1") (pintype "bidirectional"))
    )
    (net (code "1242") (name "~{DATA5}") (class "Default")
      (node (ref "D7") (pin "15") (pinfunction "15_15") (pintype "passive"))
      (node (ref "U$2") (pin "BS1") (pinfunction "1_BS1") (pintype "bidirectional"))
    )
    (net (code "1243") (name "~{DATA6}") (class "Default")
      (node (ref "D7") (pin "17") (pinfunction "17_17") (pintype "passive"))
      (node (ref "U$2") (pin "BU1") (pinfunction "1_BU1") (pintype "bidirectional"))
    )
    (net (code "1244") (name "~{DATA7}") (class "Default")
      (node (ref "D7") (pin "18") (pinfunction "18_18") (pintype "passive"))
      (node (ref "U$2") (pin "BV1") (pinfunction "1_BV1") (pintype "bidirectional"))
    )
    (net (code "1245") (name "~{DATA8}") (class "Default")
      (node (ref "D13") (pin "14") (pinfunction "14_14") (pintype "passive"))
      (node (ref "U$2") (pin "DR1") (pinfunction "1_DR1") (pintype "bidirectional"))
    )
    (net (code "1246") (name "~{DATA9}") (class "Default")
      (node (ref "D13") (pin "15") (pinfunction "15_15") (pintype "passive"))
      (node (ref "U$2") (pin "DS1") (pinfunction "1_DS1") (pintype "bidirectional"))
    )
    (net (code "1247") (name "~{DATA10}") (class "Default")
      (node (ref "D13") (pin "17") (pinfunction "17_17") (pintype "passive"))
      (node (ref "U$2") (pin "DU1") (pinfunction "1_DU1") (pintype "bidirectional"))
    )
    (net (code "1248") (name "~{DATA11}") (class "Default")
      (node (ref "D13") (pin "18") (pinfunction "18_18") (pintype "passive"))
      (node (ref "U$2") (pin "DV1") (pinfunction "1_DV1") (pintype "bidirectional"))
    )
    (net (code "1249") (name "~{D}") (class "Default")
      (node (ref "D14") (pin "9") (pinfunction "9_9") (pintype "passive"))
      (node (ref "U$2") (pin "DK2") (pinfunction "1_DK2") (pintype "bidirectional"))
    )
    (net (code "1250") (name "~{EMA0}") (class "Default")
      (node (ref "D10") (pin "4") (pinfunction "4_4") (pintype "passive"))
      (node (ref "U$2") (pin "AD2") (pinfunction "1_AD2") (pintype "bidirectional"))
    )
    (net (code "1251") (name "~{EMA1}") (class "Default")
      (node (ref "D10") (pin "5") (pinfunction "5_5") (pintype "passive"))
      (node (ref "U$2") (pin "AE2") (pinfunction "1_AE2") (pintype "bidirectional"))
    )
    (net (code "1252") (name "~{EMA2}") (class "Default")
      (node (ref "D10") (pin "7") (pinfunction "7_7") (pintype "passive"))
      (node (ref "U$2") (pin "AH2") (pinfunction "1_AH2") (pintype "bidirectional"))
    )
    (net (code "1253") (name "~{E}") (class "Default")
      (node (ref "D14") (pin "10") (pinfunction "10_10") (pintype "passive"))
      (node (ref "U$2") (pin "DL2") (pinfunction "1_DL2") (pintype "bidirectional"))
    )
    (net (code "1254") (name "~{FSET}") (class "Default")
      (node (ref "D14") (pin "13") (pinfunction "13_13") (pintype "passive"))
      (node (ref "U$2") (pin "DP2") (pinfunction "1_DP2") (pintype "bidirectional"))
    )
    (net (code "1255") (name "~{F}") (class "Default")
      (node (ref "D14") (pin "8") (pinfunction "8_8") (pintype "passive"))
      (node (ref "U$2") (pin "DJ2") (pinfunction "1_DJ2") (pintype "bidirectional"))
    )
    (net (code "1256") (name "~{IND1}") (class "Default")
      (node (ref "D12") (pin "17") (pinfunction "17_17") (pintype "passive"))
      (node (ref "U$2") (pin "CU2") (pinfunction "1_CU2") (pintype "bidirectional"))
    )
    (net (code "1257") (name "~{IND2}") (class "Default")
      (node (ref "D12") (pin "18") (pinfunction "18_18") (pintype "passive"))
      (node (ref "U$2") (pin "CV2") (pinfunction "1_CV2") (pintype "bidirectional"))
    )
    (net (code "1258") (name "~{INTERNAL_IO}") (class "Default")
      (node (ref "D11") (pin "10") (pinfunction "10_10") (pintype "passive"))
      (node (ref "U$2") (pin "CL1") (pinfunction "1_CL1") (pintype "bidirectional"))
    )
    (net (code "1259") (name "~{INT_RQST}") (class "Default")
      (node (ref "D11") (pin "13") (pinfunction "13_13") (pintype "passive"))
      (node (ref "U$2") (pin "CP1") (pinfunction "1_CP1") (pintype "bidirectional"))
    )
    (net (code "1260") (name "~{IO_PAUSE}") (class "Default")
      (node (ref "D11") (pin "4") (pinfunction "4_4") (pintype "passive"))
      (node (ref "U$2") (pin "CD1") (pinfunction "1_CD1") (pintype "bidirectional"))
    )
    (net (code "1261") (name "~{IR0}") (class "Default")
      (node (ref "D14") (pin "4") (pinfunction "4_4") (pintype "passive"))
      (node (ref "U$2") (pin "DD2") (pinfunction "1_DD2") (pintype "bidirectional"))
    )
    (net (code "1262") (name "~{IR1}") (class "Default")
      (node (ref "D14") (pin "5") (pinfunction "5_5") (pintype "passive"))
      (node (ref "U$2") (pin "DE2") (pinfunction "1_DE2") (pintype "bidirectional"))
    )
    (net (code "1263") (name "~{IR2}") (class "Default")
      (node (ref "D14") (pin "7") (pinfunction "7_7") (pintype "passive"))
      (node (ref "U$2") (pin "DH2") (pinfunction "1_DH2") (pintype "bidirectional"))
    )
    (net (code "1264") (name "~{KEY_CONT}") (class "Default")
      (node (ref "D14") (pin "17") (pinfunction "17_17") (pintype "passive"))
      (node (ref "U$2") (pin "DU2") (pinfunction "1_DU2") (pintype "bidirectional"))
    )
    (net (code "1265") (name "~{LA_ENABLE}") (class "Default")
      (node (ref "D8") (pin "11") (pinfunction "11_11") (pintype "passive"))
      (node (ref "U$2") (pin "BM2") (pinfunction "1_BM2") (pintype "bidirectional"))
    )
    (net (code "1266") (name "~{LINK_DATA}") (class "Default")
      (node (ref "D12") (pin "14") (pinfunction "14_14") (pintype "passive"))
      (node (ref "U$2") (pin "CR2") (pinfunction "1_CR2") (pintype "bidirectional"))
    )
    (net (code "1267") (name "~{LINK_LOAD}") (class "Default")
      (node (ref "D12") (pin "15") (pinfunction "15_15") (pintype "passive"))
      (node (ref "U$2") (pin "CS2") (pinfunction "1_CS2") (pintype "bidirectional"))
    )
    (net (code "1268") (name "~{LINK}") (class "Default")
      (node (ref "D10") (pin "18") (pinfunction "18_18") (pintype "passive"))
      (node (ref "U$2") (pin "AV2") (pinfunction "1_AV2") (pintype "bidirectional"))
    )
    (net (code "1269") (name "~{LOAD_CONT}") (class "Default")
      (node (ref "D8") (pin "7") (pinfunction "7_7") (pintype "passive"))
      (node (ref "U$2") (pin "BH2") (pinfunction "1_BH2") (pintype "bidirectional"))
    )
    (net (code "1270") (name "~{MA00}") (class "Default")
      (node (ref "D9") (pin "4") (pinfunction "4_4") (pintype "passive"))
      (node (ref "U$2") (pin "AD1") (pinfunction "1_AD1") (pintype "bidirectional"))
    )
    (net (code "1271") (name "~{MA01}") (class "Default")
      (node (ref "D9") (pin "5") (pinfunction "5_5") (pintype "passive"))
      (node (ref "U$2") (pin "AE1") (pinfunction "1_AE1") (pintype "bidirectional"))
    )
    (net (code "1272") (name "~{MA02}") (class "Default")
      (node (ref "D9") (pin "7") (pinfunction "7_7") (pintype "passive"))
      (node (ref "U$2") (pin "AH1") (pinfunction "1_AH1") (pintype "bidirectional"))
    )
    (net (code "1273") (name "~{MA03}") (class "Default")
      (node (ref "D9") (pin "8") (pinfunction "8_8") (pintype "passive"))
      (node (ref "U$2") (pin "AJ1") (pinfunction "1_AJ1") (pintype "bidirectional"))
    )
    (net (code "1274") (name "~{MA04}") (class "Default")
      (node (ref "D7") (pin "4") (pinfunction "4_4") (pintype "passive"))
      (node (ref "U$2") (pin "BD1") (pinfunction "1_BD1") (pintype "bidirectional"))
    )
    (net (code "1275") (name "~{MA05}") (class "Default")
      (node (ref "D7") (pin "5") (pinfunction "5_5") (pintype "passive"))
      (node (ref "U$2") (pin "BE1") (pinfunction "1_BE1") (pintype "bidirectional"))
    )
    (net (code "1276") (name "~{MA06}") (class "Default")
      (node (ref "D7") (pin "7") (pinfunction "7_7") (pintype "passive"))
      (node (ref "U$2") (pin "BH1") (pinfunction "1_BH1") (pintype "bidirectional"))
    )
    (net (code "1277") (name "~{MA07}") (class "Default")
      (node (ref "D7") (pin "8") (pinfunction "8_8") (pintype "passive"))
      (node (ref "U$2") (pin "BJ1") (pinfunction "1_BJ1") (pintype "bidirectional"))
    )
    (net (code "1278") (name "~{MA08}") (class "Default")
      (node (ref "D13") (pin "4") (pinfunction "4_4") (pintype "passive"))
      (node (ref "U$2") (pin "DD1") (pinfunction "1_DD1") (pintype "bidirectional"))
    )
    (net (code "1279") (name "~{MA09}") (class "Default")
      (node (ref "D13") (pin "5") (pinfunction "5_5") (pintype "passive"))
      (node (ref "U$2") (pin "DE1") (pinfunction "1_DE1") (pintype "bidirectional"))
    )
    (net (code "1280") (name "~{MA10}") (class "Default")
      (node (ref "D13") (pin "7") (pinfunction "7_7") (pintype "passive"))
      (node (ref "U$2") (pin "DH1") (pinfunction "1_DH1") (pintype "bidirectional"))
    )
    (net (code "1281") (name "~{MA11}") (class "Default")
      (node (ref "D13") (pin "8") (pinfunction "8_8") (pintype "passive"))
      (node (ref "U$2") (pin "DJ1") (pinfunction "1_DJ1") (pintype "bidirectional"))
    )
    (net (code "1282") (name "~{MD00}") (class "Default")
      (node (ref "D9") (pin "9") (pinfunction "9_9") (pintype "passive"))
      (node (ref "U$2") (pin "AK1") (pinfunction "1_AK1") (pintype "bidirectional"))
    )
    (net (code "1283") (name "~{MD01}") (class "Default")
      (node (ref "D9") (pin "10") (pinfunction "10_10") (pintype "passive"))
      (node (ref "U$2") (pin "AL1") (pinfunction "1_AL1") (pintype "bidirectional"))
    )
    (net (code "1284") (name "~{MD02}") (class "Default")
      (node (ref "D9") (pin "11") (pinfunction "11_11") (pintype "passive"))
      (node (ref "U$2") (pin "AM1") (pinfunction "1_AM1") (pintype "bidirectional"))
    )
    (net (code "1285") (name "~{MD03}") (class "Default")
      (node (ref "D9") (pin "13") (pinfunction "13_13") (pintype "passive"))
      (node (ref "U$2") (pin "AP1") (pinfunction "1_AP1") (pintype "bidirectional"))
    )
    (net (code "1286") (name "~{MD04}") (class "Default")
      (node (ref "D7") (pin "9") (pinfunction "9_9") (pintype "passive"))
      (node (ref "U$2") (pin "BK1") (pinfunction "1_BK1") (pintype "bidirectional"))
    )
    (net (code "1287") (name "~{MD05}") (class "Default")
      (node (ref "D7") (pin "10") (pinfunction "10_10") (pintype "passive"))
      (node (ref "U$2") (pin "BL1") (pinfunction "1_BL1") (pintype "bidirectional"))
    )
    (net (code "1288") (name "~{MD06}") (class "Default")
      (node (ref "D7") (pin "11") (pinfunction "11_11") (pintype "passive"))
      (node (ref "U$2") (pin "BM1") (pinfunction "1_BM1") (pintype "bidirectional"))
    )
    (net (code "1289") (name "~{MD07}") (class "Default")
      (node (ref "D7") (pin "13") (pinfunction "13_13") (pintype "passive"))
      (node (ref "U$2") (pin "BP1") (pinfunction "1_BP1") (pintype "bidirectional"))
    )
    (net (code "1290") (name "~{MD08}") (class "Default")
      (node (ref "D13") (pin "9") (pinfunction "9_9") (pintype "passive"))
      (node (ref "U$2") (pin "DK1") (pinfunction "1_DK1") (pintype "bidirectional"))
    )
    (net (code "1291") (name "~{MD09}") (class "Default")
      (node (ref "D13") (pin "10") (pinfunction "10_10") (pintype "passive"))
      (node (ref "U$2") (pin "DL1") (pinfunction "1_DL1") (pintype "bidirectional"))
    )
    (net (code "1292") (name "~{MD10}") (class "Default")
      (node (ref "D13") (pin "11") (pinfunction "11_11") (pintype "passive"))
      (node (ref "U$2") (pin "DM1") (pinfunction "1_DM1") (pintype "bidirectional"))
    )
    (net (code "1293") (name "~{MD11}") (class "Default")
      (node (ref "D13") (pin "13") (pinfunction "13_13") (pintype "passive"))
      (node (ref "U$2") (pin "DP1") (pinfunction "1_DP1") (pintype "bidirectional"))
    )
    (net (code "1294") (name "~{MD_DIR}") (class "Default")
      (node (ref "D10") (pin "9") (pinfunction "9_9") (pintype "passive"))
      (node (ref "U$2") (pin "AK2") (pinfunction "1_AK2") (pintype "bidirectional"))
    )
    (net (code "1295") (name "~{MEM_START}") (class "Default")
      (node (ref "D10") (pin "8") (pinfunction "8_8") (pintype "passive"))
      (node (ref "U$2") (pin "AJ2") (pinfunction "1_AJ2") (pintype "bidirectional"))
    )
    (net (code "1296") (name "~{MS_DISABLE}") (class "Default")
      (node (ref "D11") (pin "18") (pinfunction "18_18") (pintype "passive"))
      (node (ref "U$2") (pin "CV1") (pinfunction "1_CV1") (pintype "bidirectional"))
    )
    (net (code "1297") (name "~{NOT_LAST_TR}") (class "Default")
      (node (ref "D11") (pin "11") (pinfunction "11_11") (pintype "passive"))
      (node (ref "U$2") (pin "CM1") (pinfunction "1_CM1") (pintype "bidirectional"))
    )
    (net (code "1298") (name "~{NTS_STALL}") (class "Default")
      (node (ref "D8") (pin "14") (pinfunction "14_14") (pintype "passive"))
      (node (ref "U$2") (pin "BR2") (pinfunction "1_BR2") (pintype "bidirectional"))
    )
    (net (code "1299") (name "~{OVERFLOW}") (class "Default")
      (node (ref "D8") (pin "8") (pinfunction "8_8") (pintype "passive"))
      (node (ref "U$2") (pin "BJ2") (pinfunction "1_BJ2") (pintype "bidirectional"))
    )
    (net (code "1300") (name "~{ROM_ADDR}") (class "Default")
      (node (ref "D10") (pin "17") (pinfunction "17_17") (pintype "passive"))
      (node (ref "U$2") (pin "AU2") (pinfunction "1_AU2") (pintype "bidirectional"))
    )
    (net (code "1301") (name "~{RUN}") (class "Default")
      (node (ref "D8") (pin "17") (pinfunction "17_17") (pintype "passive"))
      (node (ref "U$2") (pin "BU2") (pinfunction "1_BU2") (pintype "bidirectional"))
    )
    (net (code "1302") (name "~{SKIP}") (class "Default")
      (node (ref "D11") (pin "15") (pinfunction "15_15") (pintype "passive"))
      (node (ref "U$2") (pin "CS1") (pinfunction "1_CS1") (pintype "bidirectional"))
    )
    (net (code "1303") (name "~{STOP}") (class "Default")
      (node (ref "D14") (pin "15") (pinfunction "15_15") (pintype "passive"))
      (node (ref "U$2") (pin "DS2") (pinfunction "1_DS2") (pintype "bidirectional"))
    )
    (net (code "1304") (name "~{TS1}") (class "Default")
      (node (ref "D12") (pin "9") (pinfunction "9_9") (pintype "passive"))
      (node (ref "U$2") (pin "CK2") (pinfunction "1_CK2") (pintype "bidirectional"))
    )
    (net (code "1305") (name "~{TS2}") (class "Default")
      (node (ref "D12") (pin "10") (pinfunction "10_10") (pintype "passive"))
      (node (ref "U$2") (pin "CL2") (pinfunction "1_CL2") (pintype "bidirectional"))
    )
    (net (code "1306") (name "~{TS3}") (class "Default")
      (node (ref "D12") (pin "11") (pinfunction "11_11") (pintype "passive"))
      (node (ref "U$2") (pin "CM2") (pinfunction "1_CM2") (pintype "bidirectional"))
    )
    (net (code "1307") (name "~{TS4}") (class "Default")
      (node (ref "D12") (pin "13") (pinfunction "13_13") (pintype "passive"))
      (node (ref "U$2") (pin "CP2") (pinfunction "1_CP2") (pintype "bidirectional"))
    )
    (net (code "1308") (name "~{USER_MODE}") (class "Default")
      (node (ref "D14") (pin "11") (pinfunction "11_11") (pintype "passive"))
      (node (ref "U$2") (pin "DM2") (pinfunction "1_DM2") (pintype "bidirectional"))
    )
  )
)
